# 8BIT_ADD_SUB.net
KiCad netlist of a schematic drawn in EAGLE
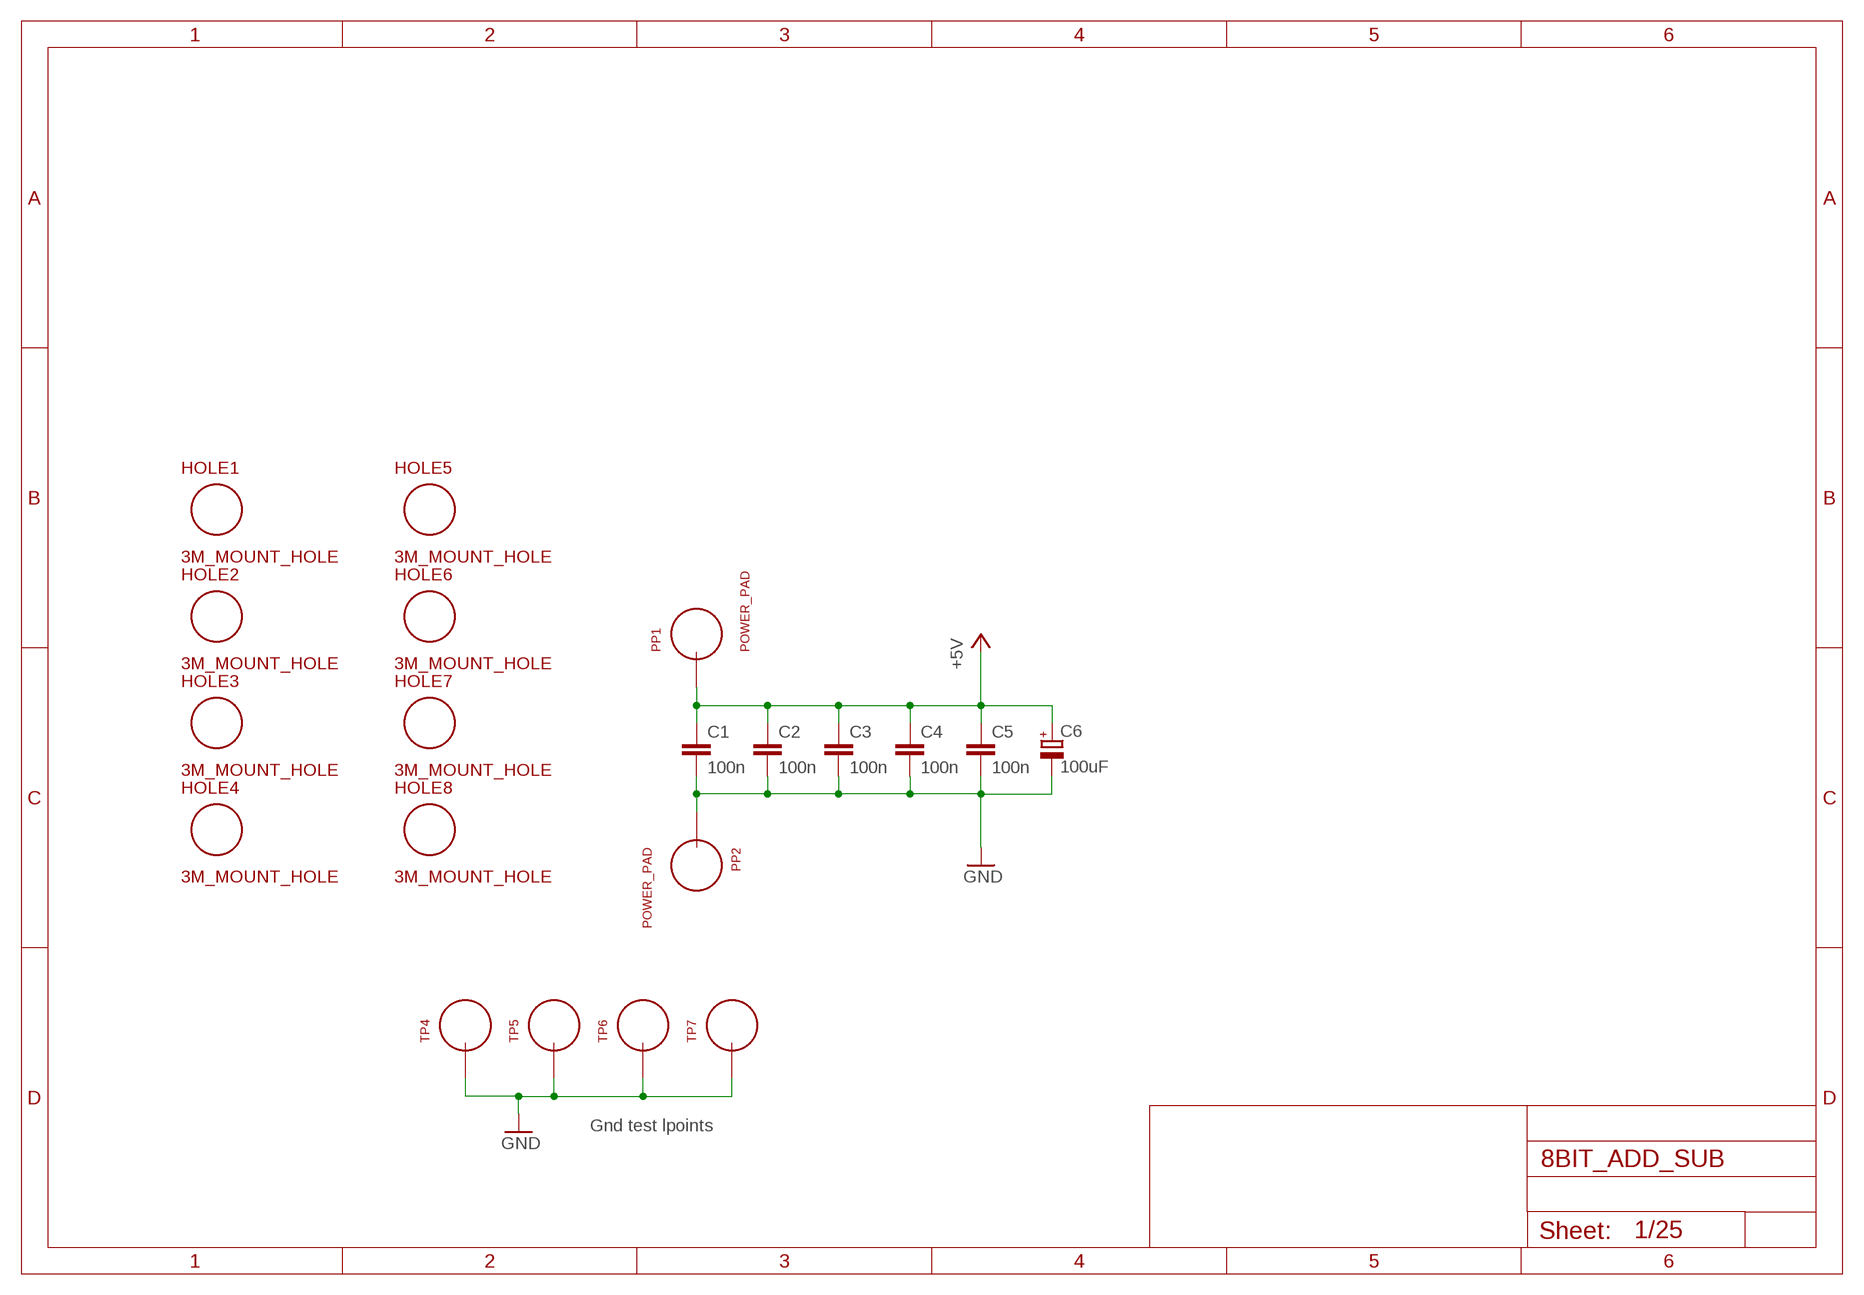
[diagram p0: schematic, sheet 1]
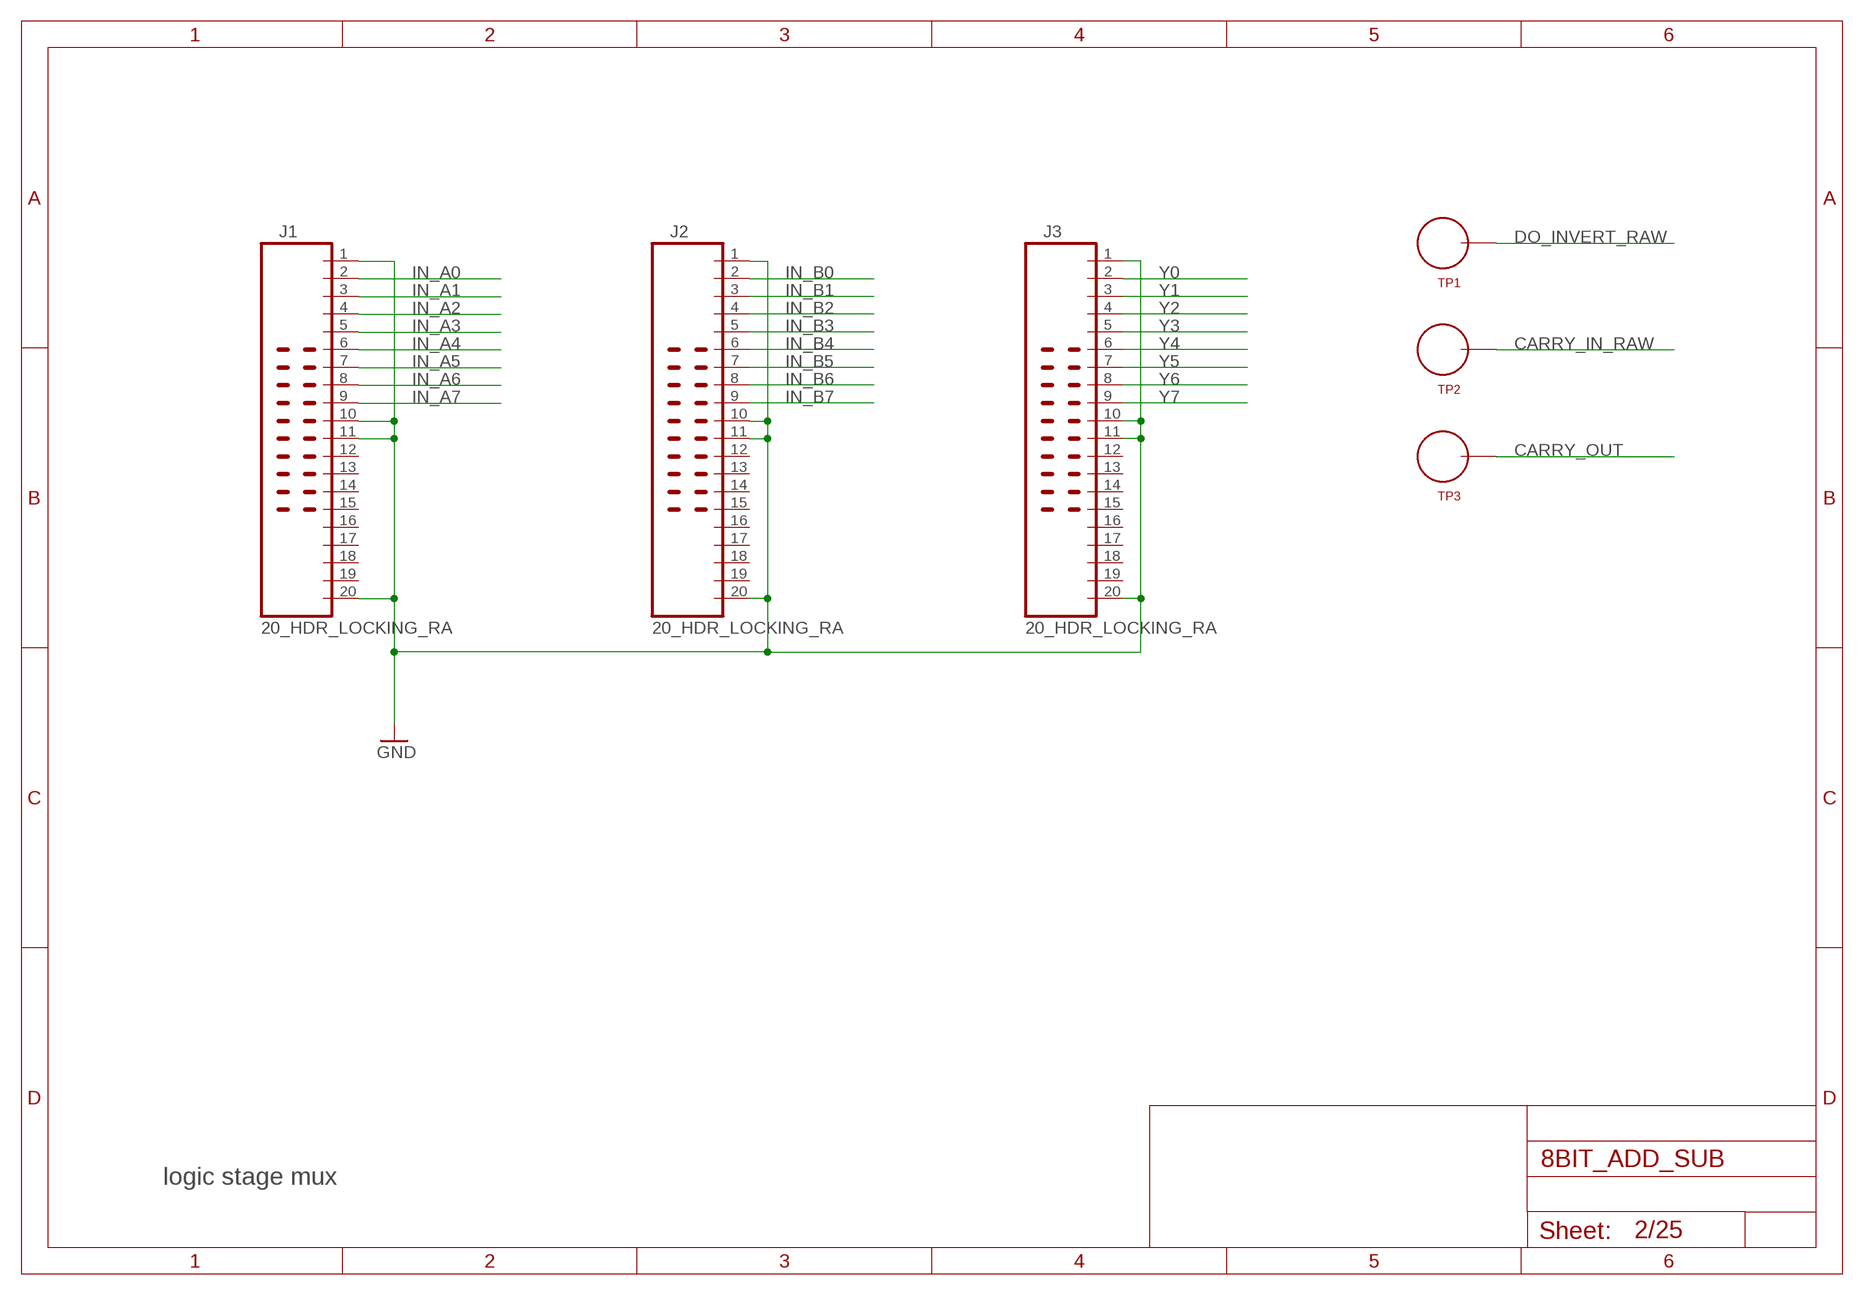
[diagram p1: schematic, sheet 2]
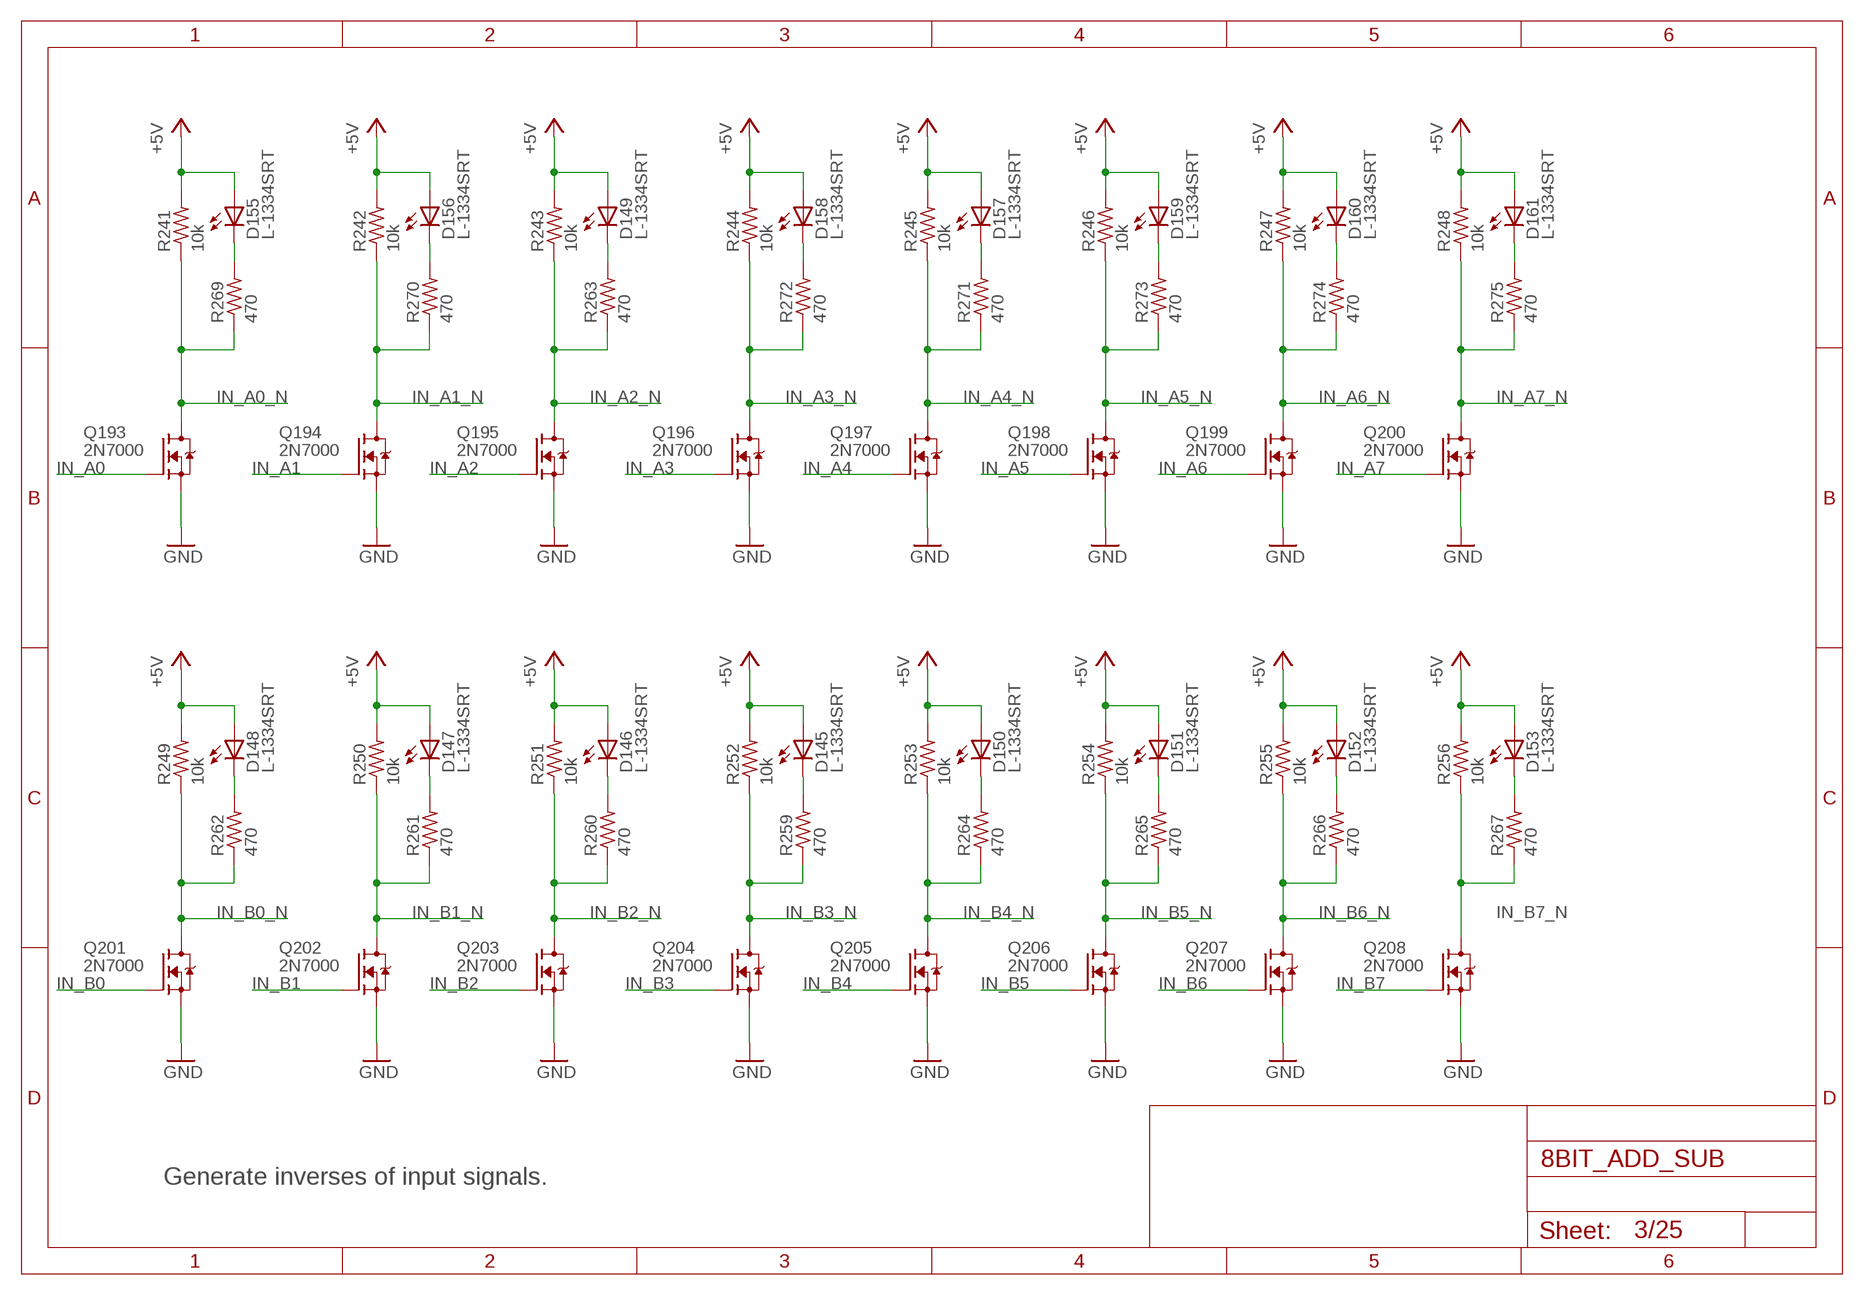
[diagram p2: schematic, sheet 3]
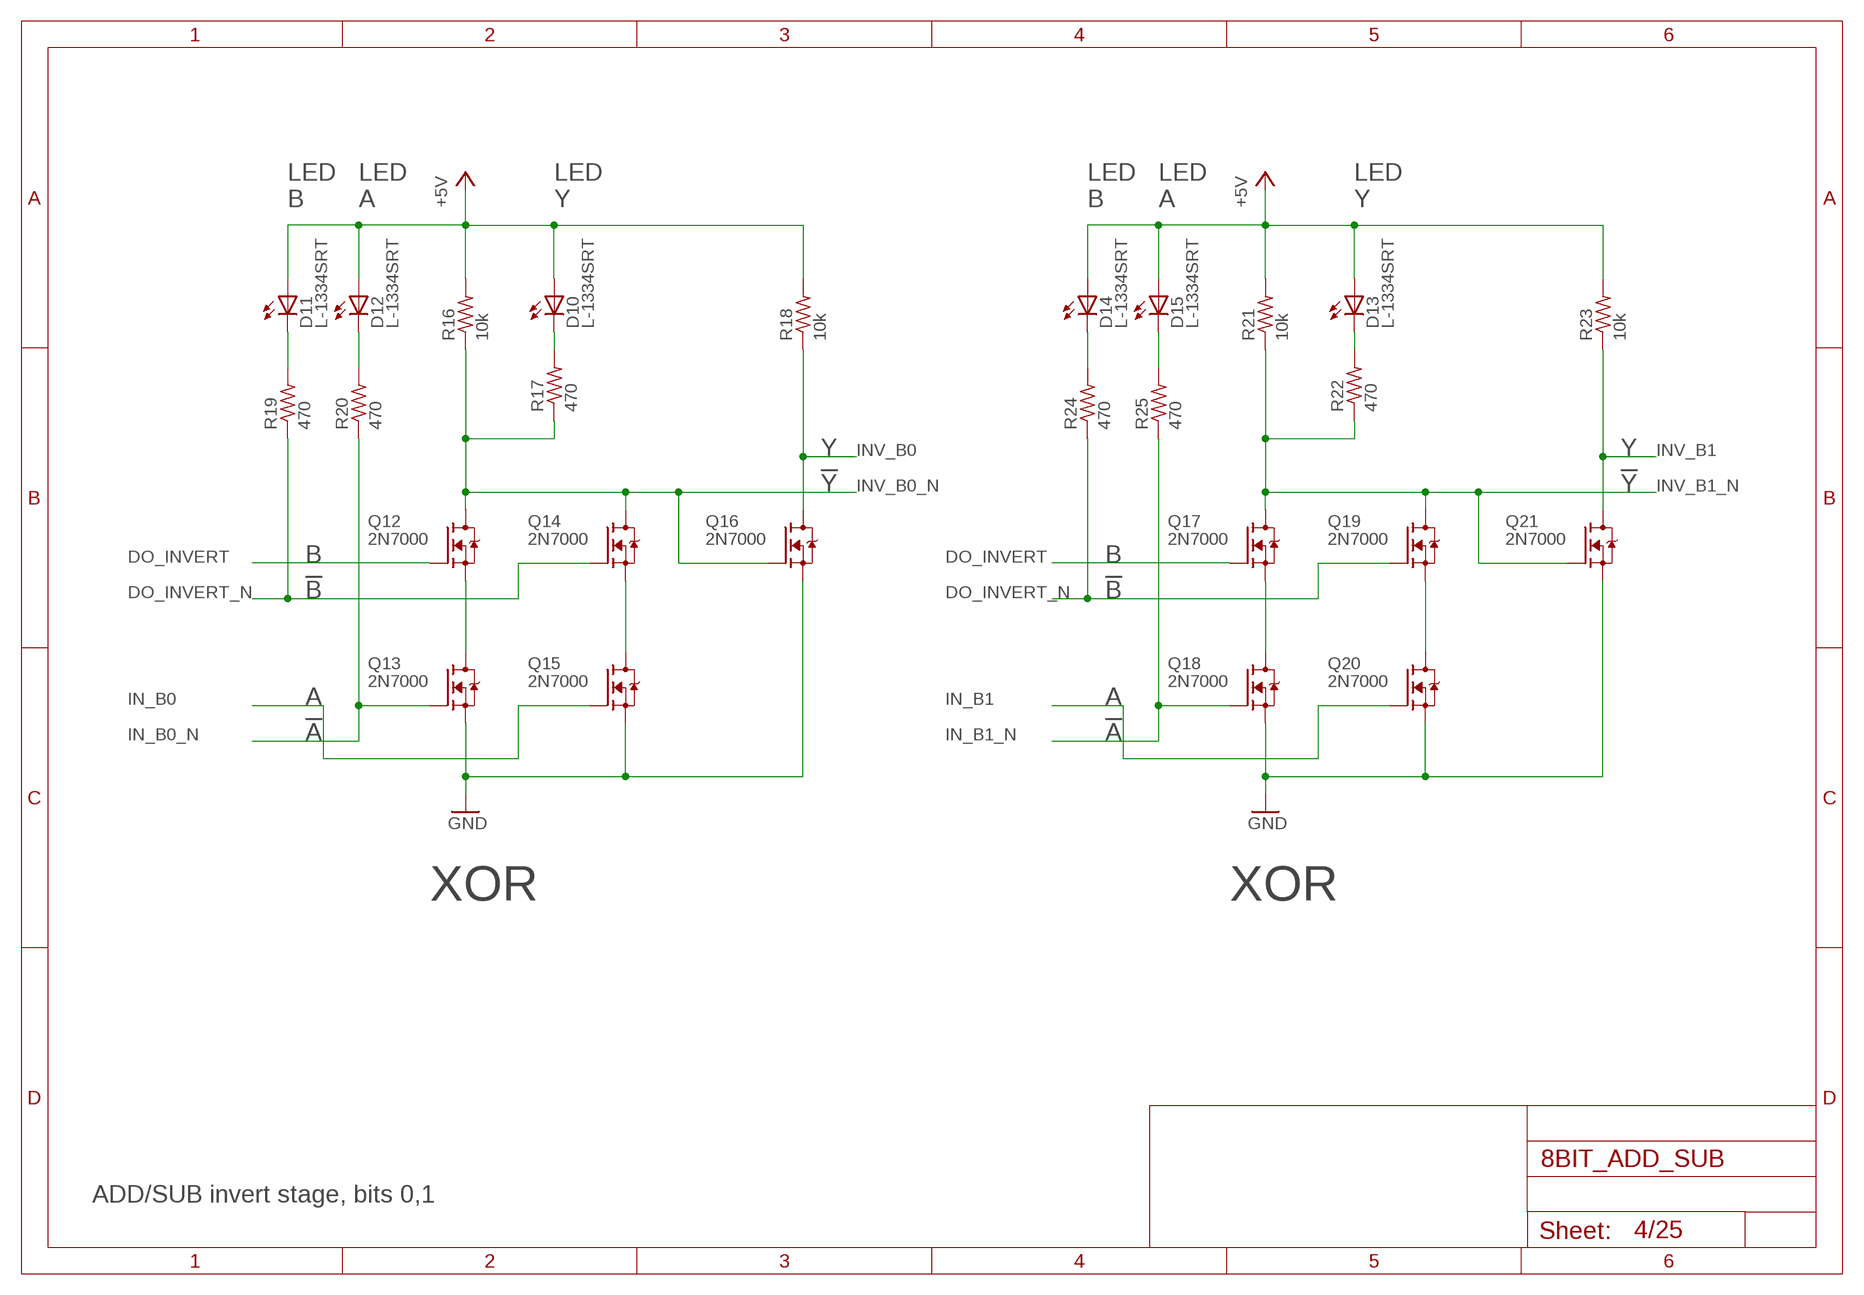
[diagram p3: schematic, sheet 4]
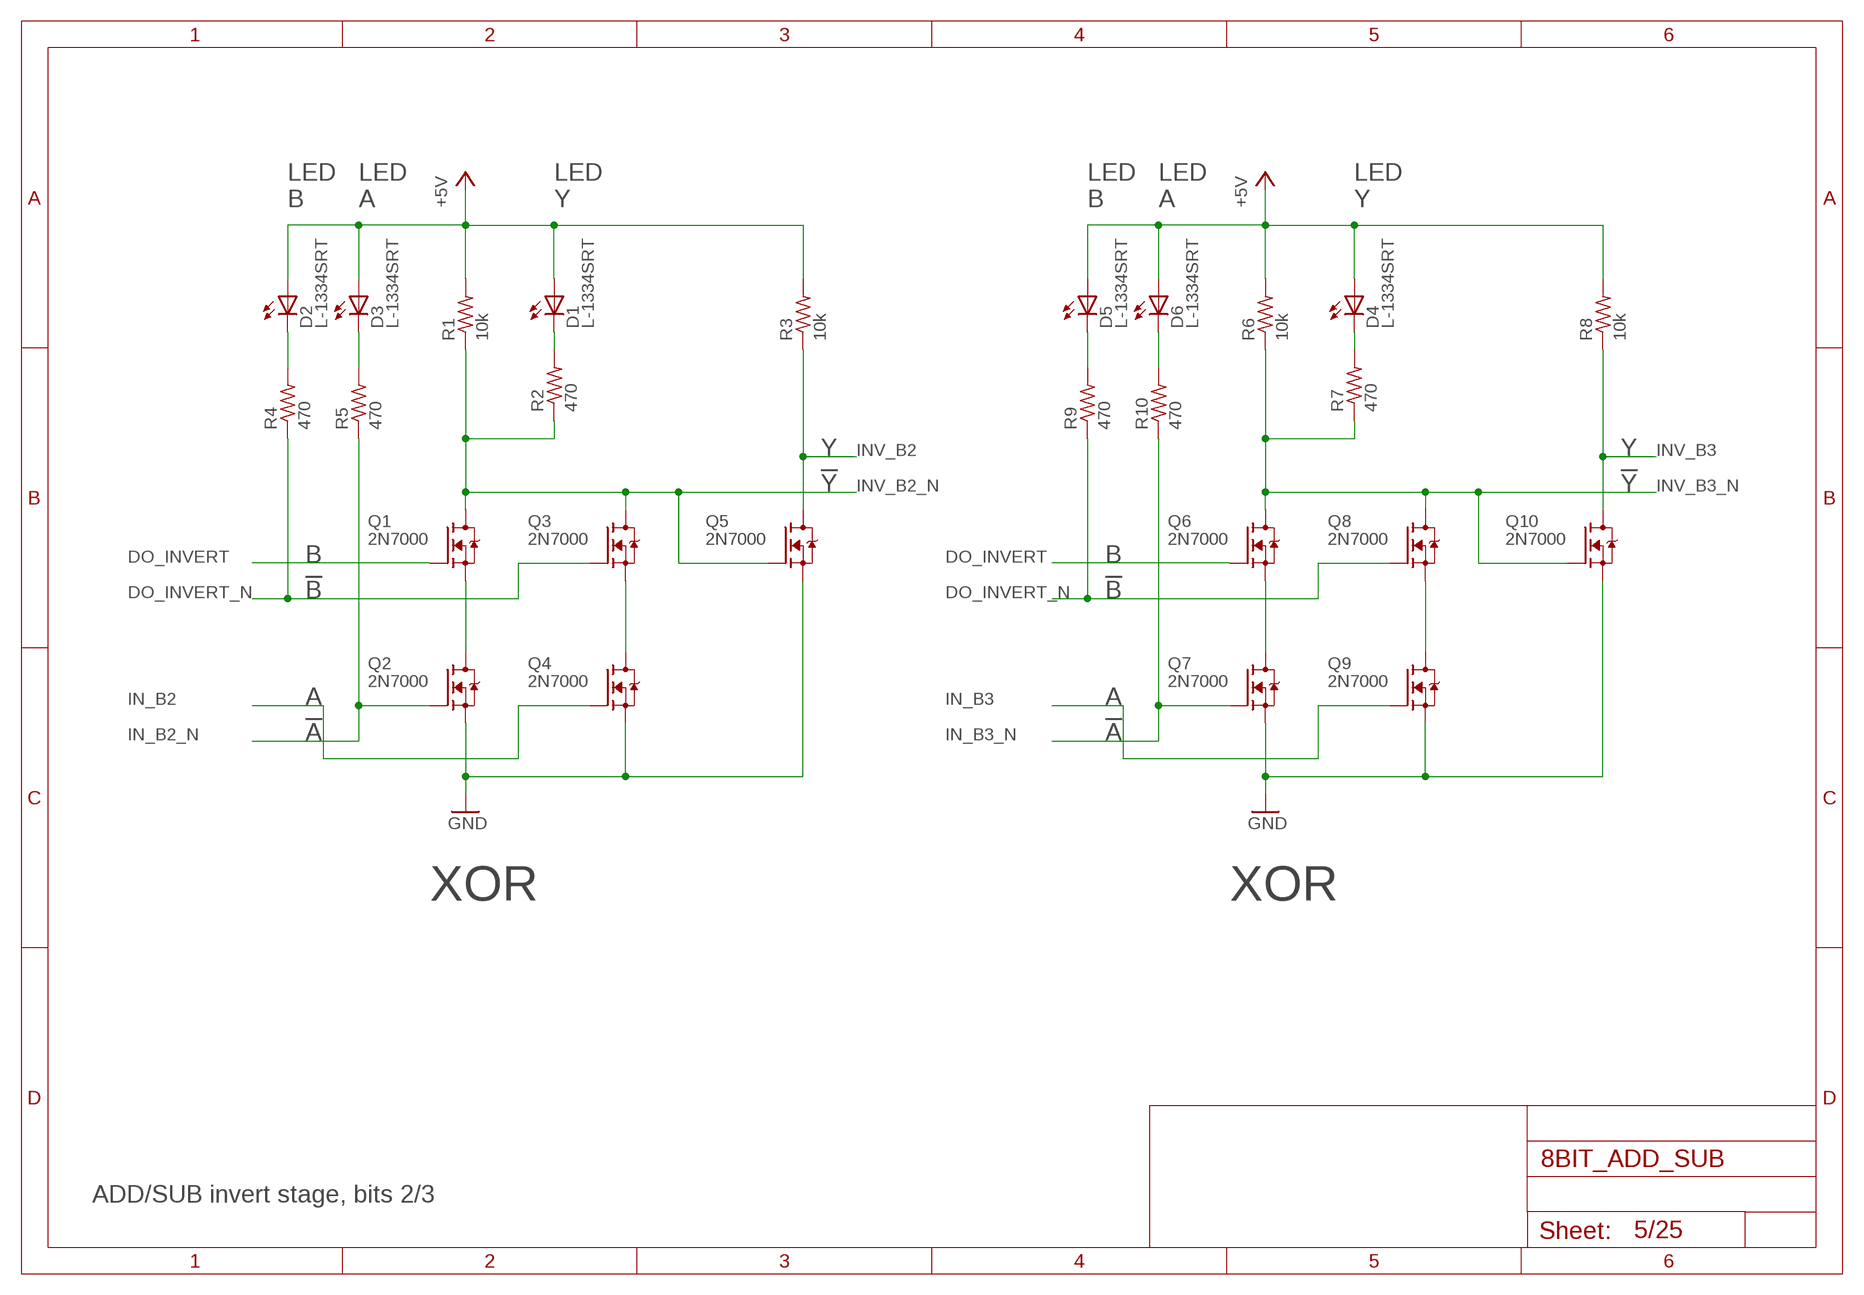
[diagram p4: schematic, sheet 5]
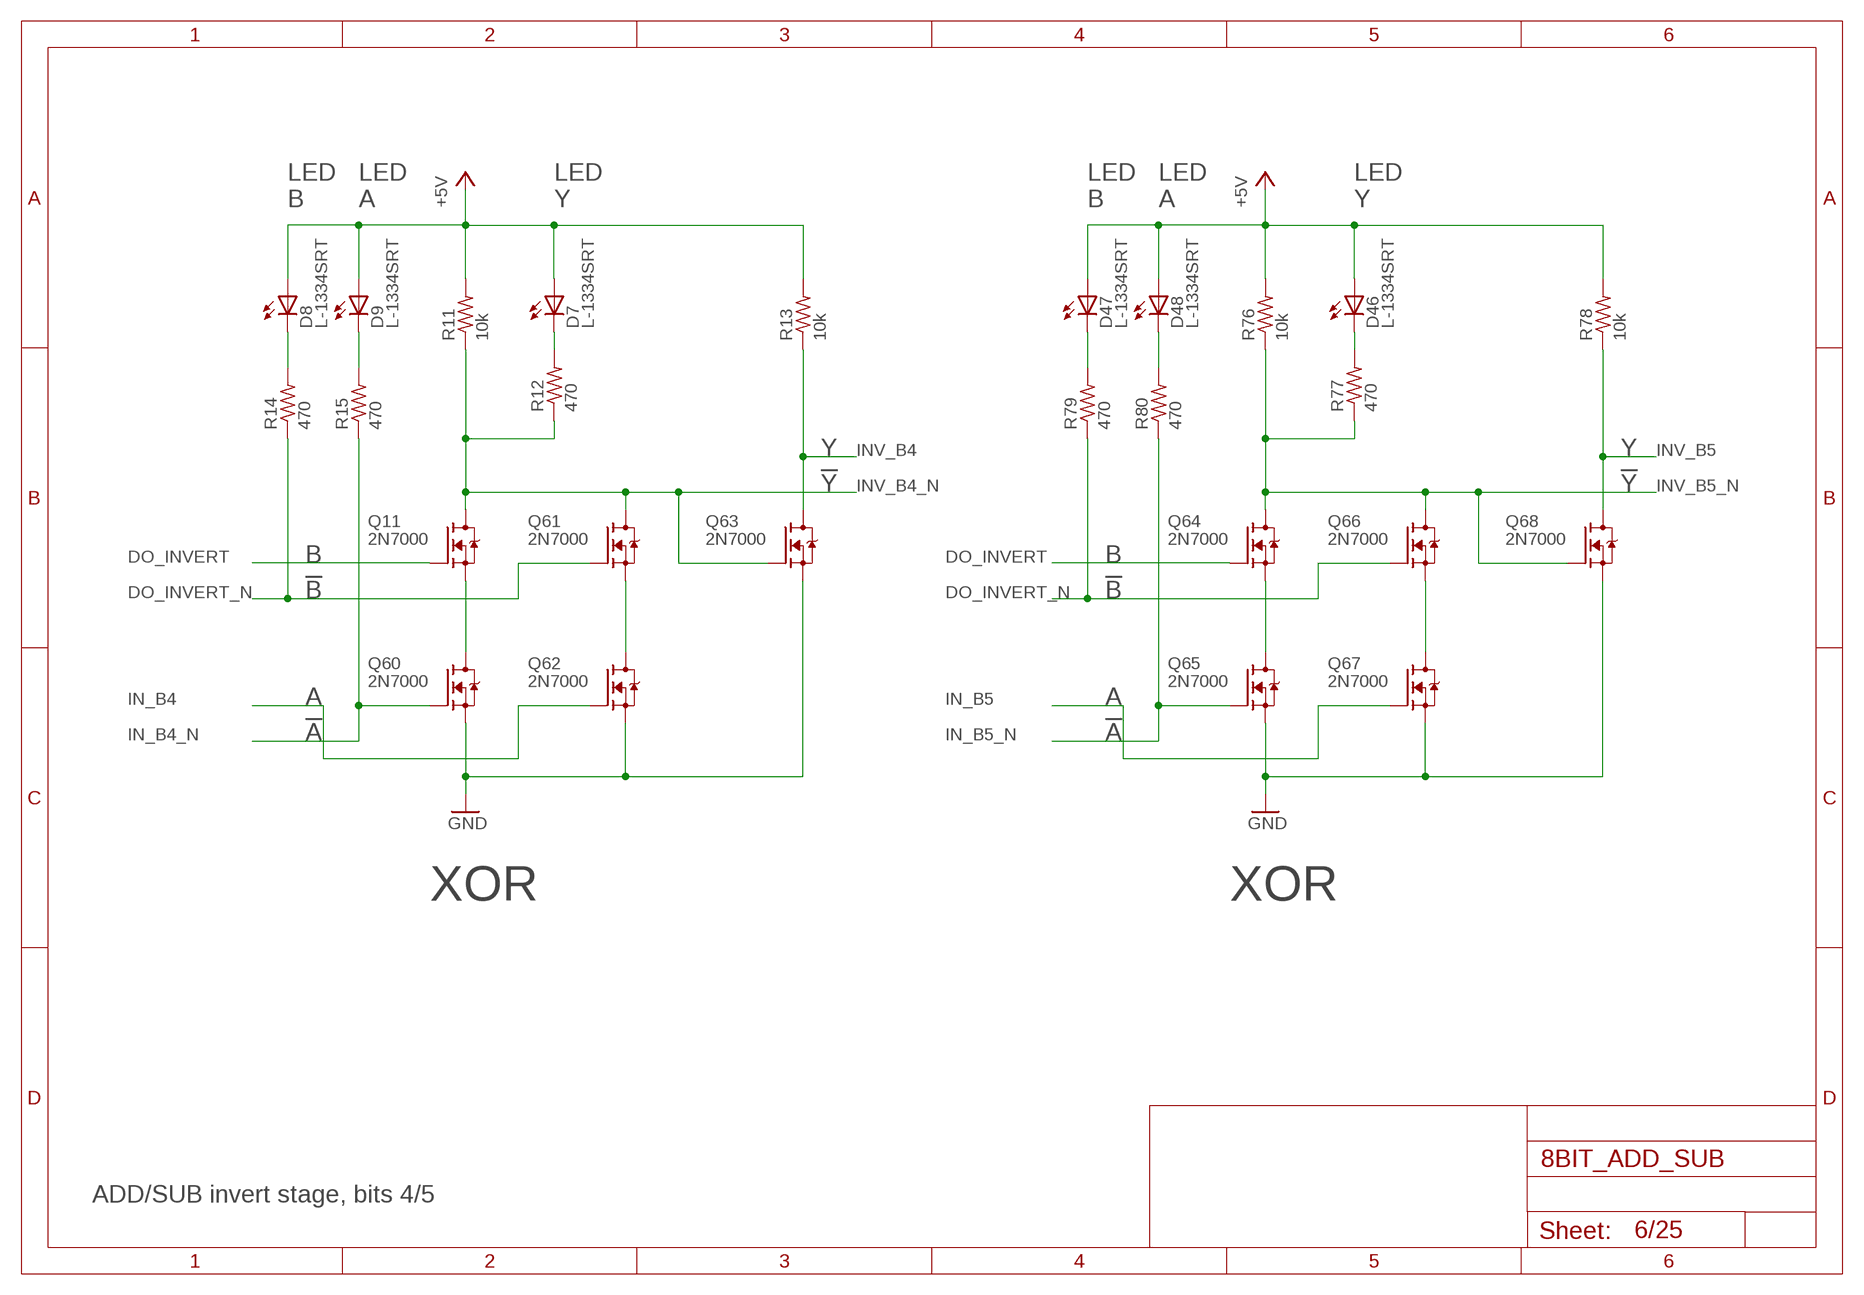
[diagram p5: schematic, sheet 6]
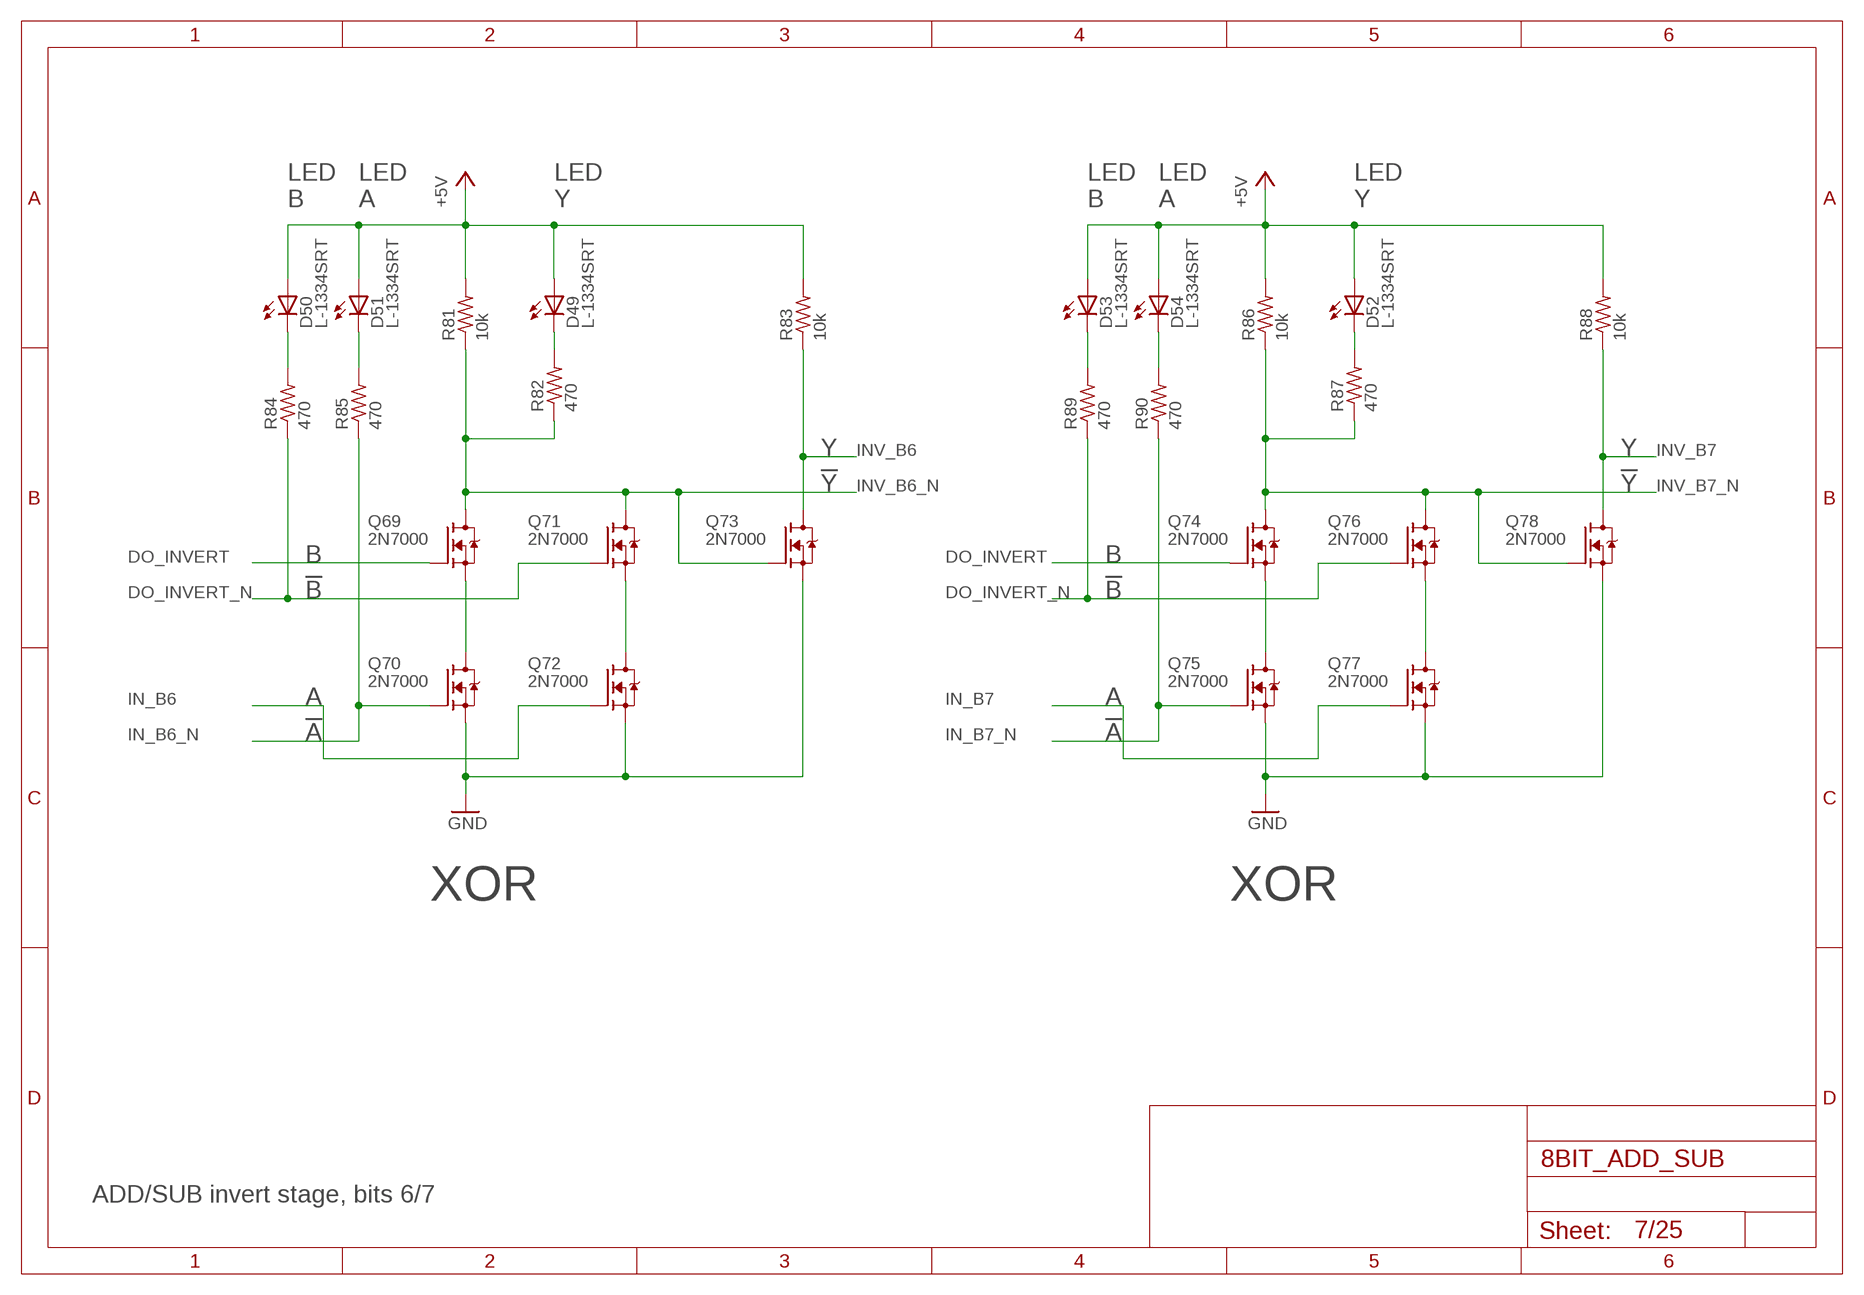
[diagram p6: schematic, sheet 7]
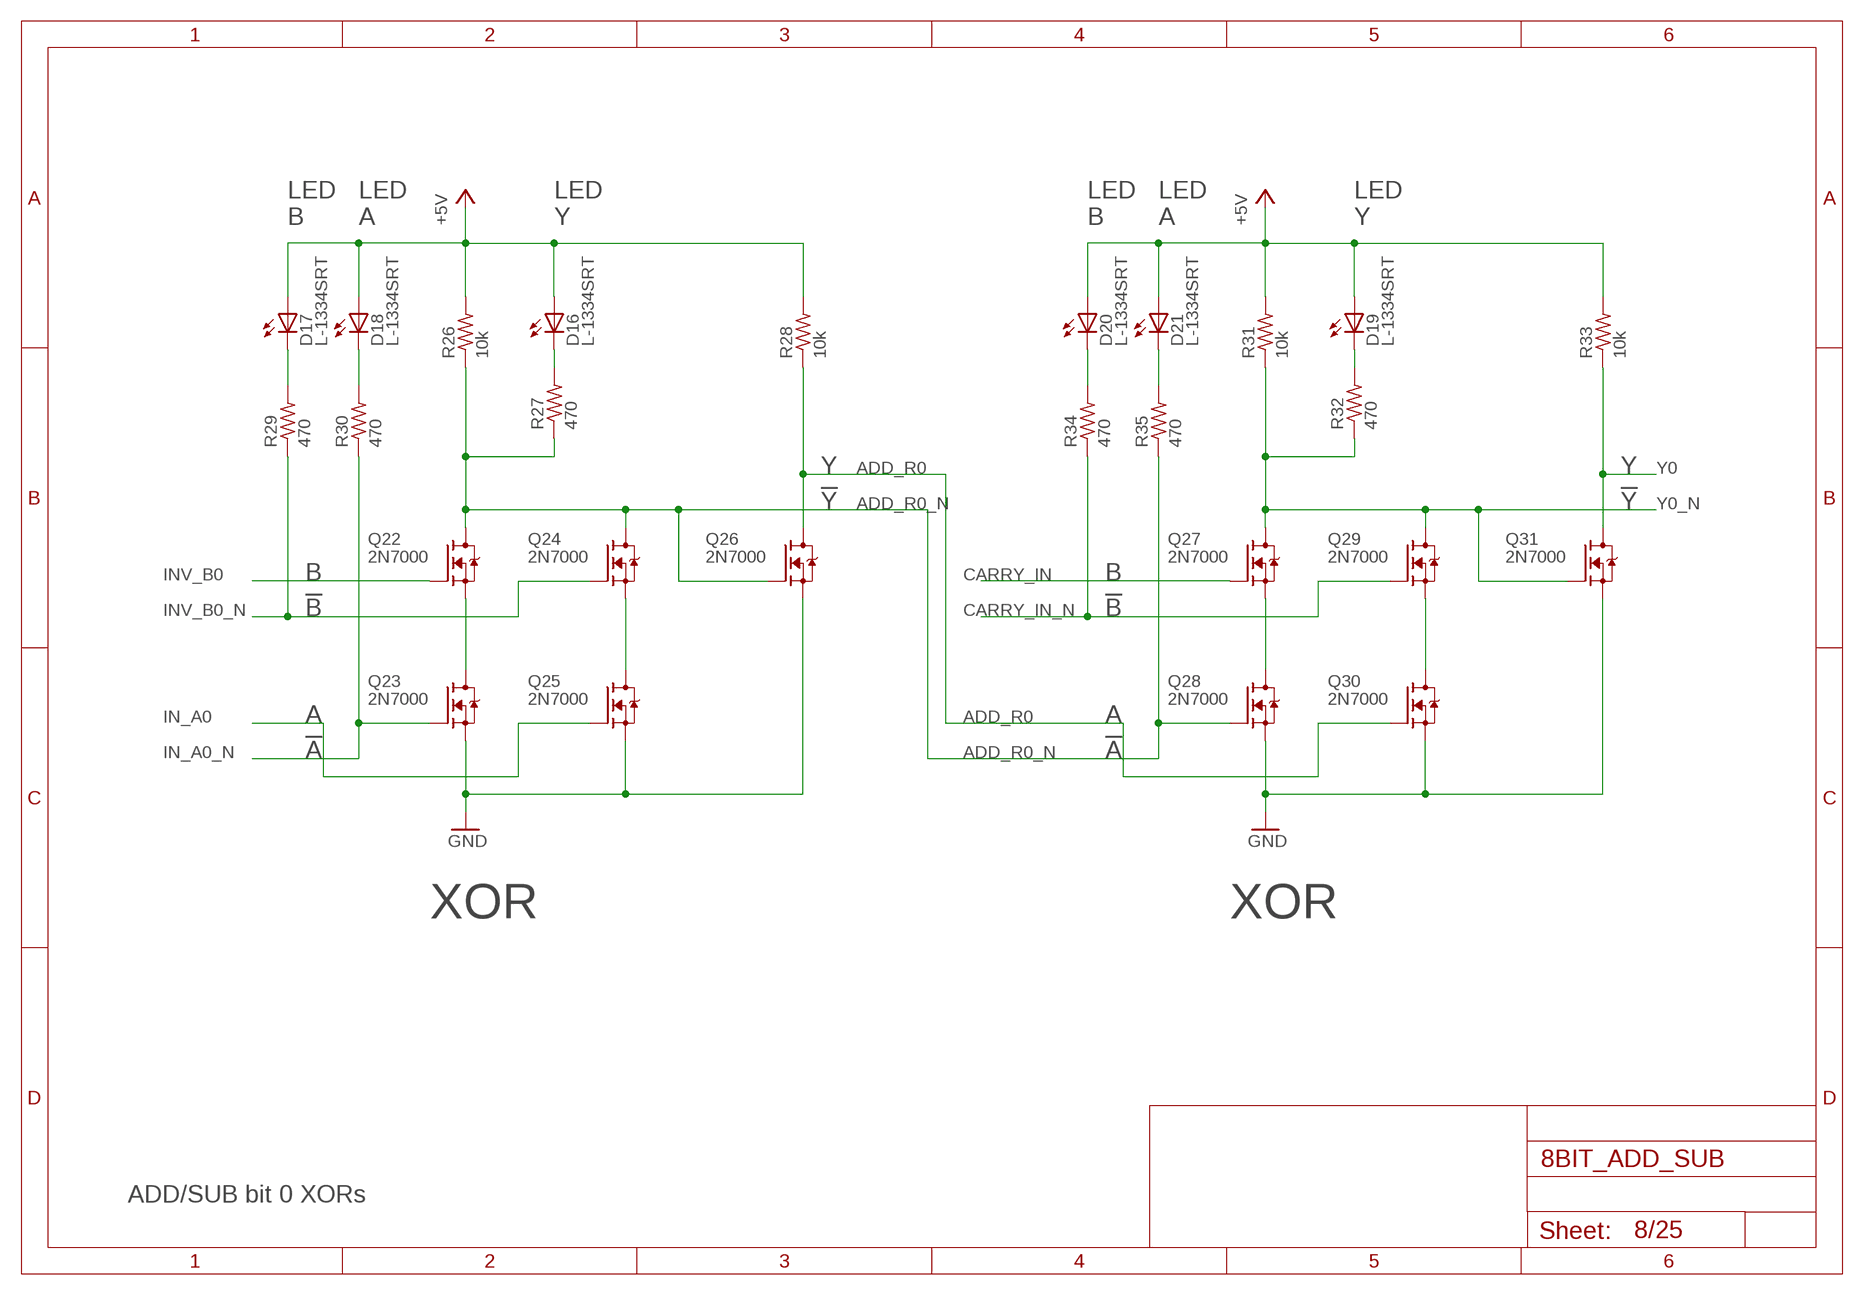
[diagram p7: schematic, sheet 8]
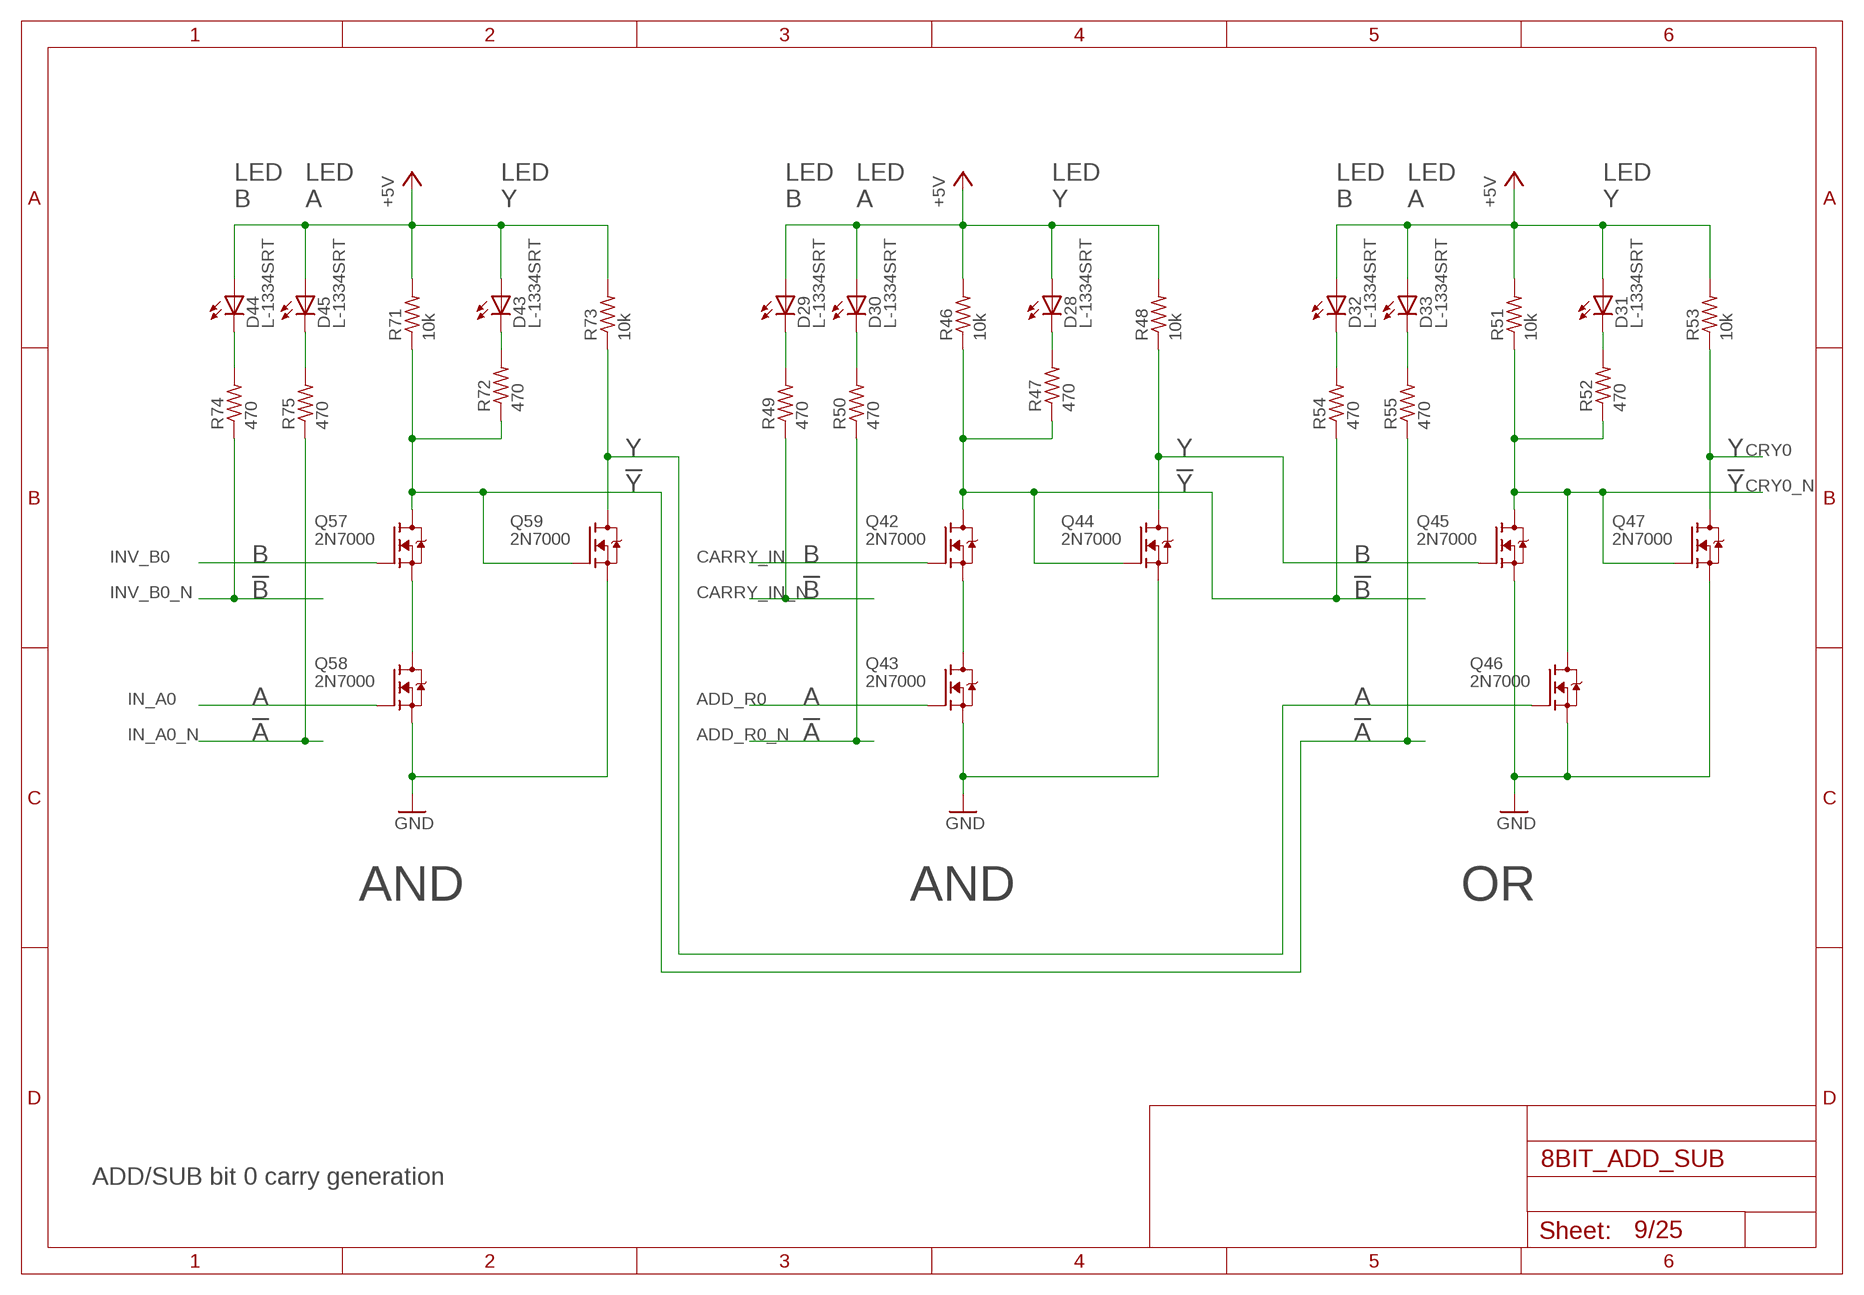
[diagram p8: schematic, sheet 9]
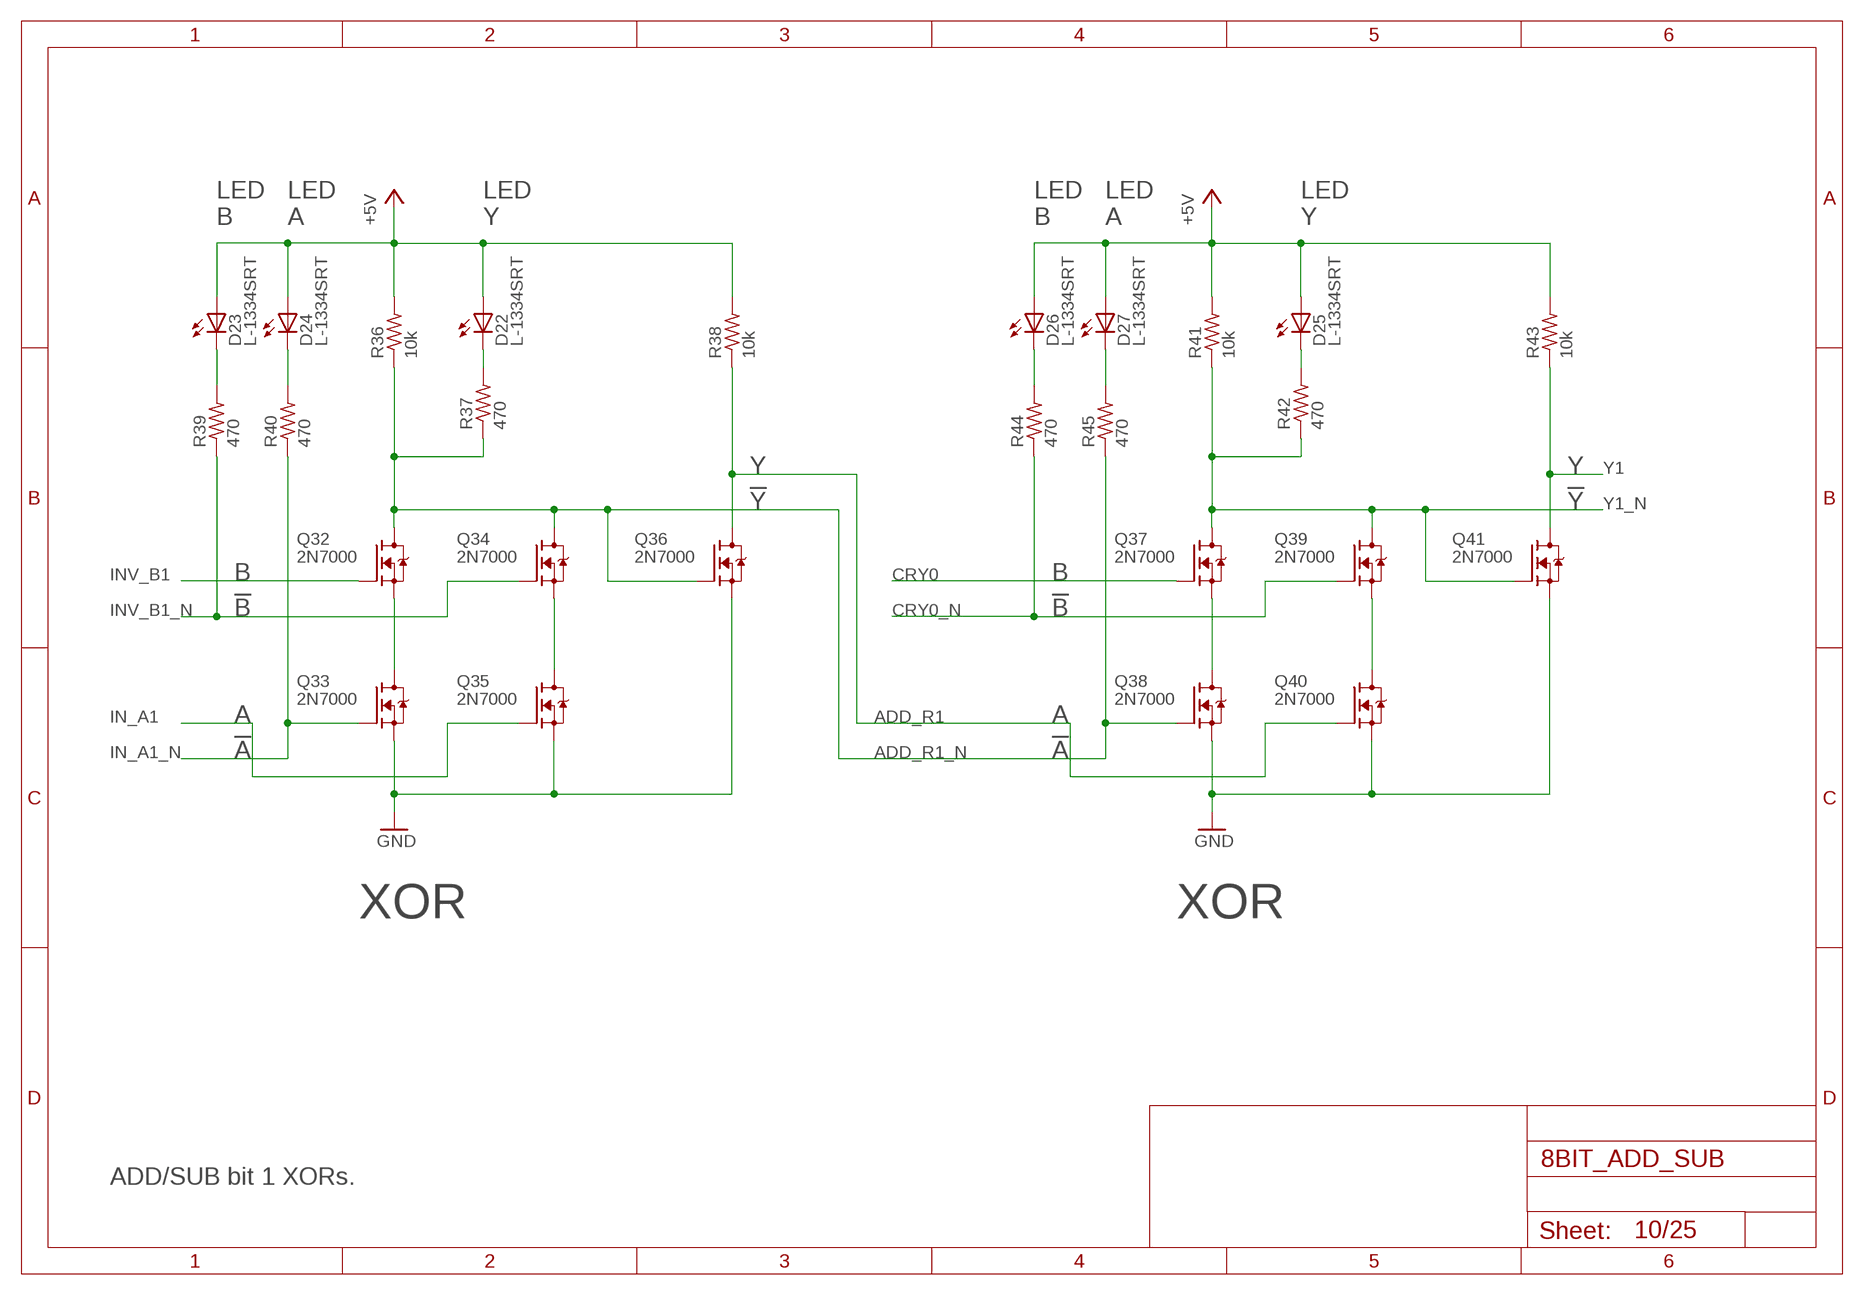
[diagram p9: schematic, sheet 10]
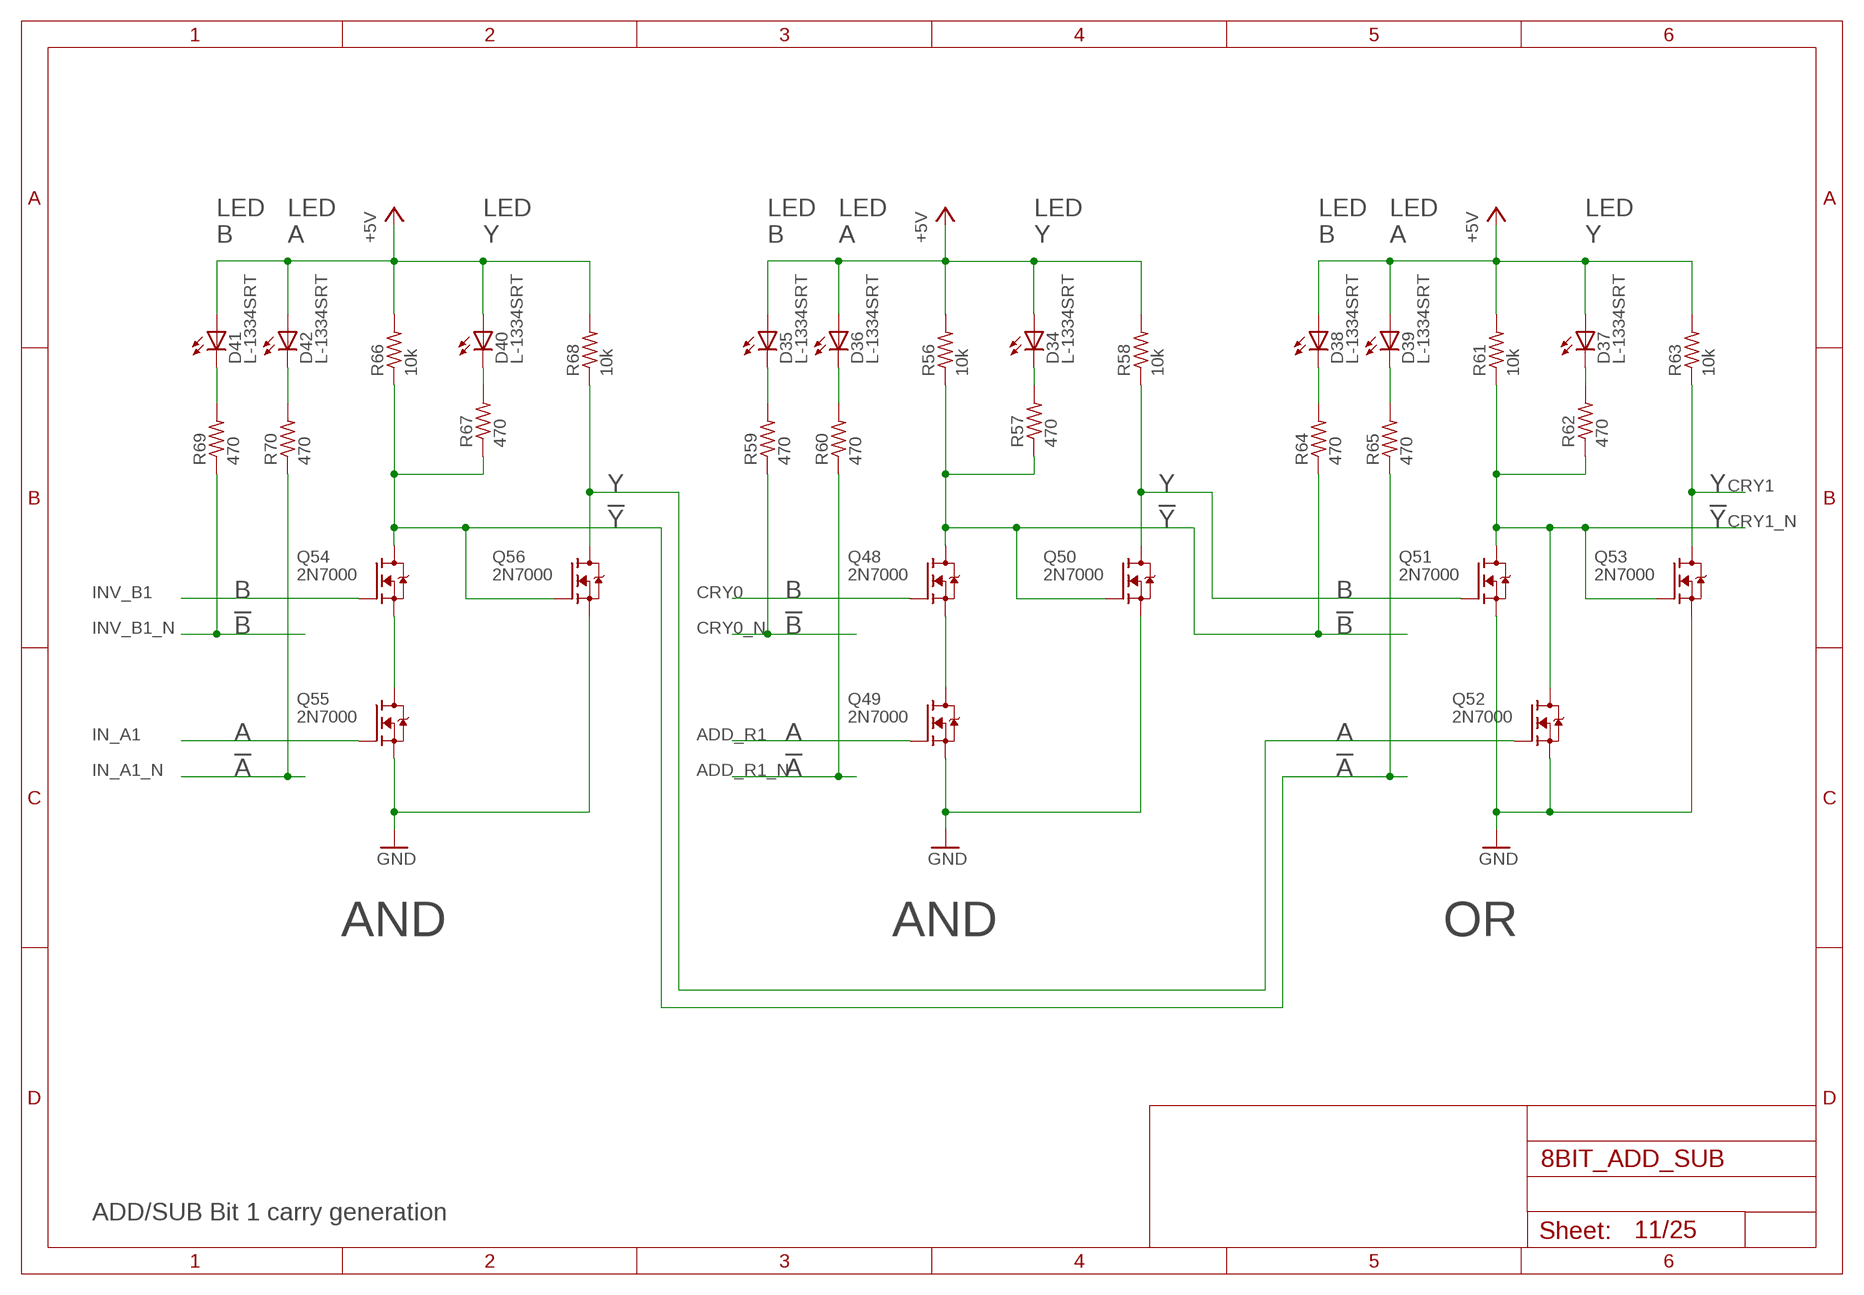
[diagram p10: schematic, sheet 11]
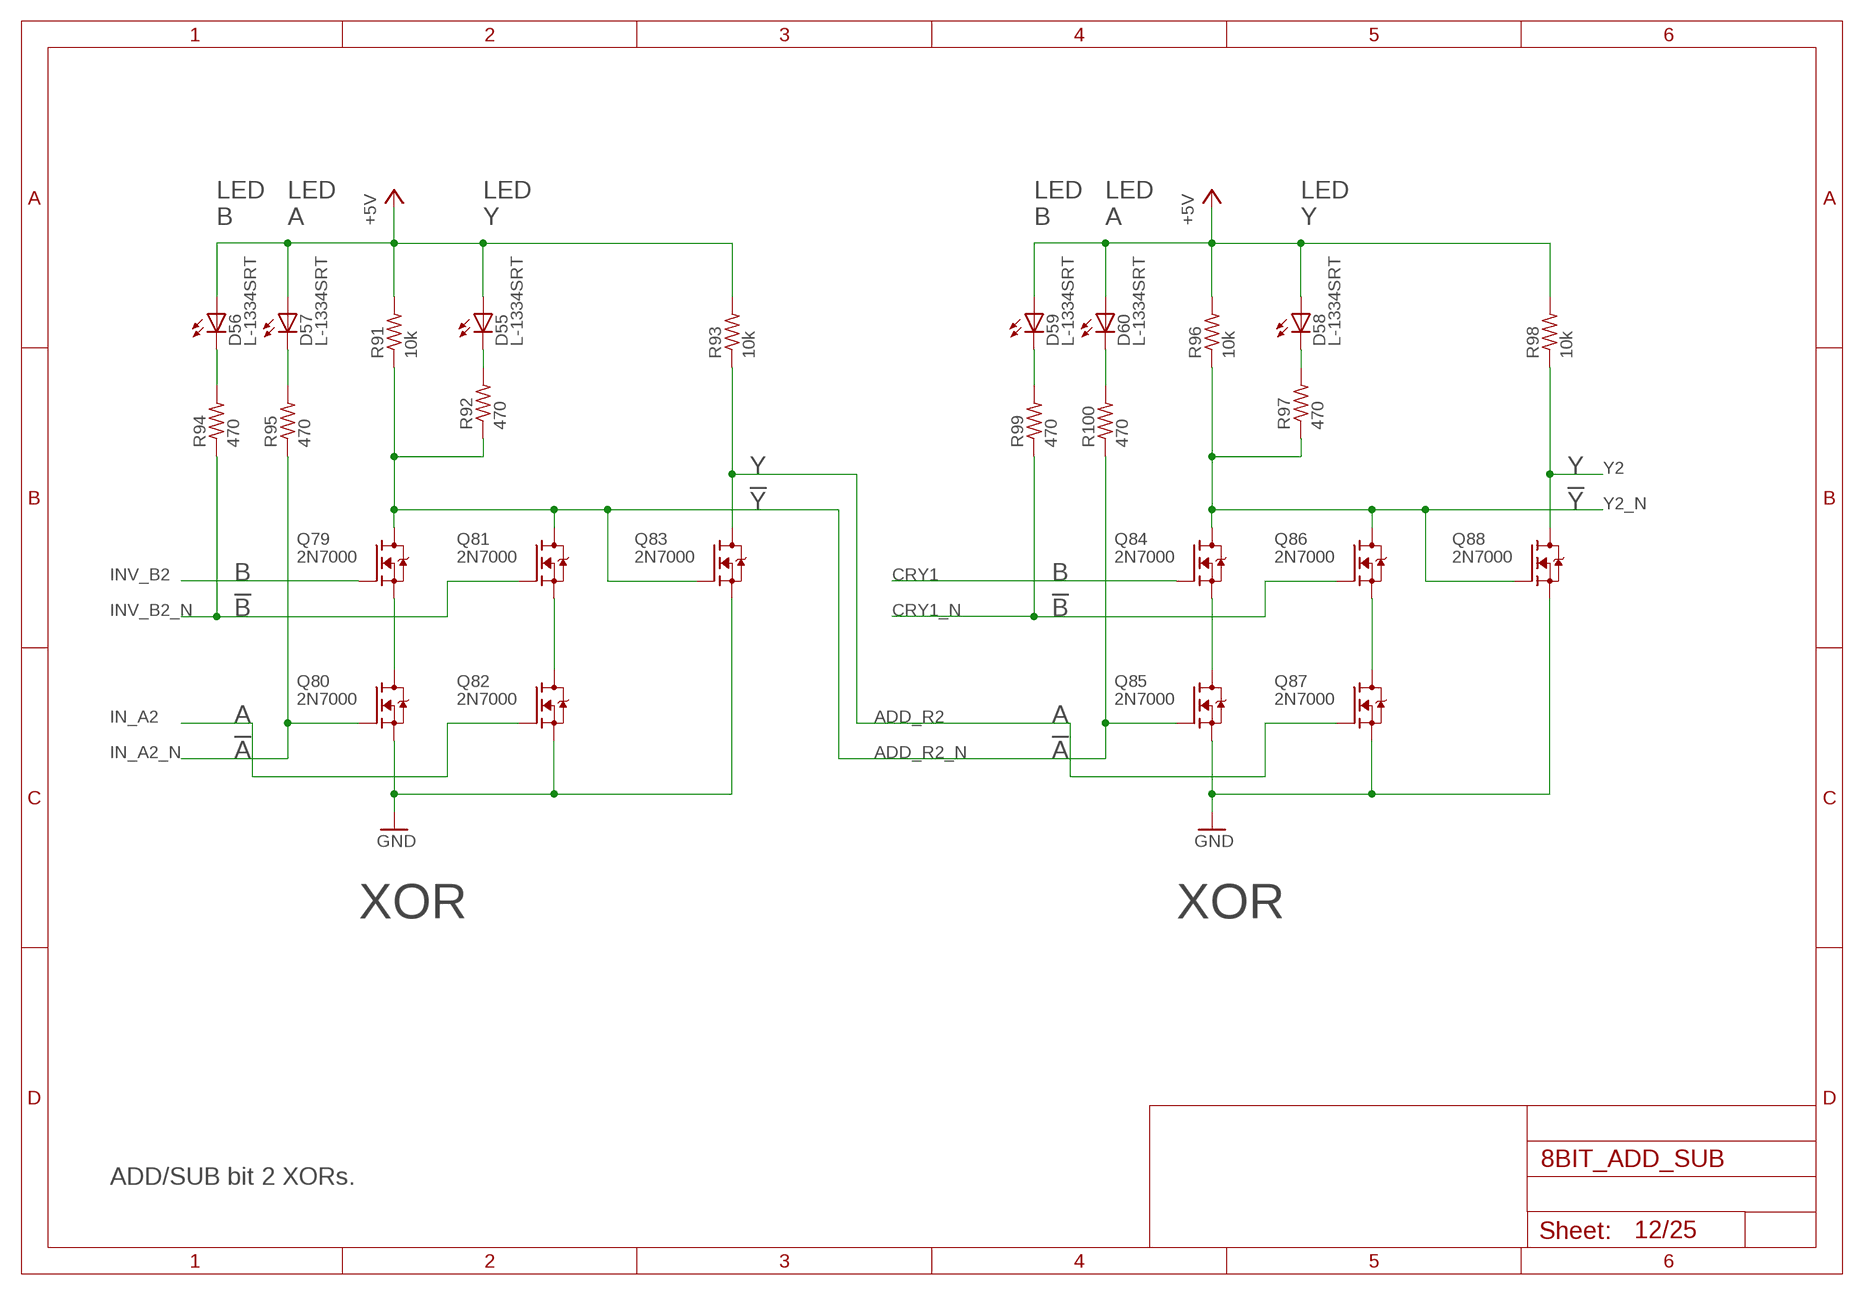
[diagram p11: schematic, sheet 12]
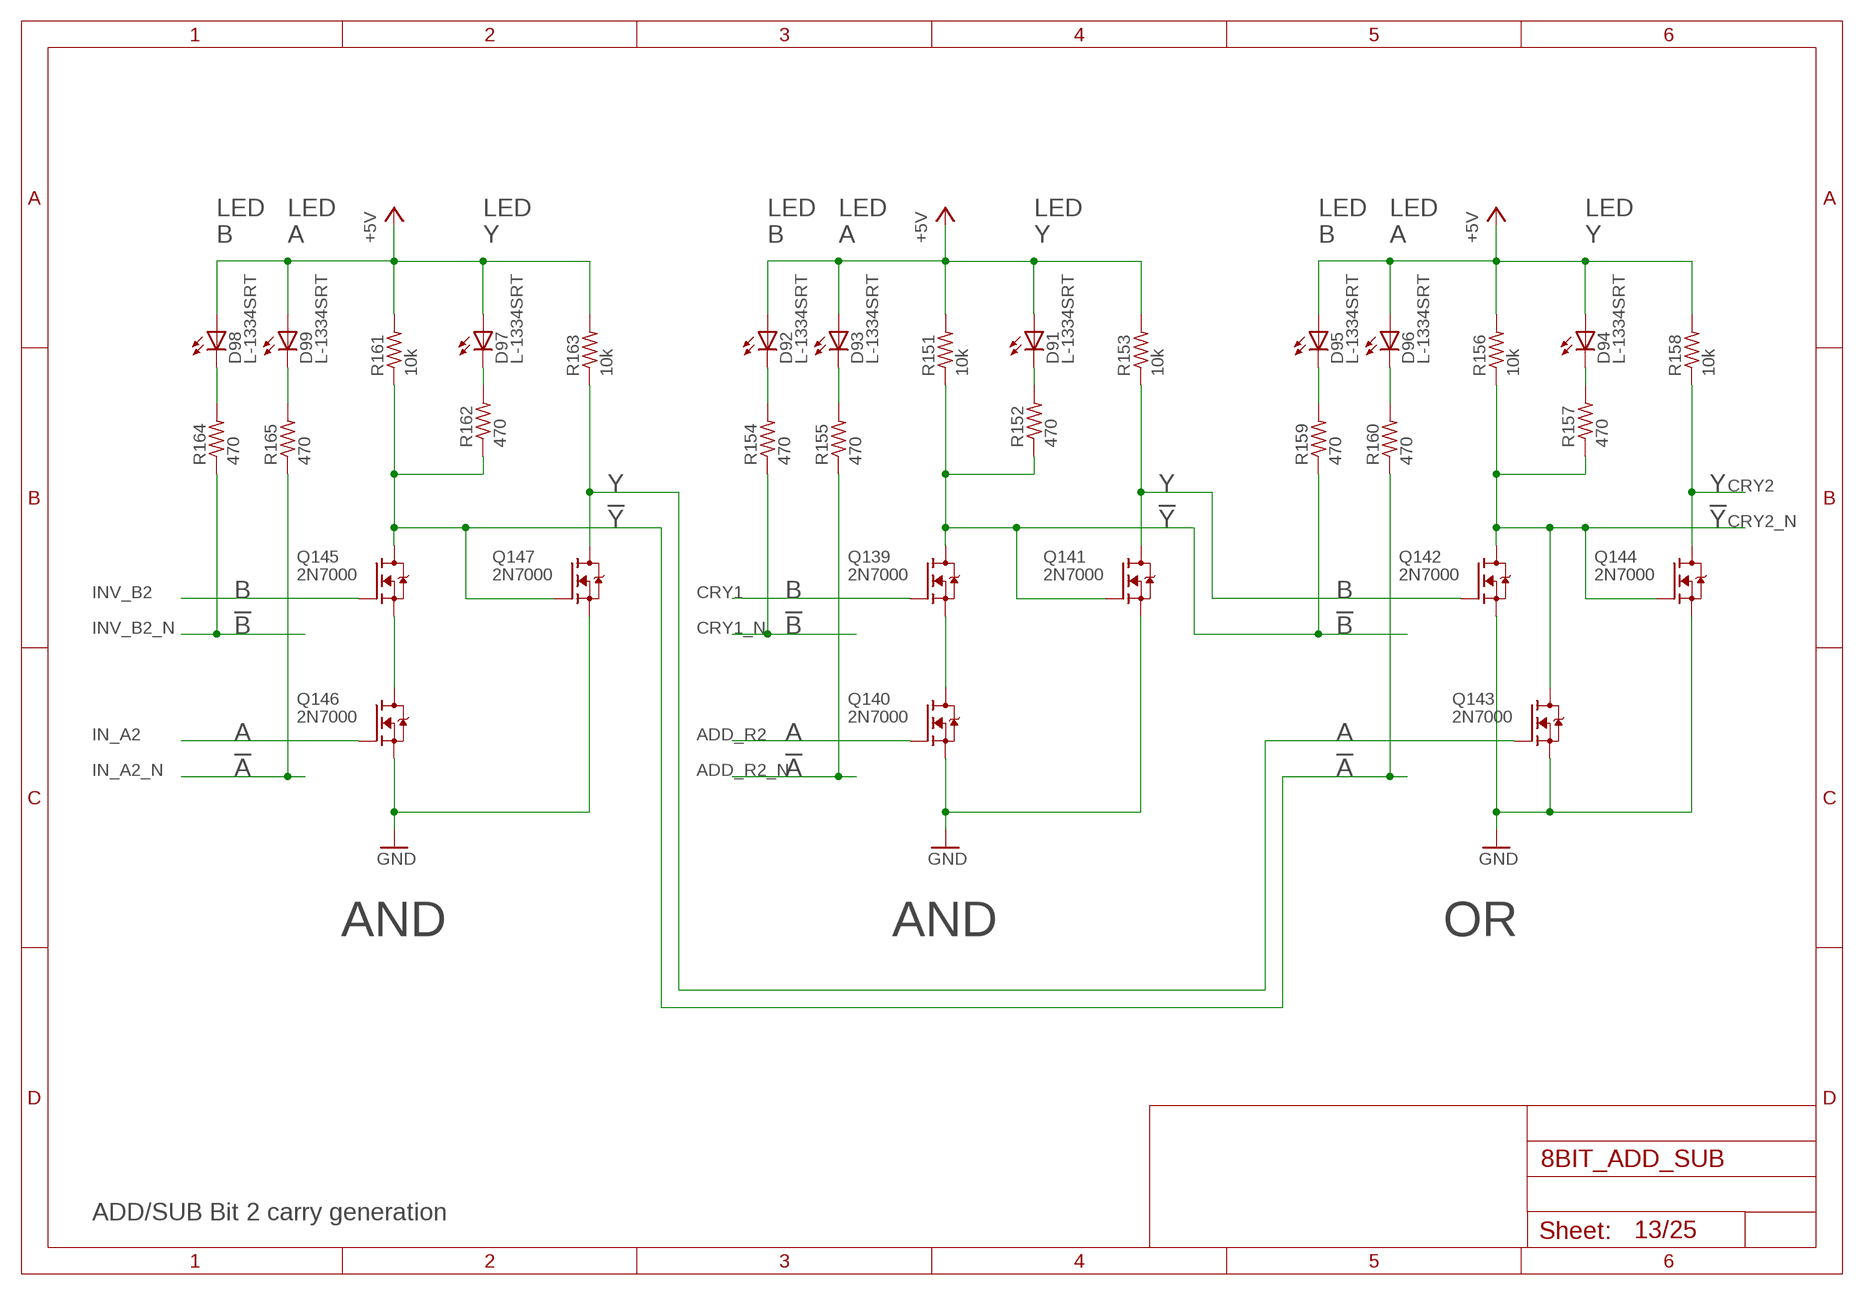
[diagram p12: schematic, sheet 13]
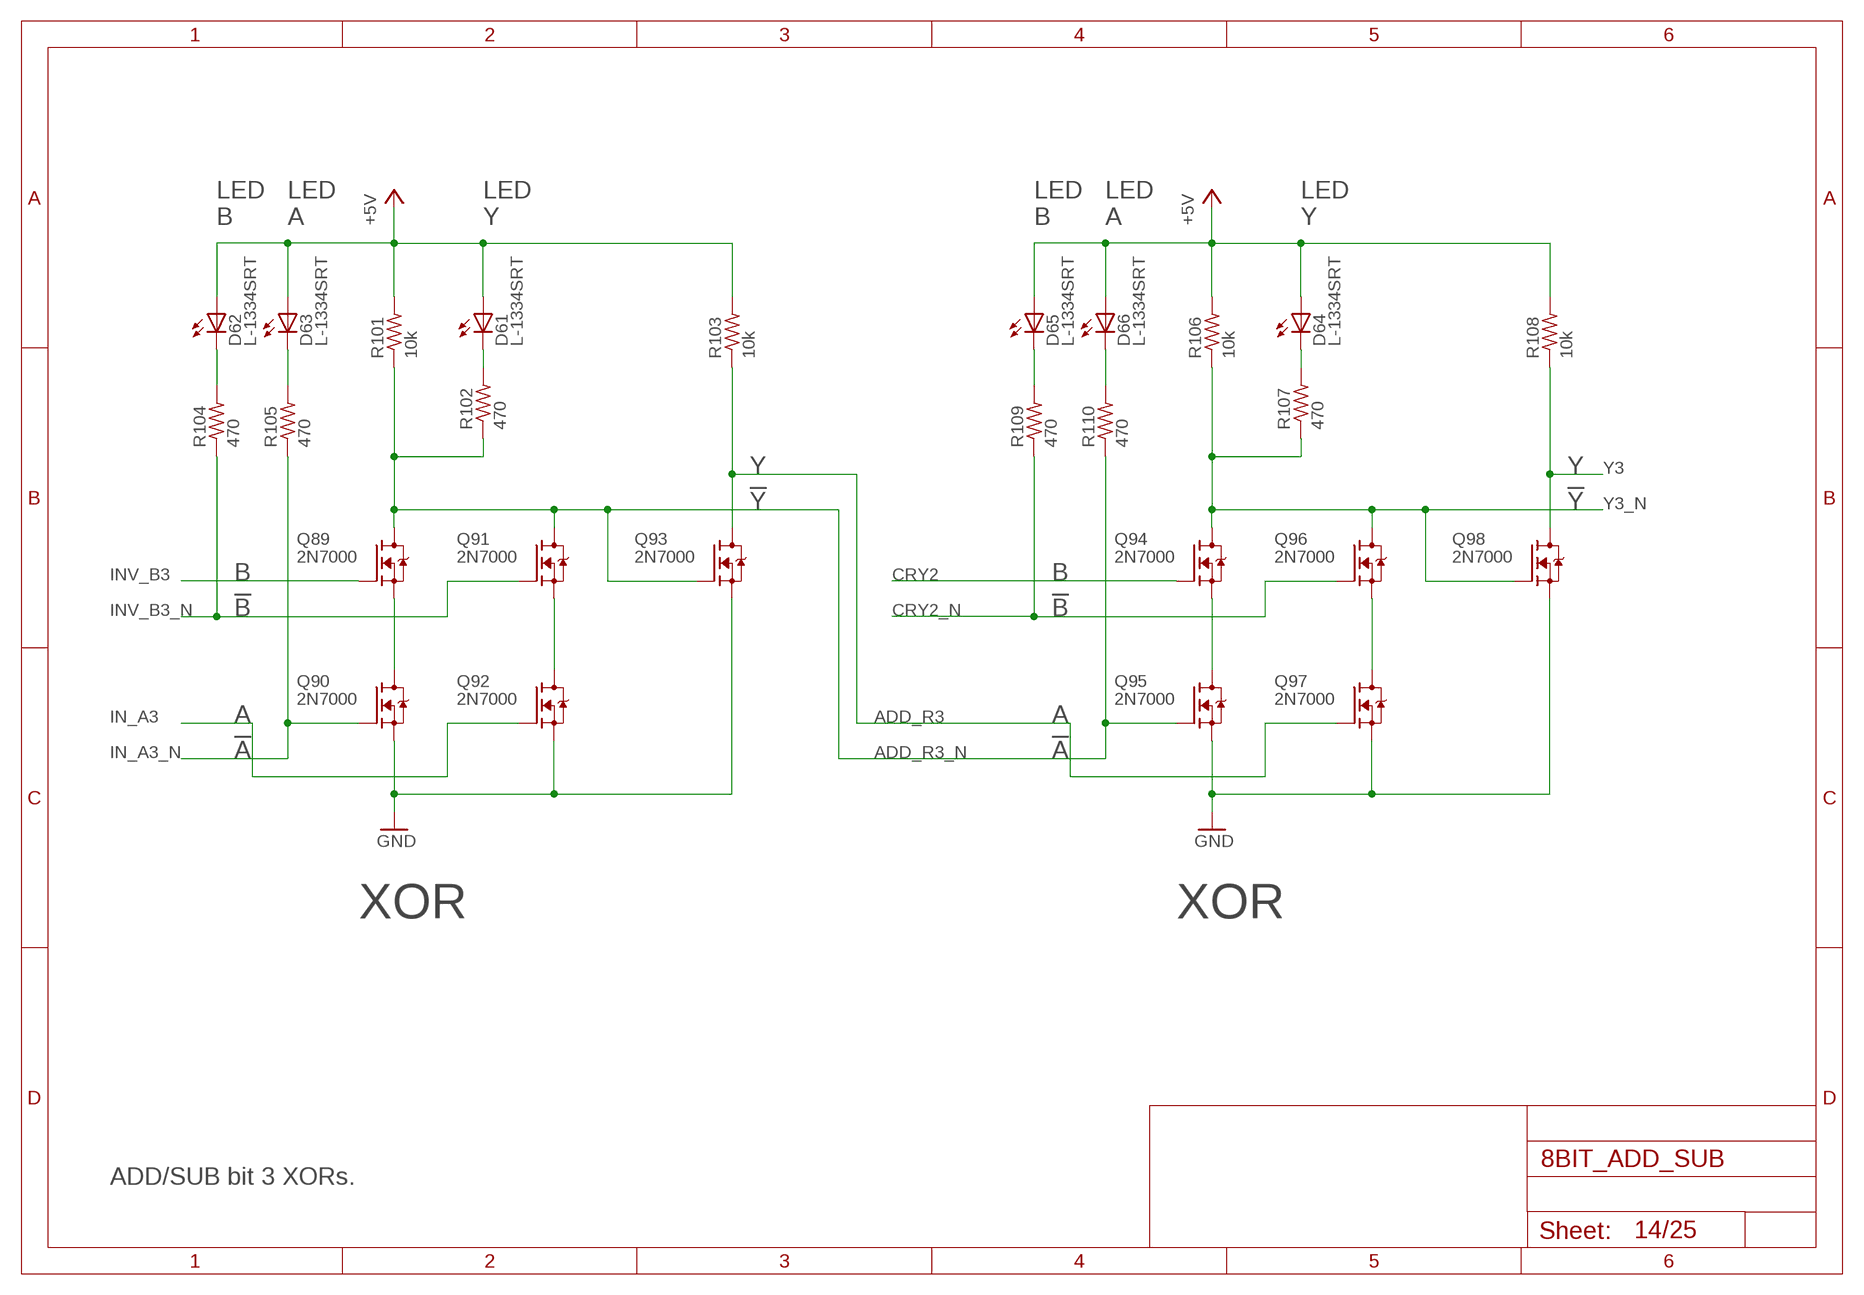
[diagram p13: schematic, sheet 14]
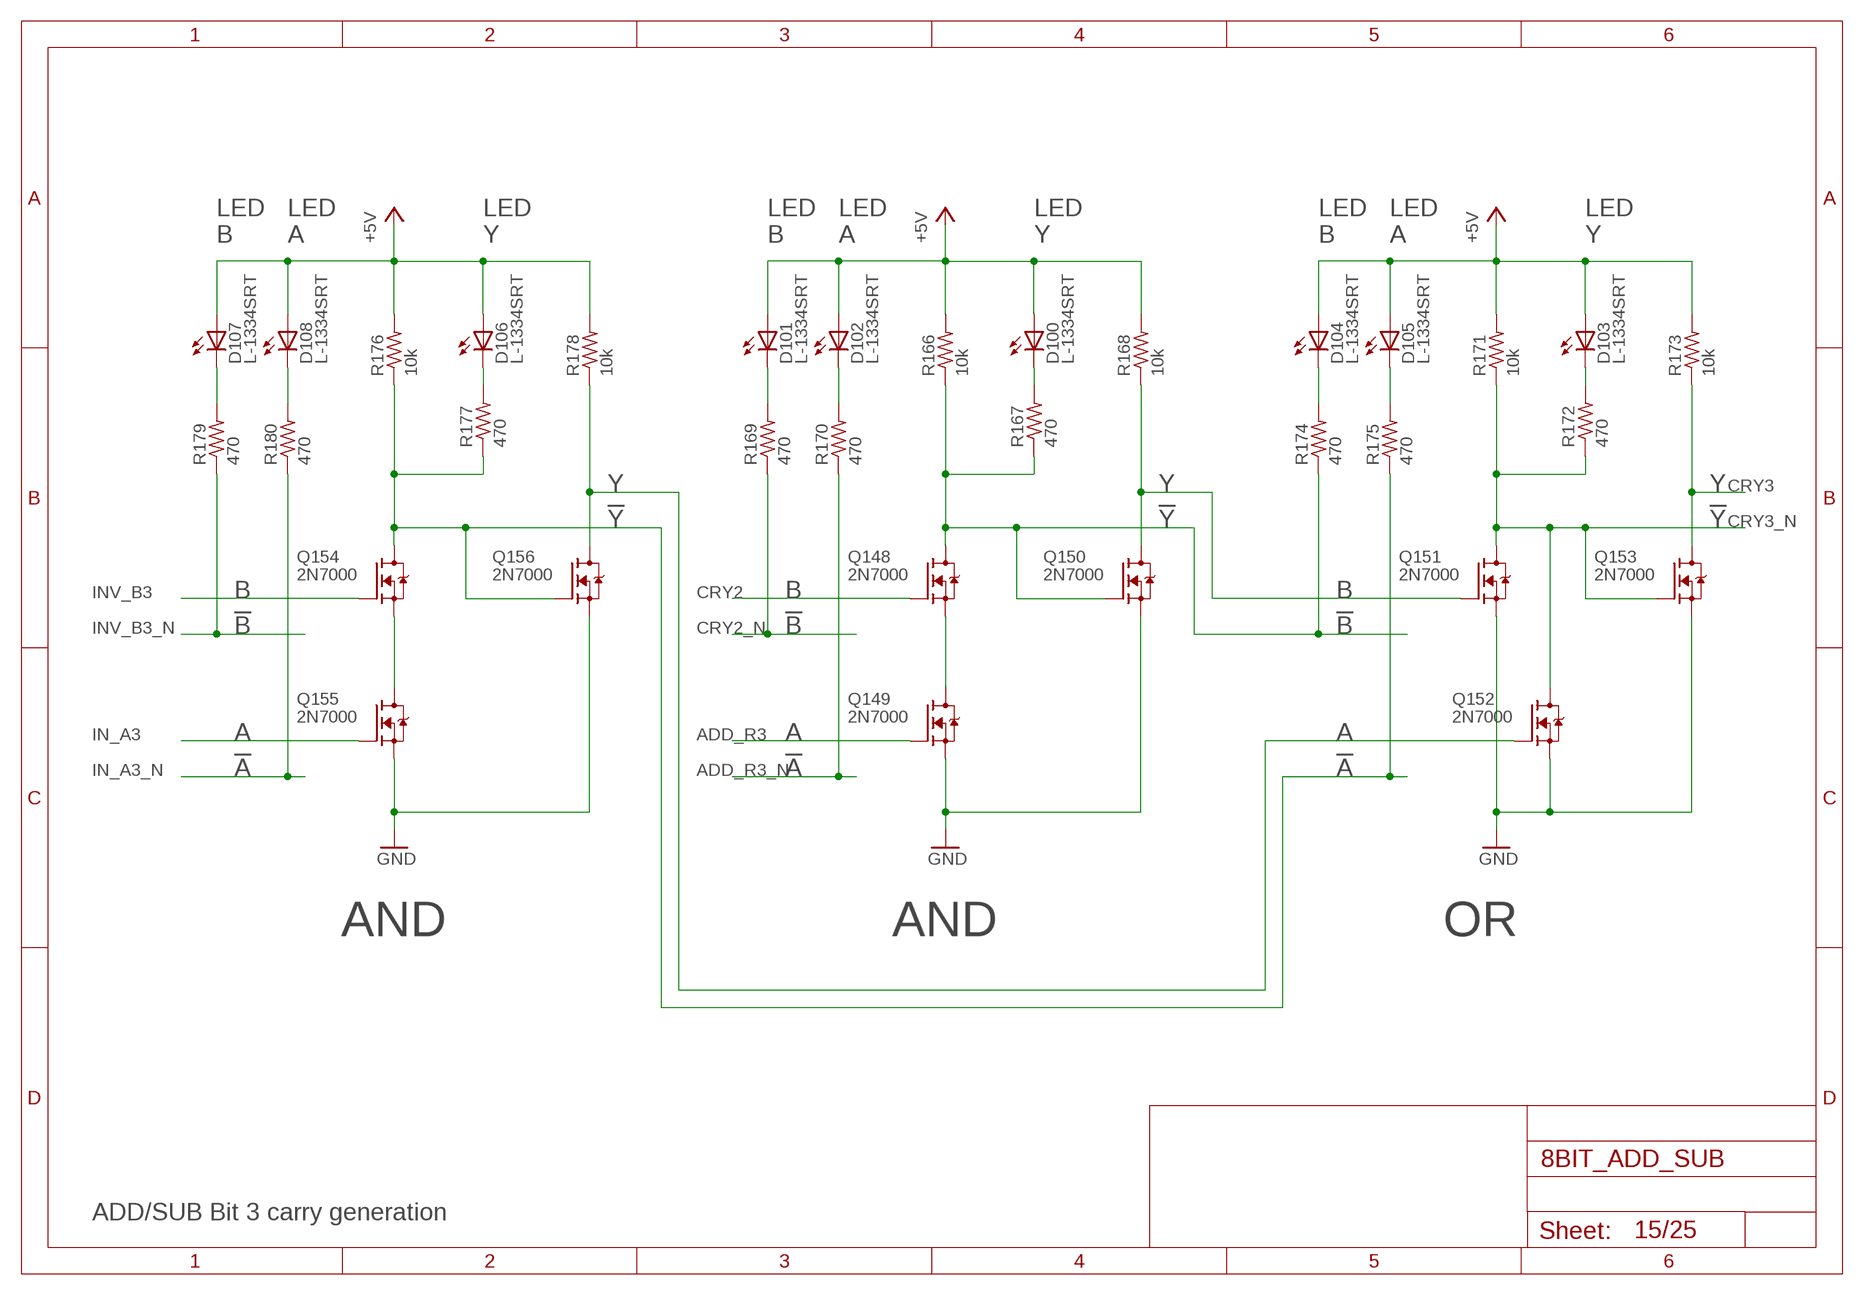
[diagram p14: schematic, sheet 15]
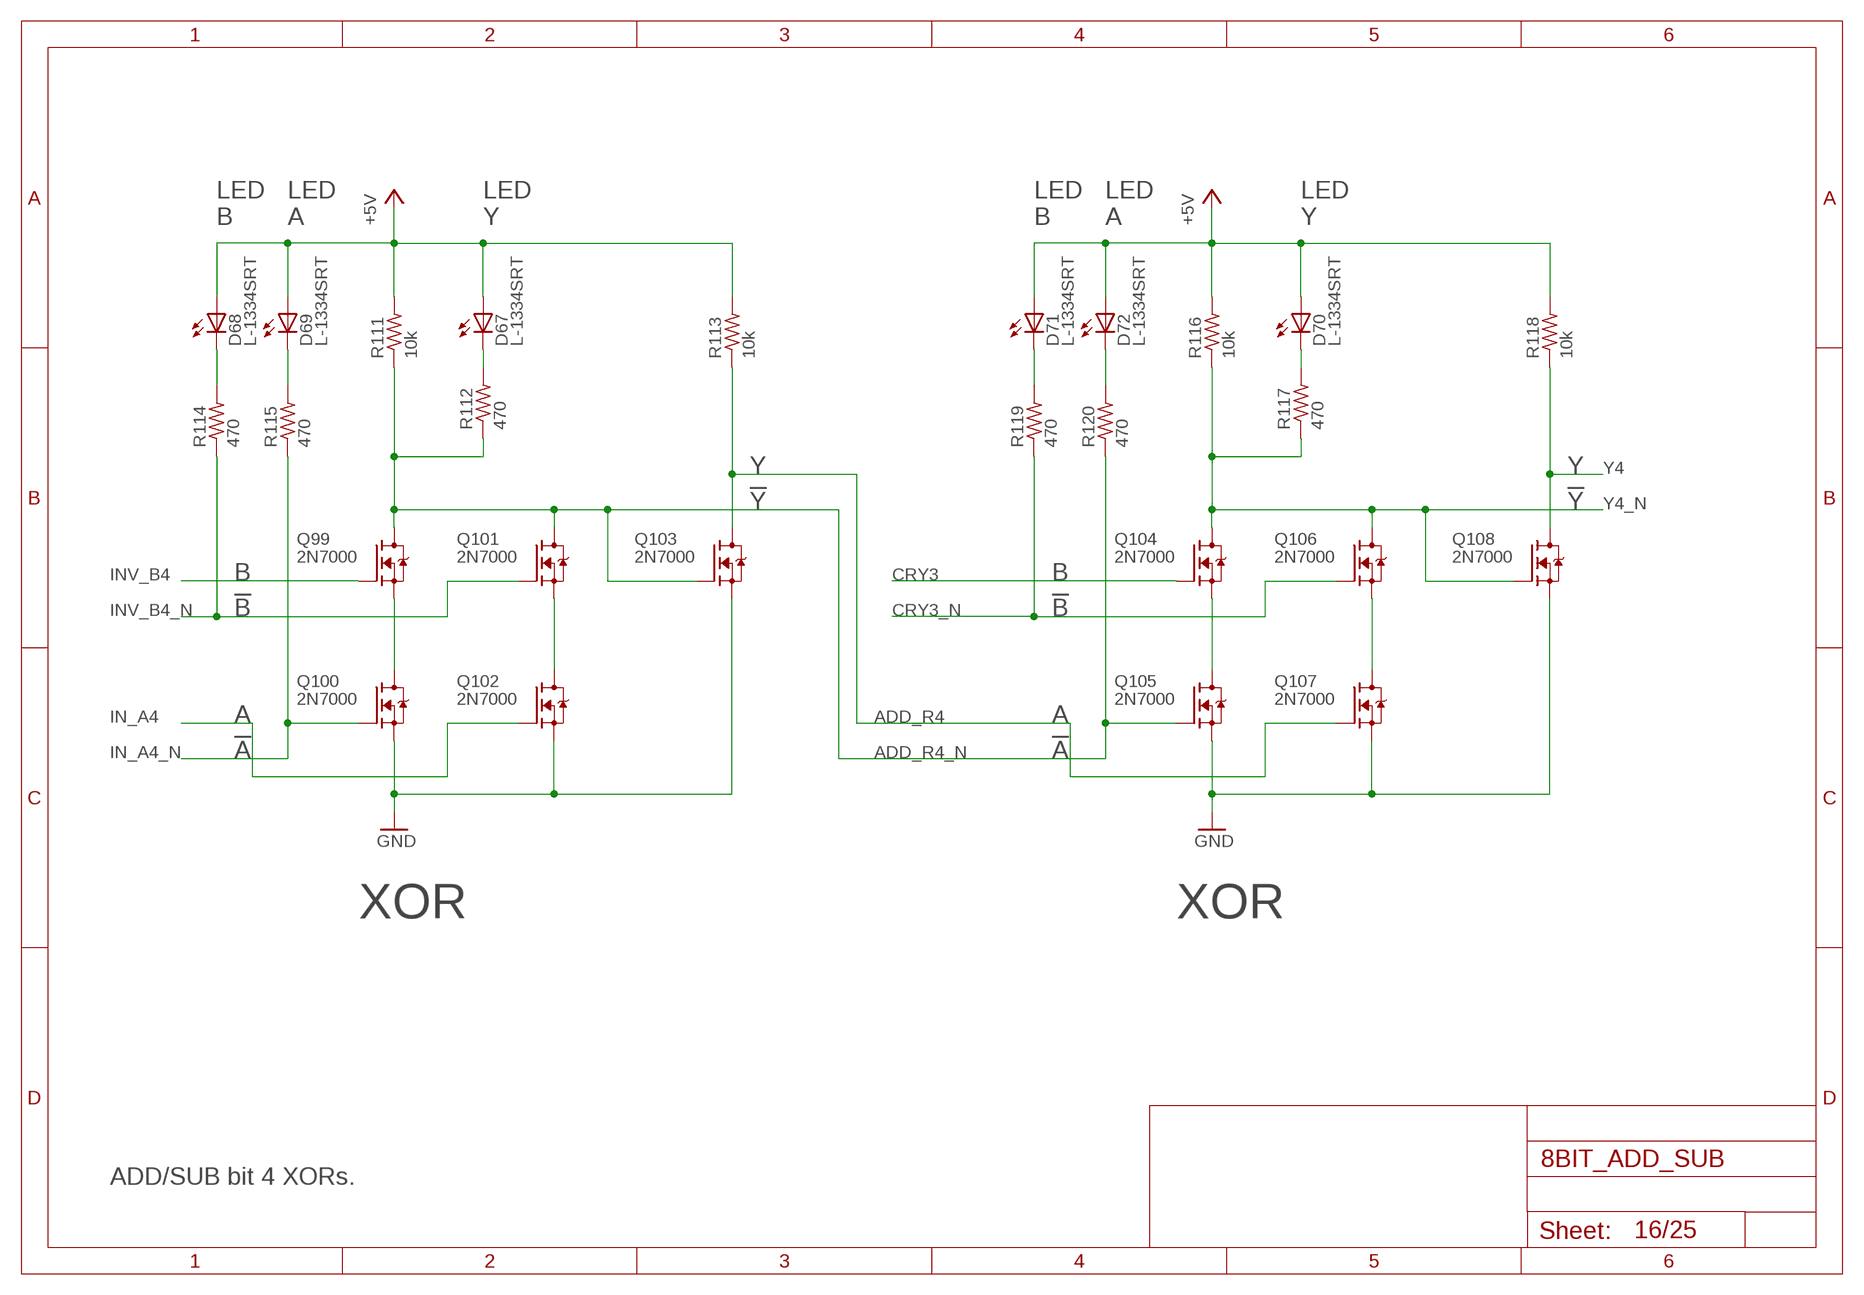
[diagram p15: schematic, sheet 16]
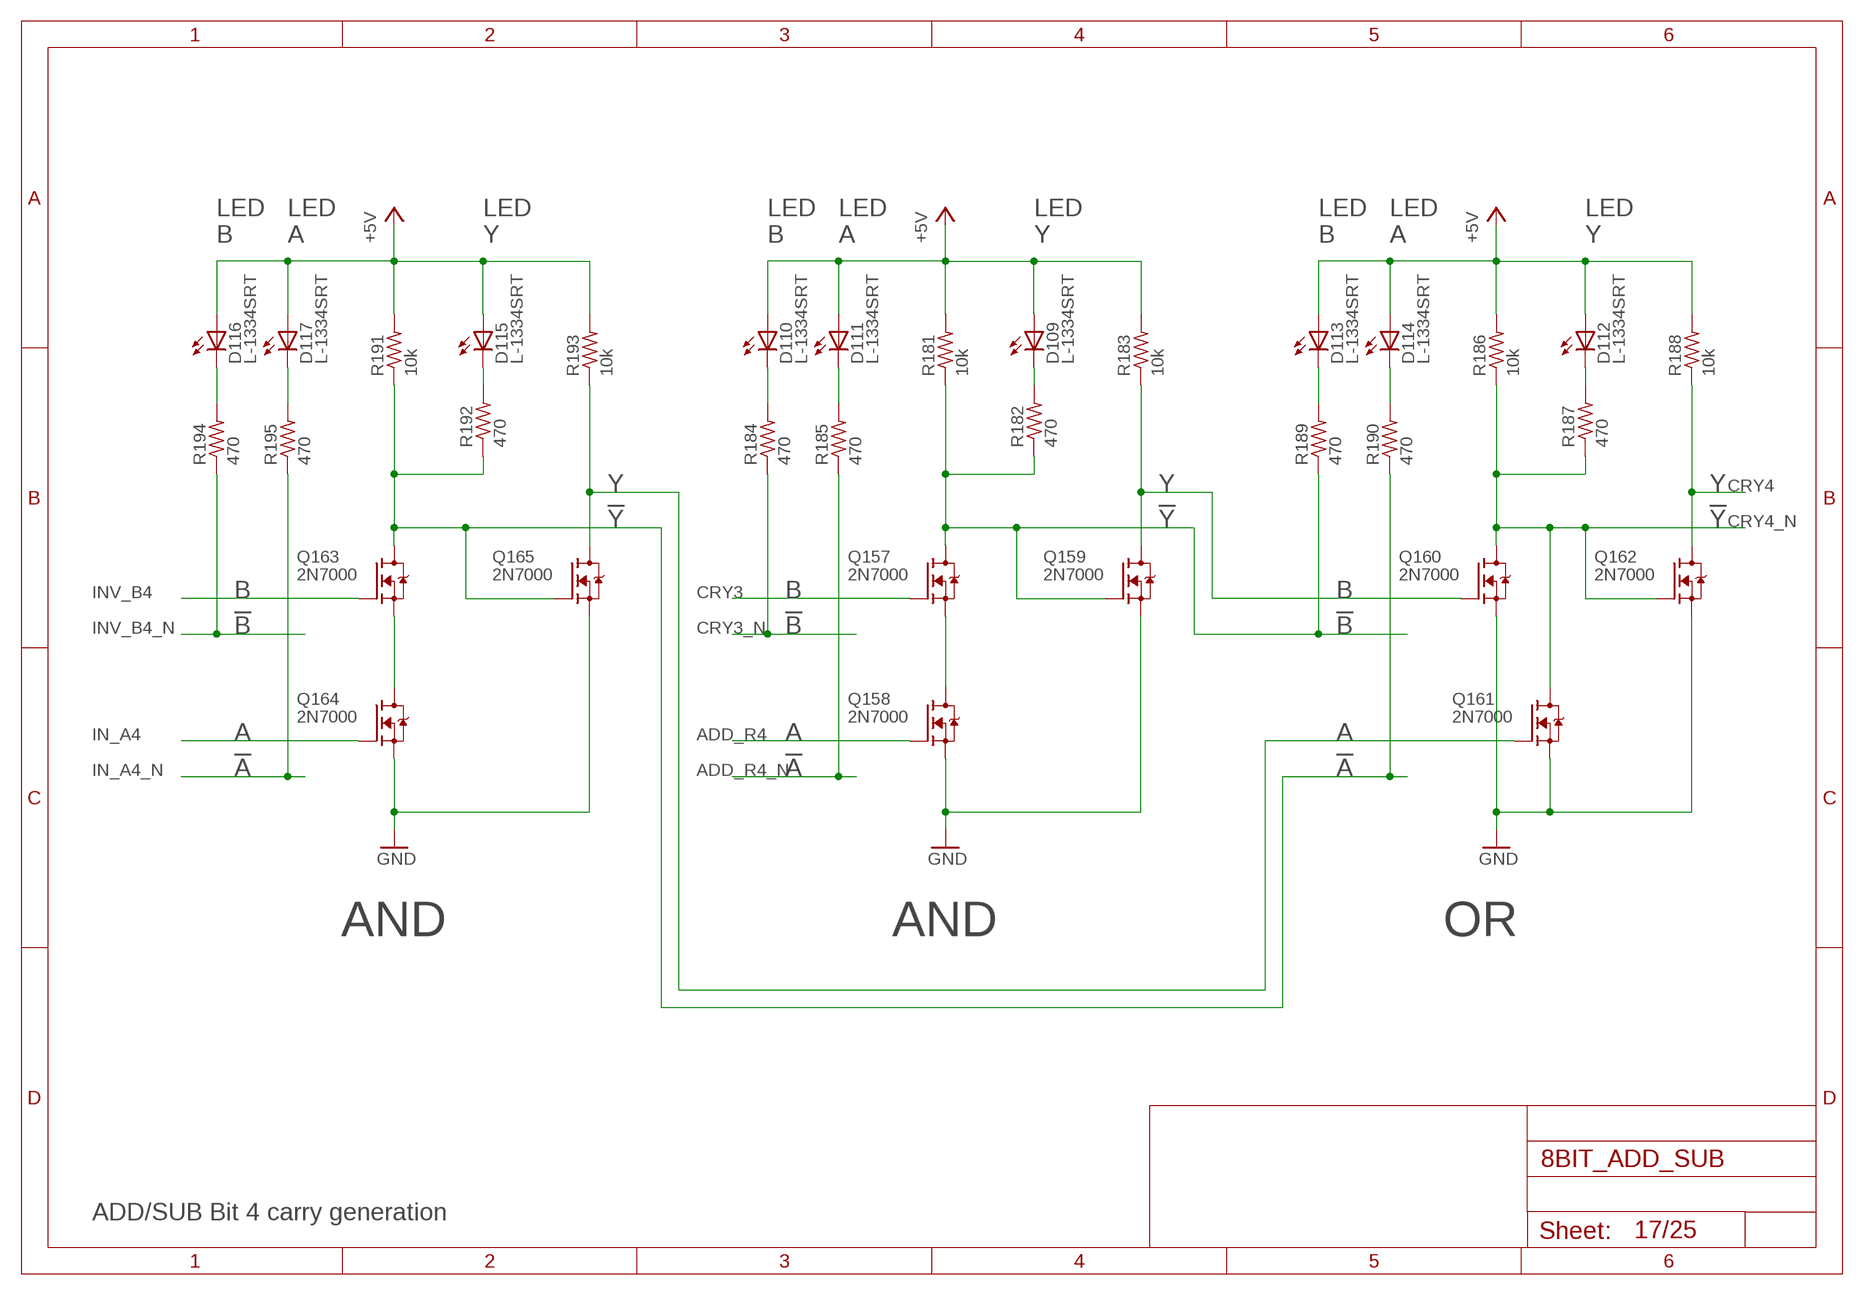
[diagram p16: schematic, sheet 17]
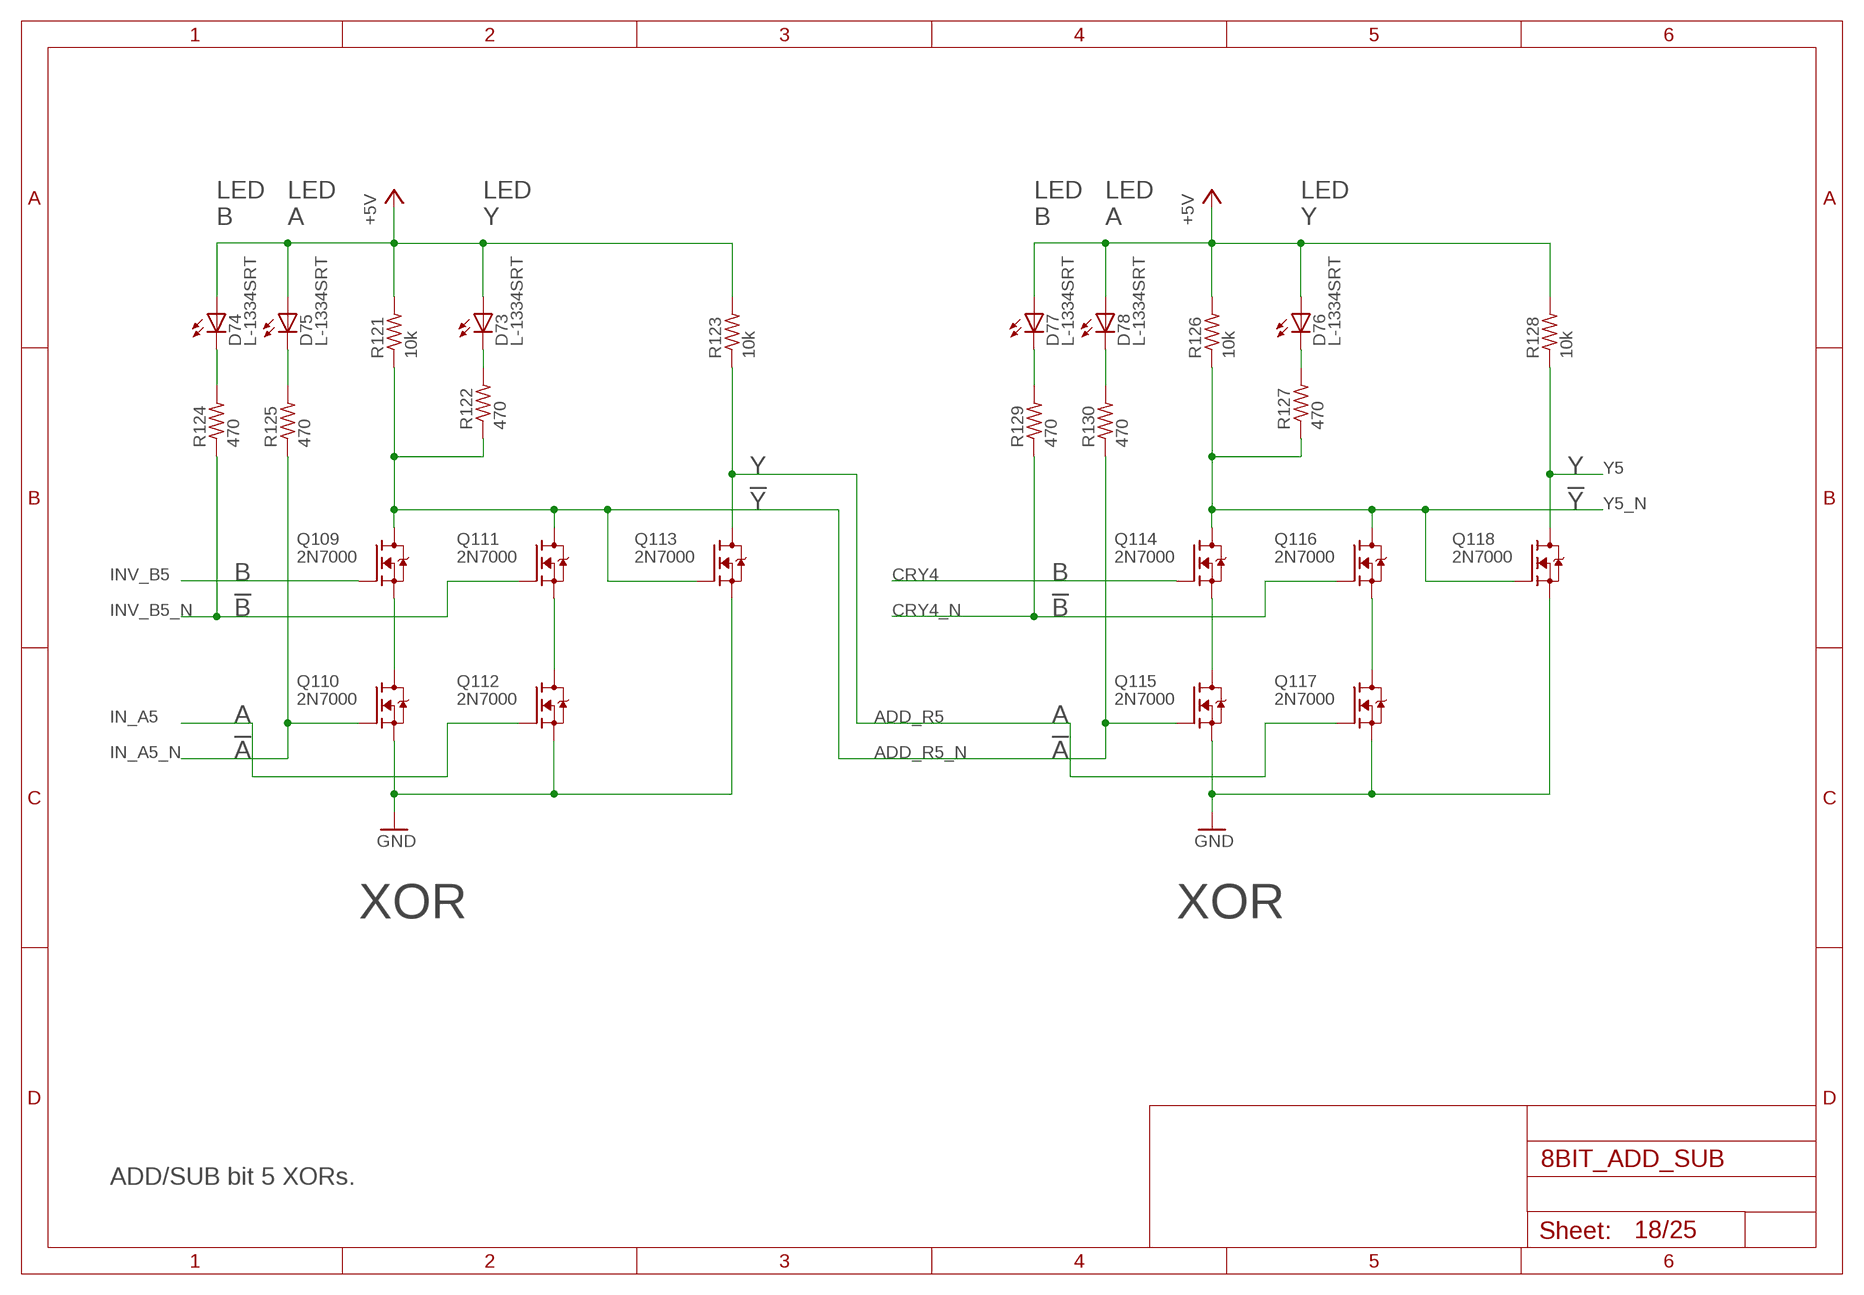
[diagram p17: schematic, sheet 18]
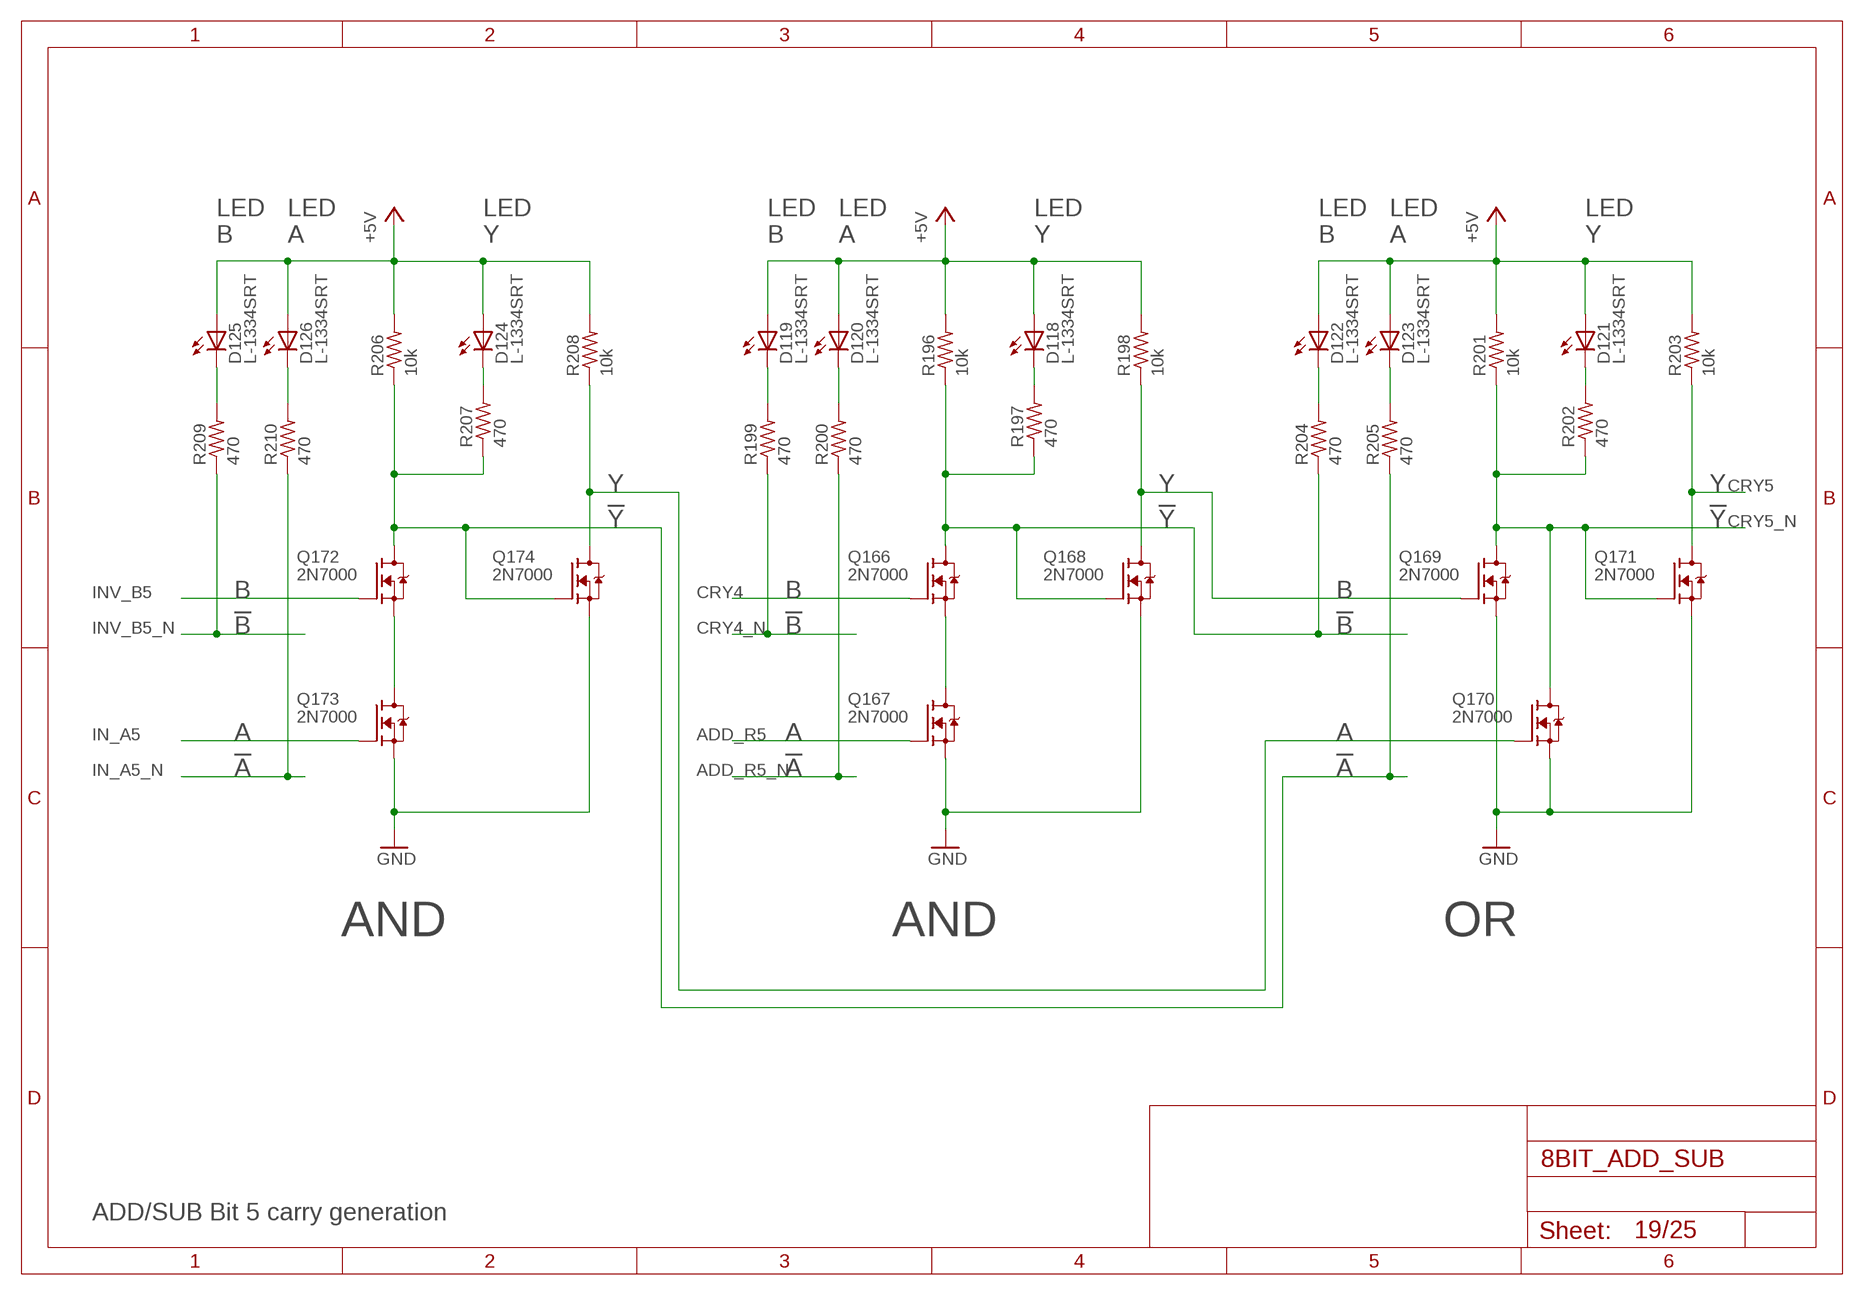
[diagram p18: schematic, sheet 19]
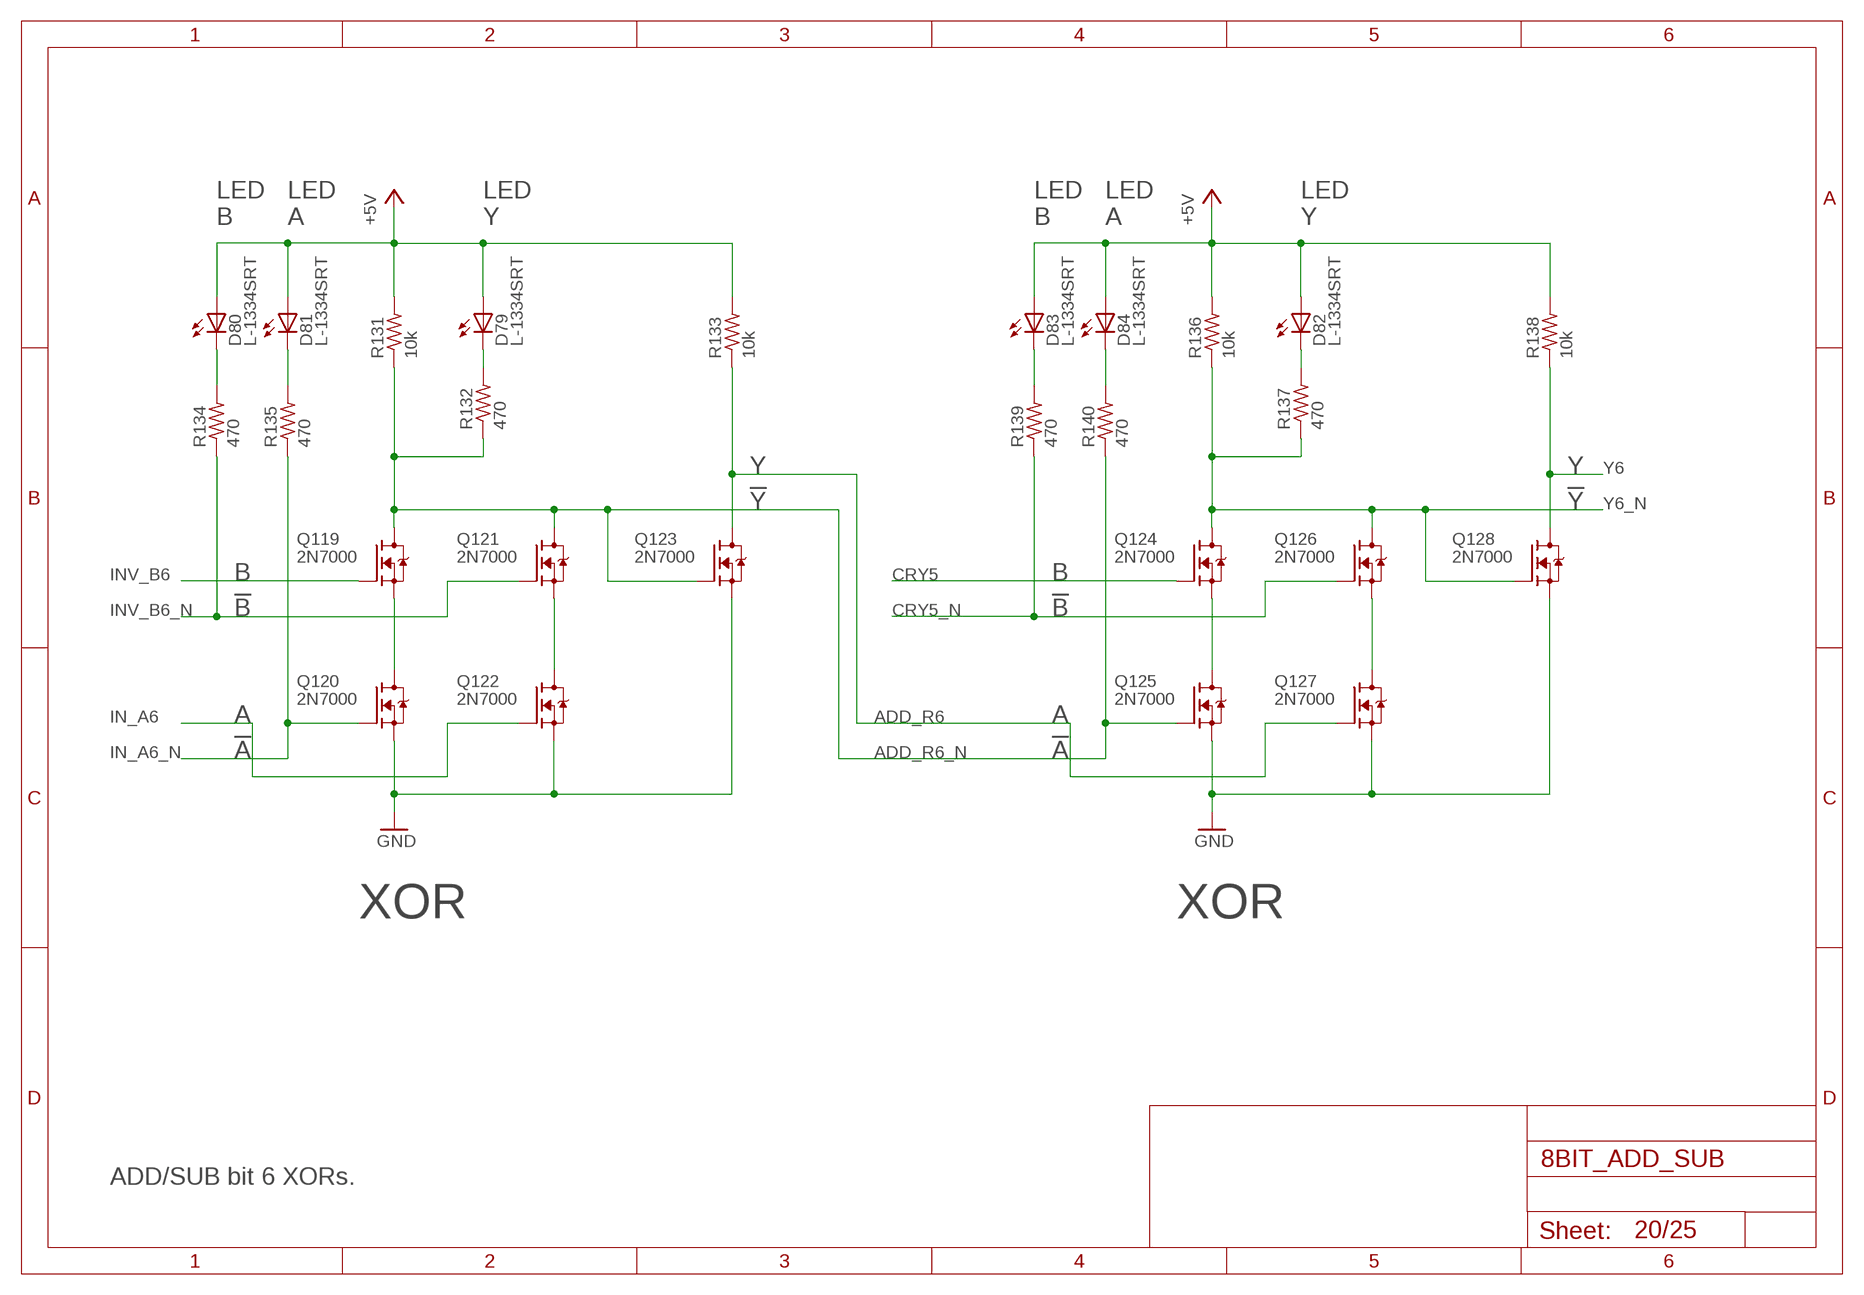
[diagram p19: schematic, sheet 20]
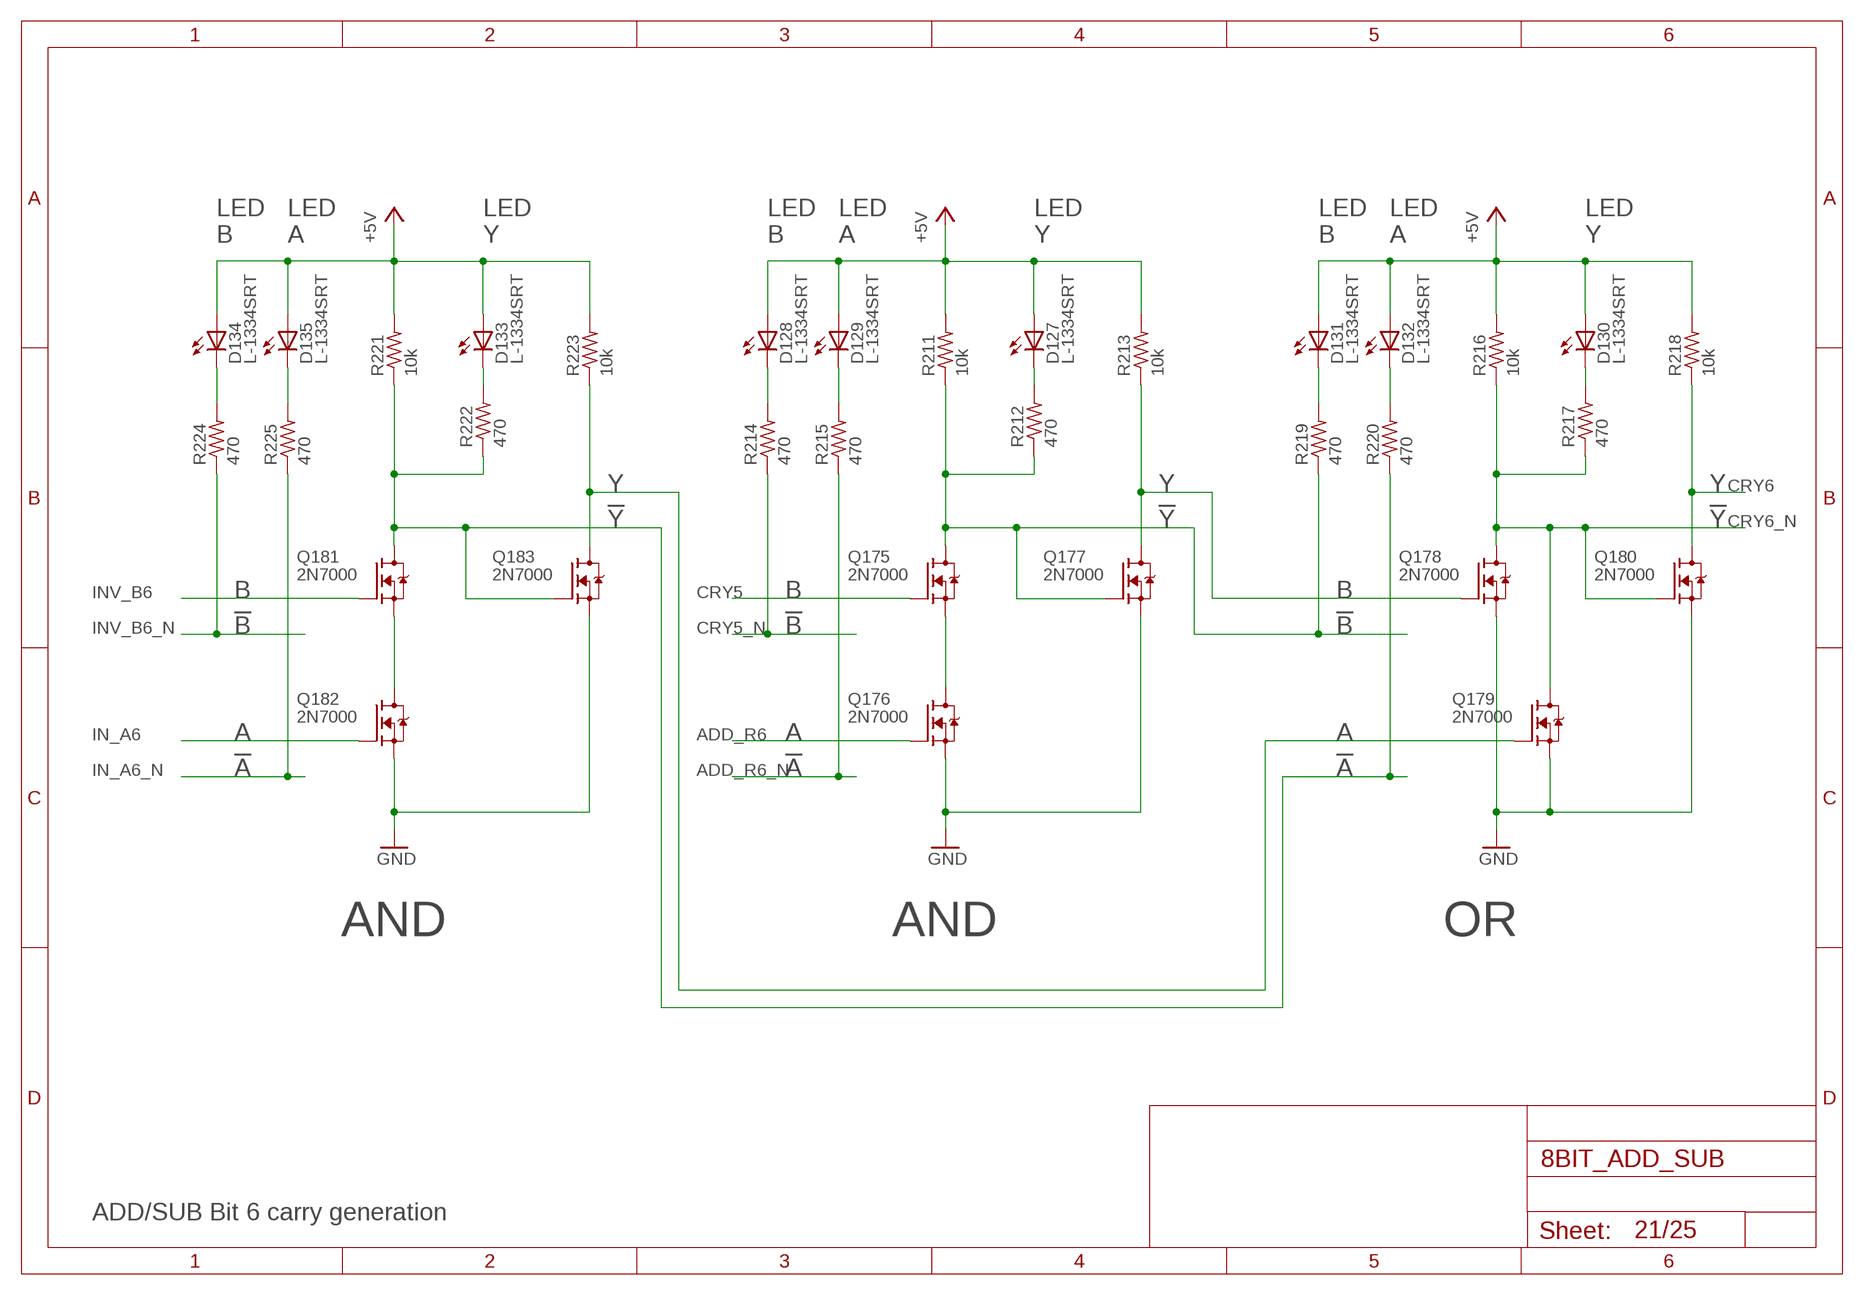
[diagram p20: schematic, sheet 21]
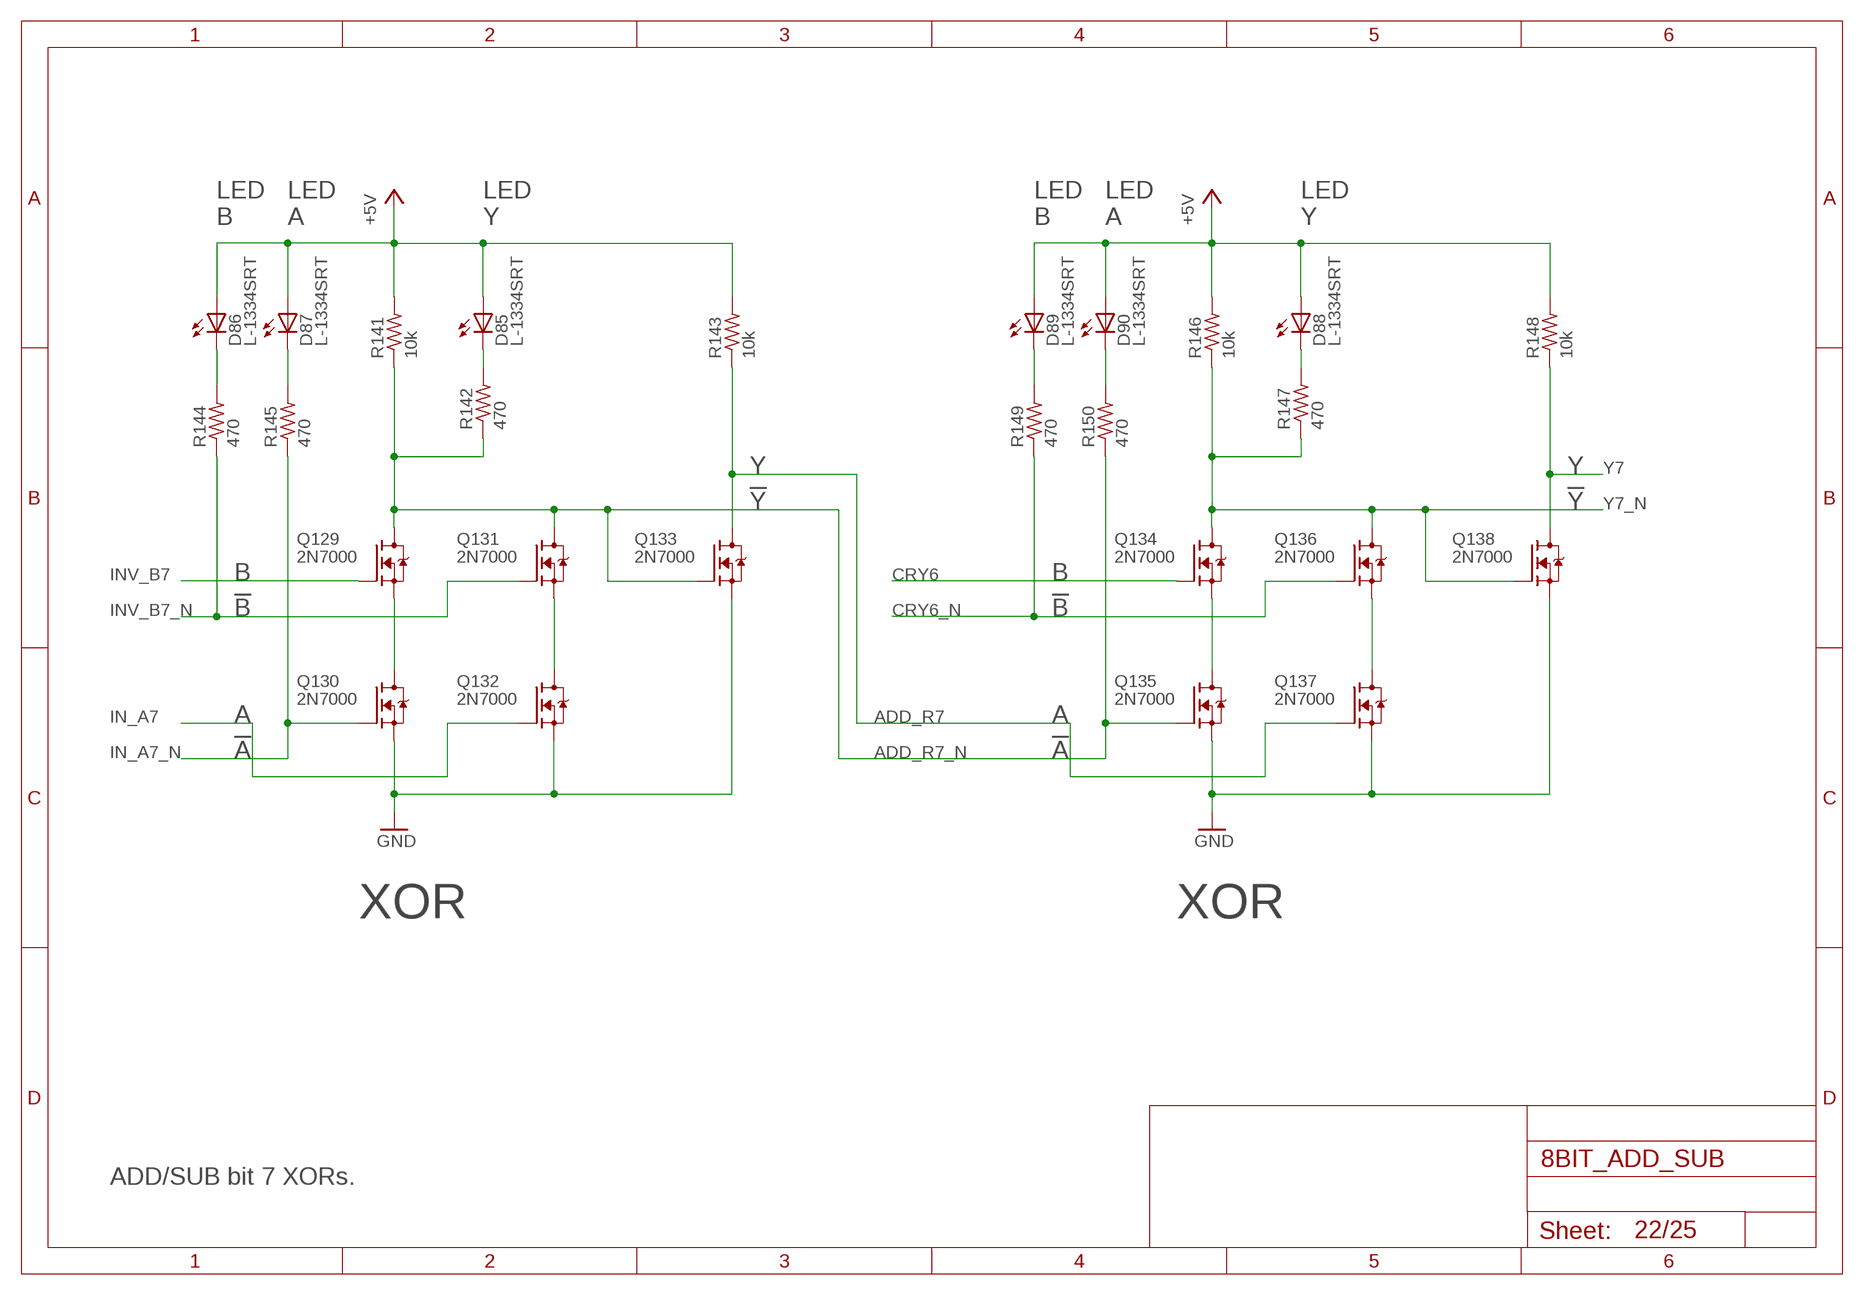
[diagram p21: schematic, sheet 22]
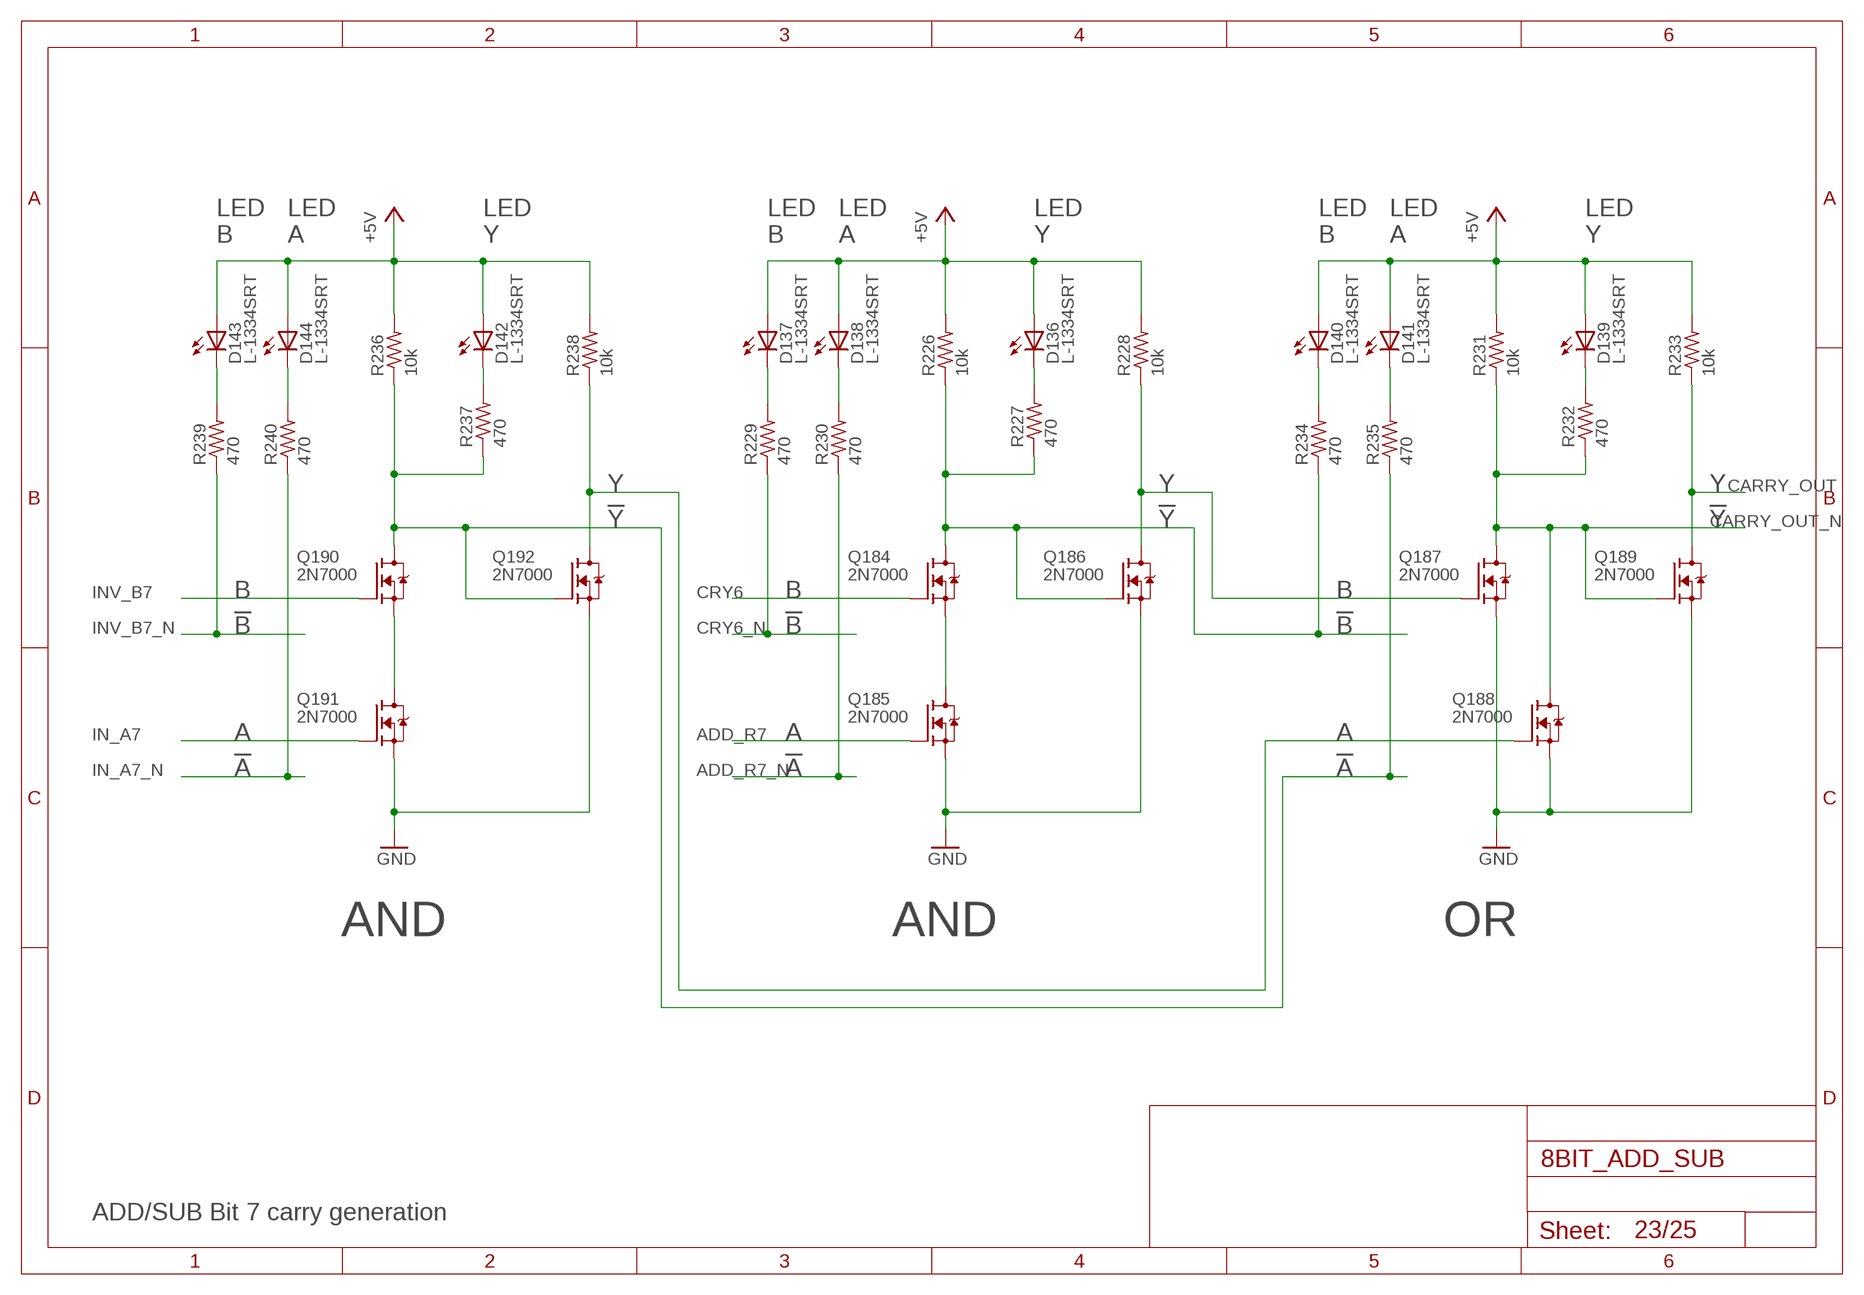
[diagram p22: schematic, sheet 23]
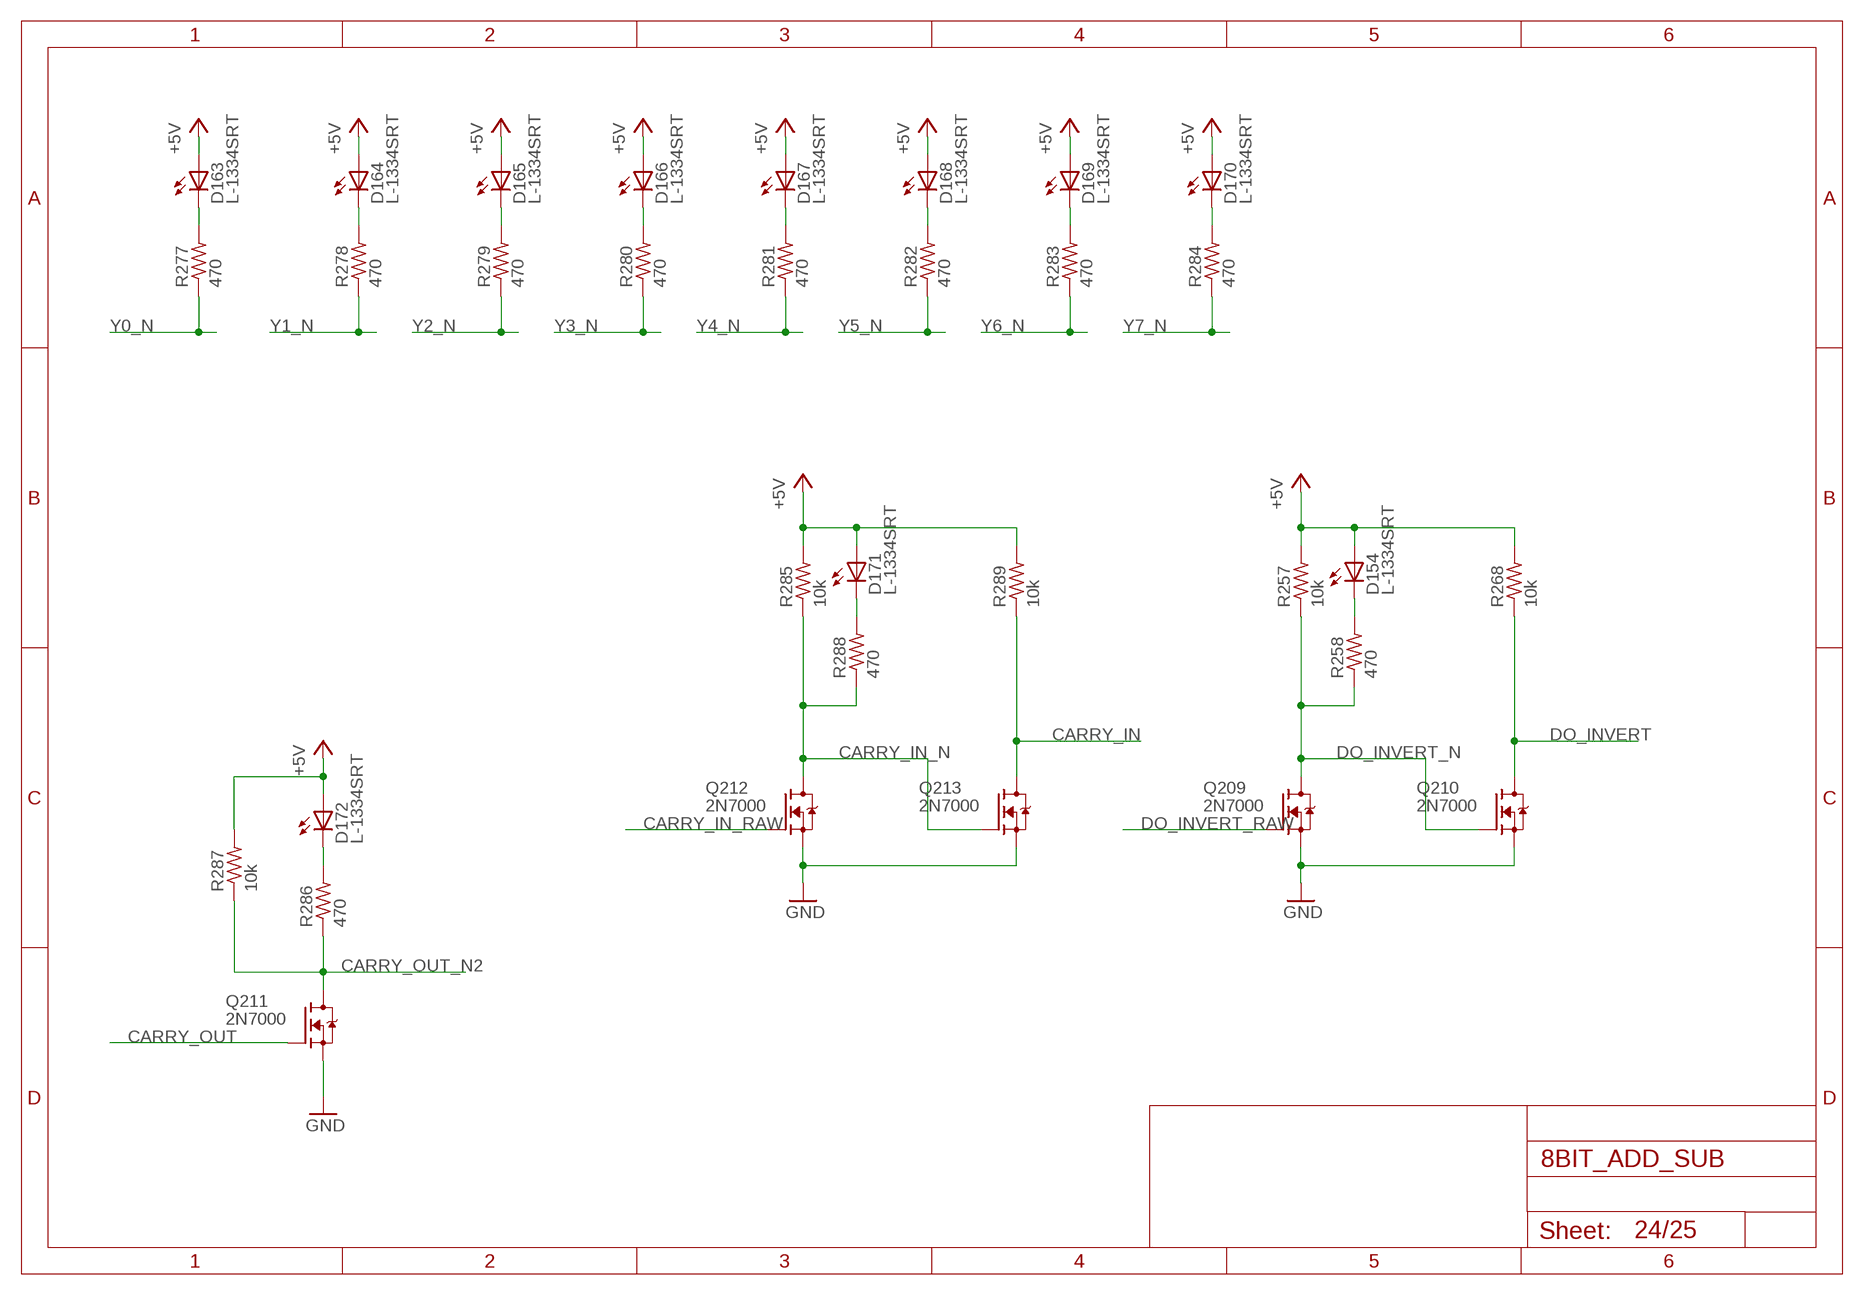
[diagram p23: schematic, sheet 24]
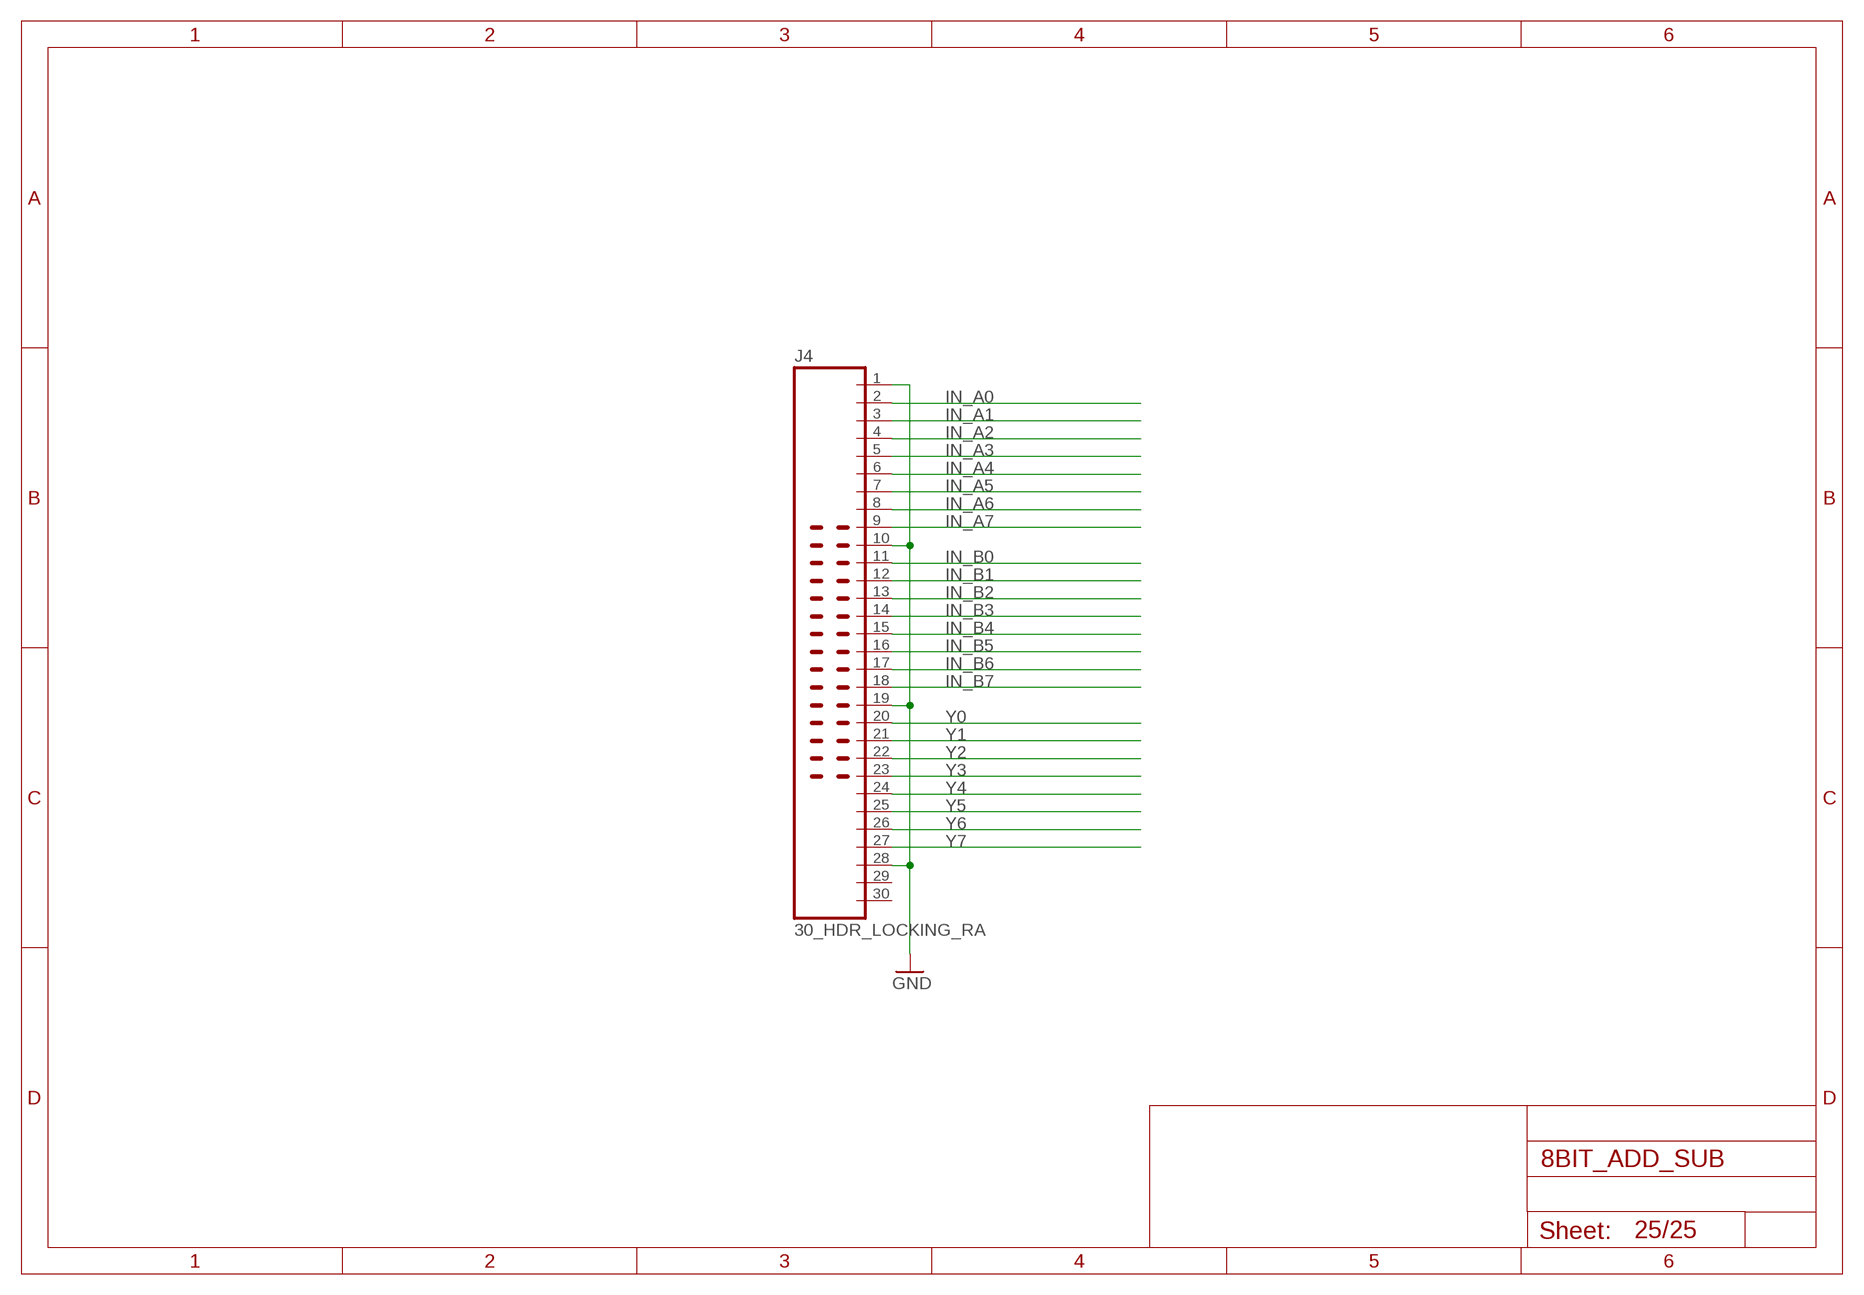
[diagram p24: schematic, sheet 25]

(export (version "E")
  (design (tool "Eeschema 10.0.6"))
  (components
    (comp (ref "J1")
      (value "20_HDR_LOCKING_RA")
      (footprint "eagle-import:20_HDR_LOCKING_RA")
      (libsource (lib "eagle-import") (part "20_HDR_LOCKING_RA"))
    )
    (comp (ref "J2")
      (value "20_HDR_LOCKING_RA")
      (footprint "eagle-import:20_HDR_LOCKING_RA")
      (libsource (lib "eagle-import") (part "20_HDR_LOCKING_RA"))
    )
    (comp (ref "J3")
      (value "20_HDR_LOCKING_RA")
      (footprint "eagle-import:20_HDR_LOCKING_RA")
      (libsource (lib "eagle-import") (part "20_HDR_LOCKING_RA"))
    )
    (comp (ref "TP1")
      (value "TEST_LOOP")
      (footprint "eagle-import:TEST_LOOP")
      (libsource (lib "eagle-import") (part "TEST_LOOP"))
    )
    (comp (ref "TP2")
      (value "TEST_LOOP")
      (footprint "eagle-import:TEST_LOOP")
      (libsource (lib "eagle-import") (part "TEST_LOOP"))
    )
    (comp (ref "TP3")
      (value "TEST_LOOP")
      (footprint "eagle-import:TEST_LOOP")
      (libsource (lib "eagle-import") (part "TEST_LOOP"))
    )
    (comp (ref "D127")
      (value "L-1334SRT")
      (footprint "eagle-import:LED3MM")
      (libsource (lib "eagle-import") (part "L-1334SRT"))
    )
    (comp (ref "D128")
      (value "L-1334SRT")
      (footprint "eagle-import:LED3MM")
      (libsource (lib "eagle-import") (part "L-1334SRT"))
    )
    (comp (ref "D129")
      (value "L-1334SRT")
      (footprint "eagle-import:LED3MM")
      (libsource (lib "eagle-import") (part "L-1334SRT"))
    )
    (comp (ref "D130")
      (value "L-1334SRT")
      (footprint "eagle-import:LED3MM")
      (libsource (lib "eagle-import") (part "L-1334SRT"))
    )
    (comp (ref "D131")
      (value "L-1334SRT")
      (footprint "eagle-import:LED3MM")
      (libsource (lib "eagle-import") (part "L-1334SRT"))
    )
    (comp (ref "D132")
      (value "L-1334SRT")
      (footprint "eagle-import:LED3MM")
      (libsource (lib "eagle-import") (part "L-1334SRT"))
    )
    (comp (ref "D133")
      (value "L-1334SRT")
      (footprint "eagle-import:LED3MM")
      (libsource (lib "eagle-import") (part "L-1334SRT"))
    )
    (comp (ref "D134")
      (value "L-1334SRT")
      (footprint "eagle-import:LED3MM")
      (libsource (lib "eagle-import") (part "L-1334SRT"))
    )
    (comp (ref "D135")
      (value "L-1334SRT")
      (footprint "eagle-import:LED3MM")
      (libsource (lib "eagle-import") (part "L-1334SRT"))
    )
    (comp (ref "Q175")
      (value "2N7000")
      (footprint "eagle-import:TO92-DGS")
      (libsource (lib "eagle-import") (part "2N7000"))
    )
    (comp (ref "Q176")
      (value "2N7000")
      (footprint "eagle-import:TO92-DGS")
      (libsource (lib "eagle-import") (part "2N7000"))
    )
    (comp (ref "Q177")
      (value "2N7000")
      (footprint "eagle-import:TO92-DGS")
      (libsource (lib "eagle-import") (part "2N7000"))
    )
    (comp (ref "Q178")
      (value "2N7000")
      (footprint "eagle-import:TO92-DGS")
      (libsource (lib "eagle-import") (part "2N7000"))
    )
    (comp (ref "Q179")
      (value "2N7000")
      (footprint "eagle-import:TO92-DGS")
      (libsource (lib "eagle-import") (part "2N7000"))
    )
    (comp (ref "Q180")
      (value "2N7000")
      (footprint "eagle-import:TO92-DGS")
      (libsource (lib "eagle-import") (part "2N7000"))
    )
    (comp (ref "Q181")
      (value "2N7000")
      (footprint "eagle-import:TO92-DGS")
      (libsource (lib "eagle-import") (part "2N7000"))
    )
    (comp (ref "Q182")
      (value "2N7000")
      (footprint "eagle-import:TO92-DGS")
      (libsource (lib "eagle-import") (part "2N7000"))
    )
    (comp (ref "Q183")
      (value "2N7000")
      (footprint "eagle-import:TO92-DGS")
      (libsource (lib "eagle-import") (part "2N7000"))
    )
    (comp (ref "R211")
      (value "10k")
      (footprint "eagle-import:R_P2INCH")
      (libsource (lib "eagle-import") (part "R_P2INCH"))
    )
    (comp (ref "R212")
      (value "470")
      (footprint "eagle-import:R_P2INCH")
      (libsource (lib "eagle-import") (part "R_P2INCH"))
    )
    (comp (ref "R213")
      (value "10k")
      (footprint "eagle-import:R_P2INCH")
      (libsource (lib "eagle-import") (part "R_P2INCH"))
    )
    (comp (ref "R214")
      (value "470")
      (footprint "eagle-import:R_P2INCH")
      (libsource (lib "eagle-import") (part "R_P2INCH"))
    )
    (comp (ref "R215")
      (value "470")
      (footprint "eagle-import:R_P2INCH")
      (libsource (lib "eagle-import") (part "R_P2INCH"))
    )
    (comp (ref "R216")
      (value "10k")
      (footprint "eagle-import:R_P2INCH")
      (libsource (lib "eagle-import") (part "R_P2INCH"))
    )
    (comp (ref "R217")
      (value "470")
      (footprint "eagle-import:R_P2INCH")
      (libsource (lib "eagle-import") (part "R_P2INCH"))
    )
    (comp (ref "R218")
      (value "10k")
      (footprint "eagle-import:R_P2INCH")
      (libsource (lib "eagle-import") (part "R_P2INCH"))
    )
    (comp (ref "R219")
      (value "470")
      (footprint "eagle-import:R_P2INCH")
      (libsource (lib "eagle-import") (part "R_P2INCH"))
    )
    (comp (ref "R220")
      (value "470")
      (footprint "eagle-import:R_P2INCH")
      (libsource (lib "eagle-import") (part "R_P2INCH"))
    )
    (comp (ref "R221")
      (value "10k")
      (footprint "eagle-import:R_P2INCH")
      (libsource (lib "eagle-import") (part "R_P2INCH"))
    )
    (comp (ref "R222")
      (value "470")
      (footprint "eagle-import:R_P2INCH")
      (libsource (lib "eagle-import") (part "R_P2INCH"))
    )
    (comp (ref "R223")
      (value "10k")
      (footprint "eagle-import:R_P2INCH")
      (libsource (lib "eagle-import") (part "R_P2INCH"))
    )
    (comp (ref "R224")
      (value "470")
      (footprint "eagle-import:R_P2INCH")
      (libsource (lib "eagle-import") (part "R_P2INCH"))
    )
    (comp (ref "R225")
      (value "470")
      (footprint "eagle-import:R_P2INCH")
      (libsource (lib "eagle-import") (part "R_P2INCH"))
    )
    (comp (ref "D91")
      (value "L-1334SRT")
      (footprint "eagle-import:LED3MM")
      (libsource (lib "eagle-import") (part "L-1334SRT"))
    )
    (comp (ref "D92")
      (value "L-1334SRT")
      (footprint "eagle-import:LED3MM")
      (libsource (lib "eagle-import") (part "L-1334SRT"))
    )
    (comp (ref "D93")
      (value "L-1334SRT")
      (footprint "eagle-import:LED3MM")
      (libsource (lib "eagle-import") (part "L-1334SRT"))
    )
    (comp (ref "D94")
      (value "L-1334SRT")
      (footprint "eagle-import:LED3MM")
      (libsource (lib "eagle-import") (part "L-1334SRT"))
    )
    (comp (ref "D95")
      (value "L-1334SRT")
      (footprint "eagle-import:LED3MM")
      (libsource (lib "eagle-import") (part "L-1334SRT"))
    )
    (comp (ref "D96")
      (value "L-1334SRT")
      (footprint "eagle-import:LED3MM")
      (libsource (lib "eagle-import") (part "L-1334SRT"))
    )
    (comp (ref "D97")
      (value "L-1334SRT")
      (footprint "eagle-import:LED3MM")
      (libsource (lib "eagle-import") (part "L-1334SRT"))
    )
    (comp (ref "D98")
      (value "L-1334SRT")
      (footprint "eagle-import:LED3MM")
      (libsource (lib "eagle-import") (part "L-1334SRT"))
    )
    (comp (ref "D99")
      (value "L-1334SRT")
      (footprint "eagle-import:LED3MM")
      (libsource (lib "eagle-import") (part "L-1334SRT"))
    )
    (comp (ref "Q139")
      (value "2N7000")
      (footprint "eagle-import:TO92-DGS")
      (libsource (lib "eagle-import") (part "2N7000"))
    )
    (comp (ref "Q140")
      (value "2N7000")
      (footprint "eagle-import:TO92-DGS")
      (libsource (lib "eagle-import") (part "2N7000"))
    )
    (comp (ref "Q141")
      (value "2N7000")
      (footprint "eagle-import:TO92-DGS")
      (libsource (lib "eagle-import") (part "2N7000"))
    )
    (comp (ref "Q142")
      (value "2N7000")
      (footprint "eagle-import:TO92-DGS")
      (libsource (lib "eagle-import") (part "2N7000"))
    )
    (comp (ref "Q143")
      (value "2N7000")
      (footprint "eagle-import:TO92-DGS")
      (libsource (lib "eagle-import") (part "2N7000"))
    )
    (comp (ref "Q144")
      (value "2N7000")
      (footprint "eagle-import:TO92-DGS")
      (libsource (lib "eagle-import") (part "2N7000"))
    )
    (comp (ref "Q145")
      (value "2N7000")
      (footprint "eagle-import:TO92-DGS")
      (libsource (lib "eagle-import") (part "2N7000"))
    )
    (comp (ref "Q146")
      (value "2N7000")
      (footprint "eagle-import:TO92-DGS")
      (libsource (lib "eagle-import") (part "2N7000"))
    )
    (comp (ref "Q147")
      (value "2N7000")
      (footprint "eagle-import:TO92-DGS")
      (libsource (lib "eagle-import") (part "2N7000"))
    )
    (comp (ref "R151")
      (value "10k")
      (footprint "eagle-import:R_P2INCH")
      (libsource (lib "eagle-import") (part "R_P2INCH"))
    )
    (comp (ref "R152")
      (value "470")
      (footprint "eagle-import:R_P2INCH")
      (libsource (lib "eagle-import") (part "R_P2INCH"))
    )
    (comp (ref "R153")
      (value "10k")
      (footprint "eagle-import:R_P2INCH")
      (libsource (lib "eagle-import") (part "R_P2INCH"))
    )
    (comp (ref "R154")
      (value "470")
      (footprint "eagle-import:R_P2INCH")
      (libsource (lib "eagle-import") (part "R_P2INCH"))
    )
    (comp (ref "R155")
      (value "470")
      (footprint "eagle-import:R_P2INCH")
      (libsource (lib "eagle-import") (part "R_P2INCH"))
    )
    (comp (ref "R156")
      (value "10k")
      (footprint "eagle-import:R_P2INCH")
      (libsource (lib "eagle-import") (part "R_P2INCH"))
    )
    (comp (ref "R157")
      (value "470")
      (footprint "eagle-import:R_P2INCH")
      (libsource (lib "eagle-import") (part "R_P2INCH"))
    )
    (comp (ref "R158")
      (value "10k")
      (footprint "eagle-import:R_P2INCH")
      (libsource (lib "eagle-import") (part "R_P2INCH"))
    )
    (comp (ref "R159")
      (value "470")
      (footprint "eagle-import:R_P2INCH")
      (libsource (lib "eagle-import") (part "R_P2INCH"))
    )
    (comp (ref "R160")
      (value "470")
      (footprint "eagle-import:R_P2INCH")
      (libsource (lib "eagle-import") (part "R_P2INCH"))
    )
    (comp (ref "R161")
      (value "10k")
      (footprint "eagle-import:R_P2INCH")
      (libsource (lib "eagle-import") (part "R_P2INCH"))
    )
    (comp (ref "R162")
      (value "470")
      (footprint "eagle-import:R_P2INCH")
      (libsource (lib "eagle-import") (part "R_P2INCH"))
    )
    (comp (ref "R163")
      (value "10k")
      (footprint "eagle-import:R_P2INCH")
      (libsource (lib "eagle-import") (part "R_P2INCH"))
    )
    (comp (ref "R164")
      (value "470")
      (footprint "eagle-import:R_P2INCH")
      (libsource (lib "eagle-import") (part "R_P2INCH"))
    )
    (comp (ref "R165")
      (value "470")
      (footprint "eagle-import:R_P2INCH")
      (libsource (lib "eagle-import") (part "R_P2INCH"))
    )
    (comp (ref "D136")
      (value "L-1334SRT")
      (footprint "eagle-import:LED3MM")
      (libsource (lib "eagle-import") (part "L-1334SRT"))
    )
    (comp (ref "D137")
      (value "L-1334SRT")
      (footprint "eagle-import:LED3MM")
      (libsource (lib "eagle-import") (part "L-1334SRT"))
    )
    (comp (ref "D138")
      (value "L-1334SRT")
      (footprint "eagle-import:LED3MM")
      (libsource (lib "eagle-import") (part "L-1334SRT"))
    )
    (comp (ref "D139")
      (value "L-1334SRT")
      (footprint "eagle-import:LED3MM")
      (libsource (lib "eagle-import") (part "L-1334SRT"))
    )
    (comp (ref "D140")
      (value "L-1334SRT")
      (footprint "eagle-import:LED3MM")
      (libsource (lib "eagle-import") (part "L-1334SRT"))
    )
    (comp (ref "D141")
      (value "L-1334SRT")
      (footprint "eagle-import:LED3MM")
      (libsource (lib "eagle-import") (part "L-1334SRT"))
    )
    (comp (ref "D142")
      (value "L-1334SRT")
      (footprint "eagle-import:LED3MM")
      (libsource (lib "eagle-import") (part "L-1334SRT"))
    )
    (comp (ref "D143")
      (value "L-1334SRT")
      (footprint "eagle-import:LED3MM")
      (libsource (lib "eagle-import") (part "L-1334SRT"))
    )
    (comp (ref "D144")
      (value "L-1334SRT")
      (footprint "eagle-import:LED3MM")
      (libsource (lib "eagle-import") (part "L-1334SRT"))
    )
    (comp (ref "Q184")
      (value "2N7000")
      (footprint "eagle-import:TO92-DGS")
      (libsource (lib "eagle-import") (part "2N7000"))
    )
    (comp (ref "Q185")
      (value "2N7000")
      (footprint "eagle-import:TO92-DGS")
      (libsource (lib "eagle-import") (part "2N7000"))
    )
    (comp (ref "Q186")
      (value "2N7000")
      (footprint "eagle-import:TO92-DGS")
      (libsource (lib "eagle-import") (part "2N7000"))
    )
    (comp (ref "Q187")
      (value "2N7000")
      (footprint "eagle-import:TO92-DGS")
      (libsource (lib "eagle-import") (part "2N7000"))
    )
    (comp (ref "Q188")
      (value "2N7000")
      (footprint "eagle-import:TO92-DGS")
      (libsource (lib "eagle-import") (part "2N7000"))
    )
    (comp (ref "Q189")
      (value "2N7000")
      (footprint "eagle-import:TO92-DGS")
      (libsource (lib "eagle-import") (part "2N7000"))
    )
    (comp (ref "Q190")
      (value "2N7000")
      (footprint "eagle-import:TO92-DGS")
      (libsource (lib "eagle-import") (part "2N7000"))
    )
    (comp (ref "Q191")
      (value "2N7000")
      (footprint "eagle-import:TO92-DGS")
      (libsource (lib "eagle-import") (part "2N7000"))
    )
    (comp (ref "Q192")
      (value "2N7000")
      (footprint "eagle-import:TO92-DGS")
      (libsource (lib "eagle-import") (part "2N7000"))
    )
    (comp (ref "R226")
      (value "10k")
      (footprint "eagle-import:R_P2INCH")
      (libsource (lib "eagle-import") (part "R_P2INCH"))
    )
    (comp (ref "R227")
      (value "470")
      (footprint "eagle-import:R_P2INCH")
      (libsource (lib "eagle-import") (part "R_P2INCH"))
    )
    (comp (ref "R228")
      (value "10k")
      (footprint "eagle-import:R_P2INCH")
      (libsource (lib "eagle-import") (part "R_P2INCH"))
    )
    (comp (ref "R229")
      (value "470")
      (footprint "eagle-import:R_P2INCH")
      (libsource (lib "eagle-import") (part "R_P2INCH"))
    )
    (comp (ref "R230")
      (value "470")
      (footprint "eagle-import:R_P2INCH")
      (libsource (lib "eagle-import") (part "R_P2INCH"))
    )
    (comp (ref "R231")
      (value "10k")
      (footprint "eagle-import:R_P2INCH")
      (libsource (lib "eagle-import") (part "R_P2INCH"))
    )
    (comp (ref "R232")
      (value "470")
      (footprint "eagle-import:R_P2INCH")
      (libsource (lib "eagle-import") (part "R_P2INCH"))
    )
    (comp (ref "R233")
      (value "10k")
      (footprint "eagle-import:R_P2INCH")
      (libsource (lib "eagle-import") (part "R_P2INCH"))
    )
    (comp (ref "R234")
      (value "470")
      (footprint "eagle-import:R_P2INCH")
      (libsource (lib "eagle-import") (part "R_P2INCH"))
    )
    (comp (ref "R235")
      (value "470")
      (footprint "eagle-import:R_P2INCH")
      (libsource (lib "eagle-import") (part "R_P2INCH"))
    )
    (comp (ref "R236")
      (value "10k")
      (footprint "eagle-import:R_P2INCH")
      (libsource (lib "eagle-import") (part "R_P2INCH"))
    )
    (comp (ref "R237")
      (value "470")
      (footprint "eagle-import:R_P2INCH")
      (libsource (lib "eagle-import") (part "R_P2INCH"))
    )
    (comp (ref "R238")
      (value "10k")
      (footprint "eagle-import:R_P2INCH")
      (libsource (lib "eagle-import") (part "R_P2INCH"))
    )
    (comp (ref "R239")
      (value "470")
      (footprint "eagle-import:R_P2INCH")
      (libsource (lib "eagle-import") (part "R_P2INCH"))
    )
    (comp (ref "R240")
      (value "470")
      (footprint "eagle-import:R_P2INCH")
      (libsource (lib "eagle-import") (part "R_P2INCH"))
    )
    (comp (ref "D28")
      (value "L-1334SRT")
      (footprint "eagle-import:LED3MM")
      (libsource (lib "eagle-import") (part "L-1334SRT"))
    )
    (comp (ref "D29")
      (value "L-1334SRT")
      (footprint "eagle-import:LED3MM")
      (libsource (lib "eagle-import") (part "L-1334SRT"))
    )
    (comp (ref "D30")
      (value "L-1334SRT")
      (footprint "eagle-import:LED3MM")
      (libsource (lib "eagle-import") (part "L-1334SRT"))
    )
    (comp (ref "D31")
      (value "L-1334SRT")
      (footprint "eagle-import:LED3MM")
      (libsource (lib "eagle-import") (part "L-1334SRT"))
    )
    (comp (ref "D32")
      (value "L-1334SRT")
      (footprint "eagle-import:LED3MM")
      (libsource (lib "eagle-import") (part "L-1334SRT"))
    )
    (comp (ref "D33")
      (value "L-1334SRT")
      (footprint "eagle-import:LED3MM")
      (libsource (lib "eagle-import") (part "L-1334SRT"))
    )
    (comp (ref "D43")
      (value "L-1334SRT")
      (footprint "eagle-import:LED3MM")
      (libsource (lib "eagle-import") (part "L-1334SRT"))
    )
    (comp (ref "D44")
      (value "L-1334SRT")
      (footprint "eagle-import:LED3MM")
      (libsource (lib "eagle-import") (part "L-1334SRT"))
    )
    (comp (ref "D45")
      (value "L-1334SRT")
      (footprint "eagle-import:LED3MM")
      (libsource (lib "eagle-import") (part "L-1334SRT"))
    )
    (comp (ref "Q42")
      (value "2N7000")
      (footprint "eagle-import:TO92-DGS")
      (libsource (lib "eagle-import") (part "2N7000"))
    )
    (comp (ref "Q43")
      (value "2N7000")
      (footprint "eagle-import:TO92-DGS")
      (libsource (lib "eagle-import") (part "2N7000"))
    )
    (comp (ref "Q44")
      (value "2N7000")
      (footprint "eagle-import:TO92-DGS")
      (libsource (lib "eagle-import") (part "2N7000"))
    )
    (comp (ref "Q45")
      (value "2N7000")
      (footprint "eagle-import:TO92-DGS")
      (libsource (lib "eagle-import") (part "2N7000"))
    )
    (comp (ref "Q46")
      (value "2N7000")
      (footprint "eagle-import:TO92-DGS")
      (libsource (lib "eagle-import") (part "2N7000"))
    )
    (comp (ref "Q47")
      (value "2N7000")
      (footprint "eagle-import:TO92-DGS")
      (libsource (lib "eagle-import") (part "2N7000"))
    )
    (comp (ref "Q57")
      (value "2N7000")
      (footprint "eagle-import:TO92-DGS")
      (libsource (lib "eagle-import") (part "2N7000"))
    )
    (comp (ref "Q58")
      (value "2N7000")
      (footprint "eagle-import:TO92-DGS")
      (libsource (lib "eagle-import") (part "2N7000"))
    )
    (comp (ref "Q59")
      (value "2N7000")
      (footprint "eagle-import:TO92-DGS")
      (libsource (lib "eagle-import") (part "2N7000"))
    )
    (comp (ref "R46")
      (value "10k")
      (footprint "eagle-import:R_P2INCH")
      (libsource (lib "eagle-import") (part "R_P2INCH"))
    )
    (comp (ref "R47")
      (value "470")
      (footprint "eagle-import:R_P2INCH")
      (libsource (lib "eagle-import") (part "R_P2INCH"))
    )
    (comp (ref "R48")
      (value "10k")
      (footprint "eagle-import:R_P2INCH")
      (libsource (lib "eagle-import") (part "R_P2INCH"))
    )
    (comp (ref "R49")
      (value "470")
      (footprint "eagle-import:R_P2INCH")
      (libsource (lib "eagle-import") (part "R_P2INCH"))
    )
    (comp (ref "R50")
      (value "470")
      (footprint "eagle-import:R_P2INCH")
      (libsource (lib "eagle-import") (part "R_P2INCH"))
    )
    (comp (ref "R51")
      (value "10k")
      (footprint "eagle-import:R_P2INCH")
      (libsource (lib "eagle-import") (part "R_P2INCH"))
    )
    (comp (ref "R52")
      (value "470")
      (footprint "eagle-import:R_P2INCH")
      (libsource (lib "eagle-import") (part "R_P2INCH"))
    )
    (comp (ref "R53")
      (value "10k")
      (footprint "eagle-import:R_P2INCH")
      (libsource (lib "eagle-import") (part "R_P2INCH"))
    )
    (comp (ref "R54")
      (value "470")
      (footprint "eagle-import:R_P2INCH")
      (libsource (lib "eagle-import") (part "R_P2INCH"))
    )
    (comp (ref "R55")
      (value "470")
      (footprint "eagle-import:R_P2INCH")
      (libsource (lib "eagle-import") (part "R_P2INCH"))
    )
    (comp (ref "R71")
      (value "10k")
      (footprint "eagle-import:R_P2INCH")
      (libsource (lib "eagle-import") (part "R_P2INCH"))
    )
    (comp (ref "R72")
      (value "470")
      (footprint "eagle-import:R_P2INCH")
      (libsource (lib "eagle-import") (part "R_P2INCH"))
    )
    (comp (ref "R73")
      (value "10k")
      (footprint "eagle-import:R_P2INCH")
      (libsource (lib "eagle-import") (part "R_P2INCH"))
    )
    (comp (ref "R74")
      (value "470")
      (footprint "eagle-import:R_P2INCH")
      (libsource (lib "eagle-import") (part "R_P2INCH"))
    )
    (comp (ref "R75")
      (value "470")
      (footprint "eagle-import:R_P2INCH")
      (libsource (lib "eagle-import") (part "R_P2INCH"))
    )
    (comp (ref "D109")
      (value "L-1334SRT")
      (footprint "eagle-import:LED3MM")
      (libsource (lib "eagle-import") (part "L-1334SRT"))
    )
    (comp (ref "D110")
      (value "L-1334SRT")
      (footprint "eagle-import:LED3MM")
      (libsource (lib "eagle-import") (part "L-1334SRT"))
    )
    (comp (ref "D111")
      (value "L-1334SRT")
      (footprint "eagle-import:LED3MM")
      (libsource (lib "eagle-import") (part "L-1334SRT"))
    )
    (comp (ref "D112")
      (value "L-1334SRT")
      (footprint "eagle-import:LED3MM")
      (libsource (lib "eagle-import") (part "L-1334SRT"))
    )
    (comp (ref "D113")
      (value "L-1334SRT")
      (footprint "eagle-import:LED3MM")
      (libsource (lib "eagle-import") (part "L-1334SRT"))
    )
    (comp (ref "D114")
      (value "L-1334SRT")
      (footprint "eagle-import:LED3MM")
      (libsource (lib "eagle-import") (part "L-1334SRT"))
    )
    (comp (ref "D115")
      (value "L-1334SRT")
      (footprint "eagle-import:LED3MM")
      (libsource (lib "eagle-import") (part "L-1334SRT"))
    )
    (comp (ref "D116")
      (value "L-1334SRT")
      (footprint "eagle-import:LED3MM")
      (libsource (lib "eagle-import") (part "L-1334SRT"))
    )
    (comp (ref "D117")
      (value "L-1334SRT")
      (footprint "eagle-import:LED3MM")
      (libsource (lib "eagle-import") (part "L-1334SRT"))
    )
    (comp (ref "Q157")
      (value "2N7000")
      (footprint "eagle-import:TO92-DGS")
      (libsource (lib "eagle-import") (part "2N7000"))
    )
    (comp (ref "Q158")
      (value "2N7000")
      (footprint "eagle-import:TO92-DGS")
      (libsource (lib "eagle-import") (part "2N7000"))
    )
    (comp (ref "Q159")
      (value "2N7000")
      (footprint "eagle-import:TO92-DGS")
      (libsource (lib "eagle-import") (part "2N7000"))
    )
    (comp (ref "Q160")
      (value "2N7000")
      (footprint "eagle-import:TO92-DGS")
      (libsource (lib "eagle-import") (part "2N7000"))
    )
    (comp (ref "Q161")
      (value "2N7000")
      (footprint "eagle-import:TO92-DGS")
      (libsource (lib "eagle-import") (part "2N7000"))
    )
    (comp (ref "Q162")
      (value "2N7000")
      (footprint "eagle-import:TO92-DGS")
      (libsource (lib "eagle-import") (part "2N7000"))
    )
    (comp (ref "Q163")
      (value "2N7000")
      (footprint "eagle-import:TO92-DGS")
      (libsource (lib "eagle-import") (part "2N7000"))
    )
    (comp (ref "Q164")
      (value "2N7000")
      (footprint "eagle-import:TO92-DGS")
      (libsource (lib "eagle-import") (part "2N7000"))
    )
    (comp (ref "Q165")
      (value "2N7000")
      (footprint "eagle-import:TO92-DGS")
      (libsource (lib "eagle-import") (part "2N7000"))
    )
    (comp (ref "R181")
      (value "10k")
      (footprint "eagle-import:R_P2INCH")
      (libsource (lib "eagle-import") (part "R_P2INCH"))
    )
    (comp (ref "R182")
      (value "470")
      (footprint "eagle-import:R_P2INCH")
      (libsource (lib "eagle-import") (part "R_P2INCH"))
    )
    (comp (ref "R183")
      (value "10k")
      (footprint "eagle-import:R_P2INCH")
      (libsource (lib "eagle-import") (part "R_P2INCH"))
    )
    (comp (ref "R184")
      (value "470")
      (footprint "eagle-import:R_P2INCH")
      (libsource (lib "eagle-import") (part "R_P2INCH"))
    )
    (comp (ref "R185")
      (value "470")
      (footprint "eagle-import:R_P2INCH")
      (libsource (lib "eagle-import") (part "R_P2INCH"))
    )
    (comp (ref "R186")
      (value "10k")
      (footprint "eagle-import:R_P2INCH")
      (libsource (lib "eagle-import") (part "R_P2INCH"))
    )
    (comp (ref "R187")
      (value "470")
      (footprint "eagle-import:R_P2INCH")
      (libsource (lib "eagle-import") (part "R_P2INCH"))
    )
    (comp (ref "R188")
      (value "10k")
      (footprint "eagle-import:R_P2INCH")
      (libsource (lib "eagle-import") (part "R_P2INCH"))
    )
    (comp (ref "R189")
      (value "470")
      (footprint "eagle-import:R_P2INCH")
      (libsource (lib "eagle-import") (part "R_P2INCH"))
    )
    (comp (ref "R190")
      (value "470")
      (footprint "eagle-import:R_P2INCH")
      (libsource (lib "eagle-import") (part "R_P2INCH"))
    )
    (comp (ref "R191")
      (value "10k")
      (footprint "eagle-import:R_P2INCH")
      (libsource (lib "eagle-import") (part "R_P2INCH"))
    )
    (comp (ref "R192")
      (value "470")
      (footprint "eagle-import:R_P2INCH")
      (libsource (lib "eagle-import") (part "R_P2INCH"))
    )
    (comp (ref "R193")
      (value "10k")
      (footprint "eagle-import:R_P2INCH")
      (libsource (lib "eagle-import") (part "R_P2INCH"))
    )
    (comp (ref "R194")
      (value "470")
      (footprint "eagle-import:R_P2INCH")
      (libsource (lib "eagle-import") (part "R_P2INCH"))
    )
    (comp (ref "R195")
      (value "470")
      (footprint "eagle-import:R_P2INCH")
      (libsource (lib "eagle-import") (part "R_P2INCH"))
    )
    (comp (ref "D49")
      (value "L-1334SRT")
      (footprint "eagle-import:LED3MM")
      (libsource (lib "eagle-import") (part "L-1334SRT"))
    )
    (comp (ref "D50")
      (value "L-1334SRT")
      (footprint "eagle-import:LED3MM")
      (libsource (lib "eagle-import") (part "L-1334SRT"))
    )
    (comp (ref "D51")
      (value "L-1334SRT")
      (footprint "eagle-import:LED3MM")
      (libsource (lib "eagle-import") (part "L-1334SRT"))
    )
    (comp (ref "D52")
      (value "L-1334SRT")
      (footprint "eagle-import:LED3MM")
      (libsource (lib "eagle-import") (part "L-1334SRT"))
    )
    (comp (ref "D53")
      (value "L-1334SRT")
      (footprint "eagle-import:LED3MM")
      (libsource (lib "eagle-import") (part "L-1334SRT"))
    )
    (comp (ref "D54")
      (value "L-1334SRT")
      (footprint "eagle-import:LED3MM")
      (libsource (lib "eagle-import") (part "L-1334SRT"))
    )
    (comp (ref "Q69")
      (value "2N7000")
      (footprint "eagle-import:TO92-DGS")
      (libsource (lib "eagle-import") (part "2N7000"))
    )
    (comp (ref "Q70")
      (value "2N7000")
      (footprint "eagle-import:TO92-DGS")
      (libsource (lib "eagle-import") (part "2N7000"))
    )
    (comp (ref "Q71")
      (value "2N7000")
      (footprint "eagle-import:TO92-DGS")
      (libsource (lib "eagle-import") (part "2N7000"))
    )
    (comp (ref "Q72")
      (value "2N7000")
      (footprint "eagle-import:TO92-DGS")
      (libsource (lib "eagle-import") (part "2N7000"))
    )
    (comp (ref "Q73")
      (value "2N7000")
      (footprint "eagle-import:TO92-DGS")
      (libsource (lib "eagle-import") (part "2N7000"))
    )
    (comp (ref "Q74")
      (value "2N7000")
      (footprint "eagle-import:TO92-DGS")
      (libsource (lib "eagle-import") (part "2N7000"))
    )
    (comp (ref "Q75")
      (value "2N7000")
      (footprint "eagle-import:TO92-DGS")
      (libsource (lib "eagle-import") (part "2N7000"))
    )
    (comp (ref "Q76")
      (value "2N7000")
      (footprint "eagle-import:TO92-DGS")
      (libsource (lib "eagle-import") (part "2N7000"))
    )
    (comp (ref "Q77")
      (value "2N7000")
      (footprint "eagle-import:TO92-DGS")
      (libsource (lib "eagle-import") (part "2N7000"))
    )
    (comp (ref "Q78")
      (value "2N7000")
      (footprint "eagle-import:TO92-DGS")
      (libsource (lib "eagle-import") (part "2N7000"))
    )
    (comp (ref "R81")
      (value "10k")
      (footprint "eagle-import:R_P2INCH")
      (libsource (lib "eagle-import") (part "R_P2INCH"))
    )
    (comp (ref "R82")
      (value "470")
      (footprint "eagle-import:R_P2INCH")
      (libsource (lib "eagle-import") (part "R_P2INCH"))
    )
    (comp (ref "R83")
      (value "10k")
      (footprint "eagle-import:R_P2INCH")
      (libsource (lib "eagle-import") (part "R_P2INCH"))
    )
    (comp (ref "R84")
      (value "470")
      (footprint "eagle-import:R_P2INCH")
      (libsource (lib "eagle-import") (part "R_P2INCH"))
    )
    (comp (ref "R85")
      (value "470")
      (footprint "eagle-import:R_P2INCH")
      (libsource (lib "eagle-import") (part "R_P2INCH"))
    )
    (comp (ref "R86")
      (value "10k")
      (footprint "eagle-import:R_P2INCH")
      (libsource (lib "eagle-import") (part "R_P2INCH"))
    )
    (comp (ref "R87")
      (value "470")
      (footprint "eagle-import:R_P2INCH")
      (libsource (lib "eagle-import") (part "R_P2INCH"))
    )
    (comp (ref "R88")
      (value "10k")
      (footprint "eagle-import:R_P2INCH")
      (libsource (lib "eagle-import") (part "R_P2INCH"))
    )
    (comp (ref "R89")
      (value "470")
      (footprint "eagle-import:R_P2INCH")
      (libsource (lib "eagle-import") (part "R_P2INCH"))
    )
    (comp (ref "R90")
      (value "470")
      (footprint "eagle-import:R_P2INCH")
      (libsource (lib "eagle-import") (part "R_P2INCH"))
    )
    (comp (ref "D73")
      (value "L-1334SRT")
      (footprint "eagle-import:LED3MM")
      (libsource (lib "eagle-import") (part "L-1334SRT"))
    )
    (comp (ref "D74")
      (value "L-1334SRT")
      (footprint "eagle-import:LED3MM")
      (libsource (lib "eagle-import") (part "L-1334SRT"))
    )
    (comp (ref "D75")
      (value "L-1334SRT")
      (footprint "eagle-import:LED3MM")
      (libsource (lib "eagle-import") (part "L-1334SRT"))
    )
    (comp (ref "D76")
      (value "L-1334SRT")
      (footprint "eagle-import:LED3MM")
      (libsource (lib "eagle-import") (part "L-1334SRT"))
    )
    (comp (ref "D77")
      (value "L-1334SRT")
      (footprint "eagle-import:LED3MM")
      (libsource (lib "eagle-import") (part "L-1334SRT"))
    )
    (comp (ref "D78")
      (value "L-1334SRT")
      (footprint "eagle-import:LED3MM")
      (libsource (lib "eagle-import") (part "L-1334SRT"))
    )
    (comp (ref "Q109")
      (value "2N7000")
      (footprint "eagle-import:TO92-DGS")
      (libsource (lib "eagle-import") (part "2N7000"))
    )
    (comp (ref "Q110")
      (value "2N7000")
      (footprint "eagle-import:TO92-DGS")
      (libsource (lib "eagle-import") (part "2N7000"))
    )
    (comp (ref "Q111")
      (value "2N7000")
      (footprint "eagle-import:TO92-DGS")
      (libsource (lib "eagle-import") (part "2N7000"))
    )
    (comp (ref "Q112")
      (value "2N7000")
      (footprint "eagle-import:TO92-DGS")
      (libsource (lib "eagle-import") (part "2N7000"))
    )
    (comp (ref "Q113")
      (value "2N7000")
      (footprint "eagle-import:TO92-DGS")
      (libsource (lib "eagle-import") (part "2N7000"))
    )
    (comp (ref "Q114")
      (value "2N7000")
      (footprint "eagle-import:TO92-DGS")
      (libsource (lib "eagle-import") (part "2N7000"))
    )
    (comp (ref "Q115")
      (value "2N7000")
      (footprint "eagle-import:TO92-DGS")
      (libsource (lib "eagle-import") (part "2N7000"))
    )
    (comp (ref "Q116")
      (value "2N7000")
      (footprint "eagle-import:TO92-DGS")
      (libsource (lib "eagle-import") (part "2N7000"))
    )
    (comp (ref "Q117")
      (value "2N7000")
      (footprint "eagle-import:TO92-DGS")
      (libsource (lib "eagle-import") (part "2N7000"))
    )
    (comp (ref "Q118")
      (value "2N7000")
      (footprint "eagle-import:TO92-DGS")
      (libsource (lib "eagle-import") (part "2N7000"))
    )
    (comp (ref "R121")
      (value "10k")
      (footprint "eagle-import:R_P2INCH")
      (libsource (lib "eagle-import") (part "R_P2INCH"))
    )
    (comp (ref "R122")
      (value "470")
      (footprint "eagle-import:R_P2INCH")
      (libsource (lib "eagle-import") (part "R_P2INCH"))
    )
    (comp (ref "R123")
      (value "10k")
      (footprint "eagle-import:R_P2INCH")
      (libsource (lib "eagle-import") (part "R_P2INCH"))
    )
    (comp (ref "R124")
      (value "470")
      (footprint "eagle-import:R_P2INCH")
      (libsource (lib "eagle-import") (part "R_P2INCH"))
    )
    (comp (ref "R125")
      (value "470")
      (footprint "eagle-import:R_P2INCH")
      (libsource (lib "eagle-import") (part "R_P2INCH"))
    )
    (comp (ref "R126")
      (value "10k")
      (footprint "eagle-import:R_P2INCH")
      (libsource (lib "eagle-import") (part "R_P2INCH"))
    )
    (comp (ref "R127")
      (value "470")
      (footprint "eagle-import:R_P2INCH")
      (libsource (lib "eagle-import") (part "R_P2INCH"))
    )
    (comp (ref "R128")
      (value "10k")
      (footprint "eagle-import:R_P2INCH")
      (libsource (lib "eagle-import") (part "R_P2INCH"))
    )
    (comp (ref "R129")
      (value "470")
      (footprint "eagle-import:R_P2INCH")
      (libsource (lib "eagle-import") (part "R_P2INCH"))
    )
    (comp (ref "R130")
      (value "470")
      (footprint "eagle-import:R_P2INCH")
      (libsource (lib "eagle-import") (part "R_P2INCH"))
    )
    (comp (ref "D85")
      (value "L-1334SRT")
      (footprint "eagle-import:LED3MM")
      (libsource (lib "eagle-import") (part "L-1334SRT"))
    )
    (comp (ref "D86")
      (value "L-1334SRT")
      (footprint "eagle-import:LED3MM")
      (libsource (lib "eagle-import") (part "L-1334SRT"))
    )
    (comp (ref "D87")
      (value "L-1334SRT")
      (footprint "eagle-import:LED3MM")
      (libsource (lib "eagle-import") (part "L-1334SRT"))
    )
    (comp (ref "D88")
      (value "L-1334SRT")
      (footprint "eagle-import:LED3MM")
      (libsource (lib "eagle-import") (part "L-1334SRT"))
    )
    (comp (ref "D89")
      (value "L-1334SRT")
      (footprint "eagle-import:LED3MM")
      (libsource (lib "eagle-import") (part "L-1334SRT"))
    )
    (comp (ref "D90")
      (value "L-1334SRT")
      (footprint "eagle-import:LED3MM")
      (libsource (lib "eagle-import") (part "L-1334SRT"))
    )
    (comp (ref "Q129")
      (value "2N7000")
      (footprint "eagle-import:TO92-DGS")
      (libsource (lib "eagle-import") (part "2N7000"))
    )
    (comp (ref "Q130")
      (value "2N7000")
      (footprint "eagle-import:TO92-DGS")
      (libsource (lib "eagle-import") (part "2N7000"))
    )
    (comp (ref "Q131")
      (value "2N7000")
      (footprint "eagle-import:TO92-DGS")
      (libsource (lib "eagle-import") (part "2N7000"))
    )
    (comp (ref "Q132")
      (value "2N7000")
      (footprint "eagle-import:TO92-DGS")
      (libsource (lib "eagle-import") (part "2N7000"))
    )
    (comp (ref "Q133")
      (value "2N7000")
      (footprint "eagle-import:TO92-DGS")
      (libsource (lib "eagle-import") (part "2N7000"))
    )
    (comp (ref "Q134")
      (value "2N7000")
      (footprint "eagle-import:TO92-DGS")
      (libsource (lib "eagle-import") (part "2N7000"))
    )
    (comp (ref "Q135")
      (value "2N7000")
      (footprint "eagle-import:TO92-DGS")
      (libsource (lib "eagle-import") (part "2N7000"))
    )
    (comp (ref "Q136")
      (value "2N7000")
      (footprint "eagle-import:TO92-DGS")
      (libsource (lib "eagle-import") (part "2N7000"))
    )
    (comp (ref "Q137")
      (value "2N7000")
      (footprint "eagle-import:TO92-DGS")
      (libsource (lib "eagle-import") (part "2N7000"))
    )
    (comp (ref "Q138")
      (value "2N7000")
      (footprint "eagle-import:TO92-DGS")
      (libsource (lib "eagle-import") (part "2N7000"))
    )
    (comp (ref "R141")
      (value "10k")
      (footprint "eagle-import:R_P2INCH")
      (libsource (lib "eagle-import") (part "R_P2INCH"))
    )
    (comp (ref "R142")
      (value "470")
      (footprint "eagle-import:R_P2INCH")
      (libsource (lib "eagle-import") (part "R_P2INCH"))
    )
    (comp (ref "R143")
      (value "10k")
      (footprint "eagle-import:R_P2INCH")
      (libsource (lib "eagle-import") (part "R_P2INCH"))
    )
    (comp (ref "R144")
      (value "470")
      (footprint "eagle-import:R_P2INCH")
      (libsource (lib "eagle-import") (part "R_P2INCH"))
    )
    (comp (ref "R145")
      (value "470")
      (footprint "eagle-import:R_P2INCH")
      (libsource (lib "eagle-import") (part "R_P2INCH"))
    )
    (comp (ref "R146")
      (value "10k")
      (footprint "eagle-import:R_P2INCH")
      (libsource (lib "eagle-import") (part "R_P2INCH"))
    )
    (comp (ref "R147")
      (value "470")
      (footprint "eagle-import:R_P2INCH")
      (libsource (lib "eagle-import") (part "R_P2INCH"))
    )
    (comp (ref "R148")
      (value "10k")
      (footprint "eagle-import:R_P2INCH")
      (libsource (lib "eagle-import") (part "R_P2INCH"))
    )
    (comp (ref "R149")
      (value "470")
      (footprint "eagle-import:R_P2INCH")
      (libsource (lib "eagle-import") (part "R_P2INCH"))
    )
    (comp (ref "R150")
      (value "470")
      (footprint "eagle-import:R_P2INCH")
      (libsource (lib "eagle-import") (part "R_P2INCH"))
    )
    (comp (ref "D22")
      (value "L-1334SRT")
      (footprint "eagle-import:LED3MM")
      (libsource (lib "eagle-import") (part "L-1334SRT"))
    )
    (comp (ref "D23")
      (value "L-1334SRT")
      (footprint "eagle-import:LED3MM")
      (libsource (lib "eagle-import") (part "L-1334SRT"))
    )
    (comp (ref "D24")
      (value "L-1334SRT")
      (footprint "eagle-import:LED3MM")
      (libsource (lib "eagle-import") (part "L-1334SRT"))
    )
    (comp (ref "D25")
      (value "L-1334SRT")
      (footprint "eagle-import:LED3MM")
      (libsource (lib "eagle-import") (part "L-1334SRT"))
    )
    (comp (ref "D26")
      (value "L-1334SRT")
      (footprint "eagle-import:LED3MM")
      (libsource (lib "eagle-import") (part "L-1334SRT"))
    )
    (comp (ref "D27")
      (value "L-1334SRT")
      (footprint "eagle-import:LED3MM")
      (libsource (lib "eagle-import") (part "L-1334SRT"))
    )
    (comp (ref "Q32")
      (value "2N7000")
      (footprint "eagle-import:TO92-DGS")
      (libsource (lib "eagle-import") (part "2N7000"))
    )
    (comp (ref "Q33")
      (value "2N7000")
      (footprint "eagle-import:TO92-DGS")
      (libsource (lib "eagle-import") (part "2N7000"))
    )
    (comp (ref "Q34")
      (value "2N7000")
      (footprint "eagle-import:TO92-DGS")
      (libsource (lib "eagle-import") (part "2N7000"))
    )
    (comp (ref "Q35")
      (value "2N7000")
      (footprint "eagle-import:TO92-DGS")
      (libsource (lib "eagle-import") (part "2N7000"))
    )
    (comp (ref "Q36")
      (value "2N7000")
      (footprint "eagle-import:TO92-DGS")
      (libsource (lib "eagle-import") (part "2N7000"))
    )
    (comp (ref "Q37")
      (value "2N7000")
      (footprint "eagle-import:TO92-DGS")
      (libsource (lib "eagle-import") (part "2N7000"))
    )
    (comp (ref "Q38")
      (value "2N7000")
      (footprint "eagle-import:TO92-DGS")
      (libsource (lib "eagle-import") (part "2N7000"))
    )
    (comp (ref "Q39")
      (value "2N7000")
      (footprint "eagle-import:TO92-DGS")
      (libsource (lib "eagle-import") (part "2N7000"))
    )
    (comp (ref "Q40")
      (value "2N7000")
      (footprint "eagle-import:TO92-DGS")
      (libsource (lib "eagle-import") (part "2N7000"))
    )
    (comp (ref "Q41")
      (value "2N7000")
      (footprint "eagle-import:TO92-DGS")
      (libsource (lib "eagle-import") (part "2N7000"))
    )
    (comp (ref "R36")
      (value "10k")
      (footprint "eagle-import:R_P2INCH")
      (libsource (lib "eagle-import") (part "R_P2INCH"))
    )
    (comp (ref "R37")
      (value "470")
      (footprint "eagle-import:R_P2INCH")
      (libsource (lib "eagle-import") (part "R_P2INCH"))
    )
    (comp (ref "R38")
      (value "10k")
      (footprint "eagle-import:R_P2INCH")
      (libsource (lib "eagle-import") (part "R_P2INCH"))
    )
    (comp (ref "R39")
      (value "470")
      (footprint "eagle-import:R_P2INCH")
      (libsource (lib "eagle-import") (part "R_P2INCH"))
    )
    (comp (ref "R40")
      (value "470")
      (footprint "eagle-import:R_P2INCH")
      (libsource (lib "eagle-import") (part "R_P2INCH"))
    )
    (comp (ref "R41")
      (value "10k")
      (footprint "eagle-import:R_P2INCH")
      (libsource (lib "eagle-import") (part "R_P2INCH"))
    )
    (comp (ref "R42")
      (value "470")
      (footprint "eagle-import:R_P2INCH")
      (libsource (lib "eagle-import") (part "R_P2INCH"))
    )
    (comp (ref "R43")
      (value "10k")
      (footprint "eagle-import:R_P2INCH")
      (libsource (lib "eagle-import") (part "R_P2INCH"))
    )
    (comp (ref "R44")
      (value "470")
      (footprint "eagle-import:R_P2INCH")
      (libsource (lib "eagle-import") (part "R_P2INCH"))
    )
    (comp (ref "R45")
      (value "470")
      (footprint "eagle-import:R_P2INCH")
      (libsource (lib "eagle-import") (part "R_P2INCH"))
    )
    (comp (ref "D145")
      (value "L-1334SRT")
      (footprint "eagle-import:LED3MM")
      (libsource (lib "eagle-import") (part "L-1334SRT"))
    )
    (comp (ref "D146")
      (value "L-1334SRT")
      (footprint "eagle-import:LED3MM")
      (libsource (lib "eagle-import") (part "L-1334SRT"))
    )
    (comp (ref "D147")
      (value "L-1334SRT")
      (footprint "eagle-import:LED3MM")
      (libsource (lib "eagle-import") (part "L-1334SRT"))
    )
    (comp (ref "D148")
      (value "L-1334SRT")
      (footprint "eagle-import:LED3MM")
      (libsource (lib "eagle-import") (part "L-1334SRT"))
    )
    (comp (ref "D149")
      (value "L-1334SRT")
      (footprint "eagle-import:LED3MM")
      (libsource (lib "eagle-import") (part "L-1334SRT"))
    )
    (comp (ref "D150")
      (value "L-1334SRT")
      (footprint "eagle-import:LED3MM")
      (libsource (lib "eagle-import") (part "L-1334SRT"))
    )
    (comp (ref "D151")
      (value "L-1334SRT")
      (footprint "eagle-import:LED3MM")
      (libsource (lib "eagle-import") (part "L-1334SRT"))
    )
    (comp (ref "D152")
      (value "L-1334SRT")
      (footprint "eagle-import:LED3MM")
      (libsource (lib "eagle-import") (part "L-1334SRT"))
    )
    (comp (ref "D153")
      (value "L-1334SRT")
      (footprint "eagle-import:LED3MM")
      (libsource (lib "eagle-import") (part "L-1334SRT"))
    )
    (comp (ref "D155")
      (value "L-1334SRT")
      (footprint "eagle-import:LED3MM")
      (libsource (lib "eagle-import") (part "L-1334SRT"))
    )
    (comp (ref "D156")
      (value "L-1334SRT")
      (footprint "eagle-import:LED3MM")
      (libsource (lib "eagle-import") (part "L-1334SRT"))
    )
    (comp (ref "D157")
      (value "L-1334SRT")
      (footprint "eagle-import:LED3MM")
      (libsource (lib "eagle-import") (part "L-1334SRT"))
    )
    (comp (ref "D158")
      (value "L-1334SRT")
      (footprint "eagle-import:LED3MM")
      (libsource (lib "eagle-import") (part "L-1334SRT"))
    )
    (comp (ref "D159")
      (value "L-1334SRT")
      (footprint "eagle-import:LED3MM")
      (libsource (lib "eagle-import") (part "L-1334SRT"))
    )
    (comp (ref "D160")
      (value "L-1334SRT")
      (footprint "eagle-import:LED3MM")
      (libsource (lib "eagle-import") (part "L-1334SRT"))
    )
    (comp (ref "D161")
      (value "L-1334SRT")
      (footprint "eagle-import:LED3MM")
      (libsource (lib "eagle-import") (part "L-1334SRT"))
    )
    (comp (ref "Q193")
      (value "2N7000")
      (footprint "eagle-import:TO92-DGS")
      (libsource (lib "eagle-import") (part "2N7000"))
    )
    (comp (ref "Q194")
      (value "2N7000")
      (footprint "eagle-import:TO92-DGS")
      (libsource (lib "eagle-import") (part "2N7000"))
    )
    (comp (ref "Q195")
      (value "2N7000")
      (footprint "eagle-import:TO92-DGS")
      (libsource (lib "eagle-import") (part "2N7000"))
    )
    (comp (ref "Q196")
      (value "2N7000")
      (footprint "eagle-import:TO92-DGS")
      (libsource (lib "eagle-import") (part "2N7000"))
    )
    (comp (ref "Q197")
      (value "2N7000")
      (footprint "eagle-import:TO92-DGS")
      (libsource (lib "eagle-import") (part "2N7000"))
    )
    (comp (ref "Q198")
      (value "2N7000")
      (footprint "eagle-import:TO92-DGS")
      (libsource (lib "eagle-import") (part "2N7000"))
    )
    (comp (ref "Q199")
      (value "2N7000")
      (footprint "eagle-import:TO92-DGS")
      (libsource (lib "eagle-import") (part "2N7000"))
    )
    (comp (ref "Q200")
      (value "2N7000")
      (footprint "eagle-import:TO92-DGS")
      (libsource (lib "eagle-import") (part "2N7000"))
    )
    (comp (ref "Q201")
      (value "2N7000")
      (footprint "eagle-import:TO92-DGS")
      (libsource (lib "eagle-import") (part "2N7000"))
    )
    (comp (ref "Q202")
      (value "2N7000")
      (footprint "eagle-import:TO92-DGS")
      (libsource (lib "eagle-import") (part "2N7000"))
    )
    (comp (ref "Q203")
      (value "2N7000")
      (footprint "eagle-import:TO92-DGS")
      (libsource (lib "eagle-import") (part "2N7000"))
    )
    (comp (ref "Q204")
      (value "2N7000")
      (footprint "eagle-import:TO92-DGS")
      (libsource (lib "eagle-import") (part "2N7000"))
    )
    (comp (ref "Q205")
      (value "2N7000")
      (footprint "eagle-import:TO92-DGS")
      (libsource (lib "eagle-import") (part "2N7000"))
    )
    (comp (ref "Q206")
      (value "2N7000")
      (footprint "eagle-import:TO92-DGS")
      (libsource (lib "eagle-import") (part "2N7000"))
    )
    (comp (ref "Q207")
      (value "2N7000")
      (footprint "eagle-import:TO92-DGS")
      (libsource (lib "eagle-import") (part "2N7000"))
    )
    (comp (ref "Q208")
      (value "2N7000")
      (footprint "eagle-import:TO92-DGS")
      (libsource (lib "eagle-import") (part "2N7000"))
    )
    (comp (ref "R241")
      (value "10k")
      (footprint "eagle-import:R_P2INCH")
      (libsource (lib "eagle-import") (part "R_P2INCH"))
    )
    (comp (ref "R242")
      (value "10k")
      (footprint "eagle-import:R_P2INCH")
      (libsource (lib "eagle-import") (part "R_P2INCH"))
    )
    (comp (ref "R243")
      (value "10k")
      (footprint "eagle-import:R_P2INCH")
      (libsource (lib "eagle-import") (part "R_P2INCH"))
    )
    (comp (ref "R244")
      (value "10k")
      (footprint "eagle-import:R_P2INCH")
      (libsource (lib "eagle-import") (part "R_P2INCH"))
    )
    (comp (ref "R245")
      (value "10k")
      (footprint "eagle-import:R_P2INCH")
      (libsource (lib "eagle-import") (part "R_P2INCH"))
    )
    (comp (ref "R246")
      (value "10k")
      (footprint "eagle-import:R_P2INCH")
      (libsource (lib "eagle-import") (part "R_P2INCH"))
    )
    (comp (ref "R247")
      (value "10k")
      (footprint "eagle-import:R_P2INCH")
      (libsource (lib "eagle-import") (part "R_P2INCH"))
    )
    (comp (ref "R248")
      (value "10k")
      (footprint "eagle-import:R_P2INCH")
      (libsource (lib "eagle-import") (part "R_P2INCH"))
    )
    (comp (ref "R249")
      (value "10k")
      (footprint "eagle-import:R_P2INCH")
      (libsource (lib "eagle-import") (part "R_P2INCH"))
    )
    (comp (ref "R250")
      (value "10k")
      (footprint "eagle-import:R_P2INCH")
      (libsource (lib "eagle-import") (part "R_P2INCH"))
    )
    (comp (ref "R251")
      (value "10k")
      (footprint "eagle-import:R_P2INCH")
      (libsource (lib "eagle-import") (part "R_P2INCH"))
    )
    (comp (ref "R252")
      (value "10k")
      (footprint "eagle-import:R_P2INCH")
      (libsource (lib "eagle-import") (part "R_P2INCH"))
    )
    (comp (ref "R253")
      (value "10k")
      (footprint "eagle-import:R_P2INCH")
      (libsource (lib "eagle-import") (part "R_P2INCH"))
    )
    (comp (ref "R254")
      (value "10k")
      (footprint "eagle-import:R_P2INCH")
      (libsource (lib "eagle-import") (part "R_P2INCH"))
    )
    (comp (ref "R255")
      (value "10k")
      (footprint "eagle-import:R_P2INCH")
      (libsource (lib "eagle-import") (part "R_P2INCH"))
    )
    (comp (ref "R256")
      (value "10k")
      (footprint "eagle-import:R_P2INCH")
      (libsource (lib "eagle-import") (part "R_P2INCH"))
    )
    (comp (ref "R259")
      (value "470")
      (footprint "eagle-import:R_P2INCH")
      (libsource (lib "eagle-import") (part "R_P2INCH"))
    )
    (comp (ref "R260")
      (value "470")
      (footprint "eagle-import:R_P2INCH")
      (libsource (lib "eagle-import") (part "R_P2INCH"))
    )
    (comp (ref "R261")
      (value "470")
      (footprint "eagle-import:R_P2INCH")
      (libsource (lib "eagle-import") (part "R_P2INCH"))
    )
    (comp (ref "R262")
      (value "470")
      (footprint "eagle-import:R_P2INCH")
      (libsource (lib "eagle-import") (part "R_P2INCH"))
    )
    (comp (ref "R263")
      (value "470")
      (footprint "eagle-import:R_P2INCH")
      (libsource (lib "eagle-import") (part "R_P2INCH"))
    )
    (comp (ref "R264")
      (value "470")
      (footprint "eagle-import:R_P2INCH")
      (libsource (lib "eagle-import") (part "R_P2INCH"))
    )
    (comp (ref "R265")
      (value "470")
      (footprint "eagle-import:R_P2INCH")
      (libsource (lib "eagle-import") (part "R_P2INCH"))
    )
    (comp (ref "R266")
      (value "470")
      (footprint "eagle-import:R_P2INCH")
      (libsource (lib "eagle-import") (part "R_P2INCH"))
    )
    (comp (ref "R267")
      (value "470")
      (footprint "eagle-import:R_P2INCH")
      (libsource (lib "eagle-import") (part "R_P2INCH"))
    )
    (comp (ref "R269")
      (value "470")
      (footprint "eagle-import:R_P2INCH")
      (libsource (lib "eagle-import") (part "R_P2INCH"))
    )
    (comp (ref "R270")
      (value "470")
      (footprint "eagle-import:R_P2INCH")
      (libsource (lib "eagle-import") (part "R_P2INCH"))
    )
    (comp (ref "R271")
      (value "470")
      (footprint "eagle-import:R_P2INCH")
      (libsource (lib "eagle-import") (part "R_P2INCH"))
    )
    (comp (ref "R272")
      (value "470")
      (footprint "eagle-import:R_P2INCH")
      (libsource (lib "eagle-import") (part "R_P2INCH"))
    )
    (comp (ref "R273")
      (value "470")
      (footprint "eagle-import:R_P2INCH")
      (libsource (lib "eagle-import") (part "R_P2INCH"))
    )
    (comp (ref "R274")
      (value "470")
      (footprint "eagle-import:R_P2INCH")
      (libsource (lib "eagle-import") (part "R_P2INCH"))
    )
    (comp (ref "R275")
      (value "470")
      (footprint "eagle-import:R_P2INCH")
      (libsource (lib "eagle-import") (part "R_P2INCH"))
    )
    (comp (ref "D10")
      (value "L-1334SRT")
      (footprint "eagle-import:LED3MM")
      (libsource (lib "eagle-import") (part "L-1334SRT"))
    )
    (comp (ref "D11")
      (value "L-1334SRT")
      (footprint "eagle-import:LED3MM")
      (libsource (lib "eagle-import") (part "L-1334SRT"))
    )
    (comp (ref "D12")
      (value "L-1334SRT")
      (footprint "eagle-import:LED3MM")
      (libsource (lib "eagle-import") (part "L-1334SRT"))
    )
    (comp (ref "D13")
      (value "L-1334SRT")
      (footprint "eagle-import:LED3MM")
      (libsource (lib "eagle-import") (part "L-1334SRT"))
    )
    (comp (ref "D14")
      (value "L-1334SRT")
      (footprint "eagle-import:LED3MM")
      (libsource (lib "eagle-import") (part "L-1334SRT"))
    )
    (comp (ref "D15")
      (value "L-1334SRT")
      (footprint "eagle-import:LED3MM")
      (libsource (lib "eagle-import") (part "L-1334SRT"))
    )
    (comp (ref "Q12")
      (value "2N7000")
      (footprint "eagle-import:TO92-DGS")
      (libsource (lib "eagle-import") (part "2N7000"))
    )
    (comp (ref "Q13")
      (value "2N7000")
      (footprint "eagle-import:TO92-DGS")
      (libsource (lib "eagle-import") (part "2N7000"))
    )
    (comp (ref "Q14")
      (value "2N7000")
      (footprint "eagle-import:TO92-DGS")
      (libsource (lib "eagle-import") (part "2N7000"))
    )
    (comp (ref "Q15")
      (value "2N7000")
      (footprint "eagle-import:TO92-DGS")
      (libsource (lib "eagle-import") (part "2N7000"))
    )
    (comp (ref "Q16")
      (value "2N7000")
      (footprint "eagle-import:TO92-DGS")
      (libsource (lib "eagle-import") (part "2N7000"))
    )
    (comp (ref "Q17")
      (value "2N7000")
      (footprint "eagle-import:TO92-DGS")
      (libsource (lib "eagle-import") (part "2N7000"))
    )
    (comp (ref "Q18")
      (value "2N7000")
      (footprint "eagle-import:TO92-DGS")
      (libsource (lib "eagle-import") (part "2N7000"))
    )
    (comp (ref "Q19")
      (value "2N7000")
      (footprint "eagle-import:TO92-DGS")
      (libsource (lib "eagle-import") (part "2N7000"))
    )
    (comp (ref "Q20")
      (value "2N7000")
      (footprint "eagle-import:TO92-DGS")
      (libsource (lib "eagle-import") (part "2N7000"))
    )
    (comp (ref "Q21")
      (value "2N7000")
      (footprint "eagle-import:TO92-DGS")
      (libsource (lib "eagle-import") (part "2N7000"))
    )
    (comp (ref "R16")
      (value "10k")
      (footprint "eagle-import:R_P2INCH")
      (libsource (lib "eagle-import") (part "R_P2INCH"))
    )
    (comp (ref "R17")
      (value "470")
      (footprint "eagle-import:R_P2INCH")
      (libsource (lib "eagle-import") (part "R_P2INCH"))
    )
    (comp (ref "R18")
      (value "10k")
      (footprint "eagle-import:R_P2INCH")
      (libsource (lib "eagle-import") (part "R_P2INCH"))
    )
    (comp (ref "R19")
      (value "470")
      (footprint "eagle-import:R_P2INCH")
      (libsource (lib "eagle-import") (part "R_P2INCH"))
    )
    (comp (ref "R20")
      (value "470")
      (footprint "eagle-import:R_P2INCH")
      (libsource (lib "eagle-import") (part "R_P2INCH"))
    )
    (comp (ref "R21")
      (value "10k")
      (footprint "eagle-import:R_P2INCH")
      (libsource (lib "eagle-import") (part "R_P2INCH"))
    )
    (comp (ref "R22")
      (value "470")
      (footprint "eagle-import:R_P2INCH")
      (libsource (lib "eagle-import") (part "R_P2INCH"))
    )
    (comp (ref "R23")
      (value "10k")
      (footprint "eagle-import:R_P2INCH")
      (libsource (lib "eagle-import") (part "R_P2INCH"))
    )
    (comp (ref "R24")
      (value "470")
      (footprint "eagle-import:R_P2INCH")
      (libsource (lib "eagle-import") (part "R_P2INCH"))
    )
    (comp (ref "R25")
      (value "470")
      (footprint "eagle-import:R_P2INCH")
      (libsource (lib "eagle-import") (part "R_P2INCH"))
    )
    (comp (ref "D79")
      (value "L-1334SRT")
      (footprint "eagle-import:LED3MM")
      (libsource (lib "eagle-import") (part "L-1334SRT"))
    )
    (comp (ref "D80")
      (value "L-1334SRT")
      (footprint "eagle-import:LED3MM")
      (libsource (lib "eagle-import") (part "L-1334SRT"))
    )
    (comp (ref "D81")
      (value "L-1334SRT")
      (footprint "eagle-import:LED3MM")
      (libsource (lib "eagle-import") (part "L-1334SRT"))
    )
    (comp (ref "D82")
      (value "L-1334SRT")
      (footprint "eagle-import:LED3MM")
      (libsource (lib "eagle-import") (part "L-1334SRT"))
    )
    (comp (ref "D83")
      (value "L-1334SRT")
      (footprint "eagle-import:LED3MM")
      (libsource (lib "eagle-import") (part "L-1334SRT"))
    )
    (comp (ref "D84")
      (value "L-1334SRT")
      (footprint "eagle-import:LED3MM")
      (libsource (lib "eagle-import") (part "L-1334SRT"))
    )
    (comp (ref "Q119")
      (value "2N7000")
      (footprint "eagle-import:TO92-DGS")
      (libsource (lib "eagle-import") (part "2N7000"))
    )
    (comp (ref "Q120")
      (value "2N7000")
      (footprint "eagle-import:TO92-DGS")
      (libsource (lib "eagle-import") (part "2N7000"))
    )
    (comp (ref "Q121")
      (value "2N7000")
      (footprint "eagle-import:TO92-DGS")
      (libsource (lib "eagle-import") (part "2N7000"))
    )
    (comp (ref "Q122")
      (value "2N7000")
      (footprint "eagle-import:TO92-DGS")
      (libsource (lib "eagle-import") (part "2N7000"))
    )
    (comp (ref "Q123")
      (value "2N7000")
      (footprint "eagle-import:TO92-DGS")
      (libsource (lib "eagle-import") (part "2N7000"))
    )
    (comp (ref "Q124")
      (value "2N7000")
      (footprint "eagle-import:TO92-DGS")
      (libsource (lib "eagle-import") (part "2N7000"))
    )
    (comp (ref "Q125")
      (value "2N7000")
      (footprint "eagle-import:TO92-DGS")
      (libsource (lib "eagle-import") (part "2N7000"))
    )
    (comp (ref "Q126")
      (value "2N7000")
      (footprint "eagle-import:TO92-DGS")
      (libsource (lib "eagle-import") (part "2N7000"))
    )
    (comp (ref "Q127")
      (value "2N7000")
      (footprint "eagle-import:TO92-DGS")
      (libsource (lib "eagle-import") (part "2N7000"))
    )
    (comp (ref "Q128")
      (value "2N7000")
      (footprint "eagle-import:TO92-DGS")
      (libsource (lib "eagle-import") (part "2N7000"))
    )
    (comp (ref "R131")
      (value "10k")
      (footprint "eagle-import:R_P2INCH")
      (libsource (lib "eagle-import") (part "R_P2INCH"))
    )
    (comp (ref "R132")
      (value "470")
      (footprint "eagle-import:R_P2INCH")
      (libsource (lib "eagle-import") (part "R_P2INCH"))
    )
    (comp (ref "R133")
      (value "10k")
      (footprint "eagle-import:R_P2INCH")
      (libsource (lib "eagle-import") (part "R_P2INCH"))
    )
    (comp (ref "R134")
      (value "470")
      (footprint "eagle-import:R_P2INCH")
      (libsource (lib "eagle-import") (part "R_P2INCH"))
    )
    (comp (ref "R135")
      (value "470")
      (footprint "eagle-import:R_P2INCH")
      (libsource (lib "eagle-import") (part "R_P2INCH"))
    )
    (comp (ref "R136")
      (value "10k")
      (footprint "eagle-import:R_P2INCH")
      (libsource (lib "eagle-import") (part "R_P2INCH"))
    )
    (comp (ref "R137")
      (value "470")
      (footprint "eagle-import:R_P2INCH")
      (libsource (lib "eagle-import") (part "R_P2INCH"))
    )
    (comp (ref "R138")
      (value "10k")
      (footprint "eagle-import:R_P2INCH")
      (libsource (lib "eagle-import") (part "R_P2INCH"))
    )
    (comp (ref "R139")
      (value "470")
      (footprint "eagle-import:R_P2INCH")
      (libsource (lib "eagle-import") (part "R_P2INCH"))
    )
    (comp (ref "R140")
      (value "470")
      (footprint "eagle-import:R_P2INCH")
      (libsource (lib "eagle-import") (part "R_P2INCH"))
    )
    (comp (ref "D1")
      (value "L-1334SRT")
      (footprint "eagle-import:LED3MM")
      (libsource (lib "eagle-import") (part "L-1334SRT"))
    )
    (comp (ref "D2")
      (value "L-1334SRT")
      (footprint "eagle-import:LED3MM")
      (libsource (lib "eagle-import") (part "L-1334SRT"))
    )
    (comp (ref "D3")
      (value "L-1334SRT")
      (footprint "eagle-import:LED3MM")
      (libsource (lib "eagle-import") (part "L-1334SRT"))
    )
    (comp (ref "D4")
      (value "L-1334SRT")
      (footprint "eagle-import:LED3MM")
      (libsource (lib "eagle-import") (part "L-1334SRT"))
    )
    (comp (ref "D5")
      (value "L-1334SRT")
      (footprint "eagle-import:LED3MM")
      (libsource (lib "eagle-import") (part "L-1334SRT"))
    )
    (comp (ref "D6")
      (value "L-1334SRT")
      (footprint "eagle-import:LED3MM")
      (libsource (lib "eagle-import") (part "L-1334SRT"))
    )
    (comp (ref "Q1")
      (value "2N7000")
      (footprint "eagle-import:TO92-DGS")
      (libsource (lib "eagle-import") (part "2N7000"))
    )
    (comp (ref "Q2")
      (value "2N7000")
      (footprint "eagle-import:TO92-DGS")
      (libsource (lib "eagle-import") (part "2N7000"))
    )
    (comp (ref "Q3")
      (value "2N7000")
      (footprint "eagle-import:TO92-DGS")
      (libsource (lib "eagle-import") (part "2N7000"))
    )
    (comp (ref "Q4")
      (value "2N7000")
      (footprint "eagle-import:TO92-DGS")
      (libsource (lib "eagle-import") (part "2N7000"))
    )
    (comp (ref "Q5")
      (value "2N7000")
      (footprint "eagle-import:TO92-DGS")
      (libsource (lib "eagle-import") (part "2N7000"))
    )
    (comp (ref "Q6")
      (value "2N7000")
      (footprint "eagle-import:TO92-DGS")
      (libsource (lib "eagle-import") (part "2N7000"))
    )
    (comp (ref "Q7")
      (value "2N7000")
      (footprint "eagle-import:TO92-DGS")
      (libsource (lib "eagle-import") (part "2N7000"))
    )
    (comp (ref "Q8")
      (value "2N7000")
      (footprint "eagle-import:TO92-DGS")
      (libsource (lib "eagle-import") (part "2N7000"))
    )
    (comp (ref "Q9")
      (value "2N7000")
      (footprint "eagle-import:TO92-DGS")
      (libsource (lib "eagle-import") (part "2N7000"))
    )
    (comp (ref "Q10")
      (value "2N7000")
      (footprint "eagle-import:TO92-DGS")
      (libsource (lib "eagle-import") (part "2N7000"))
    )
    (comp (ref "R1")
      (value "10k")
      (footprint "eagle-import:R_P2INCH")
      (libsource (lib "eagle-import") (part "R_P2INCH"))
    )
    (comp (ref "R2")
      (value "470")
      (footprint "eagle-import:R_P2INCH")
      (libsource (lib "eagle-import") (part "R_P2INCH"))
    )
    (comp (ref "R3")
      (value "10k")
      (footprint "eagle-import:R_P2INCH")
      (libsource (lib "eagle-import") (part "R_P2INCH"))
    )
    (comp (ref "R4")
      (value "470")
      (footprint "eagle-import:R_P2INCH")
      (libsource (lib "eagle-import") (part "R_P2INCH"))
    )
    (comp (ref "R5")
      (value "470")
      (footprint "eagle-import:R_P2INCH")
      (libsource (lib "eagle-import") (part "R_P2INCH"))
    )
    (comp (ref "R6")
      (value "10k")
      (footprint "eagle-import:R_P2INCH")
      (libsource (lib "eagle-import") (part "R_P2INCH"))
    )
    (comp (ref "R7")
      (value "470")
      (footprint "eagle-import:R_P2INCH")
      (libsource (lib "eagle-import") (part "R_P2INCH"))
    )
    (comp (ref "R8")
      (value "10k")
      (footprint "eagle-import:R_P2INCH")
      (libsource (lib "eagle-import") (part "R_P2INCH"))
    )
    (comp (ref "R9")
      (value "470")
      (footprint "eagle-import:R_P2INCH")
      (libsource (lib "eagle-import") (part "R_P2INCH"))
    )
    (comp (ref "R10")
      (value "470")
      (footprint "eagle-import:R_P2INCH")
      (libsource (lib "eagle-import") (part "R_P2INCH"))
    )
    (comp (ref "D55")
      (value "L-1334SRT")
      (footprint "eagle-import:LED3MM")
      (libsource (lib "eagle-import") (part "L-1334SRT"))
    )
    (comp (ref "D56")
      (value "L-1334SRT")
      (footprint "eagle-import:LED3MM")
      (libsource (lib "eagle-import") (part "L-1334SRT"))
    )
    (comp (ref "D57")
      (value "L-1334SRT")
      (footprint "eagle-import:LED3MM")
      (libsource (lib "eagle-import") (part "L-1334SRT"))
    )
    (comp (ref "D58")
      (value "L-1334SRT")
      (footprint "eagle-import:LED3MM")
      (libsource (lib "eagle-import") (part "L-1334SRT"))
    )
    (comp (ref "D59")
      (value "L-1334SRT")
      (footprint "eagle-import:LED3MM")
      (libsource (lib "eagle-import") (part "L-1334SRT"))
    )
    (comp (ref "D60")
      (value "L-1334SRT")
      (footprint "eagle-import:LED3MM")
      (libsource (lib "eagle-import") (part "L-1334SRT"))
    )
    (comp (ref "Q79")
      (value "2N7000")
      (footprint "eagle-import:TO92-DGS")
      (libsource (lib "eagle-import") (part "2N7000"))
    )
    (comp (ref "Q80")
      (value "2N7000")
      (footprint "eagle-import:TO92-DGS")
      (libsource (lib "eagle-import") (part "2N7000"))
    )
    (comp (ref "Q81")
      (value "2N7000")
      (footprint "eagle-import:TO92-DGS")
      (libsource (lib "eagle-import") (part "2N7000"))
    )
    (comp (ref "Q82")
      (value "2N7000")
      (footprint "eagle-import:TO92-DGS")
      (libsource (lib "eagle-import") (part "2N7000"))
    )
    (comp (ref "Q83")
      (value "2N7000")
      (footprint "eagle-import:TO92-DGS")
      (libsource (lib "eagle-import") (part "2N7000"))
    )
    (comp (ref "Q84")
      (value "2N7000")
      (footprint "eagle-import:TO92-DGS")
      (libsource (lib "eagle-import") (part "2N7000"))
    )
    (comp (ref "Q85")
      (value "2N7000")
      (footprint "eagle-import:TO92-DGS")
      (libsource (lib "eagle-import") (part "2N7000"))
    )
    (comp (ref "Q86")
      (value "2N7000")
      (footprint "eagle-import:TO92-DGS")
      (libsource (lib "eagle-import") (part "2N7000"))
    )
    (comp (ref "Q87")
      (value "2N7000")
      (footprint "eagle-import:TO92-DGS")
      (libsource (lib "eagle-import") (part "2N7000"))
    )
    (comp (ref "Q88")
      (value "2N7000")
      (footprint "eagle-import:TO92-DGS")
      (libsource (lib "eagle-import") (part "2N7000"))
    )
    (comp (ref "R91")
      (value "10k")
      (footprint "eagle-import:R_P2INCH")
      (libsource (lib "eagle-import") (part "R_P2INCH"))
    )
    (comp (ref "R92")
      (value "470")
      (footprint "eagle-import:R_P2INCH")
      (libsource (lib "eagle-import") (part "R_P2INCH"))
    )
    (comp (ref "R93")
      (value "10k")
      (footprint "eagle-import:R_P2INCH")
      (libsource (lib "eagle-import") (part "R_P2INCH"))
    )
    (comp (ref "R94")
      (value "470")
      (footprint "eagle-import:R_P2INCH")
      (libsource (lib "eagle-import") (part "R_P2INCH"))
    )
    (comp (ref "R95")
      (value "470")
      (footprint "eagle-import:R_P2INCH")
      (libsource (lib "eagle-import") (part "R_P2INCH"))
    )
    (comp (ref "R96")
      (value "10k")
      (footprint "eagle-import:R_P2INCH")
      (libsource (lib "eagle-import") (part "R_P2INCH"))
    )
    (comp (ref "R97")
      (value "470")
      (footprint "eagle-import:R_P2INCH")
      (libsource (lib "eagle-import") (part "R_P2INCH"))
    )
    (comp (ref "R98")
      (value "10k")
      (footprint "eagle-import:R_P2INCH")
      (libsource (lib "eagle-import") (part "R_P2INCH"))
    )
    (comp (ref "R99")
      (value "470")
      (footprint "eagle-import:R_P2INCH")
      (libsource (lib "eagle-import") (part "R_P2INCH"))
    )
    (comp (ref "R100")
      (value "470")
      (footprint "eagle-import:R_P2INCH")
      (libsource (lib "eagle-import") (part "R_P2INCH"))
    )
    (comp (ref "D16")
      (value "L-1334SRT")
      (footprint "eagle-import:LED3MM")
      (libsource (lib "eagle-import") (part "L-1334SRT"))
    )
    (comp (ref "D17")
      (value "L-1334SRT")
      (footprint "eagle-import:LED3MM")
      (libsource (lib "eagle-import") (part "L-1334SRT"))
    )
    (comp (ref "D18")
      (value "L-1334SRT")
      (footprint "eagle-import:LED3MM")
      (libsource (lib "eagle-import") (part "L-1334SRT"))
    )
    (comp (ref "D19")
      (value "L-1334SRT")
      (footprint "eagle-import:LED3MM")
      (libsource (lib "eagle-import") (part "L-1334SRT"))
    )
    (comp (ref "D20")
      (value "L-1334SRT")
      (footprint "eagle-import:LED3MM")
      (libsource (lib "eagle-import") (part "L-1334SRT"))
    )
    (comp (ref "D21")
      (value "L-1334SRT")
      (footprint "eagle-import:LED3MM")
      (libsource (lib "eagle-import") (part "L-1334SRT"))
    )
    (comp (ref "Q22")
      (value "2N7000")
      (footprint "eagle-import:TO92-DGS")
      (libsource (lib "eagle-import") (part "2N7000"))
    )
    (comp (ref "Q23")
      (value "2N7000")
      (footprint "eagle-import:TO92-DGS")
      (libsource (lib "eagle-import") (part "2N7000"))
    )
    (comp (ref "Q24")
      (value "2N7000")
      (footprint "eagle-import:TO92-DGS")
      (libsource (lib "eagle-import") (part "2N7000"))
    )
    (comp (ref "Q25")
      (value "2N7000")
      (footprint "eagle-import:TO92-DGS")
      (libsource (lib "eagle-import") (part "2N7000"))
    )
    (comp (ref "Q26")
      (value "2N7000")
      (footprint "eagle-import:TO92-DGS")
      (libsource (lib "eagle-import") (part "2N7000"))
    )
    (comp (ref "Q27")
      (value "2N7000")
      (footprint "eagle-import:TO92-DGS")
      (libsource (lib "eagle-import") (part "2N7000"))
    )
    (comp (ref "Q28")
      (value "2N7000")
      (footprint "eagle-import:TO92-DGS")
      (libsource (lib "eagle-import") (part "2N7000"))
    )
    (comp (ref "Q29")
      (value "2N7000")
      (footprint "eagle-import:TO92-DGS")
      (libsource (lib "eagle-import") (part "2N7000"))
    )
    (comp (ref "Q30")
      (value "2N7000")
      (footprint "eagle-import:TO92-DGS")
      (libsource (lib "eagle-import") (part "2N7000"))
    )
    (comp (ref "Q31")
      (value "2N7000")
      (footprint "eagle-import:TO92-DGS")
      (libsource (lib "eagle-import") (part "2N7000"))
    )
    (comp (ref "R26")
      (value "10k")
      (footprint "eagle-import:R_P2INCH")
      (libsource (lib "eagle-import") (part "R_P2INCH"))
    )
    (comp (ref "R27")
      (value "470")
      (footprint "eagle-import:R_P2INCH")
      (libsource (lib "eagle-import") (part "R_P2INCH"))
    )
    (comp (ref "R28")
      (value "10k")
      (footprint "eagle-import:R_P2INCH")
      (libsource (lib "eagle-import") (part "R_P2INCH"))
    )
    (comp (ref "R29")
      (value "470")
      (footprint "eagle-import:R_P2INCH")
      (libsource (lib "eagle-import") (part "R_P2INCH"))
    )
    (comp (ref "R30")
      (value "470")
      (footprint "eagle-import:R_P2INCH")
      (libsource (lib "eagle-import") (part "R_P2INCH"))
    )
    (comp (ref "R31")
      (value "10k")
      (footprint "eagle-import:R_P2INCH")
      (libsource (lib "eagle-import") (part "R_P2INCH"))
    )
    (comp (ref "R32")
      (value "470")
      (footprint "eagle-import:R_P2INCH")
      (libsource (lib "eagle-import") (part "R_P2INCH"))
    )
    (comp (ref "R33")
      (value "10k")
      (footprint "eagle-import:R_P2INCH")
      (libsource (lib "eagle-import") (part "R_P2INCH"))
    )
    (comp (ref "R34")
      (value "470")
      (footprint "eagle-import:R_P2INCH")
      (libsource (lib "eagle-import") (part "R_P2INCH"))
    )
    (comp (ref "R35")
      (value "470")
      (footprint "eagle-import:R_P2INCH")
      (libsource (lib "eagle-import") (part "R_P2INCH"))
    )
    (comp (ref "D100")
      (value "L-1334SRT")
      (footprint "eagle-import:LED3MM")
      (libsource (lib "eagle-import") (part "L-1334SRT"))
    )
    (comp (ref "D101")
      (value "L-1334SRT")
      (footprint "eagle-import:LED3MM")
      (libsource (lib "eagle-import") (part "L-1334SRT"))
    )
    (comp (ref "D102")
      (value "L-1334SRT")
      (footprint "eagle-import:LED3MM")
      (libsource (lib "eagle-import") (part "L-1334SRT"))
    )
    (comp (ref "D103")
      (value "L-1334SRT")
      (footprint "eagle-import:LED3MM")
      (libsource (lib "eagle-import") (part "L-1334SRT"))
    )
    (comp (ref "D104")
      (value "L-1334SRT")
      (footprint "eagle-import:LED3MM")
      (libsource (lib "eagle-import") (part "L-1334SRT"))
    )
    (comp (ref "D105")
      (value "L-1334SRT")
      (footprint "eagle-import:LED3MM")
      (libsource (lib "eagle-import") (part "L-1334SRT"))
    )
    (comp (ref "D106")
      (value "L-1334SRT")
      (footprint "eagle-import:LED3MM")
      (libsource (lib "eagle-import") (part "L-1334SRT"))
    )
    (comp (ref "D107")
      (value "L-1334SRT")
      (footprint "eagle-import:LED3MM")
      (libsource (lib "eagle-import") (part "L-1334SRT"))
    )
    (comp (ref "D108")
      (value "L-1334SRT")
      (footprint "eagle-import:LED3MM")
      (libsource (lib "eagle-import") (part "L-1334SRT"))
    )
    (comp (ref "Q148")
      (value "2N7000")
      (footprint "eagle-import:TO92-DGS")
      (libsource (lib "eagle-import") (part "2N7000"))
    )
    (comp (ref "Q149")
      (value "2N7000")
      (footprint "eagle-import:TO92-DGS")
      (libsource (lib "eagle-import") (part "2N7000"))
    )
    (comp (ref "Q150")
      (value "2N7000")
      (footprint "eagle-import:TO92-DGS")
      (libsource (lib "eagle-import") (part "2N7000"))
    )
    (comp (ref "Q151")
      (value "2N7000")
      (footprint "eagle-import:TO92-DGS")
      (libsource (lib "eagle-import") (part "2N7000"))
    )
    (comp (ref "Q152")
      (value "2N7000")
      (footprint "eagle-import:TO92-DGS")
      (libsource (lib "eagle-import") (part "2N7000"))
    )
    (comp (ref "Q153")
      (value "2N7000")
      (footprint "eagle-import:TO92-DGS")
      (libsource (lib "eagle-import") (part "2N7000"))
    )
    (comp (ref "Q154")
      (value "2N7000")
      (footprint "eagle-import:TO92-DGS")
      (libsource (lib "eagle-import") (part "2N7000"))
    )
    (comp (ref "Q155")
      (value "2N7000")
      (footprint "eagle-import:TO92-DGS")
      (libsource (lib "eagle-import") (part "2N7000"))
    )
    (comp (ref "Q156")
      (value "2N7000")
      (footprint "eagle-import:TO92-DGS")
      (libsource (lib "eagle-import") (part "2N7000"))
    )
    (comp (ref "R166")
      (value "10k")
      (footprint "eagle-import:R_P2INCH")
      (libsource (lib "eagle-import") (part "R_P2INCH"))
    )
    (comp (ref "R167")
      (value "470")
      (footprint "eagle-import:R_P2INCH")
      (libsource (lib "eagle-import") (part "R_P2INCH"))
    )
    (comp (ref "R168")
      (value "10k")
      (footprint "eagle-import:R_P2INCH")
      (libsource (lib "eagle-import") (part "R_P2INCH"))
    )
    (comp (ref "R169")
      (value "470")
      (footprint "eagle-import:R_P2INCH")
      (libsource (lib "eagle-import") (part "R_P2INCH"))
    )
    (comp (ref "R170")
      (value "470")
      (footprint "eagle-import:R_P2INCH")
      (libsource (lib "eagle-import") (part "R_P2INCH"))
    )
    (comp (ref "R171")
      (value "10k")
      (footprint "eagle-import:R_P2INCH")
      (libsource (lib "eagle-import") (part "R_P2INCH"))
    )
    (comp (ref "R172")
      (value "470")
      (footprint "eagle-import:R_P2INCH")
      (libsource (lib "eagle-import") (part "R_P2INCH"))
    )
    (comp (ref "R173")
      (value "10k")
      (footprint "eagle-import:R_P2INCH")
      (libsource (lib "eagle-import") (part "R_P2INCH"))
    )
    (comp (ref "R174")
      (value "470")
      (footprint "eagle-import:R_P2INCH")
      (libsource (lib "eagle-import") (part "R_P2INCH"))
    )
    (comp (ref "R175")
      (value "470")
      (footprint "eagle-import:R_P2INCH")
      (libsource (lib "eagle-import") (part "R_P2INCH"))
    )
    (comp (ref "R176")
      (value "10k")
      (footprint "eagle-import:R_P2INCH")
      (libsource (lib "eagle-import") (part "R_P2INCH"))
    )
    (comp (ref "R177")
      (value "470")
      (footprint "eagle-import:R_P2INCH")
      (libsource (lib "eagle-import") (part "R_P2INCH"))
    )
    (comp (ref "R178")
      (value "10k")
      (footprint "eagle-import:R_P2INCH")
      (libsource (lib "eagle-import") (part "R_P2INCH"))
    )
    (comp (ref "R179")
      (value "470")
      (footprint "eagle-import:R_P2INCH")
      (libsource (lib "eagle-import") (part "R_P2INCH"))
    )
    (comp (ref "R180")
      (value "470")
      (footprint "eagle-import:R_P2INCH")
      (libsource (lib "eagle-import") (part "R_P2INCH"))
    )
    (comp (ref "D118")
      (value "L-1334SRT")
      (footprint "eagle-import:LED3MM")
      (libsource (lib "eagle-import") (part "L-1334SRT"))
    )
    (comp (ref "D119")
      (value "L-1334SRT")
      (footprint "eagle-import:LED3MM")
      (libsource (lib "eagle-import") (part "L-1334SRT"))
    )
    (comp (ref "D120")
      (value "L-1334SRT")
      (footprint "eagle-import:LED3MM")
      (libsource (lib "eagle-import") (part "L-1334SRT"))
    )
    (comp (ref "D121")
      (value "L-1334SRT")
      (footprint "eagle-import:LED3MM")
      (libsource (lib "eagle-import") (part "L-1334SRT"))
    )
    (comp (ref "D122")
      (value "L-1334SRT")
      (footprint "eagle-import:LED3MM")
      (libsource (lib "eagle-import") (part "L-1334SRT"))
    )
    (comp (ref "D123")
      (value "L-1334SRT")
      (footprint "eagle-import:LED3MM")
      (libsource (lib "eagle-import") (part "L-1334SRT"))
    )
    (comp (ref "D124")
      (value "L-1334SRT")
      (footprint "eagle-import:LED3MM")
      (libsource (lib "eagle-import") (part "L-1334SRT"))
    )
    (comp (ref "D125")
      (value "L-1334SRT")
      (footprint "eagle-import:LED3MM")
      (libsource (lib "eagle-import") (part "L-1334SRT"))
    )
    (comp (ref "D126")
      (value "L-1334SRT")
      (footprint "eagle-import:LED3MM")
      (libsource (lib "eagle-import") (part "L-1334SRT"))
    )
    (comp (ref "Q166")
      (value "2N7000")
      (footprint "eagle-import:TO92-DGS")
      (libsource (lib "eagle-import") (part "2N7000"))
    )
    (comp (ref "Q167")
      (value "2N7000")
      (footprint "eagle-import:TO92-DGS")
      (libsource (lib "eagle-import") (part "2N7000"))
    )
    (comp (ref "Q168")
      (value "2N7000")
      (footprint "eagle-import:TO92-DGS")
      (libsource (lib "eagle-import") (part "2N7000"))
    )
    (comp (ref "Q169")
      (value "2N7000")
      (footprint "eagle-import:TO92-DGS")
      (libsource (lib "eagle-import") (part "2N7000"))
    )
    (comp (ref "Q170")
      (value "2N7000")
      (footprint "eagle-import:TO92-DGS")
      (libsource (lib "eagle-import") (part "2N7000"))
    )
    (comp (ref "Q171")
      (value "2N7000")
      (footprint "eagle-import:TO92-DGS")
      (libsource (lib "eagle-import") (part "2N7000"))
    )
    (comp (ref "Q172")
      (value "2N7000")
      (footprint "eagle-import:TO92-DGS")
      (libsource (lib "eagle-import") (part "2N7000"))
    )
    (comp (ref "Q173")
      (value "2N7000")
      (footprint "eagle-import:TO92-DGS")
      (libsource (lib "eagle-import") (part "2N7000"))
    )
    (comp (ref "Q174")
      (value "2N7000")
      (footprint "eagle-import:TO92-DGS")
      (libsource (lib "eagle-import") (part "2N7000"))
    )
    (comp (ref "R196")
      (value "10k")
      (footprint "eagle-import:R_P2INCH")
      (libsource (lib "eagle-import") (part "R_P2INCH"))
    )
    (comp (ref "R197")
      (value "470")
      (footprint "eagle-import:R_P2INCH")
      (libsource (lib "eagle-import") (part "R_P2INCH"))
    )
    (comp (ref "R198")
      (value "10k")
      (footprint "eagle-import:R_P2INCH")
      (libsource (lib "eagle-import") (part "R_P2INCH"))
    )
    (comp (ref "R199")
      (value "470")
      (footprint "eagle-import:R_P2INCH")
      (libsource (lib "eagle-import") (part "R_P2INCH"))
    )
    (comp (ref "R200")
      (value "470")
      (footprint "eagle-import:R_P2INCH")
      (libsource (lib "eagle-import") (part "R_P2INCH"))
    )
    (comp (ref "R201")
      (value "10k")
      (footprint "eagle-import:R_P2INCH")
      (libsource (lib "eagle-import") (part "R_P2INCH"))
    )
    (comp (ref "R202")
      (value "470")
      (footprint "eagle-import:R_P2INCH")
      (libsource (lib "eagle-import") (part "R_P2INCH"))
    )
    (comp (ref "R203")
      (value "10k")
      (footprint "eagle-import:R_P2INCH")
      (libsource (lib "eagle-import") (part "R_P2INCH"))
    )
    (comp (ref "R204")
      (value "470")
      (footprint "eagle-import:R_P2INCH")
      (libsource (lib "eagle-import") (part "R_P2INCH"))
    )
    (comp (ref "R205")
      (value "470")
      (footprint "eagle-import:R_P2INCH")
      (libsource (lib "eagle-import") (part "R_P2INCH"))
    )
    (comp (ref "R206")
      (value "10k")
      (footprint "eagle-import:R_P2INCH")
      (libsource (lib "eagle-import") (part "R_P2INCH"))
    )
    (comp (ref "R207")
      (value "470")
      (footprint "eagle-import:R_P2INCH")
      (libsource (lib "eagle-import") (part "R_P2INCH"))
    )
    (comp (ref "R208")
      (value "10k")
      (footprint "eagle-import:R_P2INCH")
      (libsource (lib "eagle-import") (part "R_P2INCH"))
    )
    (comp (ref "R209")
      (value "470")
      (footprint "eagle-import:R_P2INCH")
      (libsource (lib "eagle-import") (part "R_P2INCH"))
    )
    (comp (ref "R210")
      (value "470")
      (footprint "eagle-import:R_P2INCH")
      (libsource (lib "eagle-import") (part "R_P2INCH"))
    )
    (comp (ref "D61")
      (value "L-1334SRT")
      (footprint "eagle-import:LED3MM")
      (libsource (lib "eagle-import") (part "L-1334SRT"))
    )
    (comp (ref "D62")
      (value "L-1334SRT")
      (footprint "eagle-import:LED3MM")
      (libsource (lib "eagle-import") (part "L-1334SRT"))
    )
    (comp (ref "D63")
      (value "L-1334SRT")
      (footprint "eagle-import:LED3MM")
      (libsource (lib "eagle-import") (part "L-1334SRT"))
    )
    (comp (ref "D64")
      (value "L-1334SRT")
      (footprint "eagle-import:LED3MM")
      (libsource (lib "eagle-import") (part "L-1334SRT"))
    )
    (comp (ref "D65")
      (value "L-1334SRT")
      (footprint "eagle-import:LED3MM")
      (libsource (lib "eagle-import") (part "L-1334SRT"))
    )
    (comp (ref "D66")
      (value "L-1334SRT")
      (footprint "eagle-import:LED3MM")
      (libsource (lib "eagle-import") (part "L-1334SRT"))
    )
    (comp (ref "Q89")
      (value "2N7000")
      (footprint "eagle-import:TO92-DGS")
      (libsource (lib "eagle-import") (part "2N7000"))
    )
    (comp (ref "Q90")
      (value "2N7000")
      (footprint "eagle-import:TO92-DGS")
      (libsource (lib "eagle-import") (part "2N7000"))
    )
    (comp (ref "Q91")
      (value "2N7000")
      (footprint "eagle-import:TO92-DGS")
      (libsource (lib "eagle-import") (part "2N7000"))
    )
    (comp (ref "Q92")
      (value "2N7000")
      (footprint "eagle-import:TO92-DGS")
      (libsource (lib "eagle-import") (part "2N7000"))
    )
    (comp (ref "Q93")
      (value "2N7000")
      (footprint "eagle-import:TO92-DGS")
      (libsource (lib "eagle-import") (part "2N7000"))
    )
    (comp (ref "Q94")
      (value "2N7000")
      (footprint "eagle-import:TO92-DGS")
      (libsource (lib "eagle-import") (part "2N7000"))
    )
    (comp (ref "Q95")
      (value "2N7000")
      (footprint "eagle-import:TO92-DGS")
      (libsource (lib "eagle-import") (part "2N7000"))
    )
    (comp (ref "Q96")
      (value "2N7000")
      (footprint "eagle-import:TO92-DGS")
      (libsource (lib "eagle-import") (part "2N7000"))
    )
    (comp (ref "Q97")
      (value "2N7000")
      (footprint "eagle-import:TO92-DGS")
      (libsource (lib "eagle-import") (part "2N7000"))
    )
    (comp (ref "Q98")
      (value "2N7000")
      (footprint "eagle-import:TO92-DGS")
      (libsource (lib "eagle-import") (part "2N7000"))
    )
    (comp (ref "R101")
      (value "10k")
      (footprint "eagle-import:R_P2INCH")
      (libsource (lib "eagle-import") (part "R_P2INCH"))
    )
    (comp (ref "R102")
      (value "470")
      (footprint "eagle-import:R_P2INCH")
      (libsource (lib "eagle-import") (part "R_P2INCH"))
    )
    (comp (ref "R103")
      (value "10k")
      (footprint "eagle-import:R_P2INCH")
      (libsource (lib "eagle-import") (part "R_P2INCH"))
    )
    (comp (ref "R104")
      (value "470")
      (footprint "eagle-import:R_P2INCH")
      (libsource (lib "eagle-import") (part "R_P2INCH"))
    )
    (comp (ref "R105")
      (value "470")
      (footprint "eagle-import:R_P2INCH")
      (libsource (lib "eagle-import") (part "R_P2INCH"))
    )
    (comp (ref "R106")
      (value "10k")
      (footprint "eagle-import:R_P2INCH")
      (libsource (lib "eagle-import") (part "R_P2INCH"))
    )
    (comp (ref "R107")
      (value "470")
      (footprint "eagle-import:R_P2INCH")
      (libsource (lib "eagle-import") (part "R_P2INCH"))
    )
    (comp (ref "R108")
      (value "10k")
      (footprint "eagle-import:R_P2INCH")
      (libsource (lib "eagle-import") (part "R_P2INCH"))
    )
    (comp (ref "R109")
      (value "470")
      (footprint "eagle-import:R_P2INCH")
      (libsource (lib "eagle-import") (part "R_P2INCH"))
    )
    (comp (ref "R110")
      (value "470")
      (footprint "eagle-import:R_P2INCH")
      (libsource (lib "eagle-import") (part "R_P2INCH"))
    )
    (comp (ref "D67")
      (value "L-1334SRT")
      (footprint "eagle-import:LED3MM")
      (libsource (lib "eagle-import") (part "L-1334SRT"))
    )
    (comp (ref "D68")
      (value "L-1334SRT")
      (footprint "eagle-import:LED3MM")
      (libsource (lib "eagle-import") (part "L-1334SRT"))
    )
    (comp (ref "D69")
      (value "L-1334SRT")
      (footprint "eagle-import:LED3MM")
      (libsource (lib "eagle-import") (part "L-1334SRT"))
    )
    (comp (ref "D70")
      (value "L-1334SRT")
      (footprint "eagle-import:LED3MM")
      (libsource (lib "eagle-import") (part "L-1334SRT"))
    )
    (comp (ref "D71")
      (value "L-1334SRT")
      (footprint "eagle-import:LED3MM")
      (libsource (lib "eagle-import") (part "L-1334SRT"))
    )
    (comp (ref "D72")
      (value "L-1334SRT")
      (footprint "eagle-import:LED3MM")
      (libsource (lib "eagle-import") (part "L-1334SRT"))
    )
    (comp (ref "Q99")
      (value "2N7000")
      (footprint "eagle-import:TO92-DGS")
      (libsource (lib "eagle-import") (part "2N7000"))
    )
    (comp (ref "Q100")
      (value "2N7000")
      (footprint "eagle-import:TO92-DGS")
      (libsource (lib "eagle-import") (part "2N7000"))
    )
    (comp (ref "Q101")
      (value "2N7000")
      (footprint "eagle-import:TO92-DGS")
      (libsource (lib "eagle-import") (part "2N7000"))
    )
    (comp (ref "Q102")
      (value "2N7000")
      (footprint "eagle-import:TO92-DGS")
      (libsource (lib "eagle-import") (part "2N7000"))
    )
    (comp (ref "Q103")
      (value "2N7000")
      (footprint "eagle-import:TO92-DGS")
      (libsource (lib "eagle-import") (part "2N7000"))
    )
    (comp (ref "Q104")
      (value "2N7000")
      (footprint "eagle-import:TO92-DGS")
      (libsource (lib "eagle-import") (part "2N7000"))
    )
    (comp (ref "Q105")
      (value "2N7000")
      (footprint "eagle-import:TO92-DGS")
      (libsource (lib "eagle-import") (part "2N7000"))
    )
    (comp (ref "Q106")
      (value "2N7000")
      (footprint "eagle-import:TO92-DGS")
      (libsource (lib "eagle-import") (part "2N7000"))
    )
    (comp (ref "Q107")
      (value "2N7000")
      (footprint "eagle-import:TO92-DGS")
      (libsource (lib "eagle-import") (part "2N7000"))
    )
    (comp (ref "Q108")
      (value "2N7000")
      (footprint "eagle-import:TO92-DGS")
      (libsource (lib "eagle-import") (part "2N7000"))
    )
    (comp (ref "R111")
      (value "10k")
      (footprint "eagle-import:R_P2INCH")
      (libsource (lib "eagle-import") (part "R_P2INCH"))
    )
    (comp (ref "R112")
      (value "470")
      (footprint "eagle-import:R_P2INCH")
      (libsource (lib "eagle-import") (part "R_P2INCH"))
    )
    (comp (ref "R113")
      (value "10k")
      (footprint "eagle-import:R_P2INCH")
      (libsource (lib "eagle-import") (part "R_P2INCH"))
    )
    (comp (ref "R114")
      (value "470")
      (footprint "eagle-import:R_P2INCH")
      (libsource (lib "eagle-import") (part "R_P2INCH"))
    )
    (comp (ref "R115")
      (value "470")
      (footprint "eagle-import:R_P2INCH")
      (libsource (lib "eagle-import") (part "R_P2INCH"))
    )
    (comp (ref "R116")
      (value "10k")
      (footprint "eagle-import:R_P2INCH")
      (libsource (lib "eagle-import") (part "R_P2INCH"))
    )
    (comp (ref "R117")
      (value "470")
      (footprint "eagle-import:R_P2INCH")
      (libsource (lib "eagle-import") (part "R_P2INCH"))
    )
    (comp (ref "R118")
      (value "10k")
      (footprint "eagle-import:R_P2INCH")
      (libsource (lib "eagle-import") (part "R_P2INCH"))
    )
    (comp (ref "R119")
      (value "470")
      (footprint "eagle-import:R_P2INCH")
      (libsource (lib "eagle-import") (part "R_P2INCH"))
    )
    (comp (ref "R120")
      (value "470")
      (footprint "eagle-import:R_P2INCH")
      (libsource (lib "eagle-import") (part "R_P2INCH"))
    )
    (comp (ref "D154")
      (value "L-1334SRT")
      (footprint "eagle-import:LED3MM")
      (libsource (lib "eagle-import") (part "L-1334SRT"))
    )
    (comp (ref "D163")
      (value "L-1334SRT")
      (footprint "eagle-import:LED3MM")
      (libsource (lib "eagle-import") (part "L-1334SRT"))
    )
    (comp (ref "D164")
      (value "L-1334SRT")
      (footprint "eagle-import:LED3MM")
      (libsource (lib "eagle-import") (part "L-1334SRT"))
    )
    (comp (ref "D165")
      (value "L-1334SRT")
      (footprint "eagle-import:LED3MM")
      (libsource (lib "eagle-import") (part "L-1334SRT"))
    )
    (comp (ref "D166")
      (value "L-1334SRT")
      (footprint "eagle-import:LED3MM")
      (libsource (lib "eagle-import") (part "L-1334SRT"))
    )
    (comp (ref "D167")
      (value "L-1334SRT")
      (footprint "eagle-import:LED3MM")
      (libsource (lib "eagle-import") (part "L-1334SRT"))
    )
    (comp (ref "D168")
      (value "L-1334SRT")
      (footprint "eagle-import:LED3MM")
      (libsource (lib "eagle-import") (part "L-1334SRT"))
    )
    (comp (ref "D169")
      (value "L-1334SRT")
      (footprint "eagle-import:LED3MM")
      (libsource (lib "eagle-import") (part "L-1334SRT"))
    )
    (comp (ref "D170")
      (value "L-1334SRT")
      (footprint "eagle-import:LED3MM")
      (libsource (lib "eagle-import") (part "L-1334SRT"))
    )
    (comp (ref "D171")
      (value "L-1334SRT")
      (footprint "eagle-import:LED3MM")
      (libsource (lib "eagle-import") (part "L-1334SRT"))
    )
    (comp (ref "D172")
      (value "L-1334SRT")
      (footprint "eagle-import:LED3MM")
      (libsource (lib "eagle-import") (part "L-1334SRT"))
    )
    (comp (ref "Q209")
      (value "2N7000")
      (footprint "eagle-import:TO92-DGS")
      (libsource (lib "eagle-import") (part "2N7000"))
    )
    (comp (ref "Q210")
      (value "2N7000")
      (footprint "eagle-import:TO92-DGS")
      (libsource (lib "eagle-import") (part "2N7000"))
    )
    (comp (ref "Q211")
      (value "2N7000")
      (footprint "eagle-import:TO92-DGS")
      (libsource (lib "eagle-import") (part "2N7000"))
    )
    (comp (ref "Q212")
      (value "2N7000")
      (footprint "eagle-import:TO92-DGS")
      (libsource (lib "eagle-import") (part "2N7000"))
    )
    (comp (ref "Q213")
      (value "2N7000")
      (footprint "eagle-import:TO92-DGS")
      (libsource (lib "eagle-import") (part "2N7000"))
    )
    (comp (ref "R257")
      (value "10k")
      (footprint "eagle-import:R_P2INCH")
      (libsource (lib "eagle-import") (part "R_P2INCH"))
    )
    (comp (ref "R258")
      (value "470")
      (footprint "eagle-import:R_P2INCH")
      (libsource (lib "eagle-import") (part "R_P2INCH"))
    )
    (comp (ref "R268")
      (value "10k")
      (footprint "eagle-import:R_P2INCH")
      (libsource (lib "eagle-import") (part "R_P2INCH"))
    )
    (comp (ref "R277")
      (value "470")
      (footprint "eagle-import:R_P2INCH")
      (libsource (lib "eagle-import") (part "R_P2INCH"))
    )
    (comp (ref "R278")
      (value "470")
      (footprint "eagle-import:R_P2INCH")
      (libsource (lib "eagle-import") (part "R_P2INCH"))
    )
    (comp (ref "R279")
      (value "470")
      (footprint "eagle-import:R_P2INCH")
      (libsource (lib "eagle-import") (part "R_P2INCH"))
    )
    (comp (ref "R280")
      (value "470")
      (footprint "eagle-import:R_P2INCH")
      (libsource (lib "eagle-import") (part "R_P2INCH"))
    )
    (comp (ref "R281")
      (value "470")
      (footprint "eagle-import:R_P2INCH")
      (libsource (lib "eagle-import") (part "R_P2INCH"))
    )
    (comp (ref "R282")
      (value "470")
      (footprint "eagle-import:R_P2INCH")
      (libsource (lib "eagle-import") (part "R_P2INCH"))
    )
    (comp (ref "R283")
      (value "470")
      (footprint "eagle-import:R_P2INCH")
      (libsource (lib "eagle-import") (part "R_P2INCH"))
    )
    (comp (ref "R284")
      (value "470")
      (footprint "eagle-import:R_P2INCH")
      (libsource (lib "eagle-import") (part "R_P2INCH"))
    )
    (comp (ref "R285")
      (value "10k")
      (footprint "eagle-import:R_P2INCH")
      (libsource (lib "eagle-import") (part "R_P2INCH"))
    )
    (comp (ref "R286")
      (value "470")
      (footprint "eagle-import:R_P2INCH")
      (libsource (lib "eagle-import") (part "R_P2INCH"))
    )
    (comp (ref "R287")
      (value "10k")
      (footprint "eagle-import:R_P2INCH")
      (libsource (lib "eagle-import") (part "R_P2INCH"))
    )
    (comp (ref "R288")
      (value "470")
      (footprint "eagle-import:R_P2INCH")
      (libsource (lib "eagle-import") (part "R_P2INCH"))
    )
    (comp (ref "R289")
      (value "10k")
      (footprint "eagle-import:R_P2INCH")
      (libsource (lib "eagle-import") (part "R_P2INCH"))
    )
    (comp (ref "J4")
      (value "30_HDR_LOCKING_RA")
      (footprint "eagle-import:30_HDR_LOCKING_RA")
      (libsource (lib "eagle-import") (part "30_HDR_LOCKING_RA"))
    )
    (comp (ref "C1")
      (value "100n")
      (footprint "eagle-import:CAP_P2INCH")
      (libsource (lib "eagle-import") (part "C_P2INCH"))
    )
    (comp (ref "C2")
      (value "100n")
      (footprint "eagle-import:CAP_P2INCH")
      (libsource (lib "eagle-import") (part "C_P2INCH"))
    )
    (comp (ref "C3")
      (value "100n")
      (footprint "eagle-import:CAP_P2INCH")
      (libsource (lib "eagle-import") (part "C_P2INCH"))
    )
    (comp (ref "C4")
      (value "100n")
      (footprint "eagle-import:CAP_P2INCH")
      (libsource (lib "eagle-import") (part "C_P2INCH"))
    )
    (comp (ref "C5")
      (value "100n")
      (footprint "eagle-import:CAP_P2INCH")
      (libsource (lib "eagle-import") (part "C_P2INCH"))
    )
    (comp (ref "C6")
      (value "100uF")
      (footprint "eagle-import:POLARISED_CAP_2P5")
      (libsource (lib "eagle-import") (part "POLARISED_CAP_2P5"))
    )
    (comp (ref "HOLE1")
      (value "3M_MOUNT_HOLE")
      (footprint "eagle-import:3M_HOLE")
      (libsource (lib "eagle-import") (part "3M_MOUNT_HOLE"))
    )
    (comp (ref "HOLE2")
      (value "3M_MOUNT_HOLE")
      (footprint "eagle-import:3M_HOLE")
      (libsource (lib "eagle-import") (part "3M_MOUNT_HOLE"))
    )
    (comp (ref "HOLE3")
      (value "3M_MOUNT_HOLE")
      (footprint "eagle-import:3M_HOLE")
      (libsource (lib "eagle-import") (part "3M_MOUNT_HOLE"))
    )
    (comp (ref "HOLE4")
      (value "3M_MOUNT_HOLE")
      (footprint "eagle-import:3M_HOLE")
      (libsource (lib "eagle-import") (part "3M_MOUNT_HOLE"))
    )
    (comp (ref "HOLE5")
      (value "3M_MOUNT_HOLE")
      (footprint "eagle-import:3M_HOLE")
      (libsource (lib "eagle-import") (part "3M_MOUNT_HOLE"))
    )
    (comp (ref "HOLE6")
      (value "3M_MOUNT_HOLE")
      (footprint "eagle-import:3M_HOLE")
      (libsource (lib "eagle-import") (part "3M_MOUNT_HOLE"))
    )
    (comp (ref "HOLE7")
      (value "3M_MOUNT_HOLE")
      (footprint "eagle-import:3M_HOLE")
      (libsource (lib "eagle-import") (part "3M_MOUNT_HOLE"))
    )
    (comp (ref "HOLE8")
      (value "3M_MOUNT_HOLE")
      (footprint "eagle-import:3M_HOLE")
      (libsource (lib "eagle-import") (part "3M_MOUNT_HOLE"))
    )
    (comp (ref "PP1")
      (value "POWER_PAD")
      (footprint "eagle-import:POWER_PAD")
      (libsource (lib "eagle-import") (part "POWER_PAD"))
    )
    (comp (ref "PP2")
      (value "POWER_PAD")
      (footprint "eagle-import:POWER_PAD")
      (libsource (lib "eagle-import") (part "POWER_PAD"))
    )
    (comp (ref "TP4")
      (value "TEST_LOOP")
      (footprint "eagle-import:TEST_LOOP")
      (libsource (lib "eagle-import") (part "TEST_LOOP"))
    )
    (comp (ref "TP5")
      (value "TEST_LOOP")
      (footprint "eagle-import:TEST_LOOP")
      (libsource (lib "eagle-import") (part "TEST_LOOP"))
    )
    (comp (ref "TP6")
      (value "TEST_LOOP")
      (footprint "eagle-import:TEST_LOOP")
      (libsource (lib "eagle-import") (part "TEST_LOOP"))
    )
    (comp (ref "TP7")
      (value "TEST_LOOP")
      (footprint "eagle-import:TEST_LOOP")
      (libsource (lib "eagle-import") (part "TEST_LOOP"))
    )
    (comp (ref "D7")
      (value "L-1334SRT")
      (footprint "eagle-import:LED3MM")
      (libsource (lib "eagle-import") (part "L-1334SRT"))
    )
    (comp (ref "D8")
      (value "L-1334SRT")
      (footprint "eagle-import:LED3MM")
      (libsource (lib "eagle-import") (part "L-1334SRT"))
    )
    (comp (ref "D9")
      (value "L-1334SRT")
      (footprint "eagle-import:LED3MM")
      (libsource (lib "eagle-import") (part "L-1334SRT"))
    )
    (comp (ref "D46")
      (value "L-1334SRT")
      (footprint "eagle-import:LED3MM")
      (libsource (lib "eagle-import") (part "L-1334SRT"))
    )
    (comp (ref "D47")
      (value "L-1334SRT")
      (footprint "eagle-import:LED3MM")
      (libsource (lib "eagle-import") (part "L-1334SRT"))
    )
    (comp (ref "D48")
      (value "L-1334SRT")
      (footprint "eagle-import:LED3MM")
      (libsource (lib "eagle-import") (part "L-1334SRT"))
    )
    (comp (ref "Q11")
      (value "2N7000")
      (footprint "eagle-import:TO92-DGS")
      (libsource (lib "eagle-import") (part "2N7000"))
    )
    (comp (ref "Q60")
      (value "2N7000")
      (footprint "eagle-import:TO92-DGS")
      (libsource (lib "eagle-import") (part "2N7000"))
    )
    (comp (ref "Q61")
      (value "2N7000")
      (footprint "eagle-import:TO92-DGS")
      (libsource (lib "eagle-import") (part "2N7000"))
    )
    (comp (ref "Q62")
      (value "2N7000")
      (footprint "eagle-import:TO92-DGS")
      (libsource (lib "eagle-import") (part "2N7000"))
    )
    (comp (ref "Q63")
      (value "2N7000")
      (footprint "eagle-import:TO92-DGS")
      (libsource (lib "eagle-import") (part "2N7000"))
    )
    (comp (ref "Q64")
      (value "2N7000")
      (footprint "eagle-import:TO92-DGS")
      (libsource (lib "eagle-import") (part "2N7000"))
    )
    (comp (ref "Q65")
      (value "2N7000")
      (footprint "eagle-import:TO92-DGS")
      (libsource (lib "eagle-import") (part "2N7000"))
    )
    (comp (ref "Q66")
      (value "2N7000")
      (footprint "eagle-import:TO92-DGS")
      (libsource (lib "eagle-import") (part "2N7000"))
    )
    (comp (ref "Q67")
      (value "2N7000")
      (footprint "eagle-import:TO92-DGS")
      (libsource (lib "eagle-import") (part "2N7000"))
    )
    (comp (ref "Q68")
      (value "2N7000")
      (footprint "eagle-import:TO92-DGS")
      (libsource (lib "eagle-import") (part "2N7000"))
    )
    (comp (ref "R11")
      (value "10k")
      (footprint "eagle-import:R_P2INCH")
      (libsource (lib "eagle-import") (part "R_P2INCH"))
    )
    (comp (ref "R12")
      (value "470")
      (footprint "eagle-import:R_P2INCH")
      (libsource (lib "eagle-import") (part "R_P2INCH"))
    )
    (comp (ref "R13")
      (value "10k")
      (footprint "eagle-import:R_P2INCH")
      (libsource (lib "eagle-import") (part "R_P2INCH"))
    )
    (comp (ref "R14")
      (value "470")
      (footprint "eagle-import:R_P2INCH")
      (libsource (lib "eagle-import") (part "R_P2INCH"))
    )
    (comp (ref "R15")
      (value "470")
      (footprint "eagle-import:R_P2INCH")
      (libsource (lib "eagle-import") (part "R_P2INCH"))
    )
    (comp (ref "R76")
      (value "10k")
      (footprint "eagle-import:R_P2INCH")
      (libsource (lib "eagle-import") (part "R_P2INCH"))
    )
    (comp (ref "R77")
      (value "470")
      (footprint "eagle-import:R_P2INCH")
      (libsource (lib "eagle-import") (part "R_P2INCH"))
    )
    (comp (ref "R78")
      (value "10k")
      (footprint "eagle-import:R_P2INCH")
      (libsource (lib "eagle-import") (part "R_P2INCH"))
    )
    (comp (ref "R79")
      (value "470")
      (footprint "eagle-import:R_P2INCH")
      (libsource (lib "eagle-import") (part "R_P2INCH"))
    )
    (comp (ref "R80")
      (value "470")
      (footprint "eagle-import:R_P2INCH")
      (libsource (lib "eagle-import") (part "R_P2INCH"))
    )
    (comp (ref "D34")
      (value "L-1334SRT")
      (footprint "eagle-import:LED3MM")
      (libsource (lib "eagle-import") (part "L-1334SRT"))
    )
    (comp (ref "D35")
      (value "L-1334SRT")
      (footprint "eagle-import:LED3MM")
      (libsource (lib "eagle-import") (part "L-1334SRT"))
    )
    (comp (ref "D36")
      (value "L-1334SRT")
      (footprint "eagle-import:LED3MM")
      (libsource (lib "eagle-import") (part "L-1334SRT"))
    )
    (comp (ref "D37")
      (value "L-1334SRT")
      (footprint "eagle-import:LED3MM")
      (libsource (lib "eagle-import") (part "L-1334SRT"))
    )
    (comp (ref "D38")
      (value "L-1334SRT")
      (footprint "eagle-import:LED3MM")
      (libsource (lib "eagle-import") (part "L-1334SRT"))
    )
    (comp (ref "D39")
      (value "L-1334SRT")
      (footprint "eagle-import:LED3MM")
      (libsource (lib "eagle-import") (part "L-1334SRT"))
    )
    (comp (ref "D40")
      (value "L-1334SRT")
      (footprint "eagle-import:LED3MM")
      (libsource (lib "eagle-import") (part "L-1334SRT"))
    )
    (comp (ref "D41")
      (value "L-1334SRT")
      (footprint "eagle-import:LED3MM")
      (libsource (lib "eagle-import") (part "L-1334SRT"))
    )
    (comp (ref "D42")
      (value "L-1334SRT")
      (footprint "eagle-import:LED3MM")
      (libsource (lib "eagle-import") (part "L-1334SRT"))
    )
    (comp (ref "Q48")
      (value "2N7000")
      (footprint "eagle-import:TO92-DGS")
      (libsource (lib "eagle-import") (part "2N7000"))
    )
    (comp (ref "Q49")
      (value "2N7000")
      (footprint "eagle-import:TO92-DGS")
      (libsource (lib "eagle-import") (part "2N7000"))
    )
    (comp (ref "Q50")
      (value "2N7000")
      (footprint "eagle-import:TO92-DGS")
      (libsource (lib "eagle-import") (part "2N7000"))
    )
    (comp (ref "Q51")
      (value "2N7000")
      (footprint "eagle-import:TO92-DGS")
      (libsource (lib "eagle-import") (part "2N7000"))
    )
    (comp (ref "Q52")
      (value "2N7000")
      (footprint "eagle-import:TO92-DGS")
      (libsource (lib "eagle-import") (part "2N7000"))
    )
    (comp (ref "Q53")
      (value "2N7000")
      (footprint "eagle-import:TO92-DGS")
      (libsource (lib "eagle-import") (part "2N7000"))
    )
    (comp (ref "Q54")
      (value "2N7000")
      (footprint "eagle-import:TO92-DGS")
      (libsource (lib "eagle-import") (part "2N7000"))
    )
    (comp (ref "Q55")
      (value "2N7000")
      (footprint "eagle-import:TO92-DGS")
      (libsource (lib "eagle-import") (part "2N7000"))
    )
    (comp (ref "Q56")
      (value "2N7000")
      (footprint "eagle-import:TO92-DGS")
      (libsource (lib "eagle-import") (part "2N7000"))
    )
    (comp (ref "R56")
      (value "10k")
      (footprint "eagle-import:R_P2INCH")
      (libsource (lib "eagle-import") (part "R_P2INCH"))
    )
    (comp (ref "R57")
      (value "470")
      (footprint "eagle-import:R_P2INCH")
      (libsource (lib "eagle-import") (part "R_P2INCH"))
    )
    (comp (ref "R58")
      (value "10k")
      (footprint "eagle-import:R_P2INCH")
      (libsource (lib "eagle-import") (part "R_P2INCH"))
    )
    (comp (ref "R59")
      (value "470")
      (footprint "eagle-import:R_P2INCH")
      (libsource (lib "eagle-import") (part "R_P2INCH"))
    )
    (comp (ref "R60")
      (value "470")
      (footprint "eagle-import:R_P2INCH")
      (libsource (lib "eagle-import") (part "R_P2INCH"))
    )
    (comp (ref "R61")
      (value "10k")
      (footprint "eagle-import:R_P2INCH")
      (libsource (lib "eagle-import") (part "R_P2INCH"))
    )
    (comp (ref "R62")
      (value "470")
      (footprint "eagle-import:R_P2INCH")
      (libsource (lib "eagle-import") (part "R_P2INCH"))
    )
    (comp (ref "R63")
      (value "10k")
      (footprint "eagle-import:R_P2INCH")
      (libsource (lib "eagle-import") (part "R_P2INCH"))
    )
    (comp (ref "R64")
      (value "470")
      (footprint "eagle-import:R_P2INCH")
      (libsource (lib "eagle-import") (part "R_P2INCH"))
    )
    (comp (ref "R65")
      (value "470")
      (footprint "eagle-import:R_P2INCH")
      (libsource (lib "eagle-import") (part "R_P2INCH"))
    )
    (comp (ref "R66")
      (value "10k")
      (footprint "eagle-import:R_P2INCH")
      (libsource (lib "eagle-import") (part "R_P2INCH"))
    )
    (comp (ref "R67")
      (value "470")
      (footprint "eagle-import:R_P2INCH")
      (libsource (lib "eagle-import") (part "R_P2INCH"))
    )
    (comp (ref "R68")
      (value "10k")
      (footprint "eagle-import:R_P2INCH")
      (libsource (lib "eagle-import") (part "R_P2INCH"))
    )
    (comp (ref "R69")
      (value "470")
      (footprint "eagle-import:R_P2INCH")
      (libsource (lib "eagle-import") (part "R_P2INCH"))
    )
    (comp (ref "R70")
      (value "470")
      (footprint "eagle-import:R_P2INCH")
      (libsource (lib "eagle-import") (part "R_P2INCH"))
    )
  )
  (nets
    (net (code "1") (name "+5V") (class "Default")
      (node (ref "C1") (pin "1") (pinfunction "1_1") (pintype "passive"))
      (node (ref "C2") (pin "1") (pinfunction "1_1") (pintype "passive"))
      (node (ref "C3") (pin "1") (pinfunction "1_1") (pintype "passive"))
      (node (ref "C4") (pin "1") (pinfunction "1_1") (pintype "passive"))
      (node (ref "C5") (pin "1") (pinfunction "1_1") (pintype "passive"))
      (node (ref "C6") (pin "A") (pinfunction "A_A") (pintype "passive"))
      (node (ref "D1") (pin "A") (pinfunction "A_A") (pintype "passive"))
      (node (ref "D10") (pin "A") (pinfunction "A_A") (pintype "passive"))
      (node (ref "D100") (pin "A") (pinfunction "A_A") (pintype "passive"))
      (node (ref "D101") (pin "A") (pinfunction "A_A") (pintype "passive"))
      (node (ref "D102") (pin "A") (pinfunction "A_A") (pintype "passive"))
      (node (ref "D103") (pin "A") (pinfunction "A_A") (pintype "passive"))
      (node (ref "D104") (pin "A") (pinfunction "A_A") (pintype "passive"))
      (node (ref "D105") (pin "A") (pinfunction "A_A") (pintype "passive"))
      (node (ref "D106") (pin "A") (pinfunction "A_A") (pintype "passive"))
      (node (ref "D107") (pin "A") (pinfunction "A_A") (pintype "passive"))
      (node (ref "D108") (pin "A") (pinfunction "A_A") (pintype "passive"))
      (node (ref "D109") (pin "A") (pinfunction "A_A") (pintype "passive"))
      (node (ref "D11") (pin "A") (pinfunction "A_A") (pintype "passive"))
      (node (ref "D110") (pin "A") (pinfunction "A_A") (pintype "passive"))
      (node (ref "D111") (pin "A") (pinfunction "A_A") (pintype "passive"))
      (node (ref "D112") (pin "A") (pinfunction "A_A") (pintype "passive"))
      (node (ref "D113") (pin "A") (pinfunction "A_A") (pintype "passive"))
      (node (ref "D114") (pin "A") (pinfunction "A_A") (pintype "passive"))
      (node (ref "D115") (pin "A") (pinfunction "A_A") (pintype "passive"))
      (node (ref "D116") (pin "A") (pinfunction "A_A") (pintype "passive"))
      (node (ref "D117") (pin "A") (pinfunction "A_A") (pintype "passive"))
      (node (ref "D118") (pin "A") (pinfunction "A_A") (pintype "passive"))
      (node (ref "D119") (pin "A") (pinfunction "A_A") (pintype "passive"))
      (node (ref "D12") (pin "A") (pinfunction "A_A") (pintype "passive"))
      (node (ref "D120") (pin "A") (pinfunction "A_A") (pintype "passive"))
      (node (ref "D121") (pin "A") (pinfunction "A_A") (pintype "passive"))
      (node (ref "D122") (pin "A") (pinfunction "A_A") (pintype "passive"))
      (node (ref "D123") (pin "A") (pinfunction "A_A") (pintype "passive"))
      (node (ref "D124") (pin "A") (pinfunction "A_A") (pintype "passive"))
      (node (ref "D125") (pin "A") (pinfunction "A_A") (pintype "passive"))
      (node (ref "D126") (pin "A") (pinfunction "A_A") (pintype "passive"))
      (node (ref "D127") (pin "A") (pinfunction "A_A") (pintype "passive"))
      (node (ref "D128") (pin "A") (pinfunction "A_A") (pintype "passive"))
      (node (ref "D129") (pin "A") (pinfunction "A_A") (pintype "passive"))
      (node (ref "D13") (pin "A") (pinfunction "A_A") (pintype "passive"))
      (node (ref "D130") (pin "A") (pinfunction "A_A") (pintype "passive"))
      (node (ref "D131") (pin "A") (pinfunction "A_A") (pintype "passive"))
      (node (ref "D132") (pin "A") (pinfunction "A_A") (pintype "passive"))
      (node (ref "D133") (pin "A") (pinfunction "A_A") (pintype "passive"))
      (node (ref "D134") (pin "A") (pinfunction "A_A") (pintype "passive"))
      (node (ref "D135") (pin "A") (pinfunction "A_A") (pintype "passive"))
      (node (ref "D136") (pin "A") (pinfunction "A_A") (pintype "passive"))
      (node (ref "D137") (pin "A") (pinfunction "A_A") (pintype "passive"))
      (node (ref "D138") (pin "A") (pinfunction "A_A") (pintype "passive"))
      (node (ref "D139") (pin "A") (pinfunction "A_A") (pintype "passive"))
      (node (ref "D14") (pin "A") (pinfunction "A_A") (pintype "passive"))
      (node (ref "D140") (pin "A") (pinfunction "A_A") (pintype "passive"))
      (node (ref "D141") (pin "A") (pinfunction "A_A") (pintype "passive"))
      (node (ref "D142") (pin "A") (pinfunction "A_A") (pintype "passive"))
      (node (ref "D143") (pin "A") (pinfunction "A_A") (pintype "passive"))
      (node (ref "D144") (pin "A") (pinfunction "A_A") (pintype "passive"))
      (node (ref "D145") (pin "A") (pinfunction "A_A") (pintype "passive"))
      (node (ref "D146") (pin "A") (pinfunction "A_A") (pintype "passive"))
      (node (ref "D147") (pin "A") (pinfunction "A_A") (pintype "passive"))
      (node (ref "D148") (pin "A") (pinfunction "A_A") (pintype "passive"))
      (node (ref "D149") (pin "A") (pinfunction "A_A") (pintype "passive"))
      (node (ref "D15") (pin "A") (pinfunction "A_A") (pintype "passive"))
      (node (ref "D150") (pin "A") (pinfunction "A_A") (pintype "passive"))
      (node (ref "D151") (pin "A") (pinfunction "A_A") (pintype "passive"))
      (node (ref "D152") (pin "A") (pinfunction "A_A") (pintype "passive"))
      (node (ref "D153") (pin "A") (pinfunction "A_A") (pintype "passive"))
      (node (ref "D154") (pin "A") (pinfunction "A_A") (pintype "passive"))
      (node (ref "D155") (pin "A") (pinfunction "A_A") (pintype "passive"))
      (node (ref "D156") (pin "A") (pinfunction "A_A") (pintype "passive"))
      (node (ref "D157") (pin "A") (pinfunction "A_A") (pintype "passive"))
      (node (ref "D158") (pin "A") (pinfunction "A_A") (pintype "passive"))
      (node (ref "D159") (pin "A") (pinfunction "A_A") (pintype "passive"))
      (node (ref "D16") (pin "A") (pinfunction "A_A") (pintype "passive"))
      (node (ref "D160") (pin "A") (pinfunction "A_A") (pintype "passive"))
      (node (ref "D161") (pin "A") (pinfunction "A_A") (pintype "passive"))
      (node (ref "D163") (pin "A") (pinfunction "A_A") (pintype "passive"))
      (node (ref "D164") (pin "A") (pinfunction "A_A") (pintype "passive"))
      (node (ref "D165") (pin "A") (pinfunction "A_A") (pintype "passive"))
      (node (ref "D166") (pin "A") (pinfunction "A_A") (pintype "passive"))
      (node (ref "D167") (pin "A") (pinfunction "A_A") (pintype "passive"))
      (node (ref "D168") (pin "A") (pinfunction "A_A") (pintype "passive"))
      (node (ref "D169") (pin "A") (pinfunction "A_A") (pintype "passive"))
      (node (ref "D17") (pin "A") (pinfunction "A_A") (pintype "passive"))
      (node (ref "D170") (pin "A") (pinfunction "A_A") (pintype "passive"))
      (node (ref "D171") (pin "A") (pinfunction "A_A") (pintype "passive"))
      (node (ref "D172") (pin "A") (pinfunction "A_A") (pintype "passive"))
      (node (ref "D18") (pin "A") (pinfunction "A_A") (pintype "passive"))
      (node (ref "D19") (pin "A") (pinfunction "A_A") (pintype "passive"))
      (node (ref "D2") (pin "A") (pinfunction "A_A") (pintype "passive"))
      (node (ref "D20") (pin "A") (pinfunction "A_A") (pintype "passive"))
      (node (ref "D21") (pin "A") (pinfunction "A_A") (pintype "passive"))
      (node (ref "D22") (pin "A") (pinfunction "A_A") (pintype "passive"))
      (node (ref "D23") (pin "A") (pinfunction "A_A") (pintype "passive"))
      (node (ref "D24") (pin "A") (pinfunction "A_A") (pintype "passive"))
      (node (ref "D25") (pin "A") (pinfunction "A_A") (pintype "passive"))
      (node (ref "D26") (pin "A") (pinfunction "A_A") (pintype "passive"))
      (node (ref "D27") (pin "A") (pinfunction "A_A") (pintype "passive"))
      (node (ref "D28") (pin "A") (pinfunction "A_A") (pintype "passive"))
      (node (ref "D29") (pin "A") (pinfunction "A_A") (pintype "passive"))
      (node (ref "D3") (pin "A") (pinfunction "A_A") (pintype "passive"))
      (node (ref "D30") (pin "A") (pinfunction "A_A") (pintype "passive"))
      (node (ref "D31") (pin "A") (pinfunction "A_A") (pintype "passive"))
      (node (ref "D32") (pin "A") (pinfunction "A_A") (pintype "passive"))
      (node (ref "D33") (pin "A") (pinfunction "A_A") (pintype "passive"))
      (node (ref "D34") (pin "A") (pinfunction "A_A") (pintype "passive"))
      (node (ref "D35") (pin "A") (pinfunction "A_A") (pintype "passive"))
      (node (ref "D36") (pin "A") (pinfunction "A_A") (pintype "passive"))
      (node (ref "D37") (pin "A") (pinfunction "A_A") (pintype "passive"))
      (node (ref "D38") (pin "A") (pinfunction "A_A") (pintype "passive"))
      (node (ref "D39") (pin "A") (pinfunction "A_A") (pintype "passive"))
      (node (ref "D4") (pin "A") (pinfunction "A_A") (pintype "passive"))
      (node (ref "D40") (pin "A") (pinfunction "A_A") (pintype "passive"))
      (node (ref "D41") (pin "A") (pinfunction "A_A") (pintype "passive"))
      (node (ref "D42") (pin "A") (pinfunction "A_A") (pintype "passive"))
      (node (ref "D43") (pin "A") (pinfunction "A_A") (pintype "passive"))
      (node (ref "D44") (pin "A") (pinfunction "A_A") (pintype "passive"))
      (node (ref "D45") (pin "A") (pinfunction "A_A") (pintype "passive"))
      (node (ref "D46") (pin "A") (pinfunction "A_A") (pintype "passive"))
      (node (ref "D47") (pin "A") (pinfunction "A_A") (pintype "passive"))
      (node (ref "D48") (pin "A") (pinfunction "A_A") (pintype "passive"))
      (node (ref "D49") (pin "A") (pinfunction "A_A") (pintype "passive"))
      (node (ref "D5") (pin "A") (pinfunction "A_A") (pintype "passive"))
      (node (ref "D50") (pin "A") (pinfunction "A_A") (pintype "passive"))
      (node (ref "D51") (pin "A") (pinfunction "A_A") (pintype "passive"))
      (node (ref "D52") (pin "A") (pinfunction "A_A") (pintype "passive"))
      (node (ref "D53") (pin "A") (pinfunction "A_A") (pintype "passive"))
      (node (ref "D54") (pin "A") (pinfunction "A_A") (pintype "passive"))
      (node (ref "D55") (pin "A") (pinfunction "A_A") (pintype "passive"))
      (node (ref "D56") (pin "A") (pinfunction "A_A") (pintype "passive"))
      (node (ref "D57") (pin "A") (pinfunction "A_A") (pintype "passive"))
      (node (ref "D58") (pin "A") (pinfunction "A_A") (pintype "passive"))
      (node (ref "D59") (pin "A") (pinfunction "A_A") (pintype "passive"))
      (node (ref "D6") (pin "A") (pinfunction "A_A") (pintype "passive"))
      (node (ref "D60") (pin "A") (pinfunction "A_A") (pintype "passive"))
      (node (ref "D61") (pin "A") (pinfunction "A_A") (pintype "passive"))
      (node (ref "D62") (pin "A") (pinfunction "A_A") (pintype "passive"))
      (node (ref "D63") (pin "A") (pinfunction "A_A") (pintype "passive"))
      (node (ref "D64") (pin "A") (pinfunction "A_A") (pintype "passive"))
      (node (ref "D65") (pin "A") (pinfunction "A_A") (pintype "passive"))
      (node (ref "D66") (pin "A") (pinfunction "A_A") (pintype "passive"))
      (node (ref "D67") (pin "A") (pinfunction "A_A") (pintype "passive"))
      (node (ref "D68") (pin "A") (pinfunction "A_A") (pintype "passive"))
      (node (ref "D69") (pin "A") (pinfunction "A_A") (pintype "passive"))
      (node (ref "D7") (pin "A") (pinfunction "A_A") (pintype "passive"))
      (node (ref "D70") (pin "A") (pinfunction "A_A") (pintype "passive"))
      (node (ref "D71") (pin "A") (pinfunction "A_A") (pintype "passive"))
      (node (ref "D72") (pin "A") (pinfunction "A_A") (pintype "passive"))
      (node (ref "D73") (pin "A") (pinfunction "A_A") (pintype "passive"))
      (node (ref "D74") (pin "A") (pinfunction "A_A") (pintype "passive"))
      (node (ref "D75") (pin "A") (pinfunction "A_A") (pintype "passive"))
      (node (ref "D76") (pin "A") (pinfunction "A_A") (pintype "passive"))
      (node (ref "D77") (pin "A") (pinfunction "A_A") (pintype "passive"))
      (node (ref "D78") (pin "A") (pinfunction "A_A") (pintype "passive"))
      (node (ref "D79") (pin "A") (pinfunction "A_A") (pintype "passive"))
      (node (ref "D8") (pin "A") (pinfunction "A_A") (pintype "passive"))
      (node (ref "D80") (pin "A") (pinfunction "A_A") (pintype "passive"))
      (node (ref "D81") (pin "A") (pinfunction "A_A") (pintype "passive"))
      (node (ref "D82") (pin "A") (pinfunction "A_A") (pintype "passive"))
      (node (ref "D83") (pin "A") (pinfunction "A_A") (pintype "passive"))
      (node (ref "D84") (pin "A") (pinfunction "A_A") (pintype "passive"))
      (node (ref "D85") (pin "A") (pinfunction "A_A") (pintype "passive"))
      (node (ref "D86") (pin "A") (pinfunction "A_A") (pintype "passive"))
      (node (ref "D87") (pin "A") (pinfunction "A_A") (pintype "passive"))
      (node (ref "D88") (pin "A") (pinfunction "A_A") (pintype "passive"))
      (node (ref "D89") (pin "A") (pinfunction "A_A") (pintype "passive"))
      (node (ref "D9") (pin "A") (pinfunction "A_A") (pintype "passive"))
      (node (ref "D90") (pin "A") (pinfunction "A_A") (pintype "passive"))
      (node (ref "D91") (pin "A") (pinfunction "A_A") (pintype "passive"))
      (node (ref "D92") (pin "A") (pinfunction "A_A") (pintype "passive"))
      (node (ref "D93") (pin "A") (pinfunction "A_A") (pintype "passive"))
      (node (ref "D94") (pin "A") (pinfunction "A_A") (pintype "passive"))
      (node (ref "D95") (pin "A") (pinfunction "A_A") (pintype "passive"))
      (node (ref "D96") (pin "A") (pinfunction "A_A") (pintype "passive"))
      (node (ref "D97") (pin "A") (pinfunction "A_A") (pintype "passive"))
      (node (ref "D98") (pin "A") (pinfunction "A_A") (pintype "passive"))
      (node (ref "D99") (pin "A") (pinfunction "A_A") (pintype "passive"))
      (node (ref "PP1") (pin "1") (pinfunction "P$1_1") (pintype "bidirectional"))
      (node (ref "R1") (pin "2") (pinfunction "2_2") (pintype "passive"))
      (node (ref "R101") (pin "2") (pinfunction "2_2") (pintype "passive"))
      (node (ref "R103") (pin "2") (pinfunction "2_2") (pintype "passive"))
      (node (ref "R106") (pin "2") (pinfunction "2_2") (pintype "passive"))
      (node (ref "R108") (pin "2") (pinfunction "2_2") (pintype "passive"))
      (node (ref "R11") (pin "2") (pinfunction "2_2") (pintype "passive"))
      (node (ref "R111") (pin "2") (pinfunction "2_2") (pintype "passive"))
      (node (ref "R113") (pin "2") (pinfunction "2_2") (pintype "passive"))
      (node (ref "R116") (pin "2") (pinfunction "2_2") (pintype "passive"))
      (node (ref "R118") (pin "2") (pinfunction "2_2") (pintype "passive"))
      (node (ref "R121") (pin "2") (pinfunction "2_2") (pintype "passive"))
      (node (ref "R123") (pin "2") (pinfunction "2_2") (pintype "passive"))
      (node (ref "R126") (pin "2") (pinfunction "2_2") (pintype "passive"))
      (node (ref "R128") (pin "2") (pinfunction "2_2") (pintype "passive"))
      (node (ref "R13") (pin "2") (pinfunction "2_2") (pintype "passive"))
      (node (ref "R131") (pin "2") (pinfunction "2_2") (pintype "passive"))
      (node (ref "R133") (pin "2") (pinfunction "2_2") (pintype "passive"))
      (node (ref "R136") (pin "2") (pinfunction "2_2") (pintype "passive"))
      (node (ref "R138") (pin "2") (pinfunction "2_2") (pintype "passive"))
      (node (ref "R141") (pin "2") (pinfunction "2_2") (pintype "passive"))
      (node (ref "R143") (pin "2") (pinfunction "2_2") (pintype "passive"))
      (node (ref "R146") (pin "2") (pinfunction "2_2") (pintype "passive"))
      (node (ref "R148") (pin "2") (pinfunction "2_2") (pintype "passive"))
      (node (ref "R151") (pin "2") (pinfunction "2_2") (pintype "passive"))
      (node (ref "R153") (pin "2") (pinfunction "2_2") (pintype "passive"))
      (node (ref "R156") (pin "2") (pinfunction "2_2") (pintype "passive"))
      (node (ref "R158") (pin "2") (pinfunction "2_2") (pintype "passive"))
      (node (ref "R16") (pin "2") (pinfunction "2_2") (pintype "passive"))
      (node (ref "R161") (pin "2") (pinfunction "2_2") (pintype "passive"))
      (node (ref "R163") (pin "2") (pinfunction "2_2") (pintype "passive"))
      (node (ref "R166") (pin "2") (pinfunction "2_2") (pintype "passive"))
      (node (ref "R168") (pin "2") (pinfunction "2_2") (pintype "passive"))
      (node (ref "R171") (pin "2") (pinfunction "2_2") (pintype "passive"))
      (node (ref "R173") (pin "2") (pinfunction "2_2") (pintype "passive"))
      (node (ref "R176") (pin "2") (pinfunction "2_2") (pintype "passive"))
      (node (ref "R178") (pin "2") (pinfunction "2_2") (pintype "passive"))
      (node (ref "R18") (pin "2") (pinfunction "2_2") (pintype "passive"))
      (node (ref "R181") (pin "2") (pinfunction "2_2") (pintype "passive"))
      (node (ref "R183") (pin "2") (pinfunction "2_2") (pintype "passive"))
      (node (ref "R186") (pin "2") (pinfunction "2_2") (pintype "passive"))
      (node (ref "R188") (pin "2") (pinfunction "2_2") (pintype "passive"))
      (node (ref "R191") (pin "2") (pinfunction "2_2") (pintype "passive"))
      (node (ref "R193") (pin "2") (pinfunction "2_2") (pintype "passive"))
      (node (ref "R196") (pin "2") (pinfunction "2_2") (pintype "passive"))
      (node (ref "R198") (pin "2") (pinfunction "2_2") (pintype "passive"))
      (node (ref "R201") (pin "2") (pinfunction "2_2") (pintype "passive"))
      (node (ref "R203") (pin "2") (pinfunction "2_2") (pintype "passive"))
      (node (ref "R206") (pin "2") (pinfunction "2_2") (pintype "passive"))
      (node (ref "R208") (pin "2") (pinfunction "2_2") (pintype "passive"))
      (node (ref "R21") (pin "2") (pinfunction "2_2") (pintype "passive"))
      (node (ref "R211") (pin "2") (pinfunction "2_2") (pintype "passive"))
      (node (ref "R213") (pin "2") (pinfunction "2_2") (pintype "passive"))
      (node (ref "R216") (pin "2") (pinfunction "2_2") (pintype "passive"))
      (node (ref "R218") (pin "2") (pinfunction "2_2") (pintype "passive"))
      (node (ref "R221") (pin "2") (pinfunction "2_2") (pintype "passive"))
      (node (ref "R223") (pin "2") (pinfunction "2_2") (pintype "passive"))
      (node (ref "R226") (pin "2") (pinfunction "2_2") (pintype "passive"))
      (node (ref "R228") (pin "2") (pinfunction "2_2") (pintype "passive"))
      (node (ref "R23") (pin "2") (pinfunction "2_2") (pintype "passive"))
      (node (ref "R231") (pin "2") (pinfunction "2_2") (pintype "passive"))
      (node (ref "R233") (pin "2") (pinfunction "2_2") (pintype "passive"))
      (node (ref "R236") (pin "2") (pinfunction "2_2") (pintype "passive"))
      (node (ref "R238") (pin "2") (pinfunction "2_2") (pintype "passive"))
      (node (ref "R241") (pin "2") (pinfunction "2_2") (pintype "passive"))
      (node (ref "R242") (pin "2") (pinfunction "2_2") (pintype "passive"))
      (node (ref "R243") (pin "2") (pinfunction "2_2") (pintype "passive"))
      (node (ref "R244") (pin "2") (pinfunction "2_2") (pintype "passive"))
      (node (ref "R245") (pin "2") (pinfunction "2_2") (pintype "passive"))
      (node (ref "R246") (pin "2") (pinfunction "2_2") (pintype "passive"))
      (node (ref "R247") (pin "2") (pinfunction "2_2") (pintype "passive"))
      (node (ref "R248") (pin "2") (pinfunction "2_2") (pintype "passive"))
      (node (ref "R249") (pin "2") (pinfunction "2_2") (pintype "passive"))
      (node (ref "R250") (pin "2") (pinfunction "2_2") (pintype "passive"))
      (node (ref "R251") (pin "2") (pinfunction "2_2") (pintype "passive"))
      (node (ref "R252") (pin "2") (pinfunction "2_2") (pintype "passive"))
      (node (ref "R253") (pin "2") (pinfunction "2_2") (pintype "passive"))
      (node (ref "R254") (pin "2") (pinfunction "2_2") (pintype "passive"))
      (node (ref "R255") (pin "2") (pinfunction "2_2") (pintype "passive"))
      (node (ref "R256") (pin "2") (pinfunction "2_2") (pintype "passive"))
      (node (ref "R257") (pin "2") (pinfunction "2_2") (pintype "passive"))
      (node (ref "R26") (pin "2") (pinfunction "2_2") (pintype "passive"))
      (node (ref "R268") (pin "2") (pinfunction "2_2") (pintype "passive"))
      (node (ref "R28") (pin "2") (pinfunction "2_2") (pintype "passive"))
      (node (ref "R285") (pin "2") (pinfunction "2_2") (pintype "passive"))
      (node (ref "R287") (pin "2") (pinfunction "2_2") (pintype "passive"))
      (node (ref "R289") (pin "2") (pinfunction "2_2") (pintype "passive"))
      (node (ref "R3") (pin "2") (pinfunction "2_2") (pintype "passive"))
      (node (ref "R31") (pin "2") (pinfunction "2_2") (pintype "passive"))
      (node (ref "R33") (pin "2") (pinfunction "2_2") (pintype "passive"))
      (node (ref "R36") (pin "2") (pinfunction "2_2") (pintype "passive"))
      (node (ref "R38") (pin "2") (pinfunction "2_2") (pintype "passive"))
      (node (ref "R41") (pin "2") (pinfunction "2_2") (pintype "passive"))
      (node (ref "R43") (pin "2") (pinfunction "2_2") (pintype "passive"))
      (node (ref "R46") (pin "2") (pinfunction "2_2") (pintype "passive"))
      (node (ref "R48") (pin "2") (pinfunction "2_2") (pintype "passive"))
      (node (ref "R51") (pin "2") (pinfunction "2_2") (pintype "passive"))
      (node (ref "R53") (pin "2") (pinfunction "2_2") (pintype "passive"))
      (node (ref "R56") (pin "2") (pinfunction "2_2") (pintype "passive"))
      (node (ref "R58") (pin "2") (pinfunction "2_2") (pintype "passive"))
      (node (ref "R6") (pin "2") (pinfunction "2_2") (pintype "passive"))
      (node (ref "R61") (pin "2") (pinfunction "2_2") (pintype "passive"))
      (node (ref "R63") (pin "2") (pinfunction "2_2") (pintype "passive"))
      (node (ref "R66") (pin "2") (pinfunction "2_2") (pintype "passive"))
      (node (ref "R68") (pin "2") (pinfunction "2_2") (pintype "passive"))
      (node (ref "R71") (pin "2") (pinfunction "2_2") (pintype "passive"))
      (node (ref "R73") (pin "2") (pinfunction "2_2") (pintype "passive"))
      (node (ref "R76") (pin "2") (pinfunction "2_2") (pintype "passive"))
      (node (ref "R78") (pin "2") (pinfunction "2_2") (pintype "passive"))
      (node (ref "R8") (pin "2") (pinfunction "2_2") (pintype "passive"))
      (node (ref "R81") (pin "2") (pinfunction "2_2") (pintype "passive"))
      (node (ref "R83") (pin "2") (pinfunction "2_2") (pintype "passive"))
      (node (ref "R86") (pin "2") (pinfunction "2_2") (pintype "passive"))
      (node (ref "R88") (pin "2") (pinfunction "2_2") (pintype "passive"))
      (node (ref "R91") (pin "2") (pinfunction "2_2") (pintype "passive"))
      (node (ref "R93") (pin "2") (pinfunction "2_2") (pintype "passive"))
      (node (ref "R96") (pin "2") (pinfunction "2_2") (pintype "passive"))
      (node (ref "R98") (pin "2") (pinfunction "2_2") (pintype "passive"))
    )
    (net (code "2") (name "ADD_R0") (class "Default")
      (node (ref "Q26") (pin "D") (pinfunction "D_D") (pintype "passive"))
      (node (ref "Q30") (pin "G") (pinfunction "G_G") (pintype "passive"))
      (node (ref "Q43") (pin "G") (pinfunction "G_G") (pintype "passive"))
      (node (ref "R28") (pin "1") (pinfunction "1_1") (pintype "passive"))
    )
    (net (code "3") (name "ADD_R0_N") (class "Default")
      (node (ref "Q22") (pin "D") (pinfunction "D_D") (pintype "passive"))
      (node (ref "Q24") (pin "D") (pinfunction "D_D") (pintype "passive"))
      (node (ref "Q26") (pin "G") (pinfunction "G_G") (pintype "passive"))
      (node (ref "Q28") (pin "G") (pinfunction "G_G") (pintype "passive"))
      (node (ref "R26") (pin "1") (pinfunction "1_1") (pintype "passive"))
      (node (ref "R27") (pin "1") (pinfunction "1_1") (pintype "passive"))
      (node (ref "R35") (pin "1") (pinfunction "1_1") (pintype "passive"))
      (node (ref "R50") (pin "1") (pinfunction "1_1") (pintype "passive"))
    )
    (net (code "4") (name "ADD_R1") (class "Default")
      (node (ref "Q36") (pin "D") (pinfunction "D_D") (pintype "passive"))
      (node (ref "Q40") (pin "G") (pinfunction "G_G") (pintype "passive"))
      (node (ref "Q49") (pin "G") (pinfunction "G_G") (pintype "passive"))
      (node (ref "R38") (pin "1") (pinfunction "1_1") (pintype "passive"))
    )
    (net (code "5") (name "ADD_R1_N") (class "Default")
      (node (ref "Q32") (pin "D") (pinfunction "D_D") (pintype "passive"))
      (node (ref "Q34") (pin "D") (pinfunction "D_D") (pintype "passive"))
      (node (ref "Q36") (pin "G") (pinfunction "G_G") (pintype "passive"))
      (node (ref "Q38") (pin "G") (pinfunction "G_G") (pintype "passive"))
      (node (ref "R36") (pin "1") (pinfunction "1_1") (pintype "passive"))
      (node (ref "R37") (pin "1") (pinfunction "1_1") (pintype "passive"))
      (node (ref "R45") (pin "1") (pinfunction "1_1") (pintype "passive"))
      (node (ref "R60") (pin "1") (pinfunction "1_1") (pintype "passive"))
    )
    (net (code "6") (name "ADD_R2") (class "Default")
      (node (ref "Q140") (pin "G") (pinfunction "G_G") (pintype "passive"))
      (node (ref "Q83") (pin "D") (pinfunction "D_D") (pintype "passive"))
      (node (ref "Q87") (pin "G") (pinfunction "G_G") (pintype "passive"))
      (node (ref "R93") (pin "1") (pinfunction "1_1") (pintype "passive"))
    )
    (net (code "7") (name "ADD_R2_N") (class "Default")
      (node (ref "Q79") (pin "D") (pinfunction "D_D") (pintype "passive"))
      (node (ref "Q81") (pin "D") (pinfunction "D_D") (pintype "passive"))
      (node (ref "Q83") (pin "G") (pinfunction "G_G") (pintype "passive"))
      (node (ref "Q85") (pin "G") (pinfunction "G_G") (pintype "passive"))
      (node (ref "R100") (pin "1") (pinfunction "1_1") (pintype "passive"))
      (node (ref "R155") (pin "1") (pinfunction "1_1") (pintype "passive"))
      (node (ref "R91") (pin "1") (pinfunction "1_1") (pintype "passive"))
      (node (ref "R92") (pin "1") (pinfunction "1_1") (pintype "passive"))
    )
    (net (code "8") (name "ADD_R3") (class "Default")
      (node (ref "Q149") (pin "G") (pinfunction "G_G") (pintype "passive"))
      (node (ref "Q93") (pin "D") (pinfunction "D_D") (pintype "passive"))
      (node (ref "Q97") (pin "G") (pinfunction "G_G") (pintype "passive"))
      (node (ref "R103") (pin "1") (pinfunction "1_1") (pintype "passive"))
    )
    (net (code "9") (name "ADD_R3_N") (class "Default")
      (node (ref "Q89") (pin "D") (pinfunction "D_D") (pintype "passive"))
      (node (ref "Q91") (pin "D") (pinfunction "D_D") (pintype "passive"))
      (node (ref "Q93") (pin "G") (pinfunction "G_G") (pintype "passive"))
      (node (ref "Q95") (pin "G") (pinfunction "G_G") (pintype "passive"))
      (node (ref "R101") (pin "1") (pinfunction "1_1") (pintype "passive"))
      (node (ref "R102") (pin "1") (pinfunction "1_1") (pintype "passive"))
      (node (ref "R110") (pin "1") (pinfunction "1_1") (pintype "passive"))
      (node (ref "R170") (pin "1") (pinfunction "1_1") (pintype "passive"))
    )
    (net (code "10") (name "ADD_R4") (class "Default")
      (node (ref "Q103") (pin "D") (pinfunction "D_D") (pintype "passive"))
      (node (ref "Q107") (pin "G") (pinfunction "G_G") (pintype "passive"))
      (node (ref "Q158") (pin "G") (pinfunction "G_G") (pintype "passive"))
      (node (ref "R113") (pin "1") (pinfunction "1_1") (pintype "passive"))
    )
    (net (code "11") (name "ADD_R4_N") (class "Default")
      (node (ref "Q101") (pin "D") (pinfunction "D_D") (pintype "passive"))
      (node (ref "Q103") (pin "G") (pinfunction "G_G") (pintype "passive"))
      (node (ref "Q105") (pin "G") (pinfunction "G_G") (pintype "passive"))
      (node (ref "Q99") (pin "D") (pinfunction "D_D") (pintype "passive"))
      (node (ref "R111") (pin "1") (pinfunction "1_1") (pintype "passive"))
      (node (ref "R112") (pin "1") (pinfunction "1_1") (pintype "passive"))
      (node (ref "R120") (pin "1") (pinfunction "1_1") (pintype "passive"))
      (node (ref "R185") (pin "1") (pinfunction "1_1") (pintype "passive"))
    )
    (net (code "12") (name "ADD_R5") (class "Default")
      (node (ref "Q113") (pin "D") (pinfunction "D_D") (pintype "passive"))
      (node (ref "Q117") (pin "G") (pinfunction "G_G") (pintype "passive"))
      (node (ref "Q167") (pin "G") (pinfunction "G_G") (pintype "passive"))
      (node (ref "R123") (pin "1") (pinfunction "1_1") (pintype "passive"))
    )
    (net (code "13") (name "ADD_R5_N") (class "Default")
      (node (ref "Q109") (pin "D") (pinfunction "D_D") (pintype "passive"))
      (node (ref "Q111") (pin "D") (pinfunction "D_D") (pintype "passive"))
      (node (ref "Q113") (pin "G") (pinfunction "G_G") (pintype "passive"))
      (node (ref "Q115") (pin "G") (pinfunction "G_G") (pintype "passive"))
      (node (ref "R121") (pin "1") (pinfunction "1_1") (pintype "passive"))
      (node (ref "R122") (pin "1") (pinfunction "1_1") (pintype "passive"))
      (node (ref "R130") (pin "1") (pinfunction "1_1") (pintype "passive"))
      (node (ref "R200") (pin "1") (pinfunction "1_1") (pintype "passive"))
    )
    (net (code "14") (name "ADD_R6") (class "Default")
      (node (ref "Q123") (pin "D") (pinfunction "D_D") (pintype "passive"))
      (node (ref "Q127") (pin "G") (pinfunction "G_G") (pintype "passive"))
      (node (ref "Q176") (pin "G") (pinfunction "G_G") (pintype "passive"))
      (node (ref "R133") (pin "1") (pinfunction "1_1") (pintype "passive"))
    )
    (net (code "15") (name "ADD_R6_N") (class "Default")
      (node (ref "Q119") (pin "D") (pinfunction "D_D") (pintype "passive"))
      (node (ref "Q121") (pin "D") (pinfunction "D_D") (pintype "passive"))
      (node (ref "Q123") (pin "G") (pinfunction "G_G") (pintype "passive"))
      (node (ref "Q125") (pin "G") (pinfunction "G_G") (pintype "passive"))
      (node (ref "R131") (pin "1") (pinfunction "1_1") (pintype "passive"))
      (node (ref "R132") (pin "1") (pinfunction "1_1") (pintype "passive"))
      (node (ref "R140") (pin "1") (pinfunction "1_1") (pintype "passive"))
      (node (ref "R215") (pin "1") (pinfunction "1_1") (pintype "passive"))
    )
    (net (code "16") (name "ADD_R7") (class "Default")
      (node (ref "Q133") (pin "D") (pinfunction "D_D") (pintype "passive"))
      (node (ref "Q137") (pin "G") (pinfunction "G_G") (pintype "passive"))
      (node (ref "Q185") (pin "G") (pinfunction "G_G") (pintype "passive"))
      (node (ref "R143") (pin "1") (pinfunction "1_1") (pintype "passive"))
    )
    (net (code "17") (name "ADD_R7_N") (class "Default")
      (node (ref "Q129") (pin "D") (pinfunction "D_D") (pintype "passive"))
      (node (ref "Q131") (pin "D") (pinfunction "D_D") (pintype "passive"))
      (node (ref "Q133") (pin "G") (pinfunction "G_G") (pintype "passive"))
      (node (ref "Q135") (pin "G") (pinfunction "G_G") (pintype "passive"))
      (node (ref "R141") (pin "1") (pinfunction "1_1") (pintype "passive"))
      (node (ref "R142") (pin "1") (pinfunction "1_1") (pintype "passive"))
      (node (ref "R150") (pin "1") (pinfunction "1_1") (pintype "passive"))
      (node (ref "R230") (pin "1") (pinfunction "1_1") (pintype "passive"))
    )
    (net (code "18") (name "CARRY_IN") (class "Default")
      (node (ref "Q213") (pin "D") (pinfunction "D_D") (pintype "passive"))
      (node (ref "Q27") (pin "G") (pinfunction "G_G") (pintype "passive"))
      (node (ref "Q42") (pin "G") (pinfunction "G_G") (pintype "passive"))
      (node (ref "R289") (pin "1") (pinfunction "1_1") (pintype "passive"))
    )
    (net (code "19") (name "CARRY_IN_N") (class "Default")
      (node (ref "Q212") (pin "D") (pinfunction "D_D") (pintype "passive"))
      (node (ref "Q213") (pin "G") (pinfunction "G_G") (pintype "passive"))
      (node (ref "Q29") (pin "G") (pinfunction "G_G") (pintype "passive"))
      (node (ref "R285") (pin "1") (pinfunction "1_1") (pintype "passive"))
      (node (ref "R288") (pin "1") (pinfunction "1_1") (pintype "passive"))
      (node (ref "R34") (pin "1") (pinfunction "1_1") (pintype "passive"))
      (node (ref "R49") (pin "1") (pinfunction "1_1") (pintype "passive"))
    )
    (net (code "20") (name "CARRY_IN_RAW") (class "Default")
      (node (ref "Q212") (pin "G") (pinfunction "G_G") (pintype "passive"))
      (node (ref "TP2") (pin "P$1") (pinfunction "P$1_P$1") (pintype "bidirectional"))
    )
    (net (code "21") (name "CARRY_OUT") (class "Default")
      (node (ref "Q189") (pin "D") (pinfunction "D_D") (pintype "passive"))
      (node (ref "Q211") (pin "G") (pinfunction "G_G") (pintype "passive"))
      (node (ref "R233") (pin "1") (pinfunction "1_1") (pintype "passive"))
      (node (ref "TP3") (pin "P$1") (pinfunction "P$1_P$1") (pintype "bidirectional"))
    )
    (net (code "22") (name "CARRY_OUT_N") (class "Default")
      (node (ref "Q187") (pin "D") (pinfunction "D_D") (pintype "passive"))
      (node (ref "Q188") (pin "D") (pinfunction "D_D") (pintype "passive"))
      (node (ref "Q189") (pin "G") (pinfunction "G_G") (pintype "passive"))
      (node (ref "R231") (pin "1") (pinfunction "1_1") (pintype "passive"))
      (node (ref "R232") (pin "1") (pinfunction "1_1") (pintype "passive"))
    )
    (net (code "23") (name "CARRY_OUT_N2") (class "Default")
      (node (ref "Q211") (pin "D") (pinfunction "D_D") (pintype "passive"))
      (node (ref "R286") (pin "1") (pinfunction "1_1") (pintype "passive"))
      (node (ref "R287") (pin "1") (pinfunction "1_1") (pintype "passive"))
    )
    (net (code "24") (name "CRY0") (class "Default")
      (node (ref "Q37") (pin "G") (pinfunction "G_G") (pintype "passive"))
      (node (ref "Q47") (pin "D") (pinfunction "D_D") (pintype "passive"))
      (node (ref "Q48") (pin "G") (pinfunction "G_G") (pintype "passive"))
      (node (ref "R53") (pin "1") (pinfunction "1_1") (pintype "passive"))
    )
    (net (code "25") (name "CRY0_N") (class "Default")
      (node (ref "Q39") (pin "G") (pinfunction "G_G") (pintype "passive"))
      (node (ref "Q45") (pin "D") (pinfunction "D_D") (pintype "passive"))
      (node (ref "Q46") (pin "D") (pinfunction "D_D") (pintype "passive"))
      (node (ref "Q47") (pin "G") (pinfunction "G_G") (pintype "passive"))
      (node (ref "R44") (pin "1") (pinfunction "1_1") (pintype "passive"))
      (node (ref "R51") (pin "1") (pinfunction "1_1") (pintype "passive"))
      (node (ref "R52") (pin "1") (pinfunction "1_1") (pintype "passive"))
      (node (ref "R59") (pin "1") (pinfunction "1_1") (pintype "passive"))
    )
    (net (code "26") (name "CRY1") (class "Default")
      (node (ref "Q139") (pin "G") (pinfunction "G_G") (pintype "passive"))
      (node (ref "Q53") (pin "D") (pinfunction "D_D") (pintype "passive"))
      (node (ref "Q84") (pin "G") (pinfunction "G_G") (pintype "passive"))
      (node (ref "R63") (pin "1") (pinfunction "1_1") (pintype "passive"))
    )
    (net (code "27") (name "CRY1_N") (class "Default")
      (node (ref "Q51") (pin "D") (pinfunction "D_D") (pintype "passive"))
      (node (ref "Q52") (pin "D") (pinfunction "D_D") (pintype "passive"))
      (node (ref "Q53") (pin "G") (pinfunction "G_G") (pintype "passive"))
      (node (ref "Q86") (pin "G") (pinfunction "G_G") (pintype "passive"))
      (node (ref "R154") (pin "1") (pinfunction "1_1") (pintype "passive"))
      (node (ref "R61") (pin "1") (pinfunction "1_1") (pintype "passive"))
      (node (ref "R62") (pin "1") (pinfunction "1_1") (pintype "passive"))
      (node (ref "R99") (pin "1") (pinfunction "1_1") (pintype "passive"))
    )
    (net (code "28") (name "CRY2") (class "Default")
      (node (ref "Q144") (pin "D") (pinfunction "D_D") (pintype "passive"))
      (node (ref "Q148") (pin "G") (pinfunction "G_G") (pintype "passive"))
      (node (ref "Q94") (pin "G") (pinfunction "G_G") (pintype "passive"))
      (node (ref "R158") (pin "1") (pinfunction "1_1") (pintype "passive"))
    )
    (net (code "29") (name "CRY2_N") (class "Default")
      (node (ref "Q142") (pin "D") (pinfunction "D_D") (pintype "passive"))
      (node (ref "Q143") (pin "D") (pinfunction "D_D") (pintype "passive"))
      (node (ref "Q144") (pin "G") (pinfunction "G_G") (pintype "passive"))
      (node (ref "Q96") (pin "G") (pinfunction "G_G") (pintype "passive"))
      (node (ref "R109") (pin "1") (pinfunction "1_1") (pintype "passive"))
      (node (ref "R156") (pin "1") (pinfunction "1_1") (pintype "passive"))
      (node (ref "R157") (pin "1") (pinfunction "1_1") (pintype "passive"))
      (node (ref "R169") (pin "1") (pinfunction "1_1") (pintype "passive"))
    )
    (net (code "30") (name "CRY3") (class "Default")
      (node (ref "Q104") (pin "G") (pinfunction "G_G") (pintype "passive"))
      (node (ref "Q153") (pin "D") (pinfunction "D_D") (pintype "passive"))
      (node (ref "Q157") (pin "G") (pinfunction "G_G") (pintype "passive"))
      (node (ref "R173") (pin "1") (pinfunction "1_1") (pintype "passive"))
    )
    (net (code "31") (name "CRY3_N") (class "Default")
      (node (ref "Q106") (pin "G") (pinfunction "G_G") (pintype "passive"))
      (node (ref "Q151") (pin "D") (pinfunction "D_D") (pintype "passive"))
      (node (ref "Q152") (pin "D") (pinfunction "D_D") (pintype "passive"))
      (node (ref "Q153") (pin "G") (pinfunction "G_G") (pintype "passive"))
      (node (ref "R119") (pin "1") (pinfunction "1_1") (pintype "passive"))
      (node (ref "R171") (pin "1") (pinfunction "1_1") (pintype "passive"))
      (node (ref "R172") (pin "1") (pinfunction "1_1") (pintype "passive"))
      (node (ref "R184") (pin "1") (pinfunction "1_1") (pintype "passive"))
    )
    (net (code "32") (name "CRY4") (class "Default")
      (node (ref "Q114") (pin "G") (pinfunction "G_G") (pintype "passive"))
      (node (ref "Q162") (pin "D") (pinfunction "D_D") (pintype "passive"))
      (node (ref "Q166") (pin "G") (pinfunction "G_G") (pintype "passive"))
      (node (ref "R188") (pin "1") (pinfunction "1_1") (pintype "passive"))
    )
    (net (code "33") (name "CRY4_N") (class "Default")
      (node (ref "Q116") (pin "G") (pinfunction "G_G") (pintype "passive"))
      (node (ref "Q160") (pin "D") (pinfunction "D_D") (pintype "passive"))
      (node (ref "Q161") (pin "D") (pinfunction "D_D") (pintype "passive"))
      (node (ref "Q162") (pin "G") (pinfunction "G_G") (pintype "passive"))
      (node (ref "R129") (pin "1") (pinfunction "1_1") (pintype "passive"))
      (node (ref "R186") (pin "1") (pinfunction "1_1") (pintype "passive"))
      (node (ref "R187") (pin "1") (pinfunction "1_1") (pintype "passive"))
      (node (ref "R199") (pin "1") (pinfunction "1_1") (pintype "passive"))
    )
    (net (code "34") (name "CRY5") (class "Default")
      (node (ref "Q124") (pin "G") (pinfunction "G_G") (pintype "passive"))
      (node (ref "Q171") (pin "D") (pinfunction "D_D") (pintype "passive"))
      (node (ref "Q175") (pin "G") (pinfunction "G_G") (pintype "passive"))
      (node (ref "R203") (pin "1") (pinfunction "1_1") (pintype "passive"))
    )
    (net (code "35") (name "CRY5_N") (class "Default")
      (node (ref "Q126") (pin "G") (pinfunction "G_G") (pintype "passive"))
      (node (ref "Q169") (pin "D") (pinfunction "D_D") (pintype "passive"))
      (node (ref "Q170") (pin "D") (pinfunction "D_D") (pintype "passive"))
      (node (ref "Q171") (pin "G") (pinfunction "G_G") (pintype "passive"))
      (node (ref "R139") (pin "1") (pinfunction "1_1") (pintype "passive"))
      (node (ref "R201") (pin "1") (pinfunction "1_1") (pintype "passive"))
      (node (ref "R202") (pin "1") (pinfunction "1_1") (pintype "passive"))
      (node (ref "R214") (pin "1") (pinfunction "1_1") (pintype "passive"))
    )
    (net (code "36") (name "CRY6") (class "Default")
      (node (ref "Q134") (pin "G") (pinfunction "G_G") (pintype "passive"))
      (node (ref "Q180") (pin "D") (pinfunction "D_D") (pintype "passive"))
      (node (ref "Q184") (pin "G") (pinfunction "G_G") (pintype "passive"))
      (node (ref "R218") (pin "1") (pinfunction "1_1") (pintype "passive"))
    )
    (net (code "37") (name "CRY6_N") (class "Default")
      (node (ref "Q136") (pin "G") (pinfunction "G_G") (pintype "passive"))
      (node (ref "Q178") (pin "D") (pinfunction "D_D") (pintype "passive"))
      (node (ref "Q179") (pin "D") (pinfunction "D_D") (pintype "passive"))
      (node (ref "Q180") (pin "G") (pinfunction "G_G") (pintype "passive"))
      (node (ref "R149") (pin "1") (pinfunction "1_1") (pintype "passive"))
      (node (ref "R216") (pin "1") (pinfunction "1_1") (pintype "passive"))
      (node (ref "R217") (pin "1") (pinfunction "1_1") (pintype "passive"))
      (node (ref "R229") (pin "1") (pinfunction "1_1") (pintype "passive"))
    )
    (net (code "38") (name "DO_INVERT") (class "Default")
      (node (ref "Q1") (pin "G") (pinfunction "G_G") (pintype "passive"))
      (node (ref "Q11") (pin "G") (pinfunction "G_G") (pintype "passive"))
      (node (ref "Q12") (pin "G") (pinfunction "G_G") (pintype "passive"))
      (node (ref "Q17") (pin "G") (pinfunction "G_G") (pintype "passive"))
      (node (ref "Q210") (pin "D") (pinfunction "D_D") (pintype "passive"))
      (node (ref "Q6") (pin "G") (pinfunction "G_G") (pintype "passive"))
      (node (ref "Q64") (pin "G") (pinfunction "G_G") (pintype "passive"))
      (node (ref "Q69") (pin "G") (pinfunction "G_G") (pintype "passive"))
      (node (ref "Q74") (pin "G") (pinfunction "G_G") (pintype "passive"))
      (node (ref "R268") (pin "1") (pinfunction "1_1") (pintype "passive"))
    )
    (net (code "39") (name "DO_INVERT_N") (class "Default")
      (node (ref "Q14") (pin "G") (pinfunction "G_G") (pintype "passive"))
      (node (ref "Q19") (pin "G") (pinfunction "G_G") (pintype "passive"))
      (node (ref "Q209") (pin "D") (pinfunction "D_D") (pintype "passive"))
      (node (ref "Q210") (pin "G") (pinfunction "G_G") (pintype "passive"))
      (node (ref "Q3") (pin "G") (pinfunction "G_G") (pintype "passive"))
      (node (ref "Q61") (pin "G") (pinfunction "G_G") (pintype "passive"))
      (node (ref "Q66") (pin "G") (pinfunction "G_G") (pintype "passive"))
      (node (ref "Q71") (pin "G") (pinfunction "G_G") (pintype "passive"))
      (node (ref "Q76") (pin "G") (pinfunction "G_G") (pintype "passive"))
      (node (ref "Q8") (pin "G") (pinfunction "G_G") (pintype "passive"))
      (node (ref "R14") (pin "1") (pinfunction "1_1") (pintype "passive"))
      (node (ref "R19") (pin "1") (pinfunction "1_1") (pintype "passive"))
      (node (ref "R24") (pin "1") (pinfunction "1_1") (pintype "passive"))
      (node (ref "R257") (pin "1") (pinfunction "1_1") (pintype "passive"))
      (node (ref "R258") (pin "1") (pinfunction "1_1") (pintype "passive"))
      (node (ref "R4") (pin "1") (pinfunction "1_1") (pintype "passive"))
      (node (ref "R79") (pin "1") (pinfunction "1_1") (pintype "passive"))
      (node (ref "R84") (pin "1") (pinfunction "1_1") (pintype "passive"))
      (node (ref "R89") (pin "1") (pinfunction "1_1") (pintype "passive"))
      (node (ref "R9") (pin "1") (pinfunction "1_1") (pintype "passive"))
    )
    (net (code "40") (name "DO_INVERT_RAW") (class "Default")
      (node (ref "Q209") (pin "G") (pinfunction "G_G") (pintype "passive"))
      (node (ref "TP1") (pin "P$1") (pinfunction "P$1_P$1") (pintype "bidirectional"))
    )
    (net (code "41") (name "GND") (class "Default")
      (node (ref "C1") (pin "2") (pinfunction "2_2") (pintype "passive"))
      (node (ref "C2") (pin "2") (pinfunction "2_2") (pintype "passive"))
      (node (ref "C3") (pin "2") (pinfunction "2_2") (pintype "passive"))
      (node (ref "C4") (pin "2") (pinfunction "2_2") (pintype "passive"))
      (node (ref "C5") (pin "2") (pinfunction "2_2") (pintype "passive"))
      (node (ref "C6") (pin "K") (pinfunction "K_K") (pintype "passive"))
      (node (ref "J1") (pin "1") (pinfunction "1_1") (pintype "bidirectional"))
      (node (ref "J1") (pin "10") (pinfunction "10_10") (pintype "bidirectional"))
      (node (ref "J1") (pin "11") (pinfunction "11_11") (pintype "bidirectional"))
      (node (ref "J1") (pin "20") (pinfunction "20_20") (pintype "bidirectional"))
      (node (ref "J2") (pin "1") (pinfunction "1_1") (pintype "bidirectional"))
      (node (ref "J2") (pin "10") (pinfunction "10_10") (pintype "bidirectional"))
      (node (ref "J2") (pin "11") (pinfunction "11_11") (pintype "bidirectional"))
      (node (ref "J2") (pin "20") (pinfunction "20_20") (pintype "bidirectional"))
      (node (ref "J3") (pin "1") (pinfunction "1_1") (pintype "bidirectional"))
      (node (ref "J3") (pin "10") (pinfunction "10_10") (pintype "bidirectional"))
      (node (ref "J3") (pin "11") (pinfunction "11_11") (pintype "bidirectional"))
      (node (ref "J3") (pin "20") (pinfunction "20_20") (pintype "bidirectional"))
      (node (ref "J4") (pin "1") (pinfunction "1_1") (pintype "bidirectional"))
      (node (ref "J4") (pin "10") (pinfunction "10_10") (pintype "bidirectional"))
      (node (ref "J4") (pin "19") (pinfunction "19_19") (pintype "bidirectional"))
      (node (ref "J4") (pin "28") (pinfunction "28_28") (pintype "bidirectional"))
      (node (ref "PP2") (pin "1") (pinfunction "P$1_1") (pintype "bidirectional"))
      (node (ref "Q10") (pin "S") (pinfunction "S_S") (pintype "passive"))
      (node (ref "Q100") (pin "S") (pinfunction "S_S") (pintype "passive"))
      (node (ref "Q102") (pin "S") (pinfunction "S_S") (pintype "passive"))
      (node (ref "Q103") (pin "S") (pinfunction "S_S") (pintype "passive"))
      (node (ref "Q105") (pin "S") (pinfunction "S_S") (pintype "passive"))
      (node (ref "Q107") (pin "S") (pinfunction "S_S") (pintype "passive"))
      (node (ref "Q108") (pin "S") (pinfunction "S_S") (pintype "passive"))
      (node (ref "Q110") (pin "S") (pinfunction "S_S") (pintype "passive"))
      (node (ref "Q112") (pin "S") (pinfunction "S_S") (pintype "passive"))
      (node (ref "Q113") (pin "S") (pinfunction "S_S") (pintype "passive"))
      (node (ref "Q115") (pin "S") (pinfunction "S_S") (pintype "passive"))
      (node (ref "Q117") (pin "S") (pinfunction "S_S") (pintype "passive"))
      (node (ref "Q118") (pin "S") (pinfunction "S_S") (pintype "passive"))
      (node (ref "Q120") (pin "S") (pinfunction "S_S") (pintype "passive"))
      (node (ref "Q122") (pin "S") (pinfunction "S_S") (pintype "passive"))
      (node (ref "Q123") (pin "S") (pinfunction "S_S") (pintype "passive"))
      (node (ref "Q125") (pin "S") (pinfunction "S_S") (pintype "passive"))
      (node (ref "Q127") (pin "S") (pinfunction "S_S") (pintype "passive"))
      (node (ref "Q128") (pin "S") (pinfunction "S_S") (pintype "passive"))
      (node (ref "Q13") (pin "S") (pinfunction "S_S") (pintype "passive"))
      (node (ref "Q130") (pin "S") (pinfunction "S_S") (pintype "passive"))
      (node (ref "Q132") (pin "S") (pinfunction "S_S") (pintype "passive"))
      (node (ref "Q133") (pin "S") (pinfunction "S_S") (pintype "passive"))
      (node (ref "Q135") (pin "S") (pinfunction "S_S") (pintype "passive"))
      (node (ref "Q137") (pin "S") (pinfunction "S_S") (pintype "passive"))
      (node (ref "Q138") (pin "S") (pinfunction "S_S") (pintype "passive"))
      (node (ref "Q140") (pin "S") (pinfunction "S_S") (pintype "passive"))
      (node (ref "Q141") (pin "S") (pinfunction "S_S") (pintype "passive"))
      (node (ref "Q142") (pin "S") (pinfunction "S_S") (pintype "passive"))
      (node (ref "Q143") (pin "S") (pinfunction "S_S") (pintype "passive"))
      (node (ref "Q144") (pin "S") (pinfunction "S_S") (pintype "passive"))
      (node (ref "Q146") (pin "S") (pinfunction "S_S") (pintype "passive"))
      (node (ref "Q147") (pin "S") (pinfunction "S_S") (pintype "passive"))
      (node (ref "Q149") (pin "S") (pinfunction "S_S") (pintype "passive"))
      (node (ref "Q15") (pin "S") (pinfunction "S_S") (pintype "passive"))
      (node (ref "Q150") (pin "S") (pinfunction "S_S") (pintype "passive"))
      (node (ref "Q151") (pin "S") (pinfunction "S_S") (pintype "passive"))
      (node (ref "Q152") (pin "S") (pinfunction "S_S") (pintype "passive"))
      (node (ref "Q153") (pin "S") (pinfunction "S_S") (pintype "passive"))
      (node (ref "Q155") (pin "S") (pinfunction "S_S") (pintype "passive"))
      (node (ref "Q156") (pin "S") (pinfunction "S_S") (pintype "passive"))
      (node (ref "Q158") (pin "S") (pinfunction "S_S") (pintype "passive"))
      (node (ref "Q159") (pin "S") (pinfunction "S_S") (pintype "passive"))
      (node (ref "Q16") (pin "S") (pinfunction "S_S") (pintype "passive"))
      (node (ref "Q160") (pin "S") (pinfunction "S_S") (pintype "passive"))
      (node (ref "Q161") (pin "S") (pinfunction "S_S") (pintype "passive"))
      (node (ref "Q162") (pin "S") (pinfunction "S_S") (pintype "passive"))
      (node (ref "Q164") (pin "S") (pinfunction "S_S") (pintype "passive"))
      (node (ref "Q165") (pin "S") (pinfunction "S_S") (pintype "passive"))
      (node (ref "Q167") (pin "S") (pinfunction "S_S") (pintype "passive"))
      (node (ref "Q168") (pin "S") (pinfunction "S_S") (pintype "passive"))
      (node (ref "Q169") (pin "S") (pinfunction "S_S") (pintype "passive"))
      (node (ref "Q170") (pin "S") (pinfunction "S_S") (pintype "passive"))
      (node (ref "Q171") (pin "S") (pinfunction "S_S") (pintype "passive"))
      (node (ref "Q173") (pin "S") (pinfunction "S_S") (pintype "passive"))
      (node (ref "Q174") (pin "S") (pinfunction "S_S") (pintype "passive"))
      (node (ref "Q176") (pin "S") (pinfunction "S_S") (pintype "passive"))
      (node (ref "Q177") (pin "S") (pinfunction "S_S") (pintype "passive"))
      (node (ref "Q178") (pin "S") (pinfunction "S_S") (pintype "passive"))
      (node (ref "Q179") (pin "S") (pinfunction "S_S") (pintype "passive"))
      (node (ref "Q18") (pin "S") (pinfunction "S_S") (pintype "passive"))
      (node (ref "Q180") (pin "S") (pinfunction "S_S") (pintype "passive"))
      (node (ref "Q182") (pin "S") (pinfunction "S_S") (pintype "passive"))
      (node (ref "Q183") (pin "S") (pinfunction "S_S") (pintype "passive"))
      (node (ref "Q185") (pin "S") (pinfunction "S_S") (pintype "passive"))
      (node (ref "Q186") (pin "S") (pinfunction "S_S") (pintype "passive"))
      (node (ref "Q187") (pin "S") (pinfunction "S_S") (pintype "passive"))
      (node (ref "Q188") (pin "S") (pinfunction "S_S") (pintype "passive"))
      (node (ref "Q189") (pin "S") (pinfunction "S_S") (pintype "passive"))
      (node (ref "Q191") (pin "S") (pinfunction "S_S") (pintype "passive"))
      (node (ref "Q192") (pin "S") (pinfunction "S_S") (pintype "passive"))
      (node (ref "Q193") (pin "S") (pinfunction "S_S") (pintype "passive"))
      (node (ref "Q194") (pin "S") (pinfunction "S_S") (pintype "passive"))
      (node (ref "Q195") (pin "S") (pinfunction "S_S") (pintype "passive"))
      (node (ref "Q196") (pin "S") (pinfunction "S_S") (pintype "passive"))
      (node (ref "Q197") (pin "S") (pinfunction "S_S") (pintype "passive"))
      (node (ref "Q198") (pin "S") (pinfunction "S_S") (pintype "passive"))
      (node (ref "Q199") (pin "S") (pinfunction "S_S") (pintype "passive"))
      (node (ref "Q2") (pin "S") (pinfunction "S_S") (pintype "passive"))
      (node (ref "Q20") (pin "S") (pinfunction "S_S") (pintype "passive"))
      (node (ref "Q200") (pin "S") (pinfunction "S_S") (pintype "passive"))
      (node (ref "Q201") (pin "S") (pinfunction "S_S") (pintype "passive"))
      (node (ref "Q202") (pin "S") (pinfunction "S_S") (pintype "passive"))
      (node (ref "Q203") (pin "S") (pinfunction "S_S") (pintype "passive"))
      (node (ref "Q204") (pin "S") (pinfunction "S_S") (pintype "passive"))
      (node (ref "Q205") (pin "S") (pinfunction "S_S") (pintype "passive"))
      (node (ref "Q206") (pin "S") (pinfunction "S_S") (pintype "passive"))
      (node (ref "Q207") (pin "S") (pinfunction "S_S") (pintype "passive"))
      (node (ref "Q208") (pin "S") (pinfunction "S_S") (pintype "passive"))
      (node (ref "Q209") (pin "S") (pinfunction "S_S") (pintype "passive"))
      (node (ref "Q21") (pin "S") (pinfunction "S_S") (pintype "passive"))
      (node (ref "Q210") (pin "S") (pinfunction "S_S") (pintype "passive"))
      (node (ref "Q211") (pin "S") (pinfunction "S_S") (pintype "passive"))
      (node (ref "Q212") (pin "S") (pinfunction "S_S") (pintype "passive"))
      (node (ref "Q213") (pin "S") (pinfunction "S_S") (pintype "passive"))
      (node (ref "Q23") (pin "S") (pinfunction "S_S") (pintype "passive"))
      (node (ref "Q25") (pin "S") (pinfunction "S_S") (pintype "passive"))
      (node (ref "Q26") (pin "S") (pinfunction "S_S") (pintype "passive"))
      (node (ref "Q28") (pin "S") (pinfunction "S_S") (pintype "passive"))
      (node (ref "Q30") (pin "S") (pinfunction "S_S") (pintype "passive"))
      (node (ref "Q31") (pin "S") (pinfunction "S_S") (pintype "passive"))
      (node (ref "Q33") (pin "S") (pinfunction "S_S") (pintype "passive"))
      (node (ref "Q35") (pin "S") (pinfunction "S_S") (pintype "passive"))
      (node (ref "Q36") (pin "S") (pinfunction "S_S") (pintype "passive"))
      (node (ref "Q38") (pin "S") (pinfunction "S_S") (pintype "passive"))
      (node (ref "Q4") (pin "S") (pinfunction "S_S") (pintype "passive"))
      (node (ref "Q40") (pin "S") (pinfunction "S_S") (pintype "passive"))
      (node (ref "Q41") (pin "S") (pinfunction "S_S") (pintype "passive"))
      (node (ref "Q43") (pin "S") (pinfunction "S_S") (pintype "passive"))
      (node (ref "Q44") (pin "S") (pinfunction "S_S") (pintype "passive"))
      (node (ref "Q45") (pin "S") (pinfunction "S_S") (pintype "passive"))
      (node (ref "Q46") (pin "S") (pinfunction "S_S") (pintype "passive"))
      (node (ref "Q47") (pin "S") (pinfunction "S_S") (pintype "passive"))
      (node (ref "Q49") (pin "S") (pinfunction "S_S") (pintype "passive"))
      (node (ref "Q5") (pin "S") (pinfunction "S_S") (pintype "passive"))
      (node (ref "Q50") (pin "S") (pinfunction "S_S") (pintype "passive"))
      (node (ref "Q51") (pin "S") (pinfunction "S_S") (pintype "passive"))
      (node (ref "Q52") (pin "S") (pinfunction "S_S") (pintype "passive"))
      (node (ref "Q53") (pin "S") (pinfunction "S_S") (pintype "passive"))
      (node (ref "Q55") (pin "S") (pinfunction "S_S") (pintype "passive"))
      (node (ref "Q56") (pin "S") (pinfunction "S_S") (pintype "passive"))
      (node (ref "Q58") (pin "S") (pinfunction "S_S") (pintype "passive"))
      (node (ref "Q59") (pin "S") (pinfunction "S_S") (pintype "passive"))
      (node (ref "Q60") (pin "S") (pinfunction "S_S") (pintype "passive"))
      (node (ref "Q62") (pin "S") (pinfunction "S_S") (pintype "passive"))
      (node (ref "Q63") (pin "S") (pinfunction "S_S") (pintype "passive"))
      (node (ref "Q65") (pin "S") (pinfunction "S_S") (pintype "passive"))
      (node (ref "Q67") (pin "S") (pinfunction "S_S") (pintype "passive"))
      (node (ref "Q68") (pin "S") (pinfunction "S_S") (pintype "passive"))
      (node (ref "Q7") (pin "S") (pinfunction "S_S") (pintype "passive"))
      (node (ref "Q70") (pin "S") (pinfunction "S_S") (pintype "passive"))
      (node (ref "Q72") (pin "S") (pinfunction "S_S") (pintype "passive"))
      (node (ref "Q73") (pin "S") (pinfunction "S_S") (pintype "passive"))
      (node (ref "Q75") (pin "S") (pinfunction "S_S") (pintype "passive"))
      (node (ref "Q77") (pin "S") (pinfunction "S_S") (pintype "passive"))
      (node (ref "Q78") (pin "S") (pinfunction "S_S") (pintype "passive"))
      (node (ref "Q80") (pin "S") (pinfunction "S_S") (pintype "passive"))
      (node (ref "Q82") (pin "S") (pinfunction "S_S") (pintype "passive"))
      (node (ref "Q83") (pin "S") (pinfunction "S_S") (pintype "passive"))
      (node (ref "Q85") (pin "S") (pinfunction "S_S") (pintype "passive"))
      (node (ref "Q87") (pin "S") (pinfunction "S_S") (pintype "passive"))
      (node (ref "Q88") (pin "S") (pinfunction "S_S") (pintype "passive"))
      (node (ref "Q9") (pin "S") (pinfunction "S_S") (pintype "passive"))
      (node (ref "Q90") (pin "S") (pinfunction "S_S") (pintype "passive"))
      (node (ref "Q92") (pin "S") (pinfunction "S_S") (pintype "passive"))
      (node (ref "Q93") (pin "S") (pinfunction "S_S") (pintype "passive"))
      (node (ref "Q95") (pin "S") (pinfunction "S_S") (pintype "passive"))
      (node (ref "Q97") (pin "S") (pinfunction "S_S") (pintype "passive"))
      (node (ref "Q98") (pin "S") (pinfunction "S_S") (pintype "passive"))
      (node (ref "TP4") (pin "P$1") (pinfunction "P$1_P$1") (pintype "bidirectional"))
      (node (ref "TP5") (pin "P$1") (pinfunction "P$1_P$1") (pintype "bidirectional"))
      (node (ref "TP6") (pin "P$1") (pinfunction "P$1_P$1") (pintype "bidirectional"))
      (node (ref "TP7") (pin "P$1") (pinfunction "P$1_P$1") (pintype "bidirectional"))
    )
    (net (code "42") (name "INV_B0") (class "Default")
      (node (ref "Q16") (pin "D") (pinfunction "D_D") (pintype "passive"))
      (node (ref "Q22") (pin "G") (pinfunction "G_G") (pintype "passive"))
      (node (ref "Q57") (pin "G") (pinfunction "G_G") (pintype "passive"))
      (node (ref "R18") (pin "1") (pinfunction "1_1") (pintype "passive"))
    )
    (net (code "43") (name "INV_B0_N") (class "Default")
      (node (ref "Q12") (pin "D") (pinfunction "D_D") (pintype "passive"))
      (node (ref "Q14") (pin "D") (pinfunction "D_D") (pintype "passive"))
      (node (ref "Q16") (pin "G") (pinfunction "G_G") (pintype "passive"))
      (node (ref "Q24") (pin "G") (pinfunction "G_G") (pintype "passive"))
      (node (ref "R16") (pin "1") (pinfunction "1_1") (pintype "passive"))
      (node (ref "R17") (pin "1") (pinfunction "1_1") (pintype "passive"))
      (node (ref "R29") (pin "1") (pinfunction "1_1") (pintype "passive"))
      (node (ref "R74") (pin "1") (pinfunction "1_1") (pintype "passive"))
    )
    (net (code "44") (name "INV_B1") (class "Default")
      (node (ref "Q21") (pin "D") (pinfunction "D_D") (pintype "passive"))
      (node (ref "Q32") (pin "G") (pinfunction "G_G") (pintype "passive"))
      (node (ref "Q54") (pin "G") (pinfunction "G_G") (pintype "passive"))
      (node (ref "R23") (pin "1") (pinfunction "1_1") (pintype "passive"))
    )
    (net (code "45") (name "INV_B1_N") (class "Default")
      (node (ref "Q17") (pin "D") (pinfunction "D_D") (pintype "passive"))
      (node (ref "Q19") (pin "D") (pinfunction "D_D") (pintype "passive"))
      (node (ref "Q21") (pin "G") (pinfunction "G_G") (pintype "passive"))
      (node (ref "Q34") (pin "G") (pinfunction "G_G") (pintype "passive"))
      (node (ref "R21") (pin "1") (pinfunction "1_1") (pintype "passive"))
      (node (ref "R22") (pin "1") (pinfunction "1_1") (pintype "passive"))
      (node (ref "R39") (pin "1") (pinfunction "1_1") (pintype "passive"))
      (node (ref "R69") (pin "1") (pinfunction "1_1") (pintype "passive"))
    )
    (net (code "46") (name "INV_B2") (class "Default")
      (node (ref "Q145") (pin "G") (pinfunction "G_G") (pintype "passive"))
      (node (ref "Q5") (pin "D") (pinfunction "D_D") (pintype "passive"))
      (node (ref "Q79") (pin "G") (pinfunction "G_G") (pintype "passive"))
      (node (ref "R3") (pin "1") (pinfunction "1_1") (pintype "passive"))
    )
    (net (code "47") (name "INV_B2_N") (class "Default")
      (node (ref "Q1") (pin "D") (pinfunction "D_D") (pintype "passive"))
      (node (ref "Q3") (pin "D") (pinfunction "D_D") (pintype "passive"))
      (node (ref "Q5") (pin "G") (pinfunction "G_G") (pintype "passive"))
      (node (ref "Q81") (pin "G") (pinfunction "G_G") (pintype "passive"))
      (node (ref "R1") (pin "1") (pinfunction "1_1") (pintype "passive"))
      (node (ref "R164") (pin "1") (pinfunction "1_1") (pintype "passive"))
      (node (ref "R2") (pin "1") (pinfunction "1_1") (pintype "passive"))
      (node (ref "R94") (pin "1") (pinfunction "1_1") (pintype "passive"))
    )
    (net (code "48") (name "INV_B3") (class "Default")
      (node (ref "Q10") (pin "D") (pinfunction "D_D") (pintype "passive"))
      (node (ref "Q154") (pin "G") (pinfunction "G_G") (pintype "passive"))
      (node (ref "Q89") (pin "G") (pinfunction "G_G") (pintype "passive"))
      (node (ref "R8") (pin "1") (pinfunction "1_1") (pintype "passive"))
    )
    (net (code "49") (name "INV_B3_N") (class "Default")
      (node (ref "Q10") (pin "G") (pinfunction "G_G") (pintype "passive"))
      (node (ref "Q6") (pin "D") (pinfunction "D_D") (pintype "passive"))
      (node (ref "Q8") (pin "D") (pinfunction "D_D") (pintype "passive"))
      (node (ref "Q91") (pin "G") (pinfunction "G_G") (pintype "passive"))
      (node (ref "R104") (pin "1") (pinfunction "1_1") (pintype "passive"))
      (node (ref "R179") (pin "1") (pinfunction "1_1") (pintype "passive"))
      (node (ref "R6") (pin "1") (pinfunction "1_1") (pintype "passive"))
      (node (ref "R7") (pin "1") (pinfunction "1_1") (pintype "passive"))
    )
    (net (code "50") (name "INV_B4") (class "Default")
      (node (ref "Q163") (pin "G") (pinfunction "G_G") (pintype "passive"))
      (node (ref "Q63") (pin "D") (pinfunction "D_D") (pintype "passive"))
      (node (ref "Q99") (pin "G") (pinfunction "G_G") (pintype "passive"))
      (node (ref "R13") (pin "1") (pinfunction "1_1") (pintype "passive"))
    )
    (net (code "51") (name "INV_B4_N") (class "Default")
      (node (ref "Q101") (pin "G") (pinfunction "G_G") (pintype "passive"))
      (node (ref "Q11") (pin "D") (pinfunction "D_D") (pintype "passive"))
      (node (ref "Q61") (pin "D") (pinfunction "D_D") (pintype "passive"))
      (node (ref "Q63") (pin "G") (pinfunction "G_G") (pintype "passive"))
      (node (ref "R11") (pin "1") (pinfunction "1_1") (pintype "passive"))
      (node (ref "R114") (pin "1") (pinfunction "1_1") (pintype "passive"))
      (node (ref "R12") (pin "1") (pinfunction "1_1") (pintype "passive"))
      (node (ref "R194") (pin "1") (pinfunction "1_1") (pintype "passive"))
    )
    (net (code "52") (name "INV_B5") (class "Default")
      (node (ref "Q109") (pin "G") (pinfunction "G_G") (pintype "passive"))
      (node (ref "Q172") (pin "G") (pinfunction "G_G") (pintype "passive"))
      (node (ref "Q68") (pin "D") (pinfunction "D_D") (pintype "passive"))
      (node (ref "R78") (pin "1") (pinfunction "1_1") (pintype "passive"))
    )
    (net (code "53") (name "INV_B5_N") (class "Default")
      (node (ref "Q111") (pin "G") (pinfunction "G_G") (pintype "passive"))
      (node (ref "Q64") (pin "D") (pinfunction "D_D") (pintype "passive"))
      (node (ref "Q66") (pin "D") (pinfunction "D_D") (pintype "passive"))
      (node (ref "Q68") (pin "G") (pinfunction "G_G") (pintype "passive"))
      (node (ref "R124") (pin "1") (pinfunction "1_1") (pintype "passive"))
      (node (ref "R209") (pin "1") (pinfunction "1_1") (pintype "passive"))
      (node (ref "R76") (pin "1") (pinfunction "1_1") (pintype "passive"))
      (node (ref "R77") (pin "1") (pinfunction "1_1") (pintype "passive"))
    )
    (net (code "54") (name "INV_B6") (class "Default")
      (node (ref "Q119") (pin "G") (pinfunction "G_G") (pintype "passive"))
      (node (ref "Q181") (pin "G") (pinfunction "G_G") (pintype "passive"))
      (node (ref "Q73") (pin "D") (pinfunction "D_D") (pintype "passive"))
      (node (ref "R83") (pin "1") (pinfunction "1_1") (pintype "passive"))
    )
    (net (code "55") (name "INV_B6_N") (class "Default")
      (node (ref "Q121") (pin "G") (pinfunction "G_G") (pintype "passive"))
      (node (ref "Q69") (pin "D") (pinfunction "D_D") (pintype "passive"))
      (node (ref "Q71") (pin "D") (pinfunction "D_D") (pintype "passive"))
      (node (ref "Q73") (pin "G") (pinfunction "G_G") (pintype "passive"))
      (node (ref "R134") (pin "1") (pinfunction "1_1") (pintype "passive"))
      (node (ref "R224") (pin "1") (pinfunction "1_1") (pintype "passive"))
      (node (ref "R81") (pin "1") (pinfunction "1_1") (pintype "passive"))
      (node (ref "R82") (pin "1") (pinfunction "1_1") (pintype "passive"))
    )
    (net (code "56") (name "INV_B7") (class "Default")
      (node (ref "Q129") (pin "G") (pinfunction "G_G") (pintype "passive"))
      (node (ref "Q190") (pin "G") (pinfunction "G_G") (pintype "passive"))
      (node (ref "Q78") (pin "D") (pinfunction "D_D") (pintype "passive"))
      (node (ref "R88") (pin "1") (pinfunction "1_1") (pintype "passive"))
    )
    (net (code "57") (name "INV_B7_N") (class "Default")
      (node (ref "Q131") (pin "G") (pinfunction "G_G") (pintype "passive"))
      (node (ref "Q74") (pin "D") (pinfunction "D_D") (pintype "passive"))
      (node (ref "Q76") (pin "D") (pinfunction "D_D") (pintype "passive"))
      (node (ref "Q78") (pin "G") (pinfunction "G_G") (pintype "passive"))
      (node (ref "R144") (pin "1") (pinfunction "1_1") (pintype "passive"))
      (node (ref "R239") (pin "1") (pinfunction "1_1") (pintype "passive"))
      (node (ref "R86") (pin "1") (pinfunction "1_1") (pintype "passive"))
      (node (ref "R87") (pin "1") (pinfunction "1_1") (pintype "passive"))
    )
    (net (code "58") (name "IN_A0") (class "Default")
      (node (ref "J1") (pin "2") (pinfunction "2_2") (pintype "bidirectional"))
      (node (ref "J4") (pin "2") (pinfunction "2_2") (pintype "bidirectional"))
      (node (ref "Q193") (pin "G") (pinfunction "G_G") (pintype "passive"))
      (node (ref "Q25") (pin "G") (pinfunction "G_G") (pintype "passive"))
      (node (ref "Q58") (pin "G") (pinfunction "G_G") (pintype "passive"))
    )
    (net (code "59") (name "IN_A0_N") (class "Default")
      (node (ref "Q193") (pin "D") (pinfunction "D_D") (pintype "passive"))
      (node (ref "Q23") (pin "G") (pinfunction "G_G") (pintype "passive"))
      (node (ref "R241") (pin "1") (pinfunction "1_1") (pintype "passive"))
      (node (ref "R269") (pin "1") (pinfunction "1_1") (pintype "passive"))
      (node (ref "R30") (pin "1") (pinfunction "1_1") (pintype "passive"))
      (node (ref "R75") (pin "1") (pinfunction "1_1") (pintype "passive"))
    )
    (net (code "60") (name "IN_A1") (class "Default")
      (node (ref "J1") (pin "3") (pinfunction "3_3") (pintype "bidirectional"))
      (node (ref "J4") (pin "3") (pinfunction "3_3") (pintype "bidirectional"))
      (node (ref "Q194") (pin "G") (pinfunction "G_G") (pintype "passive"))
      (node (ref "Q35") (pin "G") (pinfunction "G_G") (pintype "passive"))
      (node (ref "Q55") (pin "G") (pinfunction "G_G") (pintype "passive"))
    )
    (net (code "61") (name "IN_A1_N") (class "Default")
      (node (ref "Q194") (pin "D") (pinfunction "D_D") (pintype "passive"))
      (node (ref "Q33") (pin "G") (pinfunction "G_G") (pintype "passive"))
      (node (ref "R242") (pin "1") (pinfunction "1_1") (pintype "passive"))
      (node (ref "R270") (pin "1") (pinfunction "1_1") (pintype "passive"))
      (node (ref "R40") (pin "1") (pinfunction "1_1") (pintype "passive"))
      (node (ref "R70") (pin "1") (pinfunction "1_1") (pintype "passive"))
    )
    (net (code "62") (name "IN_A2") (class "Default")
      (node (ref "J1") (pin "4") (pinfunction "4_4") (pintype "bidirectional"))
      (node (ref "J4") (pin "4") (pinfunction "4_4") (pintype "bidirectional"))
      (node (ref "Q146") (pin "G") (pinfunction "G_G") (pintype "passive"))
      (node (ref "Q195") (pin "G") (pinfunction "G_G") (pintype "passive"))
      (node (ref "Q82") (pin "G") (pinfunction "G_G") (pintype "passive"))
    )
    (net (code "63") (name "IN_A2_N") (class "Default")
      (node (ref "Q195") (pin "D") (pinfunction "D_D") (pintype "passive"))
      (node (ref "Q80") (pin "G") (pinfunction "G_G") (pintype "passive"))
      (node (ref "R165") (pin "1") (pinfunction "1_1") (pintype "passive"))
      (node (ref "R243") (pin "1") (pinfunction "1_1") (pintype "passive"))
      (node (ref "R263") (pin "1") (pinfunction "1_1") (pintype "passive"))
      (node (ref "R95") (pin "1") (pinfunction "1_1") (pintype "passive"))
    )
    (net (code "64") (name "IN_A3") (class "Default")
      (node (ref "J1") (pin "5") (pinfunction "5_5") (pintype "bidirectional"))
      (node (ref "J4") (pin "5") (pinfunction "5_5") (pintype "bidirectional"))
      (node (ref "Q155") (pin "G") (pinfunction "G_G") (pintype "passive"))
      (node (ref "Q196") (pin "G") (pinfunction "G_G") (pintype "passive"))
      (node (ref "Q92") (pin "G") (pinfunction "G_G") (pintype "passive"))
    )
    (net (code "65") (name "IN_A3_N") (class "Default")
      (node (ref "Q196") (pin "D") (pinfunction "D_D") (pintype "passive"))
      (node (ref "Q90") (pin "G") (pinfunction "G_G") (pintype "passive"))
      (node (ref "R105") (pin "1") (pinfunction "1_1") (pintype "passive"))
      (node (ref "R180") (pin "1") (pinfunction "1_1") (pintype "passive"))
      (node (ref "R244") (pin "1") (pinfunction "1_1") (pintype "passive"))
      (node (ref "R272") (pin "1") (pinfunction "1_1") (pintype "passive"))
    )
    (net (code "66") (name "IN_A4") (class "Default")
      (node (ref "J1") (pin "6") (pinfunction "6_6") (pintype "bidirectional"))
      (node (ref "J4") (pin "6") (pinfunction "6_6") (pintype "bidirectional"))
      (node (ref "Q102") (pin "G") (pinfunction "G_G") (pintype "passive"))
      (node (ref "Q164") (pin "G") (pinfunction "G_G") (pintype "passive"))
      (node (ref "Q197") (pin "G") (pinfunction "G_G") (pintype "passive"))
    )
    (net (code "67") (name "IN_A4_N") (class "Default")
      (node (ref "Q100") (pin "G") (pinfunction "G_G") (pintype "passive"))
      (node (ref "Q197") (pin "D") (pinfunction "D_D") (pintype "passive"))
      (node (ref "R115") (pin "1") (pinfunction "1_1") (pintype "passive"))
      (node (ref "R195") (pin "1") (pinfunction "1_1") (pintype "passive"))
      (node (ref "R245") (pin "1") (pinfunction "1_1") (pintype "passive"))
      (node (ref "R271") (pin "1") (pinfunction "1_1") (pintype "passive"))
    )
    (net (code "68") (name "IN_A5") (class "Default")
      (node (ref "J1") (pin "7") (pinfunction "7_7") (pintype "bidirectional"))
      (node (ref "J4") (pin "7") (pinfunction "7_7") (pintype "bidirectional"))
      (node (ref "Q112") (pin "G") (pinfunction "G_G") (pintype "passive"))
      (node (ref "Q173") (pin "G") (pinfunction "G_G") (pintype "passive"))
      (node (ref "Q198") (pin "G") (pinfunction "G_G") (pintype "passive"))
    )
    (net (code "69") (name "IN_A5_N") (class "Default")
      (node (ref "Q110") (pin "G") (pinfunction "G_G") (pintype "passive"))
      (node (ref "Q198") (pin "D") (pinfunction "D_D") (pintype "passive"))
      (node (ref "R125") (pin "1") (pinfunction "1_1") (pintype "passive"))
      (node (ref "R210") (pin "1") (pinfunction "1_1") (pintype "passive"))
      (node (ref "R246") (pin "1") (pinfunction "1_1") (pintype "passive"))
      (node (ref "R273") (pin "1") (pinfunction "1_1") (pintype "passive"))
    )
    (net (code "70") (name "IN_A6") (class "Default")
      (node (ref "J1") (pin "8") (pinfunction "8_8") (pintype "bidirectional"))
      (node (ref "J4") (pin "8") (pinfunction "8_8") (pintype "bidirectional"))
      (node (ref "Q122") (pin "G") (pinfunction "G_G") (pintype "passive"))
      (node (ref "Q182") (pin "G") (pinfunction "G_G") (pintype "passive"))
      (node (ref "Q199") (pin "G") (pinfunction "G_G") (pintype "passive"))
    )
    (net (code "71") (name "IN_A6_N") (class "Default")
      (node (ref "Q120") (pin "G") (pinfunction "G_G") (pintype "passive"))
      (node (ref "Q199") (pin "D") (pinfunction "D_D") (pintype "passive"))
      (node (ref "R135") (pin "1") (pinfunction "1_1") (pintype "passive"))
      (node (ref "R225") (pin "1") (pinfunction "1_1") (pintype "passive"))
      (node (ref "R247") (pin "1") (pinfunction "1_1") (pintype "passive"))
      (node (ref "R274") (pin "1") (pinfunction "1_1") (pintype "passive"))
    )
    (net (code "72") (name "IN_A7") (class "Default")
      (node (ref "J1") (pin "9") (pinfunction "9_9") (pintype "bidirectional"))
      (node (ref "J4") (pin "9") (pinfunction "9_9") (pintype "bidirectional"))
      (node (ref "Q132") (pin "G") (pinfunction "G_G") (pintype "passive"))
      (node (ref "Q191") (pin "G") (pinfunction "G_G") (pintype "passive"))
      (node (ref "Q200") (pin "G") (pinfunction "G_G") (pintype "passive"))
    )
    (net (code "73") (name "IN_A7_N") (class "Default")
      (node (ref "Q130") (pin "G") (pinfunction "G_G") (pintype "passive"))
      (node (ref "Q200") (pin "D") (pinfunction "D_D") (pintype "passive"))
      (node (ref "R145") (pin "1") (pinfunction "1_1") (pintype "passive"))
      (node (ref "R240") (pin "1") (pinfunction "1_1") (pintype "passive"))
      (node (ref "R248") (pin "1") (pinfunction "1_1") (pintype "passive"))
      (node (ref "R275") (pin "1") (pinfunction "1_1") (pintype "passive"))
    )
    (net (code "74") (name "IN_B0") (class "Default")
      (node (ref "J2") (pin "2") (pinfunction "2_2") (pintype "bidirectional"))
      (node (ref "J4") (pin "11") (pinfunction "11_11") (pintype "bidirectional"))
      (node (ref "Q15") (pin "G") (pinfunction "G_G") (pintype "passive"))
      (node (ref "Q201") (pin "G") (pinfunction "G_G") (pintype "passive"))
    )
    (net (code "75") (name "IN_B0_N") (class "Default")
      (node (ref "Q13") (pin "G") (pinfunction "G_G") (pintype "passive"))
      (node (ref "Q201") (pin "D") (pinfunction "D_D") (pintype "passive"))
      (node (ref "R20") (pin "1") (pinfunction "1_1") (pintype "passive"))
      (node (ref "R249") (pin "1") (pinfunction "1_1") (pintype "passive"))
      (node (ref "R262") (pin "1") (pinfunction "1_1") (pintype "passive"))
    )
    (net (code "76") (name "IN_B1") (class "Default")
      (node (ref "J2") (pin "3") (pinfunction "3_3") (pintype "bidirectional"))
      (node (ref "J4") (pin "12") (pinfunction "12_12") (pintype "bidirectional"))
      (node (ref "Q20") (pin "G") (pinfunction "G_G") (pintype "passive"))
      (node (ref "Q202") (pin "G") (pinfunction "G_G") (pintype "passive"))
    )
    (net (code "77") (name "IN_B1_N") (class "Default")
      (node (ref "Q18") (pin "G") (pinfunction "G_G") (pintype "passive"))
      (node (ref "Q202") (pin "D") (pinfunction "D_D") (pintype "passive"))
      (node (ref "R25") (pin "1") (pinfunction "1_1") (pintype "passive"))
      (node (ref "R250") (pin "1") (pinfunction "1_1") (pintype "passive"))
      (node (ref "R261") (pin "1") (pinfunction "1_1") (pintype "passive"))
    )
    (net (code "78") (name "IN_B2") (class "Default")
      (node (ref "J2") (pin "4") (pinfunction "4_4") (pintype "bidirectional"))
      (node (ref "J4") (pin "13") (pinfunction "13_13") (pintype "bidirectional"))
      (node (ref "Q203") (pin "G") (pinfunction "G_G") (pintype "passive"))
      (node (ref "Q4") (pin "G") (pinfunction "G_G") (pintype "passive"))
    )
    (net (code "79") (name "IN_B2_N") (class "Default")
      (node (ref "Q2") (pin "G") (pinfunction "G_G") (pintype "passive"))
      (node (ref "Q203") (pin "D") (pinfunction "D_D") (pintype "passive"))
      (node (ref "R251") (pin "1") (pinfunction "1_1") (pintype "passive"))
      (node (ref "R260") (pin "1") (pinfunction "1_1") (pintype "passive"))
      (node (ref "R5") (pin "1") (pinfunction "1_1") (pintype "passive"))
    )
    (net (code "80") (name "IN_B3") (class "Default")
      (node (ref "J2") (pin "5") (pinfunction "5_5") (pintype "bidirectional"))
      (node (ref "J4") (pin "14") (pinfunction "14_14") (pintype "bidirectional"))
      (node (ref "Q204") (pin "G") (pinfunction "G_G") (pintype "passive"))
      (node (ref "Q9") (pin "G") (pinfunction "G_G") (pintype "passive"))
    )
    (net (code "81") (name "IN_B3_N") (class "Default")
      (node (ref "Q204") (pin "D") (pinfunction "D_D") (pintype "passive"))
      (node (ref "Q7") (pin "G") (pinfunction "G_G") (pintype "passive"))
      (node (ref "R10") (pin "1") (pinfunction "1_1") (pintype "passive"))
      (node (ref "R252") (pin "1") (pinfunction "1_1") (pintype "passive"))
      (node (ref "R259") (pin "1") (pinfunction "1_1") (pintype "passive"))
    )
    (net (code "82") (name "IN_B4") (class "Default")
      (node (ref "J2") (pin "6") (pinfunction "6_6") (pintype "bidirectional"))
      (node (ref "J4") (pin "15") (pinfunction "15_15") (pintype "bidirectional"))
      (node (ref "Q205") (pin "G") (pinfunction "G_G") (pintype "passive"))
      (node (ref "Q62") (pin "G") (pinfunction "G_G") (pintype "passive"))
    )
    (net (code "83") (name "IN_B4_N") (class "Default")
      (node (ref "Q205") (pin "D") (pinfunction "D_D") (pintype "passive"))
      (node (ref "Q60") (pin "G") (pinfunction "G_G") (pintype "passive"))
      (node (ref "R15") (pin "1") (pinfunction "1_1") (pintype "passive"))
      (node (ref "R253") (pin "1") (pinfunction "1_1") (pintype "passive"))
      (node (ref "R264") (pin "1") (pinfunction "1_1") (pintype "passive"))
    )
    (net (code "84") (name "IN_B5") (class "Default")
      (node (ref "J2") (pin "7") (pinfunction "7_7") (pintype "bidirectional"))
      (node (ref "J4") (pin "16") (pinfunction "16_16") (pintype "bidirectional"))
      (node (ref "Q206") (pin "G") (pinfunction "G_G") (pintype "passive"))
      (node (ref "Q67") (pin "G") (pinfunction "G_G") (pintype "passive"))
    )
    (net (code "85") (name "IN_B5_N") (class "Default")
      (node (ref "Q206") (pin "D") (pinfunction "D_D") (pintype "passive"))
      (node (ref "Q65") (pin "G") (pinfunction "G_G") (pintype "passive"))
      (node (ref "R254") (pin "1") (pinfunction "1_1") (pintype "passive"))
      (node (ref "R265") (pin "1") (pinfunction "1_1") (pintype "passive"))
      (node (ref "R80") (pin "1") (pinfunction "1_1") (pintype "passive"))
    )
    (net (code "86") (name "IN_B6") (class "Default")
      (node (ref "J2") (pin "8") (pinfunction "8_8") (pintype "bidirectional"))
      (node (ref "J4") (pin "17") (pinfunction "17_17") (pintype "bidirectional"))
      (node (ref "Q207") (pin "G") (pinfunction "G_G") (pintype "passive"))
      (node (ref "Q72") (pin "G") (pinfunction "G_G") (pintype "passive"))
    )
    (net (code "87") (name "IN_B6_N") (class "Default")
      (node (ref "Q207") (pin "D") (pinfunction "D_D") (pintype "passive"))
      (node (ref "Q70") (pin "G") (pinfunction "G_G") (pintype "passive"))
      (node (ref "R255") (pin "1") (pinfunction "1_1") (pintype "passive"))
      (node (ref "R266") (pin "1") (pinfunction "1_1") (pintype "passive"))
      (node (ref "R85") (pin "1") (pinfunction "1_1") (pintype "passive"))
    )
    (net (code "88") (name "IN_B7") (class "Default")
      (node (ref "J2") (pin "9") (pinfunction "9_9") (pintype "bidirectional"))
      (node (ref "J4") (pin "18") (pinfunction "18_18") (pintype "bidirectional"))
      (node (ref "Q208") (pin "G") (pinfunction "G_G") (pintype "passive"))
      (node (ref "Q77") (pin "G") (pinfunction "G_G") (pintype "passive"))
    )
    (net (code "89") (name "IN_B7_N") (class "Default")
      (node (ref "Q208") (pin "D") (pinfunction "D_D") (pintype "passive"))
      (node (ref "Q75") (pin "G") (pinfunction "G_G") (pintype "passive"))
      (node (ref "R256") (pin "1") (pinfunction "1_1") (pintype "passive"))
      (node (ref "R267") (pin "1") (pinfunction "1_1") (pintype "passive"))
      (node (ref "R90") (pin "1") (pinfunction "1_1") (pintype "passive"))
    )
    (net (code "90") (name "Net-(D1-C)") (class "Default")
      (node (ref "D1") (pin "K") (pinfunction "C_K") (pintype "passive"))
      (node (ref "R2") (pin "2") (pinfunction "2_2") (pintype "passive"))
    )
    (net (code "91") (name "Net-(D2-C)") (class "Default")
      (node (ref "D2") (pin "K") (pinfunction "C_K") (pintype "passive"))
      (node (ref "R4") (pin "2") (pinfunction "2_2") (pintype "passive"))
    )
    (net (code "92") (name "Net-(D3-C)") (class "Default")
      (node (ref "D3") (pin "K") (pinfunction "C_K") (pintype "passive"))
      (node (ref "R5") (pin "2") (pinfunction "2_2") (pintype "passive"))
    )
    (net (code "93") (name "Net-(D4-C)") (class "Default")
      (node (ref "D4") (pin "K") (pinfunction "C_K") (pintype "passive"))
      (node (ref "R7") (pin "2") (pinfunction "2_2") (pintype "passive"))
    )
    (net (code "94") (name "Net-(D5-C)") (class "Default")
      (node (ref "D5") (pin "K") (pinfunction "C_K") (pintype "passive"))
      (node (ref "R9") (pin "2") (pinfunction "2_2") (pintype "passive"))
    )
    (net (code "95") (name "Net-(D6-C)") (class "Default")
      (node (ref "D6") (pin "K") (pinfunction "C_K") (pintype "passive"))
      (node (ref "R10") (pin "2") (pinfunction "2_2") (pintype "passive"))
    )
    (net (code "96") (name "Net-(D7-C)") (class "Default")
      (node (ref "D7") (pin "K") (pinfunction "C_K") (pintype "passive"))
      (node (ref "R12") (pin "2") (pinfunction "2_2") (pintype "passive"))
    )
    (net (code "97") (name "Net-(D8-C)") (class "Default")
      (node (ref "D8") (pin "K") (pinfunction "C_K") (pintype "passive"))
      (node (ref "R14") (pin "2") (pinfunction "2_2") (pintype "passive"))
    )
    (net (code "98") (name "Net-(D9-C)") (class "Default")
      (node (ref "D9") (pin "K") (pinfunction "C_K") (pintype "passive"))
      (node (ref "R15") (pin "2") (pinfunction "2_2") (pintype "passive"))
    )
    (net (code "99") (name "Net-(D10-C)") (class "Default")
      (node (ref "D10") (pin "K") (pinfunction "C_K") (pintype "passive"))
      (node (ref "R17") (pin "2") (pinfunction "2_2") (pintype "passive"))
    )
    (net (code "100") (name "Net-(D11-C)") (class "Default")
      (node (ref "D11") (pin "K") (pinfunction "C_K") (pintype "passive"))
      (node (ref "R19") (pin "2") (pinfunction "2_2") (pintype "passive"))
    )
    (net (code "101") (name "Net-(D12-C)") (class "Default")
      (node (ref "D12") (pin "K") (pinfunction "C_K") (pintype "passive"))
      (node (ref "R20") (pin "2") (pinfunction "2_2") (pintype "passive"))
    )
    (net (code "102") (name "Net-(D13-C)") (class "Default")
      (node (ref "D13") (pin "K") (pinfunction "C_K") (pintype "passive"))
      (node (ref "R22") (pin "2") (pinfunction "2_2") (pintype "passive"))
    )
    (net (code "103") (name "Net-(D14-C)") (class "Default")
      (node (ref "D14") (pin "K") (pinfunction "C_K") (pintype "passive"))
      (node (ref "R24") (pin "2") (pinfunction "2_2") (pintype "passive"))
    )
    (net (code "104") (name "Net-(D15-C)") (class "Default")
      (node (ref "D15") (pin "K") (pinfunction "C_K") (pintype "passive"))
      (node (ref "R25") (pin "2") (pinfunction "2_2") (pintype "passive"))
    )
    (net (code "105") (name "Net-(D16-C)") (class "Default")
      (node (ref "D16") (pin "K") (pinfunction "C_K") (pintype "passive"))
      (node (ref "R27") (pin "2") (pinfunction "2_2") (pintype "passive"))
    )
    (net (code "106") (name "Net-(D17-C)") (class "Default")
      (node (ref "D17") (pin "K") (pinfunction "C_K") (pintype "passive"))
      (node (ref "R29") (pin "2") (pinfunction "2_2") (pintype "passive"))
    )
    (net (code "107") (name "Net-(D18-C)") (class "Default")
      (node (ref "D18") (pin "K") (pinfunction "C_K") (pintype "passive"))
      (node (ref "R30") (pin "2") (pinfunction "2_2") (pintype "passive"))
    )
    (net (code "108") (name "Net-(D19-C)") (class "Default")
      (node (ref "D19") (pin "K") (pinfunction "C_K") (pintype "passive"))
      (node (ref "R32") (pin "2") (pinfunction "2_2") (pintype "passive"))
    )
    (net (code "109") (name "Net-(D20-C)") (class "Default")
      (node (ref "D20") (pin "K") (pinfunction "C_K") (pintype "passive"))
      (node (ref "R34") (pin "2") (pinfunction "2_2") (pintype "passive"))
    )
    (net (code "110") (name "Net-(D21-C)") (class "Default")
      (node (ref "D21") (pin "K") (pinfunction "C_K") (pintype "passive"))
      (node (ref "R35") (pin "2") (pinfunction "2_2") (pintype "passive"))
    )
    (net (code "111") (name "Net-(D22-C)") (class "Default")
      (node (ref "D22") (pin "K") (pinfunction "C_K") (pintype "passive"))
      (node (ref "R37") (pin "2") (pinfunction "2_2") (pintype "passive"))
    )
    (net (code "112") (name "Net-(D23-C)") (class "Default")
      (node (ref "D23") (pin "K") (pinfunction "C_K") (pintype "passive"))
      (node (ref "R39") (pin "2") (pinfunction "2_2") (pintype "passive"))
    )
    (net (code "113") (name "Net-(D24-C)") (class "Default")
      (node (ref "D24") (pin "K") (pinfunction "C_K") (pintype "passive"))
      (node (ref "R40") (pin "2") (pinfunction "2_2") (pintype "passive"))
    )
    (net (code "114") (name "Net-(D25-C)") (class "Default")
      (node (ref "D25") (pin "K") (pinfunction "C_K") (pintype "passive"))
      (node (ref "R42") (pin "2") (pinfunction "2_2") (pintype "passive"))
    )
    (net (code "115") (name "Net-(D26-C)") (class "Default")
      (node (ref "D26") (pin "K") (pinfunction "C_K") (pintype "passive"))
      (node (ref "R44") (pin "2") (pinfunction "2_2") (pintype "passive"))
    )
    (net (code "116") (name "Net-(D27-C)") (class "Default")
      (node (ref "D27") (pin "K") (pinfunction "C_K") (pintype "passive"))
      (node (ref "R45") (pin "2") (pinfunction "2_2") (pintype "passive"))
    )
    (net (code "117") (name "Net-(D28-C)") (class "Default")
      (node (ref "D28") (pin "K") (pinfunction "C_K") (pintype "passive"))
      (node (ref "R47") (pin "2") (pinfunction "2_2") (pintype "passive"))
    )
    (net (code "118") (name "Net-(D29-C)") (class "Default")
      (node (ref "D29") (pin "K") (pinfunction "C_K") (pintype "passive"))
      (node (ref "R49") (pin "2") (pinfunction "2_2") (pintype "passive"))
    )
    (net (code "119") (name "Net-(D30-C)") (class "Default")
      (node (ref "D30") (pin "K") (pinfunction "C_K") (pintype "passive"))
      (node (ref "R50") (pin "2") (pinfunction "2_2") (pintype "passive"))
    )
    (net (code "120") (name "Net-(D31-C)") (class "Default")
      (node (ref "D31") (pin "K") (pinfunction "C_K") (pintype "passive"))
      (node (ref "R52") (pin "2") (pinfunction "2_2") (pintype "passive"))
    )
    (net (code "121") (name "Net-(D32-C)") (class "Default")
      (node (ref "D32") (pin "K") (pinfunction "C_K") (pintype "passive"))
      (node (ref "R54") (pin "2") (pinfunction "2_2") (pintype "passive"))
    )
    (net (code "122") (name "Net-(D33-C)") (class "Default")
      (node (ref "D33") (pin "K") (pinfunction "C_K") (pintype "passive"))
      (node (ref "R55") (pin "2") (pinfunction "2_2") (pintype "passive"))
    )
    (net (code "123") (name "Net-(D34-C)") (class "Default")
      (node (ref "D34") (pin "K") (pinfunction "C_K") (pintype "passive"))
      (node (ref "R57") (pin "2") (pinfunction "2_2") (pintype "passive"))
    )
    (net (code "124") (name "Net-(D35-C)") (class "Default")
      (node (ref "D35") (pin "K") (pinfunction "C_K") (pintype "passive"))
      (node (ref "R59") (pin "2") (pinfunction "2_2") (pintype "passive"))
    )
    (net (code "125") (name "Net-(D36-C)") (class "Default")
      (node (ref "D36") (pin "K") (pinfunction "C_K") (pintype "passive"))
      (node (ref "R60") (pin "2") (pinfunction "2_2") (pintype "passive"))
    )
    (net (code "126") (name "Net-(D37-C)") (class "Default")
      (node (ref "D37") (pin "K") (pinfunction "C_K") (pintype "passive"))
      (node (ref "R62") (pin "2") (pinfunction "2_2") (pintype "passive"))
    )
    (net (code "127") (name "Net-(D38-C)") (class "Default")
      (node (ref "D38") (pin "K") (pinfunction "C_K") (pintype "passive"))
      (node (ref "R64") (pin "2") (pinfunction "2_2") (pintype "passive"))
    )
    (net (code "128") (name "Net-(D39-C)") (class "Default")
      (node (ref "D39") (pin "K") (pinfunction "C_K") (pintype "passive"))
      (node (ref "R65") (pin "2") (pinfunction "2_2") (pintype "passive"))
    )
    (net (code "129") (name "Net-(D40-C)") (class "Default")
      (node (ref "D40") (pin "K") (pinfunction "C_K") (pintype "passive"))
      (node (ref "R67") (pin "2") (pinfunction "2_2") (pintype "passive"))
    )
    (net (code "130") (name "Net-(D41-C)") (class "Default")
      (node (ref "D41") (pin "K") (pinfunction "C_K") (pintype "passive"))
      (node (ref "R69") (pin "2") (pinfunction "2_2") (pintype "passive"))
    )
    (net (code "131") (name "Net-(D42-C)") (class "Default")
      (node (ref "D42") (pin "K") (pinfunction "C_K") (pintype "passive"))
      (node (ref "R70") (pin "2") (pinfunction "2_2") (pintype "passive"))
    )
    (net (code "132") (name "Net-(D43-C)") (class "Default")
      (node (ref "D43") (pin "K") (pinfunction "C_K") (pintype "passive"))
      (node (ref "R72") (pin "2") (pinfunction "2_2") (pintype "passive"))
    )
    (net (code "133") (name "Net-(D44-C)") (class "Default")
      (node (ref "D44") (pin "K") (pinfunction "C_K") (pintype "passive"))
      (node (ref "R74") (pin "2") (pinfunction "2_2") (pintype "passive"))
    )
    (net (code "134") (name "Net-(D45-C)") (class "Default")
      (node (ref "D45") (pin "K") (pinfunction "C_K") (pintype "passive"))
      (node (ref "R75") (pin "2") (pinfunction "2_2") (pintype "passive"))
    )
    (net (code "135") (name "Net-(D46-C)") (class "Default")
      (node (ref "D46") (pin "K") (pinfunction "C_K") (pintype "passive"))
      (node (ref "R77") (pin "2") (pinfunction "2_2") (pintype "passive"))
    )
    (net (code "136") (name "Net-(D47-C)") (class "Default")
      (node (ref "D47") (pin "K") (pinfunction "C_K") (pintype "passive"))
      (node (ref "R79") (pin "2") (pinfunction "2_2") (pintype "passive"))
    )
    (net (code "137") (name "Net-(D48-C)") (class "Default")
      (node (ref "D48") (pin "K") (pinfunction "C_K") (pintype "passive"))
      (node (ref "R80") (pin "2") (pinfunction "2_2") (pintype "passive"))
    )
    (net (code "138") (name "Net-(D49-C)") (class "Default")
      (node (ref "D49") (pin "K") (pinfunction "C_K") (pintype "passive"))
      (node (ref "R82") (pin "2") (pinfunction "2_2") (pintype "passive"))
    )
    (net (code "139") (name "Net-(D50-C)") (class "Default")
      (node (ref "D50") (pin "K") (pinfunction "C_K") (pintype "passive"))
      (node (ref "R84") (pin "2") (pinfunction "2_2") (pintype "passive"))
    )
    (net (code "140") (name "Net-(D51-C)") (class "Default")
      (node (ref "D51") (pin "K") (pinfunction "C_K") (pintype "passive"))
      (node (ref "R85") (pin "2") (pinfunction "2_2") (pintype "passive"))
    )
    (net (code "141") (name "Net-(D52-C)") (class "Default")
      (node (ref "D52") (pin "K") (pinfunction "C_K") (pintype "passive"))
      (node (ref "R87") (pin "2") (pinfunction "2_2") (pintype "passive"))
    )
    (net (code "142") (name "Net-(D53-C)") (class "Default")
      (node (ref "D53") (pin "K") (pinfunction "C_K") (pintype "passive"))
      (node (ref "R89") (pin "2") (pinfunction "2_2") (pintype "passive"))
    )
    (net (code "143") (name "Net-(D54-C)") (class "Default")
      (node (ref "D54") (pin "K") (pinfunction "C_K") (pintype "passive"))
      (node (ref "R90") (pin "2") (pinfunction "2_2") (pintype "passive"))
    )
    (net (code "144") (name "Net-(D55-C)") (class "Default")
      (node (ref "D55") (pin "K") (pinfunction "C_K") (pintype "passive"))
      (node (ref "R92") (pin "2") (pinfunction "2_2") (pintype "passive"))
    )
    (net (code "145") (name "Net-(D56-C)") (class "Default")
      (node (ref "D56") (pin "K") (pinfunction "C_K") (pintype "passive"))
      (node (ref "R94") (pin "2") (pinfunction "2_2") (pintype "passive"))
    )
    (net (code "146") (name "Net-(D57-C)") (class "Default")
      (node (ref "D57") (pin "K") (pinfunction "C_K") (pintype "passive"))
      (node (ref "R95") (pin "2") (pinfunction "2_2") (pintype "passive"))
    )
    (net (code "147") (name "Net-(D58-C)") (class "Default")
      (node (ref "D58") (pin "K") (pinfunction "C_K") (pintype "passive"))
      (node (ref "R97") (pin "2") (pinfunction "2_2") (pintype "passive"))
    )
    (net (code "148") (name "Net-(D59-C)") (class "Default")
      (node (ref "D59") (pin "K") (pinfunction "C_K") (pintype "passive"))
      (node (ref "R99") (pin "2") (pinfunction "2_2") (pintype "passive"))
    )
    (net (code "149") (name "Net-(D60-C)") (class "Default")
      (node (ref "D60") (pin "K") (pinfunction "C_K") (pintype "passive"))
      (node (ref "R100") (pin "2") (pinfunction "2_2") (pintype "passive"))
    )
    (net (code "150") (name "Net-(D61-C)") (class "Default")
      (node (ref "D61") (pin "K") (pinfunction "C_K") (pintype "passive"))
      (node (ref "R102") (pin "2") (pinfunction "2_2") (pintype "passive"))
    )
    (net (code "151") (name "Net-(D62-C)") (class "Default")
      (node (ref "D62") (pin "K") (pinfunction "C_K") (pintype "passive"))
      (node (ref "R104") (pin "2") (pinfunction "2_2") (pintype "passive"))
    )
    (net (code "152") (name "Net-(D63-C)") (class "Default")
      (node (ref "D63") (pin "K") (pinfunction "C_K") (pintype "passive"))
      (node (ref "R105") (pin "2") (pinfunction "2_2") (pintype "passive"))
    )
    (net (code "153") (name "Net-(D64-C)") (class "Default")
      (node (ref "D64") (pin "K") (pinfunction "C_K") (pintype "passive"))
      (node (ref "R107") (pin "2") (pinfunction "2_2") (pintype "passive"))
    )
    (net (code "154") (name "Net-(D65-C)") (class "Default")
      (node (ref "D65") (pin "K") (pinfunction "C_K") (pintype "passive"))
      (node (ref "R109") (pin "2") (pinfunction "2_2") (pintype "passive"))
    )
    (net (code "155") (name "Net-(D66-C)") (class "Default")
      (node (ref "D66") (pin "K") (pinfunction "C_K") (pintype "passive"))
      (node (ref "R110") (pin "2") (pinfunction "2_2") (pintype "passive"))
    )
    (net (code "156") (name "Net-(D67-C)") (class "Default")
      (node (ref "D67") (pin "K") (pinfunction "C_K") (pintype "passive"))
      (node (ref "R112") (pin "2") (pinfunction "2_2") (pintype "passive"))
    )
    (net (code "157") (name "Net-(D68-C)") (class "Default")
      (node (ref "D68") (pin "K") (pinfunction "C_K") (pintype "passive"))
      (node (ref "R114") (pin "2") (pinfunction "2_2") (pintype "passive"))
    )
    (net (code "158") (name "Net-(D69-C)") (class "Default")
      (node (ref "D69") (pin "K") (pinfunction "C_K") (pintype "passive"))
      (node (ref "R115") (pin "2") (pinfunction "2_2") (pintype "passive"))
    )
    (net (code "159") (name "Net-(D70-C)") (class "Default")
      (node (ref "D70") (pin "K") (pinfunction "C_K") (pintype "passive"))
      (node (ref "R117") (pin "2") (pinfunction "2_2") (pintype "passive"))
    )
    (net (code "160") (name "Net-(D71-C)") (class "Default")
      (node (ref "D71") (pin "K") (pinfunction "C_K") (pintype "passive"))
      (node (ref "R119") (pin "2") (pinfunction "2_2") (pintype "passive"))
    )
    (net (code "161") (name "Net-(D72-C)") (class "Default")
      (node (ref "D72") (pin "K") (pinfunction "C_K") (pintype "passive"))
      (node (ref "R120") (pin "2") (pinfunction "2_2") (pintype "passive"))
    )
    (net (code "162") (name "Net-(D73-C)") (class "Default")
      (node (ref "D73") (pin "K") (pinfunction "C_K") (pintype "passive"))
      (node (ref "R122") (pin "2") (pinfunction "2_2") (pintype "passive"))
    )
    (net (code "163") (name "Net-(D74-C)") (class "Default")
      (node (ref "D74") (pin "K") (pinfunction "C_K") (pintype "passive"))
      (node (ref "R124") (pin "2") (pinfunction "2_2") (pintype "passive"))
    )
    (net (code "164") (name "Net-(D75-C)") (class "Default")
      (node (ref "D75") (pin "K") (pinfunction "C_K") (pintype "passive"))
      (node (ref "R125") (pin "2") (pinfunction "2_2") (pintype "passive"))
    )
    (net (code "165") (name "Net-(D76-C)") (class "Default")
      (node (ref "D76") (pin "K") (pinfunction "C_K") (pintype "passive"))
      (node (ref "R127") (pin "2") (pinfunction "2_2") (pintype "passive"))
    )
    (net (code "166") (name "Net-(D77-C)") (class "Default")
      (node (ref "D77") (pin "K") (pinfunction "C_K") (pintype "passive"))
      (node (ref "R129") (pin "2") (pinfunction "2_2") (pintype "passive"))
    )
    (net (code "167") (name "Net-(D78-C)") (class "Default")
      (node (ref "D78") (pin "K") (pinfunction "C_K") (pintype "passive"))
      (node (ref "R130") (pin "2") (pinfunction "2_2") (pintype "passive"))
    )
    (net (code "168") (name "Net-(D79-C)") (class "Default")
      (node (ref "D79") (pin "K") (pinfunction "C_K") (pintype "passive"))
      (node (ref "R132") (pin "2") (pinfunction "2_2") (pintype "passive"))
    )
    (net (code "169") (name "Net-(D80-C)") (class "Default")
      (node (ref "D80") (pin "K") (pinfunction "C_K") (pintype "passive"))
      (node (ref "R134") (pin "2") (pinfunction "2_2") (pintype "passive"))
    )
    (net (code "170") (name "Net-(D81-C)") (class "Default")
      (node (ref "D81") (pin "K") (pinfunction "C_K") (pintype "passive"))
      (node (ref "R135") (pin "2") (pinfunction "2_2") (pintype "passive"))
    )
    (net (code "171") (name "Net-(D82-C)") (class "Default")
      (node (ref "D82") (pin "K") (pinfunction "C_K") (pintype "passive"))
      (node (ref "R137") (pin "2") (pinfunction "2_2") (pintype "passive"))
    )
    (net (code "172") (name "Net-(D83-C)") (class "Default")
      (node (ref "D83") (pin "K") (pinfunction "C_K") (pintype "passive"))
      (node (ref "R139") (pin "2") (pinfunction "2_2") (pintype "passive"))
    )
    (net (code "173") (name "Net-(D84-C)") (class "Default")
      (node (ref "D84") (pin "K") (pinfunction "C_K") (pintype "passive"))
      (node (ref "R140") (pin "2") (pinfunction "2_2") (pintype "passive"))
    )
    (net (code "174") (name "Net-(D85-C)") (class "Default")
      (node (ref "D85") (pin "K") (pinfunction "C_K") (pintype "passive"))
      (node (ref "R142") (pin "2") (pinfunction "2_2") (pintype "passive"))
    )
    (net (code "175") (name "Net-(D86-C)") (class "Default")
      (node (ref "D86") (pin "K") (pinfunction "C_K") (pintype "passive"))
      (node (ref "R144") (pin "2") (pinfunction "2_2") (pintype "passive"))
    )
    (net (code "176") (name "Net-(D87-C)") (class "Default")
      (node (ref "D87") (pin "K") (pinfunction "C_K") (pintype "passive"))
      (node (ref "R145") (pin "2") (pinfunction "2_2") (pintype "passive"))
    )
    (net (code "177") (name "Net-(D88-C)") (class "Default")
      (node (ref "D88") (pin "K") (pinfunction "C_K") (pintype "passive"))
      (node (ref "R147") (pin "2") (pinfunction "2_2") (pintype "passive"))
    )
    (net (code "178") (name "Net-(D89-C)") (class "Default")
      (node (ref "D89") (pin "K") (pinfunction "C_K") (pintype "passive"))
      (node (ref "R149") (pin "2") (pinfunction "2_2") (pintype "passive"))
    )
    (net (code "179") (name "Net-(D90-C)") (class "Default")
      (node (ref "D90") (pin "K") (pinfunction "C_K") (pintype "passive"))
      (node (ref "R150") (pin "2") (pinfunction "2_2") (pintype "passive"))
    )
    (net (code "180") (name "Net-(D91-C)") (class "Default")
      (node (ref "D91") (pin "K") (pinfunction "C_K") (pintype "passive"))
      (node (ref "R152") (pin "2") (pinfunction "2_2") (pintype "passive"))
    )
    (net (code "181") (name "Net-(D92-C)") (class "Default")
      (node (ref "D92") (pin "K") (pinfunction "C_K") (pintype "passive"))
      (node (ref "R154") (pin "2") (pinfunction "2_2") (pintype "passive"))
    )
    (net (code "182") (name "Net-(D93-C)") (class "Default")
      (node (ref "D93") (pin "K") (pinfunction "C_K") (pintype "passive"))
      (node (ref "R155") (pin "2") (pinfunction "2_2") (pintype "passive"))
    )
    (net (code "183") (name "Net-(D94-C)") (class "Default")
      (node (ref "D94") (pin "K") (pinfunction "C_K") (pintype "passive"))
      (node (ref "R157") (pin "2") (pinfunction "2_2") (pintype "passive"))
    )
    (net (code "184") (name "Net-(D95-C)") (class "Default")
      (node (ref "D95") (pin "K") (pinfunction "C_K") (pintype "passive"))
      (node (ref "R159") (pin "2") (pinfunction "2_2") (pintype "passive"))
    )
    (net (code "185") (name "Net-(D96-C)") (class "Default")
      (node (ref "D96") (pin "K") (pinfunction "C_K") (pintype "passive"))
      (node (ref "R160") (pin "2") (pinfunction "2_2") (pintype "passive"))
    )
    (net (code "186") (name "Net-(D97-C)") (class "Default")
      (node (ref "D97") (pin "K") (pinfunction "C_K") (pintype "passive"))
      (node (ref "R162") (pin "2") (pinfunction "2_2") (pintype "passive"))
    )
    (net (code "187") (name "Net-(D98-C)") (class "Default")
      (node (ref "D98") (pin "K") (pinfunction "C_K") (pintype "passive"))
      (node (ref "R164") (pin "2") (pinfunction "2_2") (pintype "passive"))
    )
    (net (code "188") (name "Net-(D99-C)") (class "Default")
      (node (ref "D99") (pin "K") (pinfunction "C_K") (pintype "passive"))
      (node (ref "R165") (pin "2") (pinfunction "2_2") (pintype "passive"))
    )
    (net (code "189") (name "Net-(D100-C)") (class "Default")
      (node (ref "D100") (pin "K") (pinfunction "C_K") (pintype "passive"))
      (node (ref "R167") (pin "2") (pinfunction "2_2") (pintype "passive"))
    )
    (net (code "190") (name "Net-(D101-C)") (class "Default")
      (node (ref "D101") (pin "K") (pinfunction "C_K") (pintype "passive"))
      (node (ref "R169") (pin "2") (pinfunction "2_2") (pintype "passive"))
    )
    (net (code "191") (name "Net-(D102-C)") (class "Default")
      (node (ref "D102") (pin "K") (pinfunction "C_K") (pintype "passive"))
      (node (ref "R170") (pin "2") (pinfunction "2_2") (pintype "passive"))
    )
    (net (code "192") (name "Net-(D103-C)") (class "Default")
      (node (ref "D103") (pin "K") (pinfunction "C_K") (pintype "passive"))
      (node (ref "R172") (pin "2") (pinfunction "2_2") (pintype "passive"))
    )
    (net (code "193") (name "Net-(D104-C)") (class "Default")
      (node (ref "D104") (pin "K") (pinfunction "C_K") (pintype "passive"))
      (node (ref "R174") (pin "2") (pinfunction "2_2") (pintype "passive"))
    )
    (net (code "194") (name "Net-(D105-C)") (class "Default")
      (node (ref "D105") (pin "K") (pinfunction "C_K") (pintype "passive"))
      (node (ref "R175") (pin "2") (pinfunction "2_2") (pintype "passive"))
    )
    (net (code "195") (name "Net-(D106-C)") (class "Default")
      (node (ref "D106") (pin "K") (pinfunction "C_K") (pintype "passive"))
      (node (ref "R177") (pin "2") (pinfunction "2_2") (pintype "passive"))
    )
    (net (code "196") (name "Net-(D107-C)") (class "Default")
      (node (ref "D107") (pin "K") (pinfunction "C_K") (pintype "passive"))
      (node (ref "R179") (pin "2") (pinfunction "2_2") (pintype "passive"))
    )
    (net (code "197") (name "Net-(D108-C)") (class "Default")
      (node (ref "D108") (pin "K") (pinfunction "C_K") (pintype "passive"))
      (node (ref "R180") (pin "2") (pinfunction "2_2") (pintype "passive"))
    )
    (net (code "198") (name "Net-(D109-C)") (class "Default")
      (node (ref "D109") (pin "K") (pinfunction "C_K") (pintype "passive"))
      (node (ref "R182") (pin "2") (pinfunction "2_2") (pintype "passive"))
    )
    (net (code "199") (name "Net-(D110-C)") (class "Default")
      (node (ref "D110") (pin "K") (pinfunction "C_K") (pintype "passive"))
      (node (ref "R184") (pin "2") (pinfunction "2_2") (pintype "passive"))
    )
    (net (code "200") (name "Net-(D111-C)") (class "Default")
      (node (ref "D111") (pin "K") (pinfunction "C_K") (pintype "passive"))
      (node (ref "R185") (pin "2") (pinfunction "2_2") (pintype "passive"))
    )
    (net (code "201") (name "Net-(D112-C)") (class "Default")
      (node (ref "D112") (pin "K") (pinfunction "C_K") (pintype "passive"))
      (node (ref "R187") (pin "2") (pinfunction "2_2") (pintype "passive"))
    )
    (net (code "202") (name "Net-(D113-C)") (class "Default")
      (node (ref "D113") (pin "K") (pinfunction "C_K") (pintype "passive"))
      (node (ref "R189") (pin "2") (pinfunction "2_2") (pintype "passive"))
    )
    (net (code "203") (name "Net-(D114-C)") (class "Default")
      (node (ref "D114") (pin "K") (pinfunction "C_K") (pintype "passive"))
      (node (ref "R190") (pin "2") (pinfunction "2_2") (pintype "passive"))
    )
    (net (code "204") (name "Net-(D115-C)") (class "Default")
      (node (ref "D115") (pin "K") (pinfunction "C_K") (pintype "passive"))
      (node (ref "R192") (pin "2") (pinfunction "2_2") (pintype "passive"))
    )
    (net (code "205") (name "Net-(D116-C)") (class "Default")
      (node (ref "D116") (pin "K") (pinfunction "C_K") (pintype "passive"))
      (node (ref "R194") (pin "2") (pinfunction "2_2") (pintype "passive"))
    )
    (net (code "206") (name "Net-(D117-C)") (class "Default")
      (node (ref "D117") (pin "K") (pinfunction "C_K") (pintype "passive"))
      (node (ref "R195") (pin "2") (pinfunction "2_2") (pintype "passive"))
    )
    (net (code "207") (name "Net-(D118-C)") (class "Default")
      (node (ref "D118") (pin "K") (pinfunction "C_K") (pintype "passive"))
      (node (ref "R197") (pin "2") (pinfunction "2_2") (pintype "passive"))
    )
    (net (code "208") (name "Net-(D119-C)") (class "Default")
      (node (ref "D119") (pin "K") (pinfunction "C_K") (pintype "passive"))
      (node (ref "R199") (pin "2") (pinfunction "2_2") (pintype "passive"))
    )
    (net (code "209") (name "Net-(D120-C)") (class "Default")
      (node (ref "D120") (pin "K") (pinfunction "C_K") (pintype "passive"))
      (node (ref "R200") (pin "2") (pinfunction "2_2") (pintype "passive"))
    )
    (net (code "210") (name "Net-(D121-C)") (class "Default")
      (node (ref "D121") (pin "K") (pinfunction "C_K") (pintype "passive"))
      (node (ref "R202") (pin "2") (pinfunction "2_2") (pintype "passive"))
    )
    (net (code "211") (name "Net-(D122-C)") (class "Default")
      (node (ref "D122") (pin "K") (pinfunction "C_K") (pintype "passive"))
      (node (ref "R204") (pin "2") (pinfunction "2_2") (pintype "passive"))
    )
    (net (code "212") (name "Net-(D123-C)") (class "Default")
      (node (ref "D123") (pin "K") (pinfunction "C_K") (pintype "passive"))
      (node (ref "R205") (pin "2") (pinfunction "2_2") (pintype "passive"))
    )
    (net (code "213") (name "Net-(D124-C)") (class "Default")
      (node (ref "D124") (pin "K") (pinfunction "C_K") (pintype "passive"))
      (node (ref "R207") (pin "2") (pinfunction "2_2") (pintype "passive"))
    )
    (net (code "214") (name "Net-(D125-C)") (class "Default")
      (node (ref "D125") (pin "K") (pinfunction "C_K") (pintype "passive"))
      (node (ref "R209") (pin "2") (pinfunction "2_2") (pintype "passive"))
    )
    (net (code "215") (name "Net-(D126-C)") (class "Default")
      (node (ref "D126") (pin "K") (pinfunction "C_K") (pintype "passive"))
      (node (ref "R210") (pin "2") (pinfunction "2_2") (pintype "passive"))
    )
    (net (code "216") (name "Net-(D127-C)") (class "Default")
      (node (ref "D127") (pin "K") (pinfunction "C_K") (pintype "passive"))
      (node (ref "R212") (pin "2") (pinfunction "2_2") (pintype "passive"))
    )
    (net (code "217") (name "Net-(D128-C)") (class "Default")
      (node (ref "D128") (pin "K") (pinfunction "C_K") (pintype "passive"))
      (node (ref "R214") (pin "2") (pinfunction "2_2") (pintype "passive"))
    )
    (net (code "218") (name "Net-(D129-C)") (class "Default")
      (node (ref "D129") (pin "K") (pinfunction "C_K") (pintype "passive"))
      (node (ref "R215") (pin "2") (pinfunction "2_2") (pintype "passive"))
    )
    (net (code "219") (name "Net-(D130-C)") (class "Default")
      (node (ref "D130") (pin "K") (pinfunction "C_K") (pintype "passive"))
      (node (ref "R217") (pin "2") (pinfunction "2_2") (pintype "passive"))
    )
    (net (code "220") (name "Net-(D131-C)") (class "Default")
      (node (ref "D131") (pin "K") (pinfunction "C_K") (pintype "passive"))
      (node (ref "R219") (pin "2") (pinfunction "2_2") (pintype "passive"))
    )
    (net (code "221") (name "Net-(D132-C)") (class "Default")
      (node (ref "D132") (pin "K") (pinfunction "C_K") (pintype "passive"))
      (node (ref "R220") (pin "2") (pinfunction "2_2") (pintype "passive"))
    )
    (net (code "222") (name "Net-(D133-C)") (class "Default")
      (node (ref "D133") (pin "K") (pinfunction "C_K") (pintype "passive"))
      (node (ref "R222") (pin "2") (pinfunction "2_2") (pintype "passive"))
    )
    (net (code "223") (name "Net-(D134-C)") (class "Default")
      (node (ref "D134") (pin "K") (pinfunction "C_K") (pintype "passive"))
      (node (ref "R224") (pin "2") (pinfunction "2_2") (pintype "passive"))
    )
    (net (code "224") (name "Net-(D135-C)") (class "Default")
      (node (ref "D135") (pin "K") (pinfunction "C_K") (pintype "passive"))
      (node (ref "R225") (pin "2") (pinfunction "2_2") (pintype "passive"))
    )
    (net (code "225") (name "Net-(D136-C)") (class "Default")
      (node (ref "D136") (pin "K") (pinfunction "C_K") (pintype "passive"))
      (node (ref "R227") (pin "2") (pinfunction "2_2") (pintype "passive"))
    )
    (net (code "226") (name "Net-(D137-C)") (class "Default")
      (node (ref "D137") (pin "K") (pinfunction "C_K") (pintype "passive"))
      (node (ref "R229") (pin "2") (pinfunction "2_2") (pintype "passive"))
    )
    (net (code "227") (name "Net-(D138-C)") (class "Default")
      (node (ref "D138") (pin "K") (pinfunction "C_K") (pintype "passive"))
      (node (ref "R230") (pin "2") (pinfunction "2_2") (pintype "passive"))
    )
    (net (code "228") (name "Net-(D139-C)") (class "Default")
      (node (ref "D139") (pin "K") (pinfunction "C_K") (pintype "passive"))
      (node (ref "R232") (pin "2") (pinfunction "2_2") (pintype "passive"))
    )
    (net (code "229") (name "Net-(D140-C)") (class "Default")
      (node (ref "D140") (pin "K") (pinfunction "C_K") (pintype "passive"))
      (node (ref "R234") (pin "2") (pinfunction "2_2") (pintype "passive"))
    )
    (net (code "230") (name "Net-(D141-C)") (class "Default")
      (node (ref "D141") (pin "K") (pinfunction "C_K") (pintype "passive"))
      (node (ref "R235") (pin "2") (pinfunction "2_2") (pintype "passive"))
    )
    (net (code "231") (name "Net-(D142-C)") (class "Default")
      (node (ref "D142") (pin "K") (pinfunction "C_K") (pintype "passive"))
      (node (ref "R237") (pin "2") (pinfunction "2_2") (pintype "passive"))
    )
    (net (code "232") (name "Net-(D143-C)") (class "Default")
      (node (ref "D143") (pin "K") (pinfunction "C_K") (pintype "passive"))
      (node (ref "R239") (pin "2") (pinfunction "2_2") (pintype "passive"))
    )
    (net (code "233") (name "Net-(D144-C)") (class "Default")
      (node (ref "D144") (pin "K") (pinfunction "C_K") (pintype "passive"))
      (node (ref "R240") (pin "2") (pinfunction "2_2") (pintype "passive"))
    )
    (net (code "234") (name "Net-(D145-C)") (class "Default")
      (node (ref "D145") (pin "K") (pinfunction "C_K") (pintype "passive"))
      (node (ref "R259") (pin "2") (pinfunction "2_2") (pintype "passive"))
    )
    (net (code "235") (name "Net-(D146-C)") (class "Default")
      (node (ref "D146") (pin "K") (pinfunction "C_K") (pintype "passive"))
      (node (ref "R260") (pin "2") (pinfunction "2_2") (pintype "passive"))
    )
    (net (code "236") (name "Net-(D147-C)") (class "Default")
      (node (ref "D147") (pin "K") (pinfunction "C_K") (pintype "passive"))
      (node (ref "R261") (pin "2") (pinfunction "2_2") (pintype "passive"))
    )
    (net (code "237") (name "Net-(D148-C)") (class "Default")
      (node (ref "D148") (pin "K") (pinfunction "C_K") (pintype "passive"))
      (node (ref "R262") (pin "2") (pinfunction "2_2") (pintype "passive"))
    )
    (net (code "238") (name "Net-(D149-C)") (class "Default")
      (node (ref "D149") (pin "K") (pinfunction "C_K") (pintype "passive"))
      (node (ref "R263") (pin "2") (pinfunction "2_2") (pintype "passive"))
    )
    (net (code "239") (name "Net-(D150-C)") (class "Default")
      (node (ref "D150") (pin "K") (pinfunction "C_K") (pintype "passive"))
      (node (ref "R264") (pin "2") (pinfunction "2_2") (pintype "passive"))
    )
    (net (code "240") (name "Net-(D151-C)") (class "Default")
      (node (ref "D151") (pin "K") (pinfunction "C_K") (pintype "passive"))
      (node (ref "R265") (pin "2") (pinfunction "2_2") (pintype "passive"))
    )
    (net (code "241") (name "Net-(D152-C)") (class "Default")
      (node (ref "D152") (pin "K") (pinfunction "C_K") (pintype "passive"))
      (node (ref "R266") (pin "2") (pinfunction "2_2") (pintype "passive"))
    )
    (net (code "242") (name "Net-(D153-C)") (class "Default")
      (node (ref "D153") (pin "K") (pinfunction "C_K") (pintype "passive"))
      (node (ref "R267") (pin "2") (pinfunction "2_2") (pintype "passive"))
    )
    (net (code "243") (name "Net-(D154-C)") (class "Default")
      (node (ref "D154") (pin "K") (pinfunction "C_K") (pintype "passive"))
      (node (ref "R258") (pin "2") (pinfunction "2_2") (pintype "passive"))
    )
    (net (code "244") (name "Net-(D155-C)") (class "Default")
      (node (ref "D155") (pin "K") (pinfunction "C_K") (pintype "passive"))
      (node (ref "R269") (pin "2") (pinfunction "2_2") (pintype "passive"))
    )
    (net (code "245") (name "Net-(D156-C)") (class "Default")
      (node (ref "D156") (pin "K") (pinfunction "C_K") (pintype "passive"))
      (node (ref "R270") (pin "2") (pinfunction "2_2") (pintype "passive"))
    )
    (net (code "246") (name "Net-(D157-C)") (class "Default")
      (node (ref "D157") (pin "K") (pinfunction "C_K") (pintype "passive"))
      (node (ref "R271") (pin "2") (pinfunction "2_2") (pintype "passive"))
    )
    (net (code "247") (name "Net-(D158-C)") (class "Default")
      (node (ref "D158") (pin "K") (pinfunction "C_K") (pintype "passive"))
      (node (ref "R272") (pin "2") (pinfunction "2_2") (pintype "passive"))
    )
    (net (code "248") (name "Net-(D159-C)") (class "Default")
      (node (ref "D159") (pin "K") (pinfunction "C_K") (pintype "passive"))
      (node (ref "R273") (pin "2") (pinfunction "2_2") (pintype "passive"))
    )
    (net (code "249") (name "Net-(D160-C)") (class "Default")
      (node (ref "D160") (pin "K") (pinfunction "C_K") (pintype "passive"))
      (node (ref "R274") (pin "2") (pinfunction "2_2") (pintype "passive"))
    )
    (net (code "250") (name "Net-(D161-C)") (class "Default")
      (node (ref "D161") (pin "K") (pinfunction "C_K") (pintype "passive"))
      (node (ref "R275") (pin "2") (pinfunction "2_2") (pintype "passive"))
    )
    (net (code "251") (name "Net-(D163-C)") (class "Default")
      (node (ref "D163") (pin "K") (pinfunction "C_K") (pintype "passive"))
      (node (ref "R277") (pin "2") (pinfunction "2_2") (pintype "passive"))
    )
    (net (code "252") (name "Net-(D164-C)") (class "Default")
      (node (ref "D164") (pin "K") (pinfunction "C_K") (pintype "passive"))
      (node (ref "R278") (pin "2") (pinfunction "2_2") (pintype "passive"))
    )
    (net (code "253") (name "Net-(D165-C)") (class "Default")
      (node (ref "D165") (pin "K") (pinfunction "C_K") (pintype "passive"))
      (node (ref "R279") (pin "2") (pinfunction "2_2") (pintype "passive"))
    )
    (net (code "254") (name "Net-(D166-C)") (class "Default")
      (node (ref "D166") (pin "K") (pinfunction "C_K") (pintype "passive"))
      (node (ref "R280") (pin "2") (pinfunction "2_2") (pintype "passive"))
    )
    (net (code "255") (name "Net-(D167-C)") (class "Default")
      (node (ref "D167") (pin "K") (pinfunction "C_K") (pintype "passive"))
      (node (ref "R281") (pin "2") (pinfunction "2_2") (pintype "passive"))
    )
    (net (code "256") (name "Net-(D168-C)") (class "Default")
      (node (ref "D168") (pin "K") (pinfunction "C_K") (pintype "passive"))
      (node (ref "R282") (pin "2") (pinfunction "2_2") (pintype "passive"))
    )
    (net (code "257") (name "Net-(D169-C)") (class "Default")
      (node (ref "D169") (pin "K") (pinfunction "C_K") (pintype "passive"))
      (node (ref "R283") (pin "2") (pinfunction "2_2") (pintype "passive"))
    )
    (net (code "258") (name "Net-(D170-C)") (class "Default")
      (node (ref "D170") (pin "K") (pinfunction "C_K") (pintype "passive"))
      (node (ref "R284") (pin "2") (pinfunction "2_2") (pintype "passive"))
    )
    (net (code "259") (name "Net-(D171-C)") (class "Default")
      (node (ref "D171") (pin "K") (pinfunction "C_K") (pintype "passive"))
      (node (ref "R288") (pin "2") (pinfunction "2_2") (pintype "passive"))
    )
    (net (code "260") (name "Net-(D172-C)") (class "Default")
      (node (ref "D172") (pin "K") (pinfunction "C_K") (pintype "passive"))
      (node (ref "R286") (pin "2") (pinfunction "2_2") (pintype "passive"))
    )
    (net (code "261") (name "Net-(Q1-PadS)") (class "Default")
      (node (ref "Q1") (pin "S") (pinfunction "S_S") (pintype "passive"))
      (node (ref "Q2") (pin "D") (pinfunction "D_D") (pintype "passive"))
    )
    (net (code "262") (name "Net-(Q3-PadS)") (class "Default")
      (node (ref "Q3") (pin "S") (pinfunction "S_S") (pintype "passive"))
      (node (ref "Q4") (pin "D") (pinfunction "D_D") (pintype "passive"))
    )
    (net (code "263") (name "Net-(Q6-PadS)") (class "Default")
      (node (ref "Q6") (pin "S") (pinfunction "S_S") (pintype "passive"))
      (node (ref "Q7") (pin "D") (pinfunction "D_D") (pintype "passive"))
    )
    (net (code "264") (name "Net-(Q8-PadS)") (class "Default")
      (node (ref "Q8") (pin "S") (pinfunction "S_S") (pintype "passive"))
      (node (ref "Q9") (pin "D") (pinfunction "D_D") (pintype "passive"))
    )
    (net (code "265") (name "Net-(Q11-PadS)") (class "Default")
      (node (ref "Q11") (pin "S") (pinfunction "S_S") (pintype "passive"))
      (node (ref "Q60") (pin "D") (pinfunction "D_D") (pintype "passive"))
    )
    (net (code "266") (name "Net-(Q12-PadS)") (class "Default")
      (node (ref "Q12") (pin "S") (pinfunction "S_S") (pintype "passive"))
      (node (ref "Q13") (pin "D") (pinfunction "D_D") (pintype "passive"))
    )
    (net (code "267") (name "Net-(Q14-PadS)") (class "Default")
      (node (ref "Q14") (pin "S") (pinfunction "S_S") (pintype "passive"))
      (node (ref "Q15") (pin "D") (pinfunction "D_D") (pintype "passive"))
    )
    (net (code "268") (name "Net-(Q17-PadS)") (class "Default")
      (node (ref "Q17") (pin "S") (pinfunction "S_S") (pintype "passive"))
      (node (ref "Q18") (pin "D") (pinfunction "D_D") (pintype "passive"))
    )
    (net (code "269") (name "Net-(Q19-PadS)") (class "Default")
      (node (ref "Q19") (pin "S") (pinfunction "S_S") (pintype "passive"))
      (node (ref "Q20") (pin "D") (pinfunction "D_D") (pintype "passive"))
    )
    (net (code "270") (name "Net-(Q22-PadS)") (class "Default")
      (node (ref "Q22") (pin "S") (pinfunction "S_S") (pintype "passive"))
      (node (ref "Q23") (pin "D") (pinfunction "D_D") (pintype "passive"))
    )
    (net (code "271") (name "Net-(Q24-PadS)") (class "Default")
      (node (ref "Q24") (pin "S") (pinfunction "S_S") (pintype "passive"))
      (node (ref "Q25") (pin "D") (pinfunction "D_D") (pintype "passive"))
    )
    (net (code "272") (name "Net-(Q27-PadS)") (class "Default")
      (node (ref "Q27") (pin "S") (pinfunction "S_S") (pintype "passive"))
      (node (ref "Q28") (pin "D") (pinfunction "D_D") (pintype "passive"))
    )
    (net (code "273") (name "Net-(Q29-PadS)") (class "Default")
      (node (ref "Q29") (pin "S") (pinfunction "S_S") (pintype "passive"))
      (node (ref "Q30") (pin "D") (pinfunction "D_D") (pintype "passive"))
    )
    (net (code "274") (name "Net-(Q32-PadS)") (class "Default")
      (node (ref "Q32") (pin "S") (pinfunction "S_S") (pintype "passive"))
      (node (ref "Q33") (pin "D") (pinfunction "D_D") (pintype "passive"))
    )
    (net (code "275") (name "Net-(Q34-PadS)") (class "Default")
      (node (ref "Q34") (pin "S") (pinfunction "S_S") (pintype "passive"))
      (node (ref "Q35") (pin "D") (pinfunction "D_D") (pintype "passive"))
    )
    (net (code "276") (name "Net-(Q37-PadS)") (class "Default")
      (node (ref "Q37") (pin "S") (pinfunction "S_S") (pintype "passive"))
      (node (ref "Q38") (pin "D") (pinfunction "D_D") (pintype "passive"))
    )
    (net (code "277") (name "Net-(Q39-PadS)") (class "Default")
      (node (ref "Q39") (pin "S") (pinfunction "S_S") (pintype "passive"))
      (node (ref "Q40") (pin "D") (pinfunction "D_D") (pintype "passive"))
    )
    (net (code "278") (name "Net-(Q42-PadD)") (class "Default")
      (node (ref "Q42") (pin "D") (pinfunction "D_D") (pintype "passive"))
      (node (ref "Q44") (pin "G") (pinfunction "G_G") (pintype "passive"))
      (node (ref "R46") (pin "1") (pinfunction "1_1") (pintype "passive"))
      (node (ref "R47") (pin "1") (pinfunction "1_1") (pintype "passive"))
      (node (ref "R54") (pin "1") (pinfunction "1_1") (pintype "passive"))
    )
    (net (code "279") (name "Net-(Q42-PadS)") (class "Default")
      (node (ref "Q42") (pin "S") (pinfunction "S_S") (pintype "passive"))
      (node (ref "Q43") (pin "D") (pinfunction "D_D") (pintype "passive"))
    )
    (net (code "280") (name "Net-(Q44-PadD)") (class "Default")
      (node (ref "Q44") (pin "D") (pinfunction "D_D") (pintype "passive"))
      (node (ref "Q45") (pin "G") (pinfunction "G_G") (pintype "passive"))
      (node (ref "R48") (pin "1") (pinfunction "1_1") (pintype "passive"))
    )
    (net (code "281") (name "Net-(Q46-PadG)") (class "Default")
      (node (ref "Q46") (pin "G") (pinfunction "G_G") (pintype "passive"))
      (node (ref "Q59") (pin "D") (pinfunction "D_D") (pintype "passive"))
      (node (ref "R73") (pin "1") (pinfunction "1_1") (pintype "passive"))
    )
    (net (code "282") (name "Net-(Q48-PadD)") (class "Default")
      (node (ref "Q48") (pin "D") (pinfunction "D_D") (pintype "passive"))
      (node (ref "Q50") (pin "G") (pinfunction "G_G") (pintype "passive"))
      (node (ref "R56") (pin "1") (pinfunction "1_1") (pintype "passive"))
      (node (ref "R57") (pin "1") (pinfunction "1_1") (pintype "passive"))
      (node (ref "R64") (pin "1") (pinfunction "1_1") (pintype "passive"))
    )
    (net (code "283") (name "Net-(Q48-PadS)") (class "Default")
      (node (ref "Q48") (pin "S") (pinfunction "S_S") (pintype "passive"))
      (node (ref "Q49") (pin "D") (pinfunction "D_D") (pintype "passive"))
    )
    (net (code "284") (name "Net-(Q50-PadD)") (class "Default")
      (node (ref "Q50") (pin "D") (pinfunction "D_D") (pintype "passive"))
      (node (ref "Q51") (pin "G") (pinfunction "G_G") (pintype "passive"))
      (node (ref "R58") (pin "1") (pinfunction "1_1") (pintype "passive"))
    )
    (net (code "285") (name "Net-(Q52-PadG)") (class "Default")
      (node (ref "Q52") (pin "G") (pinfunction "G_G") (pintype "passive"))
      (node (ref "Q56") (pin "D") (pinfunction "D_D") (pintype "passive"))
      (node (ref "R68") (pin "1") (pinfunction "1_1") (pintype "passive"))
    )
    (net (code "286") (name "Net-(Q54-PadD)") (class "Default")
      (node (ref "Q54") (pin "D") (pinfunction "D_D") (pintype "passive"))
      (node (ref "Q56") (pin "G") (pinfunction "G_G") (pintype "passive"))
      (node (ref "R65") (pin "1") (pinfunction "1_1") (pintype "passive"))
      (node (ref "R66") (pin "1") (pinfunction "1_1") (pintype "passive"))
      (node (ref "R67") (pin "1") (pinfunction "1_1") (pintype "passive"))
    )
    (net (code "287") (name "Net-(Q54-PadS)") (class "Default")
      (node (ref "Q54") (pin "S") (pinfunction "S_S") (pintype "passive"))
      (node (ref "Q55") (pin "D") (pinfunction "D_D") (pintype "passive"))
    )
    (net (code "288") (name "Net-(Q57-PadD)") (class "Default")
      (node (ref "Q57") (pin "D") (pinfunction "D_D") (pintype "passive"))
      (node (ref "Q59") (pin "G") (pinfunction "G_G") (pintype "passive"))
      (node (ref "R55") (pin "1") (pinfunction "1_1") (pintype "passive"))
      (node (ref "R71") (pin "1") (pinfunction "1_1") (pintype "passive"))
      (node (ref "R72") (pin "1") (pinfunction "1_1") (pintype "passive"))
    )
    (net (code "289") (name "Net-(Q57-PadS)") (class "Default")
      (node (ref "Q57") (pin "S") (pinfunction "S_S") (pintype "passive"))
      (node (ref "Q58") (pin "D") (pinfunction "D_D") (pintype "passive"))
    )
    (net (code "290") (name "Net-(Q61-PadS)") (class "Default")
      (node (ref "Q61") (pin "S") (pinfunction "S_S") (pintype "passive"))
      (node (ref "Q62") (pin "D") (pinfunction "D_D") (pintype "passive"))
    )
    (net (code "291") (name "Net-(Q64-PadS)") (class "Default")
      (node (ref "Q64") (pin "S") (pinfunction "S_S") (pintype "passive"))
      (node (ref "Q65") (pin "D") (pinfunction "D_D") (pintype "passive"))
    )
    (net (code "292") (name "Net-(Q66-PadS)") (class "Default")
      (node (ref "Q66") (pin "S") (pinfunction "S_S") (pintype "passive"))
      (node (ref "Q67") (pin "D") (pinfunction "D_D") (pintype "passive"))
    )
    (net (code "293") (name "Net-(Q69-PadS)") (class "Default")
      (node (ref "Q69") (pin "S") (pinfunction "S_S") (pintype "passive"))
      (node (ref "Q70") (pin "D") (pinfunction "D_D") (pintype "passive"))
    )
    (net (code "294") (name "Net-(Q71-PadS)") (class "Default")
      (node (ref "Q71") (pin "S") (pinfunction "S_S") (pintype "passive"))
      (node (ref "Q72") (pin "D") (pinfunction "D_D") (pintype "passive"))
    )
    (net (code "295") (name "Net-(Q74-PadS)") (class "Default")
      (node (ref "Q74") (pin "S") (pinfunction "S_S") (pintype "passive"))
      (node (ref "Q75") (pin "D") (pinfunction "D_D") (pintype "passive"))
    )
    (net (code "296") (name "Net-(Q76-PadS)") (class "Default")
      (node (ref "Q76") (pin "S") (pinfunction "S_S") (pintype "passive"))
      (node (ref "Q77") (pin "D") (pinfunction "D_D") (pintype "passive"))
    )
    (net (code "297") (name "Net-(Q79-PadS)") (class "Default")
      (node (ref "Q79") (pin "S") (pinfunction "S_S") (pintype "passive"))
      (node (ref "Q80") (pin "D") (pinfunction "D_D") (pintype "passive"))
    )
    (net (code "298") (name "Net-(Q81-PadS)") (class "Default")
      (node (ref "Q81") (pin "S") (pinfunction "S_S") (pintype "passive"))
      (node (ref "Q82") (pin "D") (pinfunction "D_D") (pintype "passive"))
    )
    (net (code "299") (name "Net-(Q84-PadS)") (class "Default")
      (node (ref "Q84") (pin "S") (pinfunction "S_S") (pintype "passive"))
      (node (ref "Q85") (pin "D") (pinfunction "D_D") (pintype "passive"))
    )
    (net (code "300") (name "Net-(Q86-PadS)") (class "Default")
      (node (ref "Q86") (pin "S") (pinfunction "S_S") (pintype "passive"))
      (node (ref "Q87") (pin "D") (pinfunction "D_D") (pintype "passive"))
    )
    (net (code "301") (name "Net-(Q89-PadS)") (class "Default")
      (node (ref "Q89") (pin "S") (pinfunction "S_S") (pintype "passive"))
      (node (ref "Q90") (pin "D") (pinfunction "D_D") (pintype "passive"))
    )
    (net (code "302") (name "Net-(Q91-PadS)") (class "Default")
      (node (ref "Q91") (pin "S") (pinfunction "S_S") (pintype "passive"))
      (node (ref "Q92") (pin "D") (pinfunction "D_D") (pintype "passive"))
    )
    (net (code "303") (name "Net-(Q94-PadS)") (class "Default")
      (node (ref "Q94") (pin "S") (pinfunction "S_S") (pintype "passive"))
      (node (ref "Q95") (pin "D") (pinfunction "D_D") (pintype "passive"))
    )
    (net (code "304") (name "Net-(Q96-PadS)") (class "Default")
      (node (ref "Q96") (pin "S") (pinfunction "S_S") (pintype "passive"))
      (node (ref "Q97") (pin "D") (pinfunction "D_D") (pintype "passive"))
    )
    (net (code "305") (name "Net-(Q100-PadD)") (class "Default")
      (node (ref "Q100") (pin "D") (pinfunction "D_D") (pintype "passive"))
      (node (ref "Q99") (pin "S") (pinfunction "S_S") (pintype "passive"))
    )
    (net (code "306") (name "Net-(Q101-PadS)") (class "Default")
      (node (ref "Q101") (pin "S") (pinfunction "S_S") (pintype "passive"))
      (node (ref "Q102") (pin "D") (pinfunction "D_D") (pintype "passive"))
    )
    (net (code "307") (name "Net-(Q104-PadS)") (class "Default")
      (node (ref "Q104") (pin "S") (pinfunction "S_S") (pintype "passive"))
      (node (ref "Q105") (pin "D") (pinfunction "D_D") (pintype "passive"))
    )
    (net (code "308") (name "Net-(Q106-PadS)") (class "Default")
      (node (ref "Q106") (pin "S") (pinfunction "S_S") (pintype "passive"))
      (node (ref "Q107") (pin "D") (pinfunction "D_D") (pintype "passive"))
    )
    (net (code "309") (name "Net-(Q109-PadS)") (class "Default")
      (node (ref "Q109") (pin "S") (pinfunction "S_S") (pintype "passive"))
      (node (ref "Q110") (pin "D") (pinfunction "D_D") (pintype "passive"))
    )
    (net (code "310") (name "Net-(Q111-PadS)") (class "Default")
      (node (ref "Q111") (pin "S") (pinfunction "S_S") (pintype "passive"))
      (node (ref "Q112") (pin "D") (pinfunction "D_D") (pintype "passive"))
    )
    (net (code "311") (name "Net-(Q114-PadS)") (class "Default")
      (node (ref "Q114") (pin "S") (pinfunction "S_S") (pintype "passive"))
      (node (ref "Q115") (pin "D") (pinfunction "D_D") (pintype "passive"))
    )
    (net (code "312") (name "Net-(Q116-PadS)") (class "Default")
      (node (ref "Q116") (pin "S") (pinfunction "S_S") (pintype "passive"))
      (node (ref "Q117") (pin "D") (pinfunction "D_D") (pintype "passive"))
    )
    (net (code "313") (name "Net-(Q119-PadS)") (class "Default")
      (node (ref "Q119") (pin "S") (pinfunction "S_S") (pintype "passive"))
      (node (ref "Q120") (pin "D") (pinfunction "D_D") (pintype "passive"))
    )
    (net (code "314") (name "Net-(Q121-PadS)") (class "Default")
      (node (ref "Q121") (pin "S") (pinfunction "S_S") (pintype "passive"))
      (node (ref "Q122") (pin "D") (pinfunction "D_D") (pintype "passive"))
    )
    (net (code "315") (name "Net-(Q124-PadS)") (class "Default")
      (node (ref "Q124") (pin "S") (pinfunction "S_S") (pintype "passive"))
      (node (ref "Q125") (pin "D") (pinfunction "D_D") (pintype "passive"))
    )
    (net (code "316") (name "Net-(Q126-PadS)") (class "Default")
      (node (ref "Q126") (pin "S") (pinfunction "S_S") (pintype "passive"))
      (node (ref "Q127") (pin "D") (pinfunction "D_D") (pintype "passive"))
    )
    (net (code "317") (name "Net-(Q129-PadS)") (class "Default")
      (node (ref "Q129") (pin "S") (pinfunction "S_S") (pintype "passive"))
      (node (ref "Q130") (pin "D") (pinfunction "D_D") (pintype "passive"))
    )
    (net (code "318") (name "Net-(Q131-PadS)") (class "Default")
      (node (ref "Q131") (pin "S") (pinfunction "S_S") (pintype "passive"))
      (node (ref "Q132") (pin "D") (pinfunction "D_D") (pintype "passive"))
    )
    (net (code "319") (name "Net-(Q134-PadS)") (class "Default")
      (node (ref "Q134") (pin "S") (pinfunction "S_S") (pintype "passive"))
      (node (ref "Q135") (pin "D") (pinfunction "D_D") (pintype "passive"))
    )
    (net (code "320") (name "Net-(Q136-PadS)") (class "Default")
      (node (ref "Q136") (pin "S") (pinfunction "S_S") (pintype "passive"))
      (node (ref "Q137") (pin "D") (pinfunction "D_D") (pintype "passive"))
    )
    (net (code "321") (name "Net-(Q139-PadD)") (class "Default")
      (node (ref "Q139") (pin "D") (pinfunction "D_D") (pintype "passive"))
      (node (ref "Q141") (pin "G") (pinfunction "G_G") (pintype "passive"))
      (node (ref "R151") (pin "1") (pinfunction "1_1") (pintype "passive"))
      (node (ref "R152") (pin "1") (pinfunction "1_1") (pintype "passive"))
      (node (ref "R159") (pin "1") (pinfunction "1_1") (pintype "passive"))
    )
    (net (code "322") (name "Net-(Q139-PadS)") (class "Default")
      (node (ref "Q139") (pin "S") (pinfunction "S_S") (pintype "passive"))
      (node (ref "Q140") (pin "D") (pinfunction "D_D") (pintype "passive"))
    )
    (net (code "323") (name "Net-(Q141-PadD)") (class "Default")
      (node (ref "Q141") (pin "D") (pinfunction "D_D") (pintype "passive"))
      (node (ref "Q142") (pin "G") (pinfunction "G_G") (pintype "passive"))
      (node (ref "R153") (pin "1") (pinfunction "1_1") (pintype "passive"))
    )
    (net (code "324") (name "Net-(Q143-PadG)") (class "Default")
      (node (ref "Q143") (pin "G") (pinfunction "G_G") (pintype "passive"))
      (node (ref "Q147") (pin "D") (pinfunction "D_D") (pintype "passive"))
      (node (ref "R163") (pin "1") (pinfunction "1_1") (pintype "passive"))
    )
    (net (code "325") (name "Net-(Q145-PadD)") (class "Default")
      (node (ref "Q145") (pin "D") (pinfunction "D_D") (pintype "passive"))
      (node (ref "Q147") (pin "G") (pinfunction "G_G") (pintype "passive"))
      (node (ref "R160") (pin "1") (pinfunction "1_1") (pintype "passive"))
      (node (ref "R161") (pin "1") (pinfunction "1_1") (pintype "passive"))
      (node (ref "R162") (pin "1") (pinfunction "1_1") (pintype "passive"))
    )
    (net (code "326") (name "Net-(Q145-PadS)") (class "Default")
      (node (ref "Q145") (pin "S") (pinfunction "S_S") (pintype "passive"))
      (node (ref "Q146") (pin "D") (pinfunction "D_D") (pintype "passive"))
    )
    (net (code "327") (name "Net-(Q148-PadD)") (class "Default")
      (node (ref "Q148") (pin "D") (pinfunction "D_D") (pintype "passive"))
      (node (ref "Q150") (pin "G") (pinfunction "G_G") (pintype "passive"))
      (node (ref "R166") (pin "1") (pinfunction "1_1") (pintype "passive"))
      (node (ref "R167") (pin "1") (pinfunction "1_1") (pintype "passive"))
      (node (ref "R174") (pin "1") (pinfunction "1_1") (pintype "passive"))
    )
    (net (code "328") (name "Net-(Q148-PadS)") (class "Default")
      (node (ref "Q148") (pin "S") (pinfunction "S_S") (pintype "passive"))
      (node (ref "Q149") (pin "D") (pinfunction "D_D") (pintype "passive"))
    )
    (net (code "329") (name "Net-(Q150-PadD)") (class "Default")
      (node (ref "Q150") (pin "D") (pinfunction "D_D") (pintype "passive"))
      (node (ref "Q151") (pin "G") (pinfunction "G_G") (pintype "passive"))
      (node (ref "R168") (pin "1") (pinfunction "1_1") (pintype "passive"))
    )
    (net (code "330") (name "Net-(Q152-PadG)") (class "Default")
      (node (ref "Q152") (pin "G") (pinfunction "G_G") (pintype "passive"))
      (node (ref "Q156") (pin "D") (pinfunction "D_D") (pintype "passive"))
      (node (ref "R178") (pin "1") (pinfunction "1_1") (pintype "passive"))
    )
    (net (code "331") (name "Net-(Q154-PadD)") (class "Default")
      (node (ref "Q154") (pin "D") (pinfunction "D_D") (pintype "passive"))
      (node (ref "Q156") (pin "G") (pinfunction "G_G") (pintype "passive"))
      (node (ref "R175") (pin "1") (pinfunction "1_1") (pintype "passive"))
      (node (ref "R176") (pin "1") (pinfunction "1_1") (pintype "passive"))
      (node (ref "R177") (pin "1") (pinfunction "1_1") (pintype "passive"))
    )
    (net (code "332") (name "Net-(Q154-PadS)") (class "Default")
      (node (ref "Q154") (pin "S") (pinfunction "S_S") (pintype "passive"))
      (node (ref "Q155") (pin "D") (pinfunction "D_D") (pintype "passive"))
    )
    (net (code "333") (name "Net-(Q157-PadD)") (class "Default")
      (node (ref "Q157") (pin "D") (pinfunction "D_D") (pintype "passive"))
      (node (ref "Q159") (pin "G") (pinfunction "G_G") (pintype "passive"))
      (node (ref "R181") (pin "1") (pinfunction "1_1") (pintype "passive"))
      (node (ref "R182") (pin "1") (pinfunction "1_1") (pintype "passive"))
      (node (ref "R189") (pin "1") (pinfunction "1_1") (pintype "passive"))
    )
    (net (code "334") (name "Net-(Q157-PadS)") (class "Default")
      (node (ref "Q157") (pin "S") (pinfunction "S_S") (pintype "passive"))
      (node (ref "Q158") (pin "D") (pinfunction "D_D") (pintype "passive"))
    )
    (net (code "335") (name "Net-(Q159-PadD)") (class "Default")
      (node (ref "Q159") (pin "D") (pinfunction "D_D") (pintype "passive"))
      (node (ref "Q160") (pin "G") (pinfunction "G_G") (pintype "passive"))
      (node (ref "R183") (pin "1") (pinfunction "1_1") (pintype "passive"))
    )
    (net (code "336") (name "Net-(Q161-PadG)") (class "Default")
      (node (ref "Q161") (pin "G") (pinfunction "G_G") (pintype "passive"))
      (node (ref "Q165") (pin "D") (pinfunction "D_D") (pintype "passive"))
      (node (ref "R193") (pin "1") (pinfunction "1_1") (pintype "passive"))
    )
    (net (code "337") (name "Net-(Q163-PadD)") (class "Default")
      (node (ref "Q163") (pin "D") (pinfunction "D_D") (pintype "passive"))
      (node (ref "Q165") (pin "G") (pinfunction "G_G") (pintype "passive"))
      (node (ref "R190") (pin "1") (pinfunction "1_1") (pintype "passive"))
      (node (ref "R191") (pin "1") (pinfunction "1_1") (pintype "passive"))
      (node (ref "R192") (pin "1") (pinfunction "1_1") (pintype "passive"))
    )
    (net (code "338") (name "Net-(Q163-PadS)") (class "Default")
      (node (ref "Q163") (pin "S") (pinfunction "S_S") (pintype "passive"))
      (node (ref "Q164") (pin "D") (pinfunction "D_D") (pintype "passive"))
    )
    (net (code "339") (name "Net-(Q166-PadD)") (class "Default")
      (node (ref "Q166") (pin "D") (pinfunction "D_D") (pintype "passive"))
      (node (ref "Q168") (pin "G") (pinfunction "G_G") (pintype "passive"))
      (node (ref "R196") (pin "1") (pinfunction "1_1") (pintype "passive"))
      (node (ref "R197") (pin "1") (pinfunction "1_1") (pintype "passive"))
      (node (ref "R204") (pin "1") (pinfunction "1_1") (pintype "passive"))
    )
    (net (code "340") (name "Net-(Q166-PadS)") (class "Default")
      (node (ref "Q166") (pin "S") (pinfunction "S_S") (pintype "passive"))
      (node (ref "Q167") (pin "D") (pinfunction "D_D") (pintype "passive"))
    )
    (net (code "341") (name "Net-(Q168-PadD)") (class "Default")
      (node (ref "Q168") (pin "D") (pinfunction "D_D") (pintype "passive"))
      (node (ref "Q169") (pin "G") (pinfunction "G_G") (pintype "passive"))
      (node (ref "R198") (pin "1") (pinfunction "1_1") (pintype "passive"))
    )
    (net (code "342") (name "Net-(Q170-PadG)") (class "Default")
      (node (ref "Q170") (pin "G") (pinfunction "G_G") (pintype "passive"))
      (node (ref "Q174") (pin "D") (pinfunction "D_D") (pintype "passive"))
      (node (ref "R208") (pin "1") (pinfunction "1_1") (pintype "passive"))
    )
    (net (code "343") (name "Net-(Q172-PadD)") (class "Default")
      (node (ref "Q172") (pin "D") (pinfunction "D_D") (pintype "passive"))
      (node (ref "Q174") (pin "G") (pinfunction "G_G") (pintype "passive"))
      (node (ref "R205") (pin "1") (pinfunction "1_1") (pintype "passive"))
      (node (ref "R206") (pin "1") (pinfunction "1_1") (pintype "passive"))
      (node (ref "R207") (pin "1") (pinfunction "1_1") (pintype "passive"))
    )
    (net (code "344") (name "Net-(Q172-PadS)") (class "Default")
      (node (ref "Q172") (pin "S") (pinfunction "S_S") (pintype "passive"))
      (node (ref "Q173") (pin "D") (pinfunction "D_D") (pintype "passive"))
    )
    (net (code "345") (name "Net-(Q175-PadD)") (class "Default")
      (node (ref "Q175") (pin "D") (pinfunction "D_D") (pintype "passive"))
      (node (ref "Q177") (pin "G") (pinfunction "G_G") (pintype "passive"))
      (node (ref "R211") (pin "1") (pinfunction "1_1") (pintype "passive"))
      (node (ref "R212") (pin "1") (pinfunction "1_1") (pintype "passive"))
      (node (ref "R219") (pin "1") (pinfunction "1_1") (pintype "passive"))
    )
    (net (code "346") (name "Net-(Q175-PadS)") (class "Default")
      (node (ref "Q175") (pin "S") (pinfunction "S_S") (pintype "passive"))
      (node (ref "Q176") (pin "D") (pinfunction "D_D") (pintype "passive"))
    )
    (net (code "347") (name "Net-(Q177-PadD)") (class "Default")
      (node (ref "Q177") (pin "D") (pinfunction "D_D") (pintype "passive"))
      (node (ref "Q178") (pin "G") (pinfunction "G_G") (pintype "passive"))
      (node (ref "R213") (pin "1") (pinfunction "1_1") (pintype "passive"))
    )
    (net (code "348") (name "Net-(Q179-PadG)") (class "Default")
      (node (ref "Q179") (pin "G") (pinfunction "G_G") (pintype "passive"))
      (node (ref "Q183") (pin "D") (pinfunction "D_D") (pintype "passive"))
      (node (ref "R223") (pin "1") (pinfunction "1_1") (pintype "passive"))
    )
    (net (code "349") (name "Net-(Q181-PadD)") (class "Default")
      (node (ref "Q181") (pin "D") (pinfunction "D_D") (pintype "passive"))
      (node (ref "Q183") (pin "G") (pinfunction "G_G") (pintype "passive"))
      (node (ref "R220") (pin "1") (pinfunction "1_1") (pintype "passive"))
      (node (ref "R221") (pin "1") (pinfunction "1_1") (pintype "passive"))
      (node (ref "R222") (pin "1") (pinfunction "1_1") (pintype "passive"))
    )
    (net (code "350") (name "Net-(Q181-PadS)") (class "Default")
      (node (ref "Q181") (pin "S") (pinfunction "S_S") (pintype "passive"))
      (node (ref "Q182") (pin "D") (pinfunction "D_D") (pintype "passive"))
    )
    (net (code "351") (name "Net-(Q184-PadD)") (class "Default")
      (node (ref "Q184") (pin "D") (pinfunction "D_D") (pintype "passive"))
      (node (ref "Q186") (pin "G") (pinfunction "G_G") (pintype "passive"))
      (node (ref "R226") (pin "1") (pinfunction "1_1") (pintype "passive"))
      (node (ref "R227") (pin "1") (pinfunction "1_1") (pintype "passive"))
      (node (ref "R234") (pin "1") (pinfunction "1_1") (pintype "passive"))
    )
    (net (code "352") (name "Net-(Q184-PadS)") (class "Default")
      (node (ref "Q184") (pin "S") (pinfunction "S_S") (pintype "passive"))
      (node (ref "Q185") (pin "D") (pinfunction "D_D") (pintype "passive"))
    )
    (net (code "353") (name "Net-(Q186-PadD)") (class "Default")
      (node (ref "Q186") (pin "D") (pinfunction "D_D") (pintype "passive"))
      (node (ref "Q187") (pin "G") (pinfunction "G_G") (pintype "passive"))
      (node (ref "R228") (pin "1") (pinfunction "1_1") (pintype "passive"))
    )
    (net (code "354") (name "Net-(Q188-PadG)") (class "Default")
      (node (ref "Q188") (pin "G") (pinfunction "G_G") (pintype "passive"))
      (node (ref "Q192") (pin "D") (pinfunction "D_D") (pintype "passive"))
      (node (ref "R238") (pin "1") (pinfunction "1_1") (pintype "passive"))
    )
    (net (code "355") (name "Net-(Q190-PadD)") (class "Default")
      (node (ref "Q190") (pin "D") (pinfunction "D_D") (pintype "passive"))
      (node (ref "Q192") (pin "G") (pinfunction "G_G") (pintype "passive"))
      (node (ref "R235") (pin "1") (pinfunction "1_1") (pintype "passive"))
      (node (ref "R236") (pin "1") (pinfunction "1_1") (pintype "passive"))
      (node (ref "R237") (pin "1") (pinfunction "1_1") (pintype "passive"))
    )
    (net (code "356") (name "Net-(Q190-PadS)") (class "Default")
      (node (ref "Q190") (pin "S") (pinfunction "S_S") (pintype "passive"))
      (node (ref "Q191") (pin "D") (pinfunction "D_D") (pintype "passive"))
    )
    (net (code "357") (name "Y0") (class "Default")
      (node (ref "J3") (pin "2") (pinfunction "2_2") (pintype "bidirectional"))
      (node (ref "J4") (pin "20") (pinfunction "20_20") (pintype "bidirectional"))
      (node (ref "Q31") (pin "D") (pinfunction "D_D") (pintype "passive"))
      (node (ref "R33") (pin "1") (pinfunction "1_1") (pintype "passive"))
    )
    (net (code "358") (name "Y0_N") (class "Default")
      (node (ref "Q27") (pin "D") (pinfunction "D_D") (pintype "passive"))
      (node (ref "Q29") (pin "D") (pinfunction "D_D") (pintype "passive"))
      (node (ref "Q31") (pin "G") (pinfunction "G_G") (pintype "passive"))
      (node (ref "R277") (pin "1") (pinfunction "1_1") (pintype "passive"))
      (node (ref "R31") (pin "1") (pinfunction "1_1") (pintype "passive"))
      (node (ref "R32") (pin "1") (pinfunction "1_1") (pintype "passive"))
    )
    (net (code "359") (name "Y1") (class "Default")
      (node (ref "J3") (pin "3") (pinfunction "3_3") (pintype "bidirectional"))
      (node (ref "J4") (pin "21") (pinfunction "21_21") (pintype "bidirectional"))
      (node (ref "Q41") (pin "D") (pinfunction "D_D") (pintype "passive"))
      (node (ref "R43") (pin "1") (pinfunction "1_1") (pintype "passive"))
    )
    (net (code "360") (name "Y1_N") (class "Default")
      (node (ref "Q37") (pin "D") (pinfunction "D_D") (pintype "passive"))
      (node (ref "Q39") (pin "D") (pinfunction "D_D") (pintype "passive"))
      (node (ref "Q41") (pin "G") (pinfunction "G_G") (pintype "passive"))
      (node (ref "R278") (pin "1") (pinfunction "1_1") (pintype "passive"))
      (node (ref "R41") (pin "1") (pinfunction "1_1") (pintype "passive"))
      (node (ref "R42") (pin "1") (pinfunction "1_1") (pintype "passive"))
    )
    (net (code "361") (name "Y2") (class "Default")
      (node (ref "J3") (pin "4") (pinfunction "4_4") (pintype "bidirectional"))
      (node (ref "J4") (pin "22") (pinfunction "22_22") (pintype "bidirectional"))
      (node (ref "Q88") (pin "D") (pinfunction "D_D") (pintype "passive"))
      (node (ref "R98") (pin "1") (pinfunction "1_1") (pintype "passive"))
    )
    (net (code "362") (name "Y2_N") (class "Default")
      (node (ref "Q84") (pin "D") (pinfunction "D_D") (pintype "passive"))
      (node (ref "Q86") (pin "D") (pinfunction "D_D") (pintype "passive"))
      (node (ref "Q88") (pin "G") (pinfunction "G_G") (pintype "passive"))
      (node (ref "R279") (pin "1") (pinfunction "1_1") (pintype "passive"))
      (node (ref "R96") (pin "1") (pinfunction "1_1") (pintype "passive"))
      (node (ref "R97") (pin "1") (pinfunction "1_1") (pintype "passive"))
    )
    (net (code "363") (name "Y3") (class "Default")
      (node (ref "J3") (pin "5") (pinfunction "5_5") (pintype "bidirectional"))
      (node (ref "J4") (pin "23") (pinfunction "23_23") (pintype "bidirectional"))
      (node (ref "Q98") (pin "D") (pinfunction "D_D") (pintype "passive"))
      (node (ref "R108") (pin "1") (pinfunction "1_1") (pintype "passive"))
    )
    (net (code "364") (name "Y3_N") (class "Default")
      (node (ref "Q94") (pin "D") (pinfunction "D_D") (pintype "passive"))
      (node (ref "Q96") (pin "D") (pinfunction "D_D") (pintype "passive"))
      (node (ref "Q98") (pin "G") (pinfunction "G_G") (pintype "passive"))
      (node (ref "R106") (pin "1") (pinfunction "1_1") (pintype "passive"))
      (node (ref "R107") (pin "1") (pinfunction "1_1") (pintype "passive"))
      (node (ref "R280") (pin "1") (pinfunction "1_1") (pintype "passive"))
    )
    (net (code "365") (name "Y4") (class "Default")
      (node (ref "J3") (pin "6") (pinfunction "6_6") (pintype "bidirectional"))
      (node (ref "J4") (pin "24") (pinfunction "24_24") (pintype "bidirectional"))
      (node (ref "Q108") (pin "D") (pinfunction "D_D") (pintype "passive"))
      (node (ref "R118") (pin "1") (pinfunction "1_1") (pintype "passive"))
    )
    (net (code "366") (name "Y4_N") (class "Default")
      (node (ref "Q104") (pin "D") (pinfunction "D_D") (pintype "passive"))
      (node (ref "Q106") (pin "D") (pinfunction "D_D") (pintype "passive"))
      (node (ref "Q108") (pin "G") (pinfunction "G_G") (pintype "passive"))
      (node (ref "R116") (pin "1") (pinfunction "1_1") (pintype "passive"))
      (node (ref "R117") (pin "1") (pinfunction "1_1") (pintype "passive"))
      (node (ref "R281") (pin "1") (pinfunction "1_1") (pintype "passive"))
    )
    (net (code "367") (name "Y5") (class "Default")
      (node (ref "J3") (pin "7") (pinfunction "7_7") (pintype "bidirectional"))
      (node (ref "J4") (pin "25") (pinfunction "25_25") (pintype "bidirectional"))
      (node (ref "Q118") (pin "D") (pinfunction "D_D") (pintype "passive"))
      (node (ref "R128") (pin "1") (pinfunction "1_1") (pintype "passive"))
    )
    (net (code "368") (name "Y5_N") (class "Default")
      (node (ref "Q114") (pin "D") (pinfunction "D_D") (pintype "passive"))
      (node (ref "Q116") (pin "D") (pinfunction "D_D") (pintype "passive"))
      (node (ref "Q118") (pin "G") (pinfunction "G_G") (pintype "passive"))
      (node (ref "R126") (pin "1") (pinfunction "1_1") (pintype "passive"))
      (node (ref "R127") (pin "1") (pinfunction "1_1") (pintype "passive"))
      (node (ref "R282") (pin "1") (pinfunction "1_1") (pintype "passive"))
    )
    (net (code "369") (name "Y6") (class "Default")
      (node (ref "J3") (pin "8") (pinfunction "8_8") (pintype "bidirectional"))
      (node (ref "J4") (pin "26") (pinfunction "26_26") (pintype "bidirectional"))
      (node (ref "Q128") (pin "D") (pinfunction "D_D") (pintype "passive"))
      (node (ref "R138") (pin "1") (pinfunction "1_1") (pintype "passive"))
    )
    (net (code "370") (name "Y6_N") (class "Default")
      (node (ref "Q124") (pin "D") (pinfunction "D_D") (pintype "passive"))
      (node (ref "Q126") (pin "D") (pinfunction "D_D") (pintype "passive"))
      (node (ref "Q128") (pin "G") (pinfunction "G_G") (pintype "passive"))
      (node (ref "R136") (pin "1") (pinfunction "1_1") (pintype "passive"))
      (node (ref "R137") (pin "1") (pinfunction "1_1") (pintype "passive"))
      (node (ref "R283") (pin "1") (pinfunction "1_1") (pintype "passive"))
    )
    (net (code "371") (name "Y7") (class "Default")
      (node (ref "J3") (pin "9") (pinfunction "9_9") (pintype "bidirectional"))
      (node (ref "J4") (pin "27") (pinfunction "27_27") (pintype "bidirectional"))
      (node (ref "Q138") (pin "D") (pinfunction "D_D") (pintype "passive"))
      (node (ref "R148") (pin "1") (pinfunction "1_1") (pintype "passive"))
    )
    (net (code "372") (name "Y7_N") (class "Default")
      (node (ref "Q134") (pin "D") (pinfunction "D_D") (pintype "passive"))
      (node (ref "Q136") (pin "D") (pinfunction "D_D") (pintype "passive"))
      (node (ref "Q138") (pin "G") (pinfunction "G_G") (pintype "passive"))
      (node (ref "R146") (pin "1") (pinfunction "1_1") (pintype "passive"))
      (node (ref "R147") (pin "1") (pinfunction "1_1") (pintype "passive"))
      (node (ref "R284") (pin "1") (pinfunction "1_1") (pintype "passive"))
    )
    (net (code "373") (name "unconnected-(J1-Pad12)") (class "Default")
      (node (ref "J1") (pin "12") (pinfunction "12_12") (pintype "bidirectional"))
    )
    (net (code "374") (name "unconnected-(J1-Pad13)") (class "Default")
      (node (ref "J1") (pin "13") (pinfunction "13_13") (pintype "bidirectional"))
    )
    (net (code "375") (name "unconnected-(J1-Pad14)") (class "Default")
      (node (ref "J1") (pin "14") (pinfunction "14_14") (pintype "bidirectional"))
    )
    (net (code "376") (name "unconnected-(J1-Pad15)") (class "Default")
      (node (ref "J1") (pin "15") (pinfunction "15_15") (pintype "bidirectional"))
    )
    (net (code "377") (name "unconnected-(J1-Pad16)") (class "Default")
      (node (ref "J1") (pin "16") (pinfunction "16_16") (pintype "bidirectional"))
    )
    (net (code "378") (name "unconnected-(J1-Pad17)") (class "Default")
      (node (ref "J1") (pin "17") (pinfunction "17_17") (pintype "bidirectional"))
    )
    (net (code "379") (name "unconnected-(J1-Pad18)") (class "Default")
      (node (ref "J1") (pin "18") (pinfunction "18_18") (pintype "bidirectional"))
    )
    (net (code "380") (name "unconnected-(J1-Pad19)") (class "Default")
      (node (ref "J1") (pin "19") (pinfunction "19_19") (pintype "bidirectional"))
    )
    (net (code "381") (name "unconnected-(J2-Pad12)") (class "Default")
      (node (ref "J2") (pin "12") (pinfunction "12_12") (pintype "bidirectional"))
    )
    (net (code "382") (name "unconnected-(J2-Pad13)") (class "Default")
      (node (ref "J2") (pin "13") (pinfunction "13_13") (pintype "bidirectional"))
    )
    (net (code "383") (name "unconnected-(J2-Pad14)") (class "Default")
      (node (ref "J2") (pin "14") (pinfunction "14_14") (pintype "bidirectional"))
    )
    (net (code "384") (name "unconnected-(J2-Pad15)") (class "Default")
      (node (ref "J2") (pin "15") (pinfunction "15_15") (pintype "bidirectional"))
    )
    (net (code "385") (name "unconnected-(J2-Pad16)") (class "Default")
      (node (ref "J2") (pin "16") (pinfunction "16_16") (pintype "bidirectional"))
    )
    (net (code "386") (name "unconnected-(J2-Pad17)") (class "Default")
      (node (ref "J2") (pin "17") (pinfunction "17_17") (pintype "bidirectional"))
    )
    (net (code "387") (name "unconnected-(J2-Pad18)") (class "Default")
      (node (ref "J2") (pin "18") (pinfunction "18_18") (pintype "bidirectional"))
    )
    (net (code "388") (name "unconnected-(J2-Pad19)") (class "Default")
      (node (ref "J2") (pin "19") (pinfunction "19_19") (pintype "bidirectional"))
    )
    (net (code "389") (name "unconnected-(J3-Pad12)") (class "Default")
      (node (ref "J3") (pin "12") (pinfunction "12_12") (pintype "bidirectional"))
    )
    (net (code "390") (name "unconnected-(J3-Pad13)") (class "Default")
      (node (ref "J3") (pin "13") (pinfunction "13_13") (pintype "bidirectional"))
    )
    (net (code "391") (name "unconnected-(J3-Pad14)") (class "Default")
      (node (ref "J3") (pin "14") (pinfunction "14_14") (pintype "bidirectional"))
    )
    (net (code "392") (name "unconnected-(J3-Pad15)") (class "Default")
      (node (ref "J3") (pin "15") (pinfunction "15_15") (pintype "bidirectional"))
    )
    (net (code "393") (name "unconnected-(J3-Pad16)") (class "Default")
      (node (ref "J3") (pin "16") (pinfunction "16_16") (pintype "bidirectional"))
    )
    (net (code "394") (name "unconnected-(J3-Pad17)") (class "Default")
      (node (ref "J3") (pin "17") (pinfunction "17_17") (pintype "bidirectional"))
    )
    (net (code "395") (name "unconnected-(J3-Pad18)") (class "Default")
      (node (ref "J3") (pin "18") (pinfunction "18_18") (pintype "bidirectional"))
    )
    (net (code "396") (name "unconnected-(J3-Pad19)") (class "Default")
      (node (ref "J3") (pin "19") (pinfunction "19_19") (pintype "bidirectional"))
    )
    (net (code "397") (name "unconnected-(J4-Pad29)") (class "Default")
      (node (ref "J4") (pin "29") (pinfunction "29_29") (pintype "bidirectional"))
    )
    (net (code "398") (name "unconnected-(J4-Pad30)") (class "Default")
      (node (ref "J4") (pin "30") (pinfunction "30_30") (pintype "bidirectional"))
    )
  )
)
